# ESP32-POV.net
KiCad netlist of a schematic drawn in EAGLE
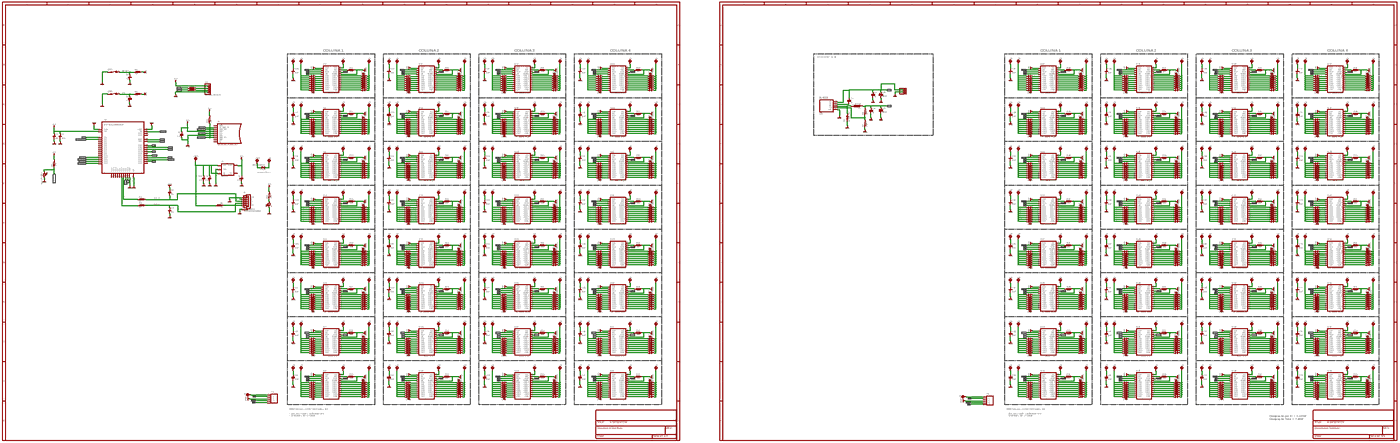
[diagram p0: schematic, sheet 1, overview]
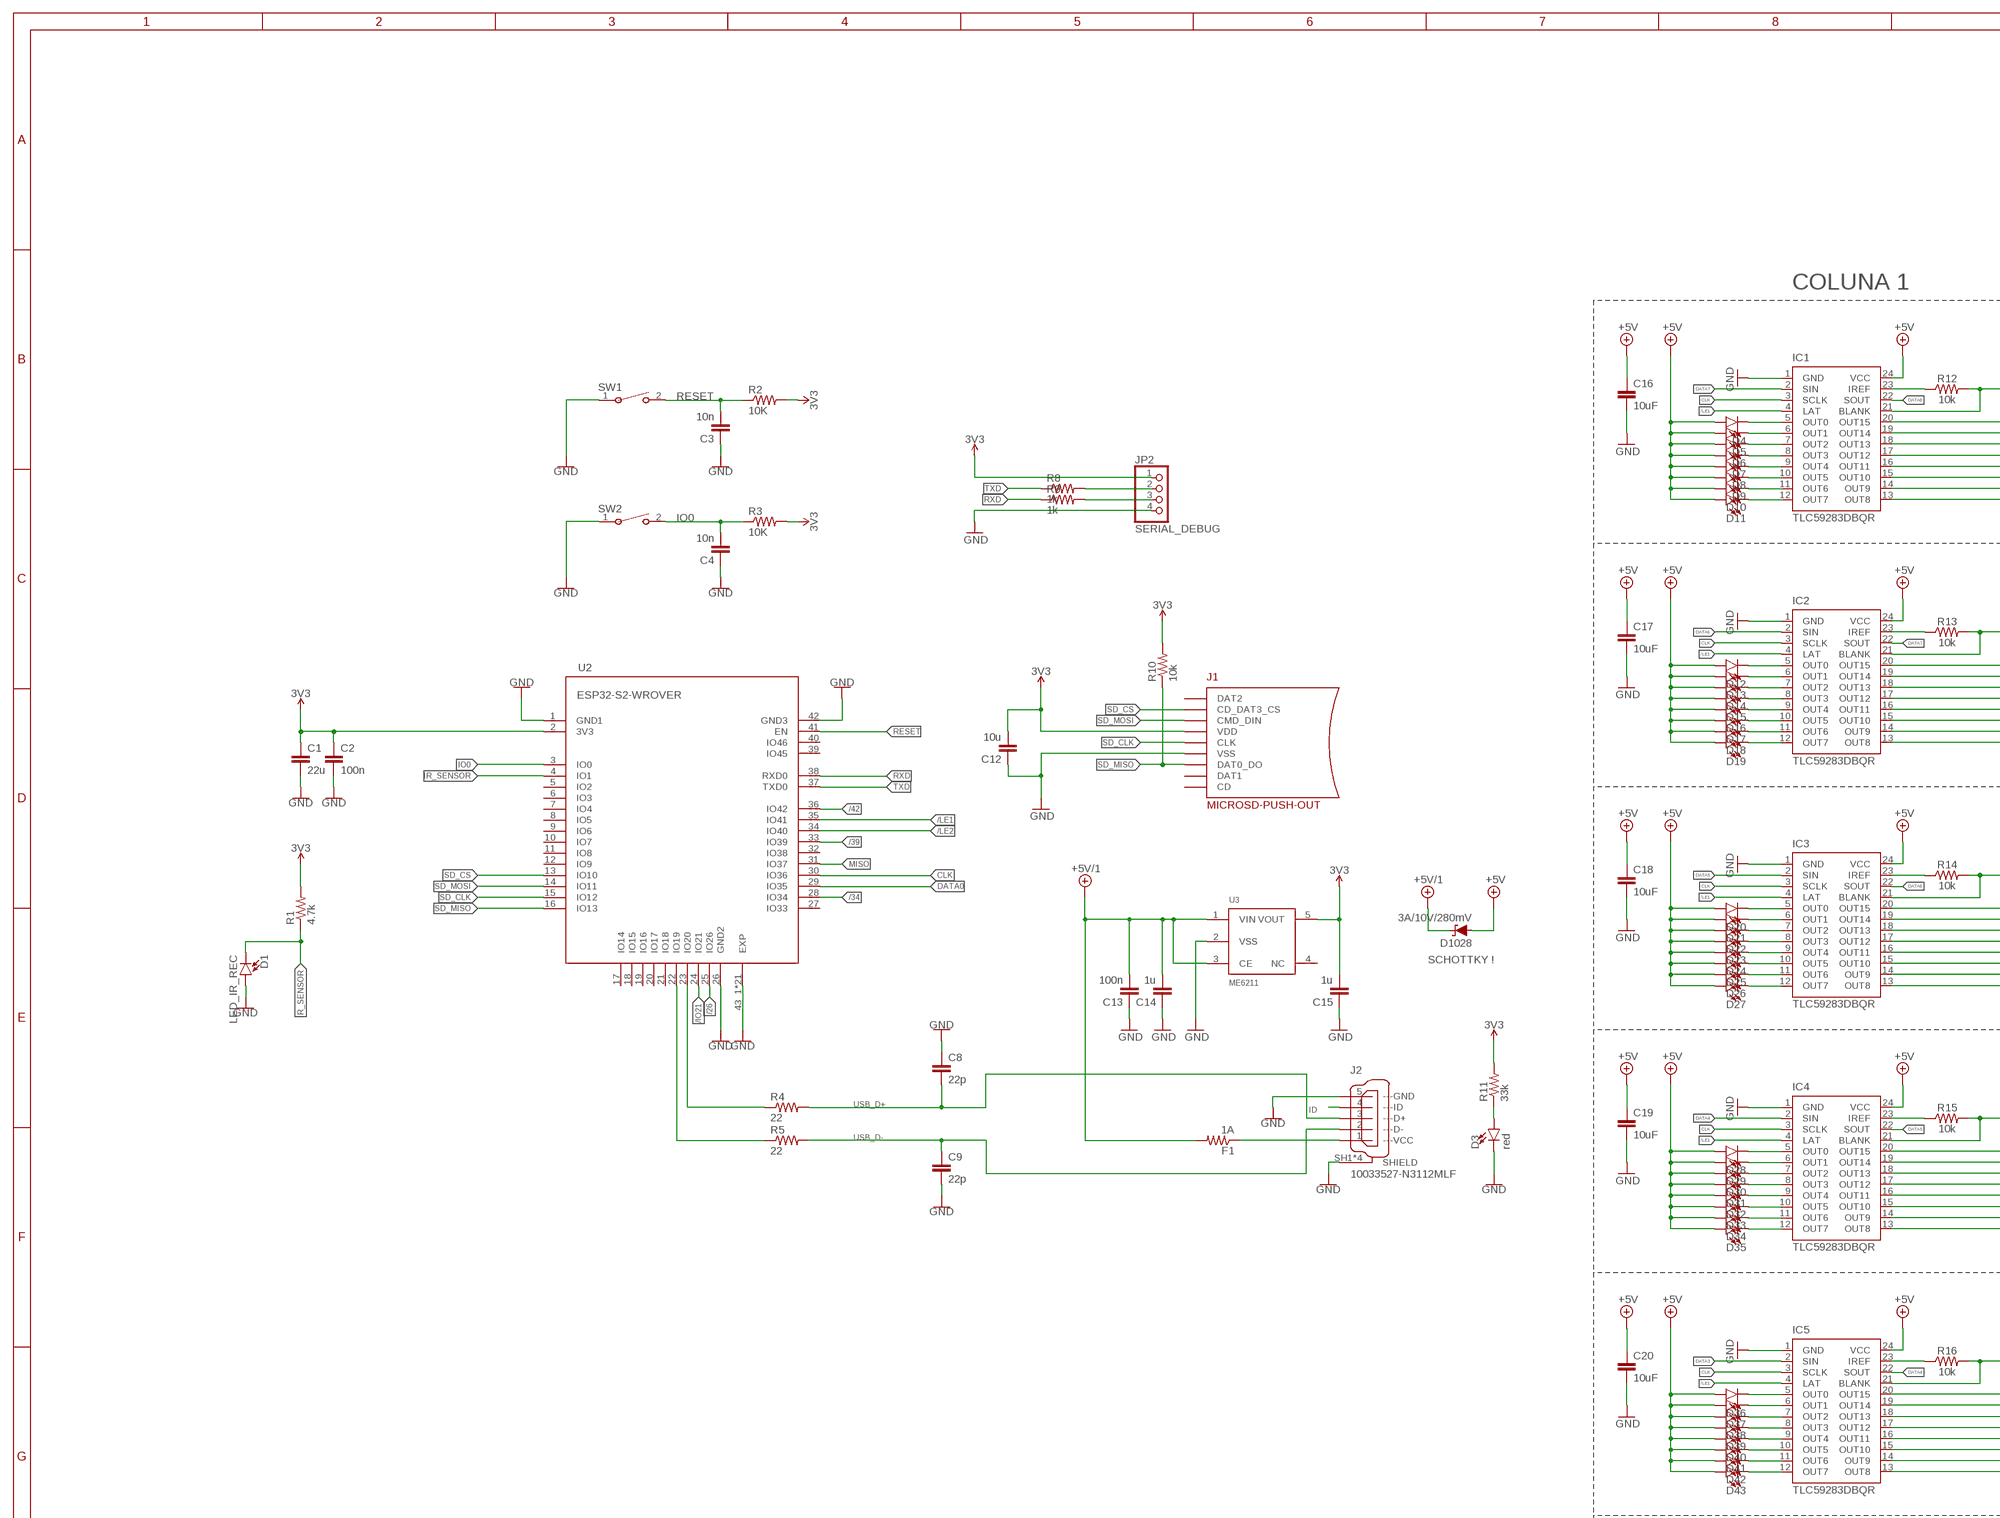
[diagram p1: schematic, sheet 1, part 1 of 8]
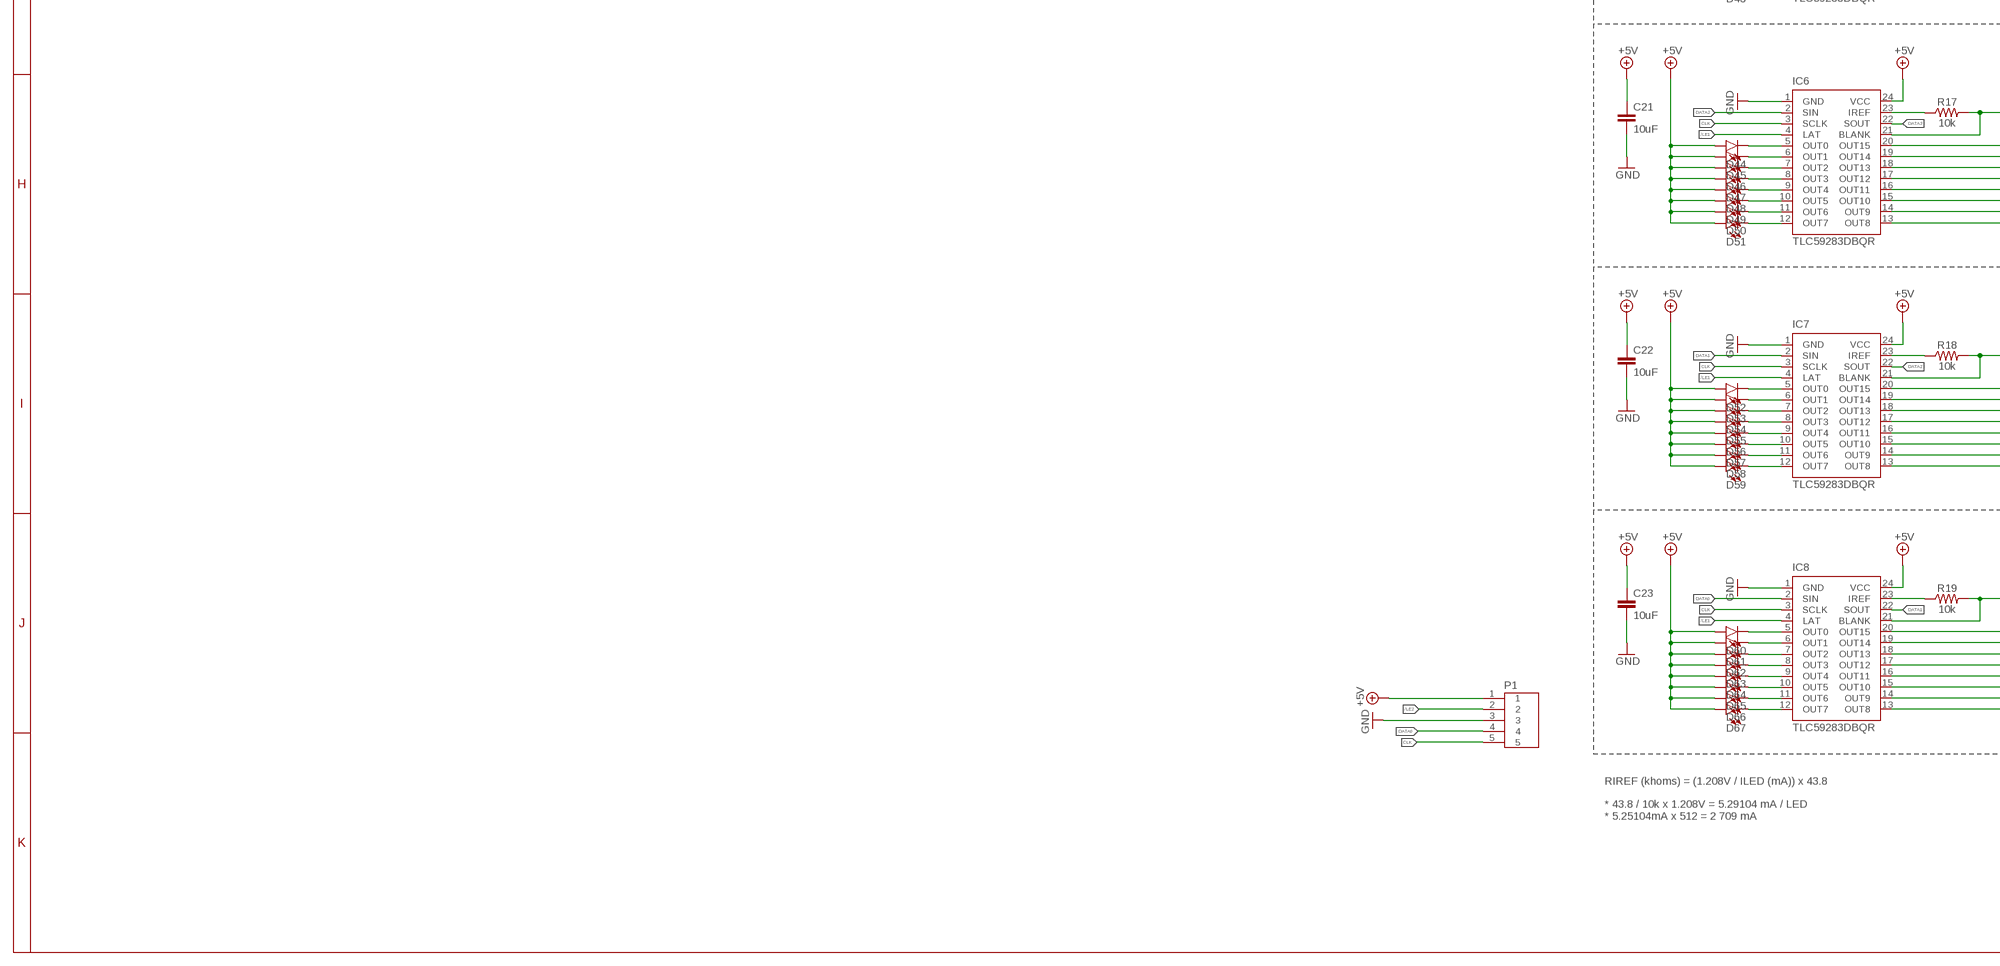
[diagram p2: schematic, sheet 1, part 2 of 8]
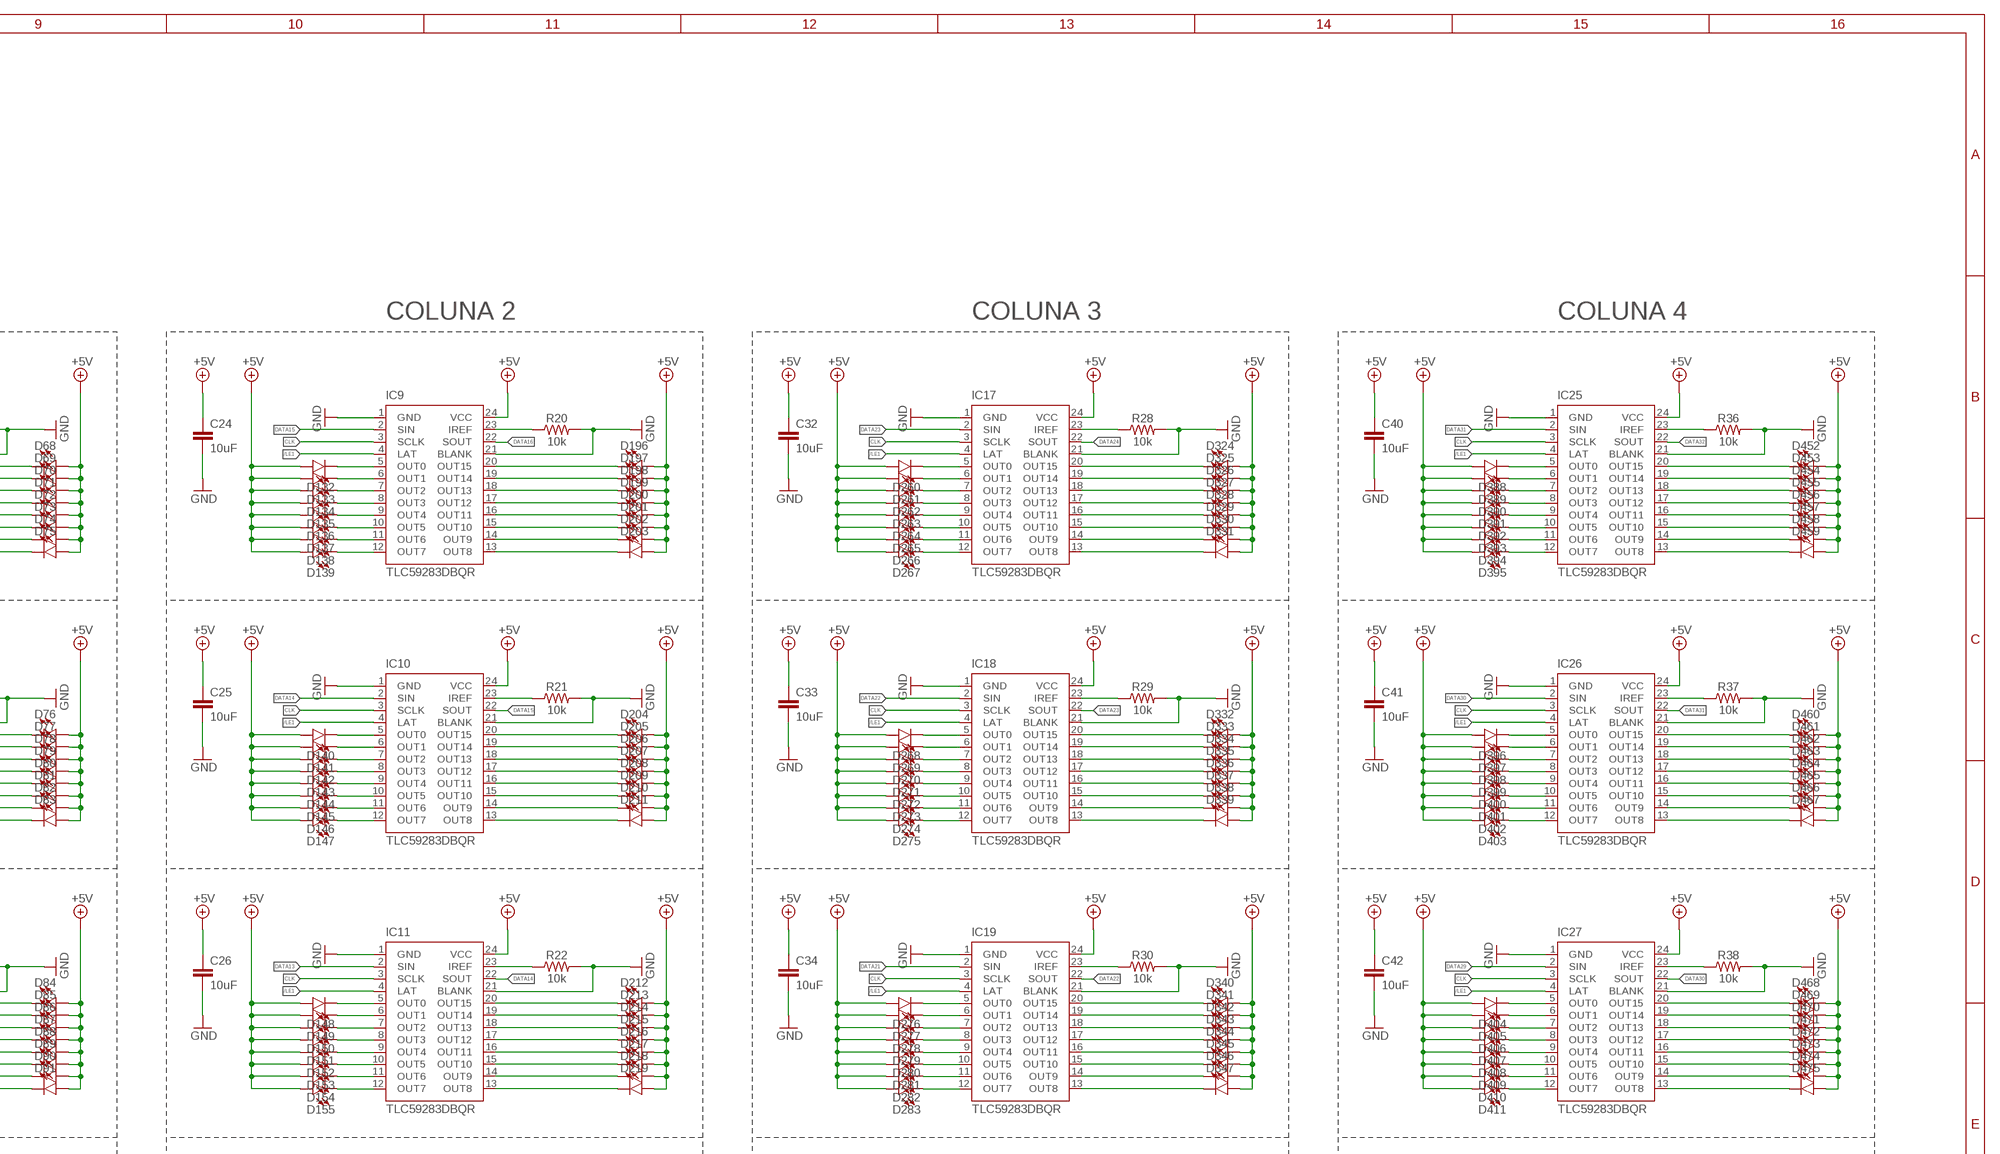
[diagram p3: schematic, sheet 1, part 3 of 8]
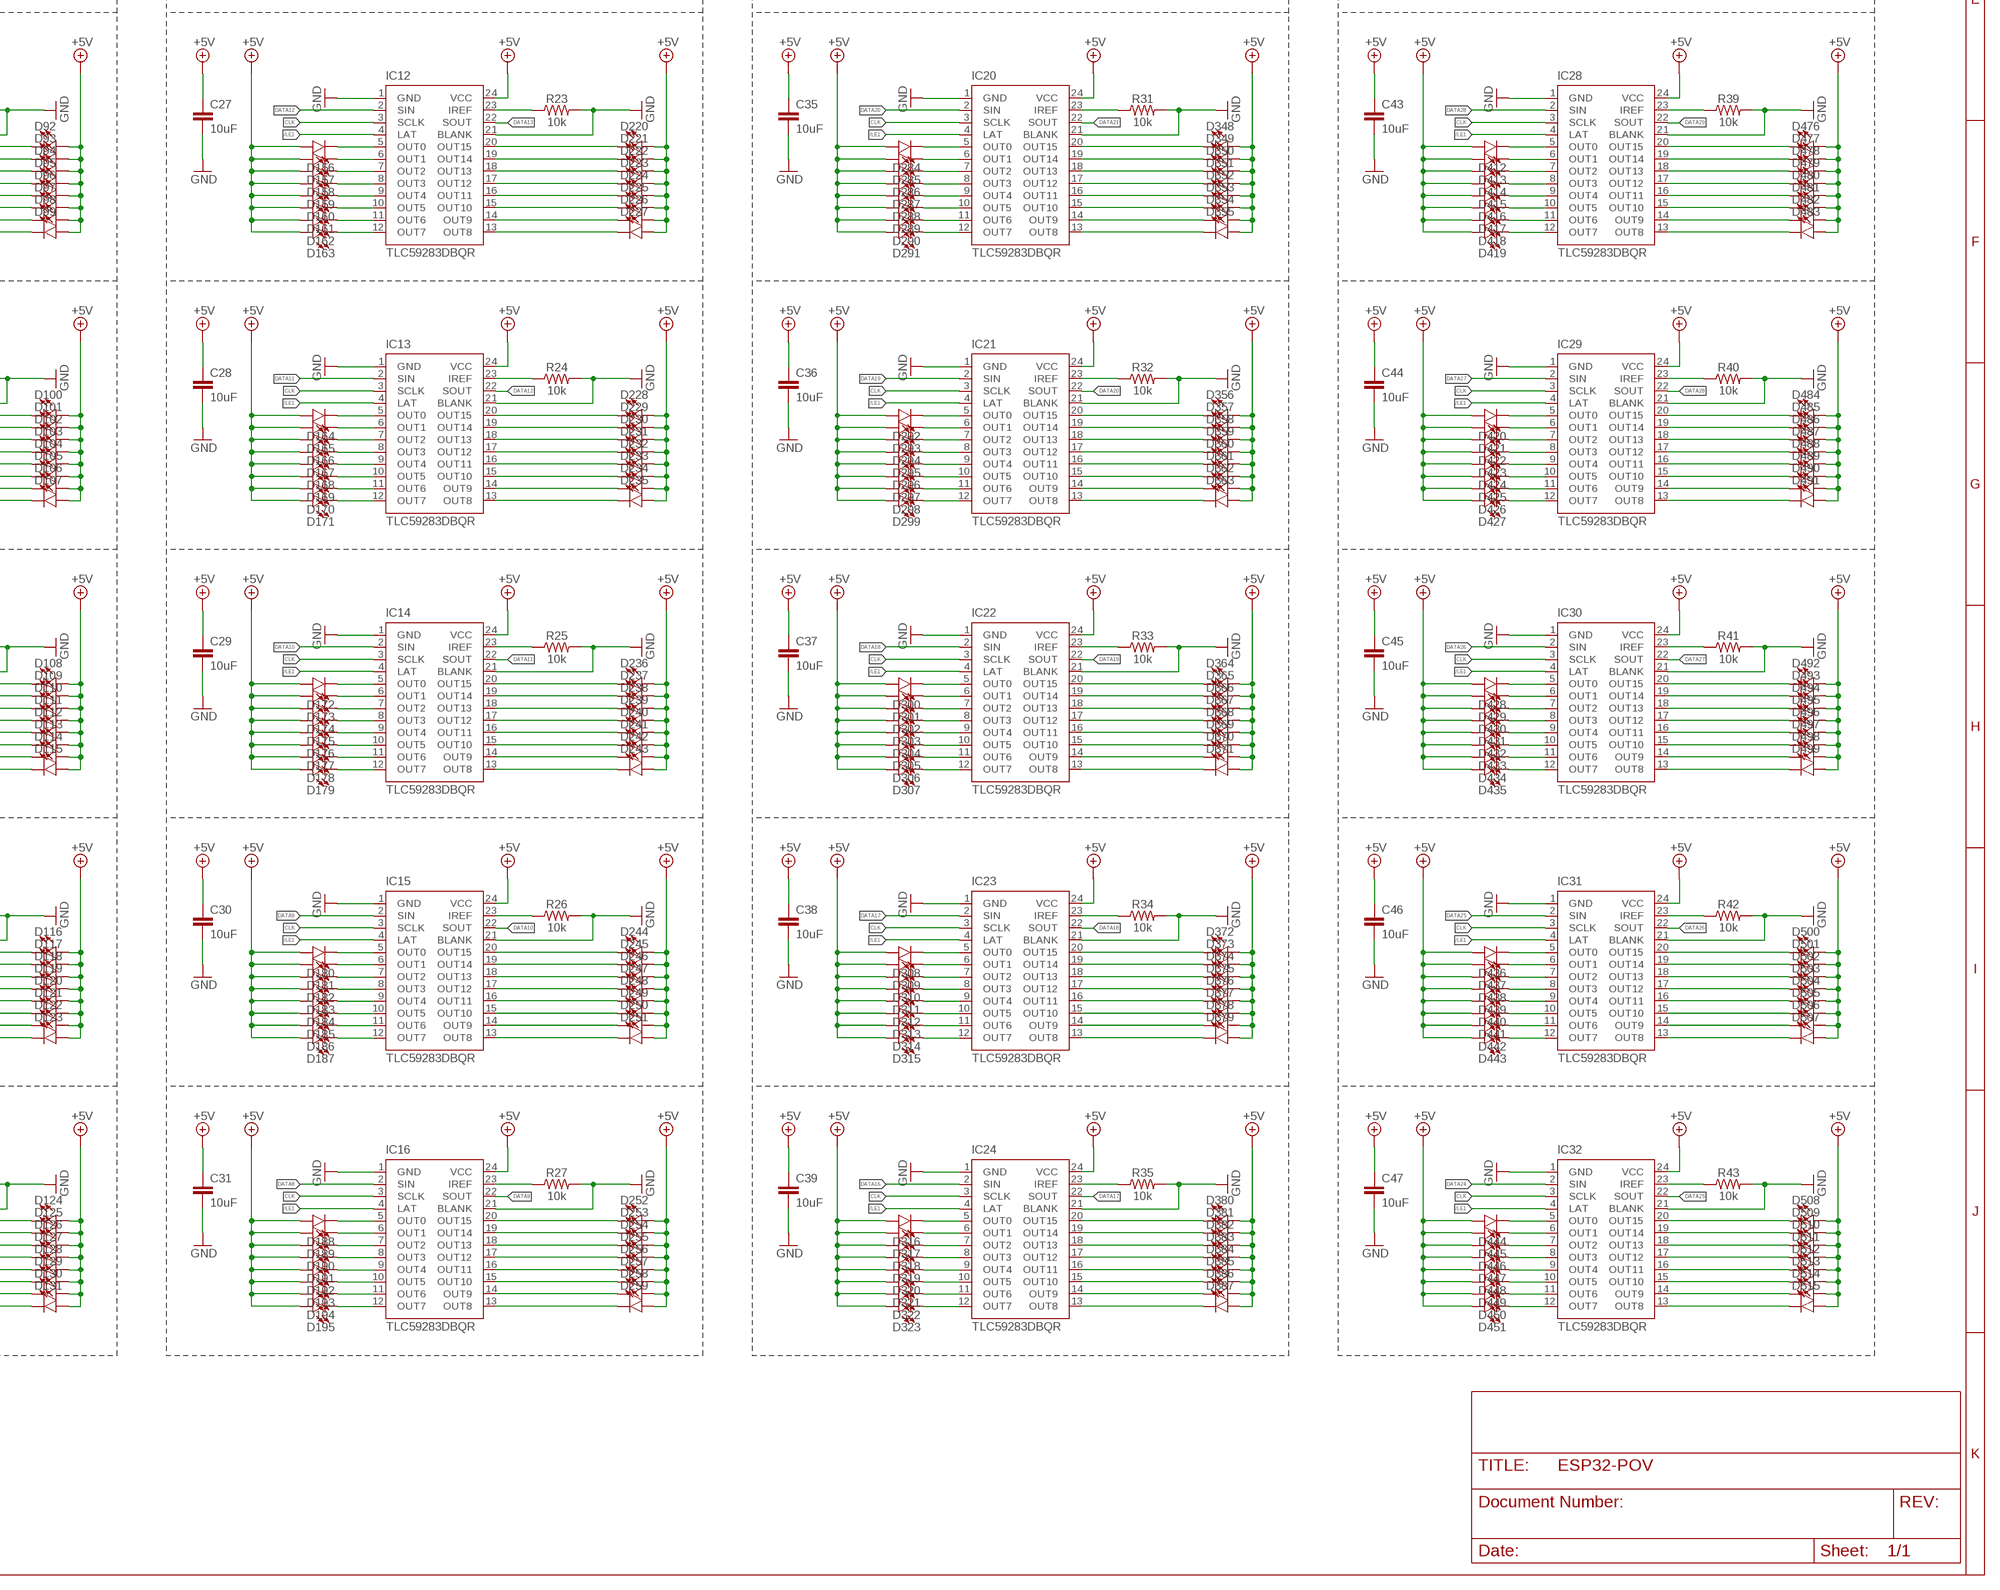
[diagram p4: schematic, sheet 1, part 4 of 8]
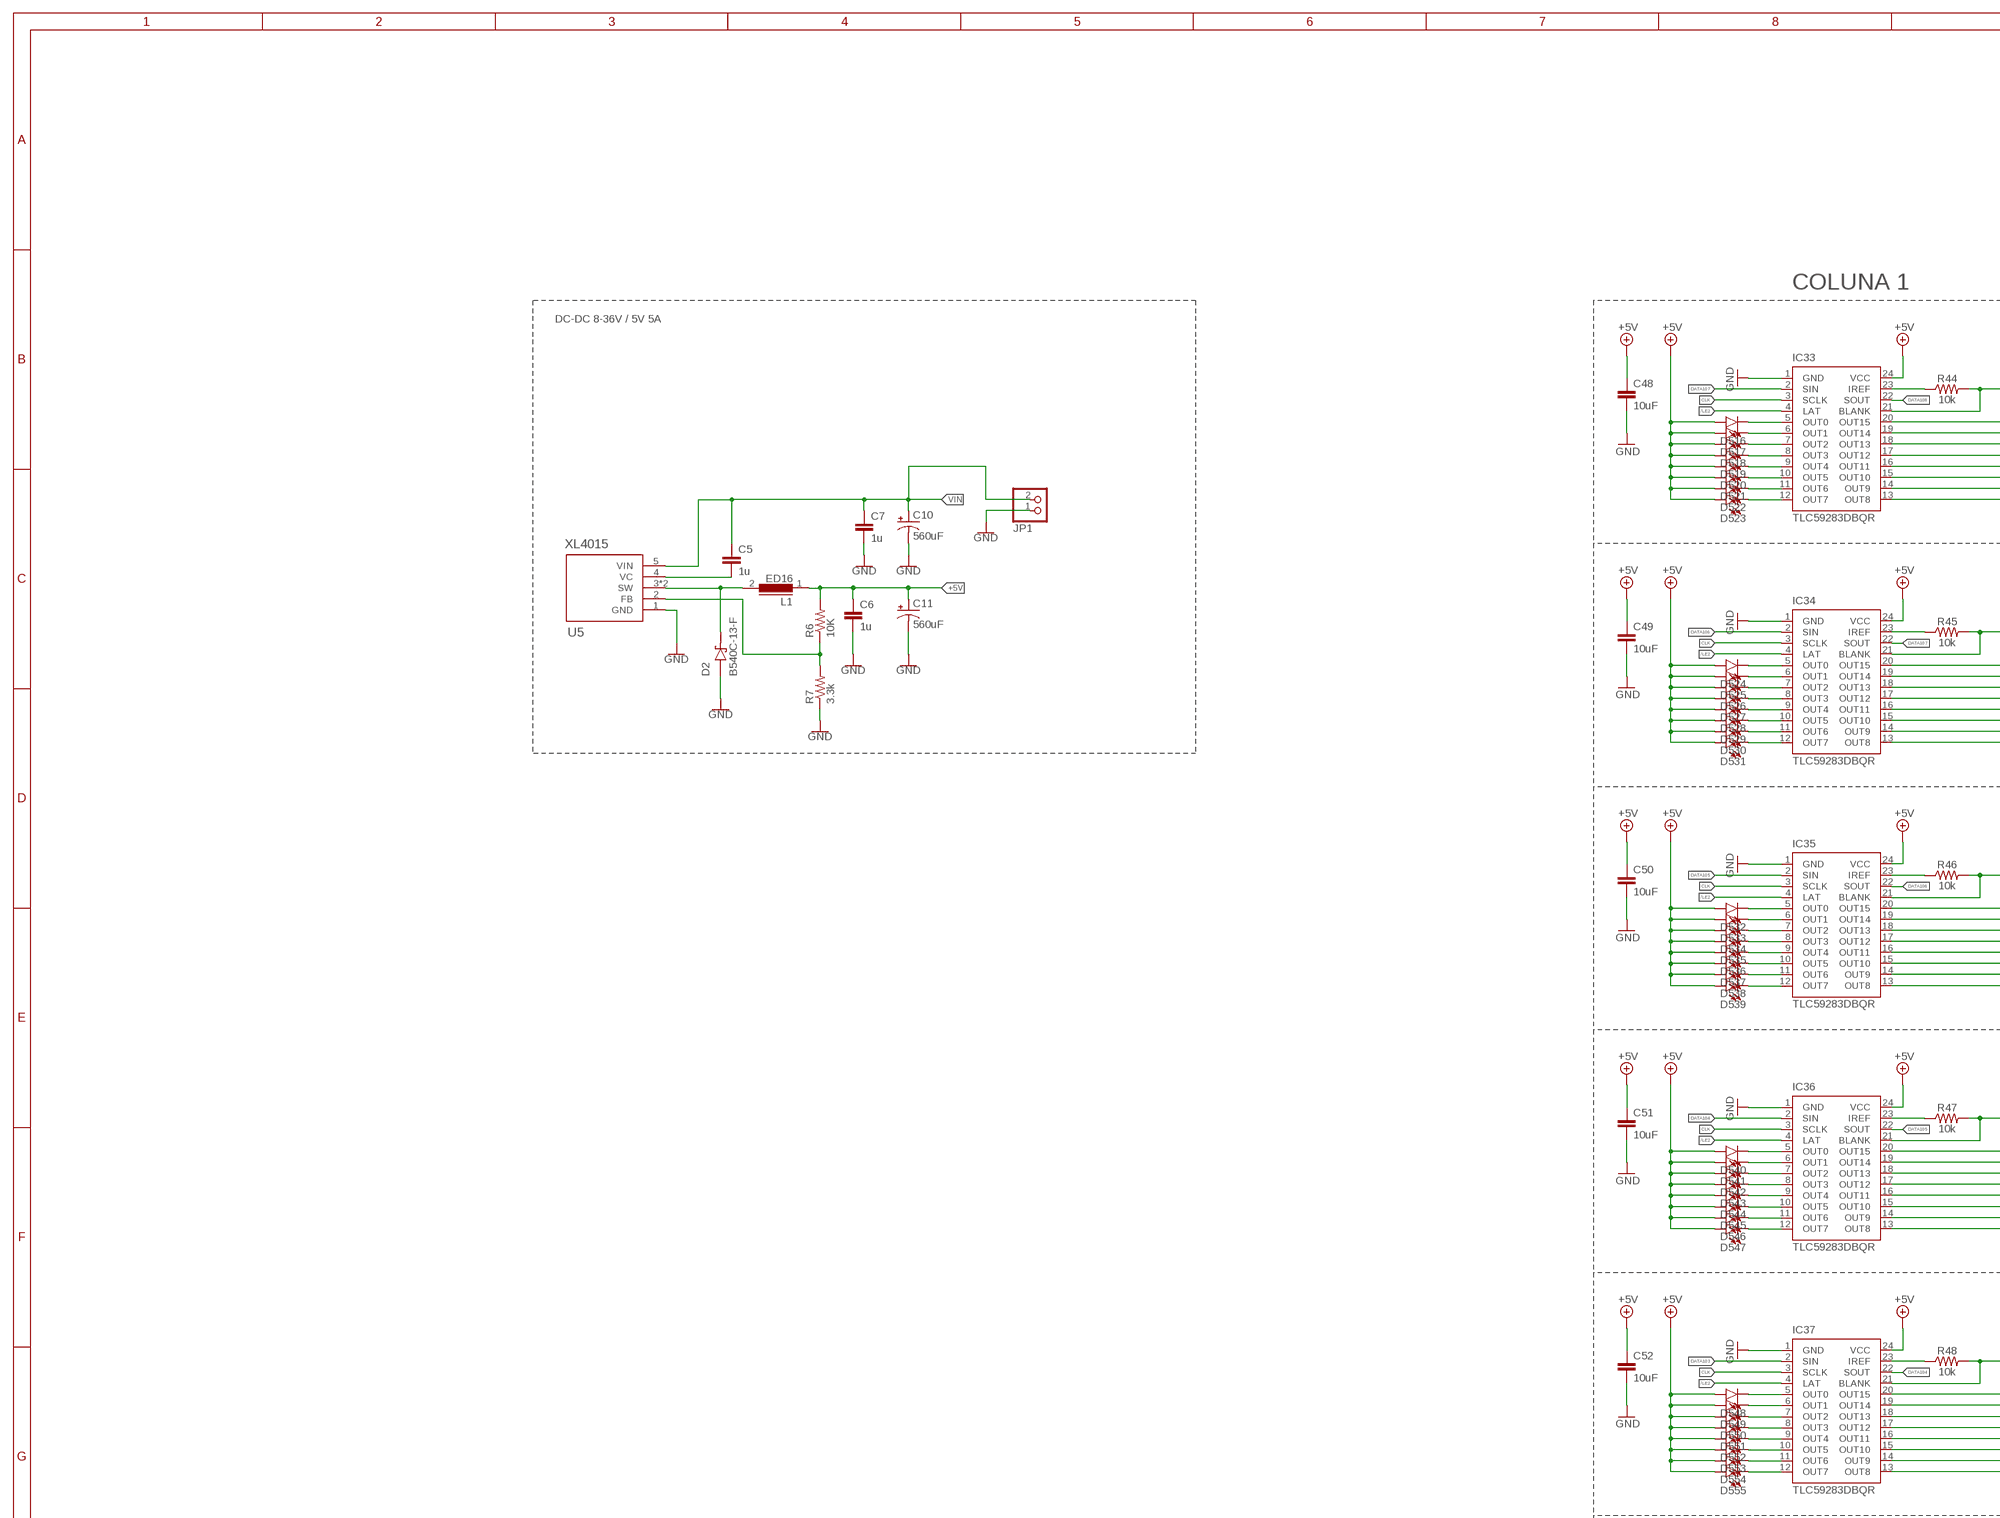
[diagram p5: schematic, sheet 1, part 5 of 8]
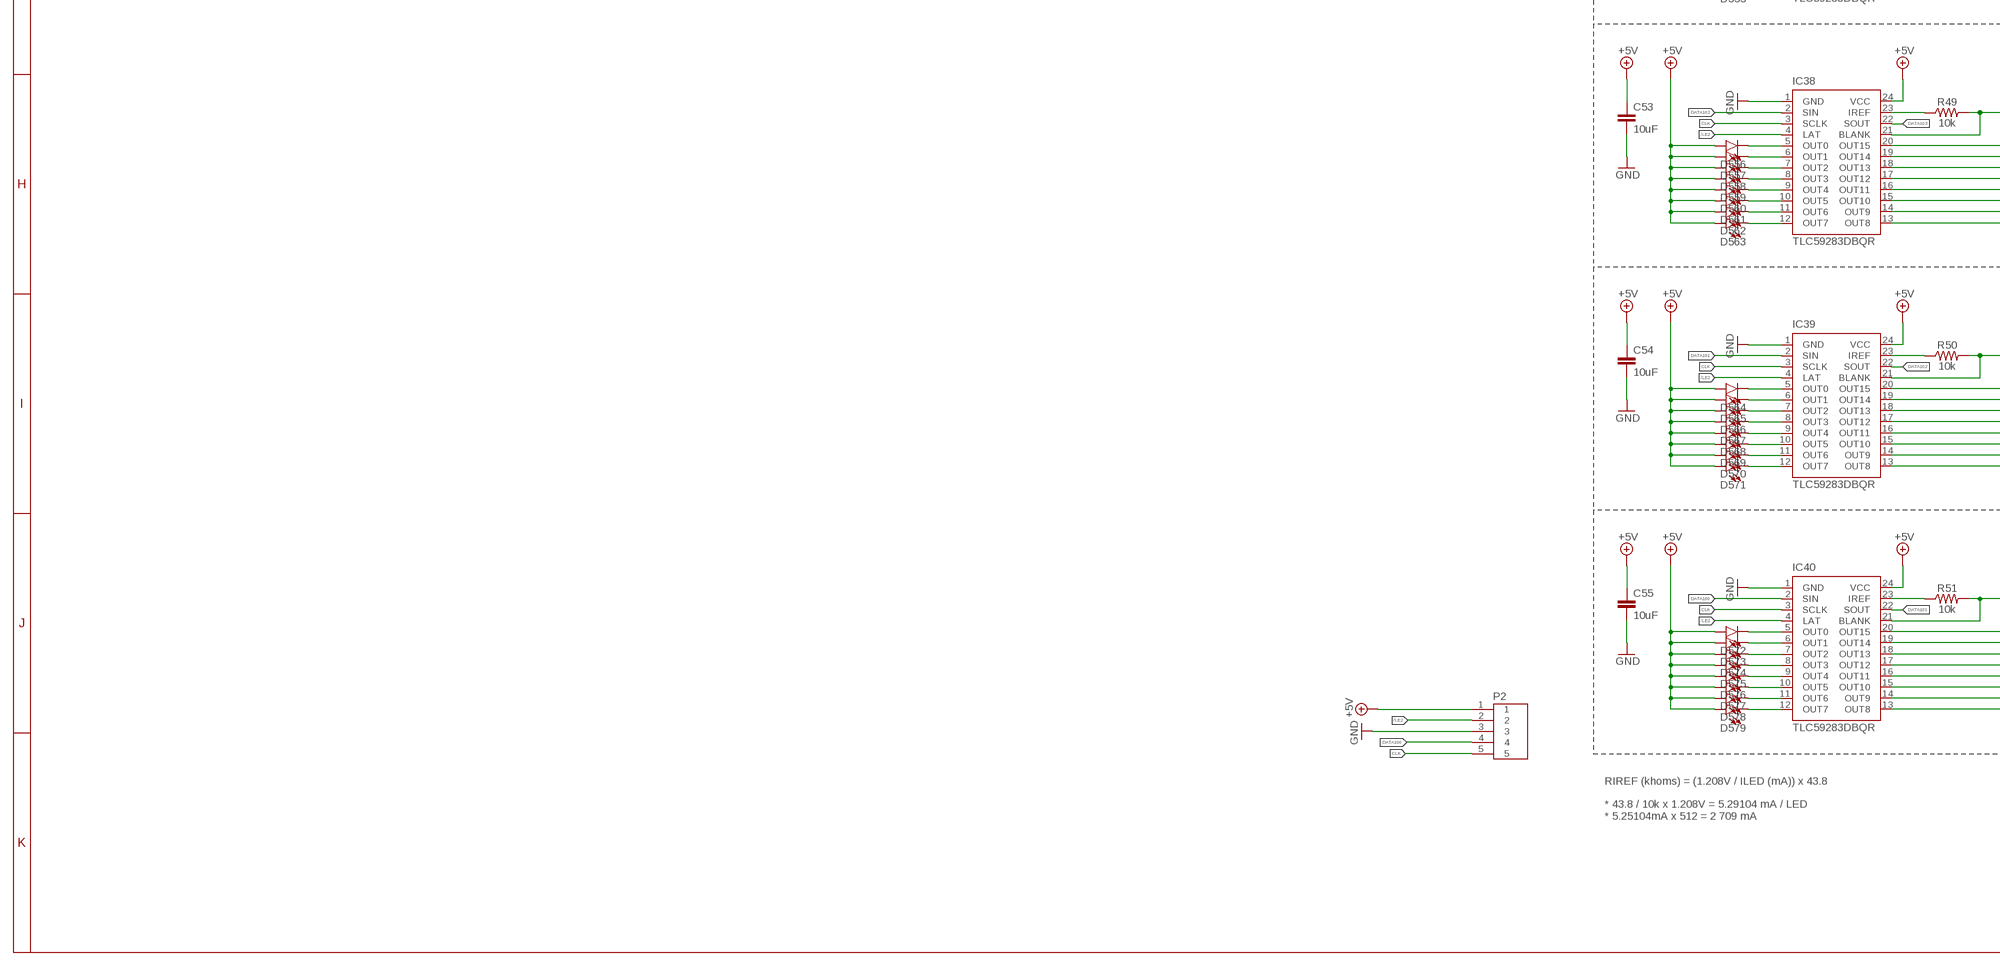
[diagram p6: schematic, sheet 1, part 6 of 8]
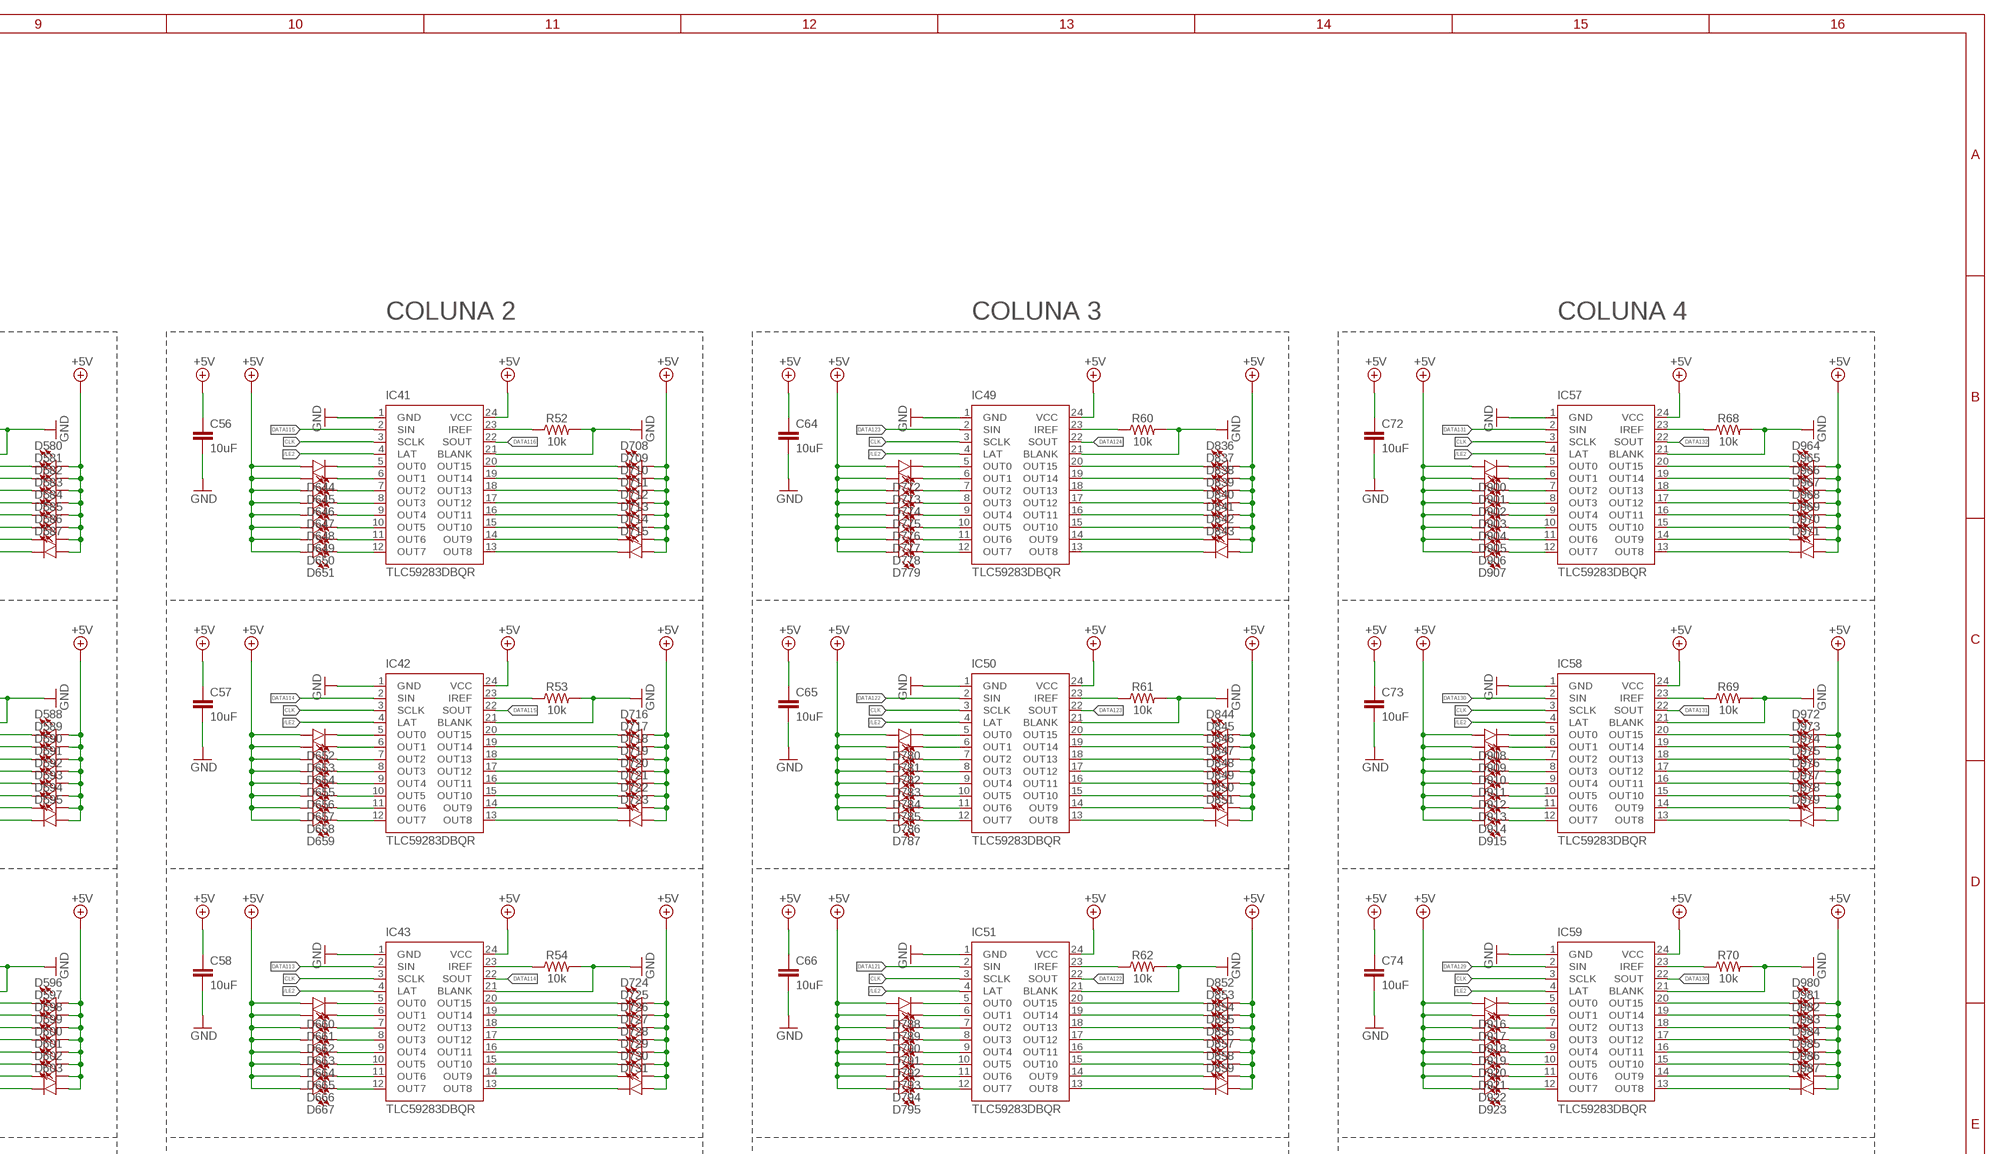
[diagram p7: schematic, sheet 1, part 7 of 8]
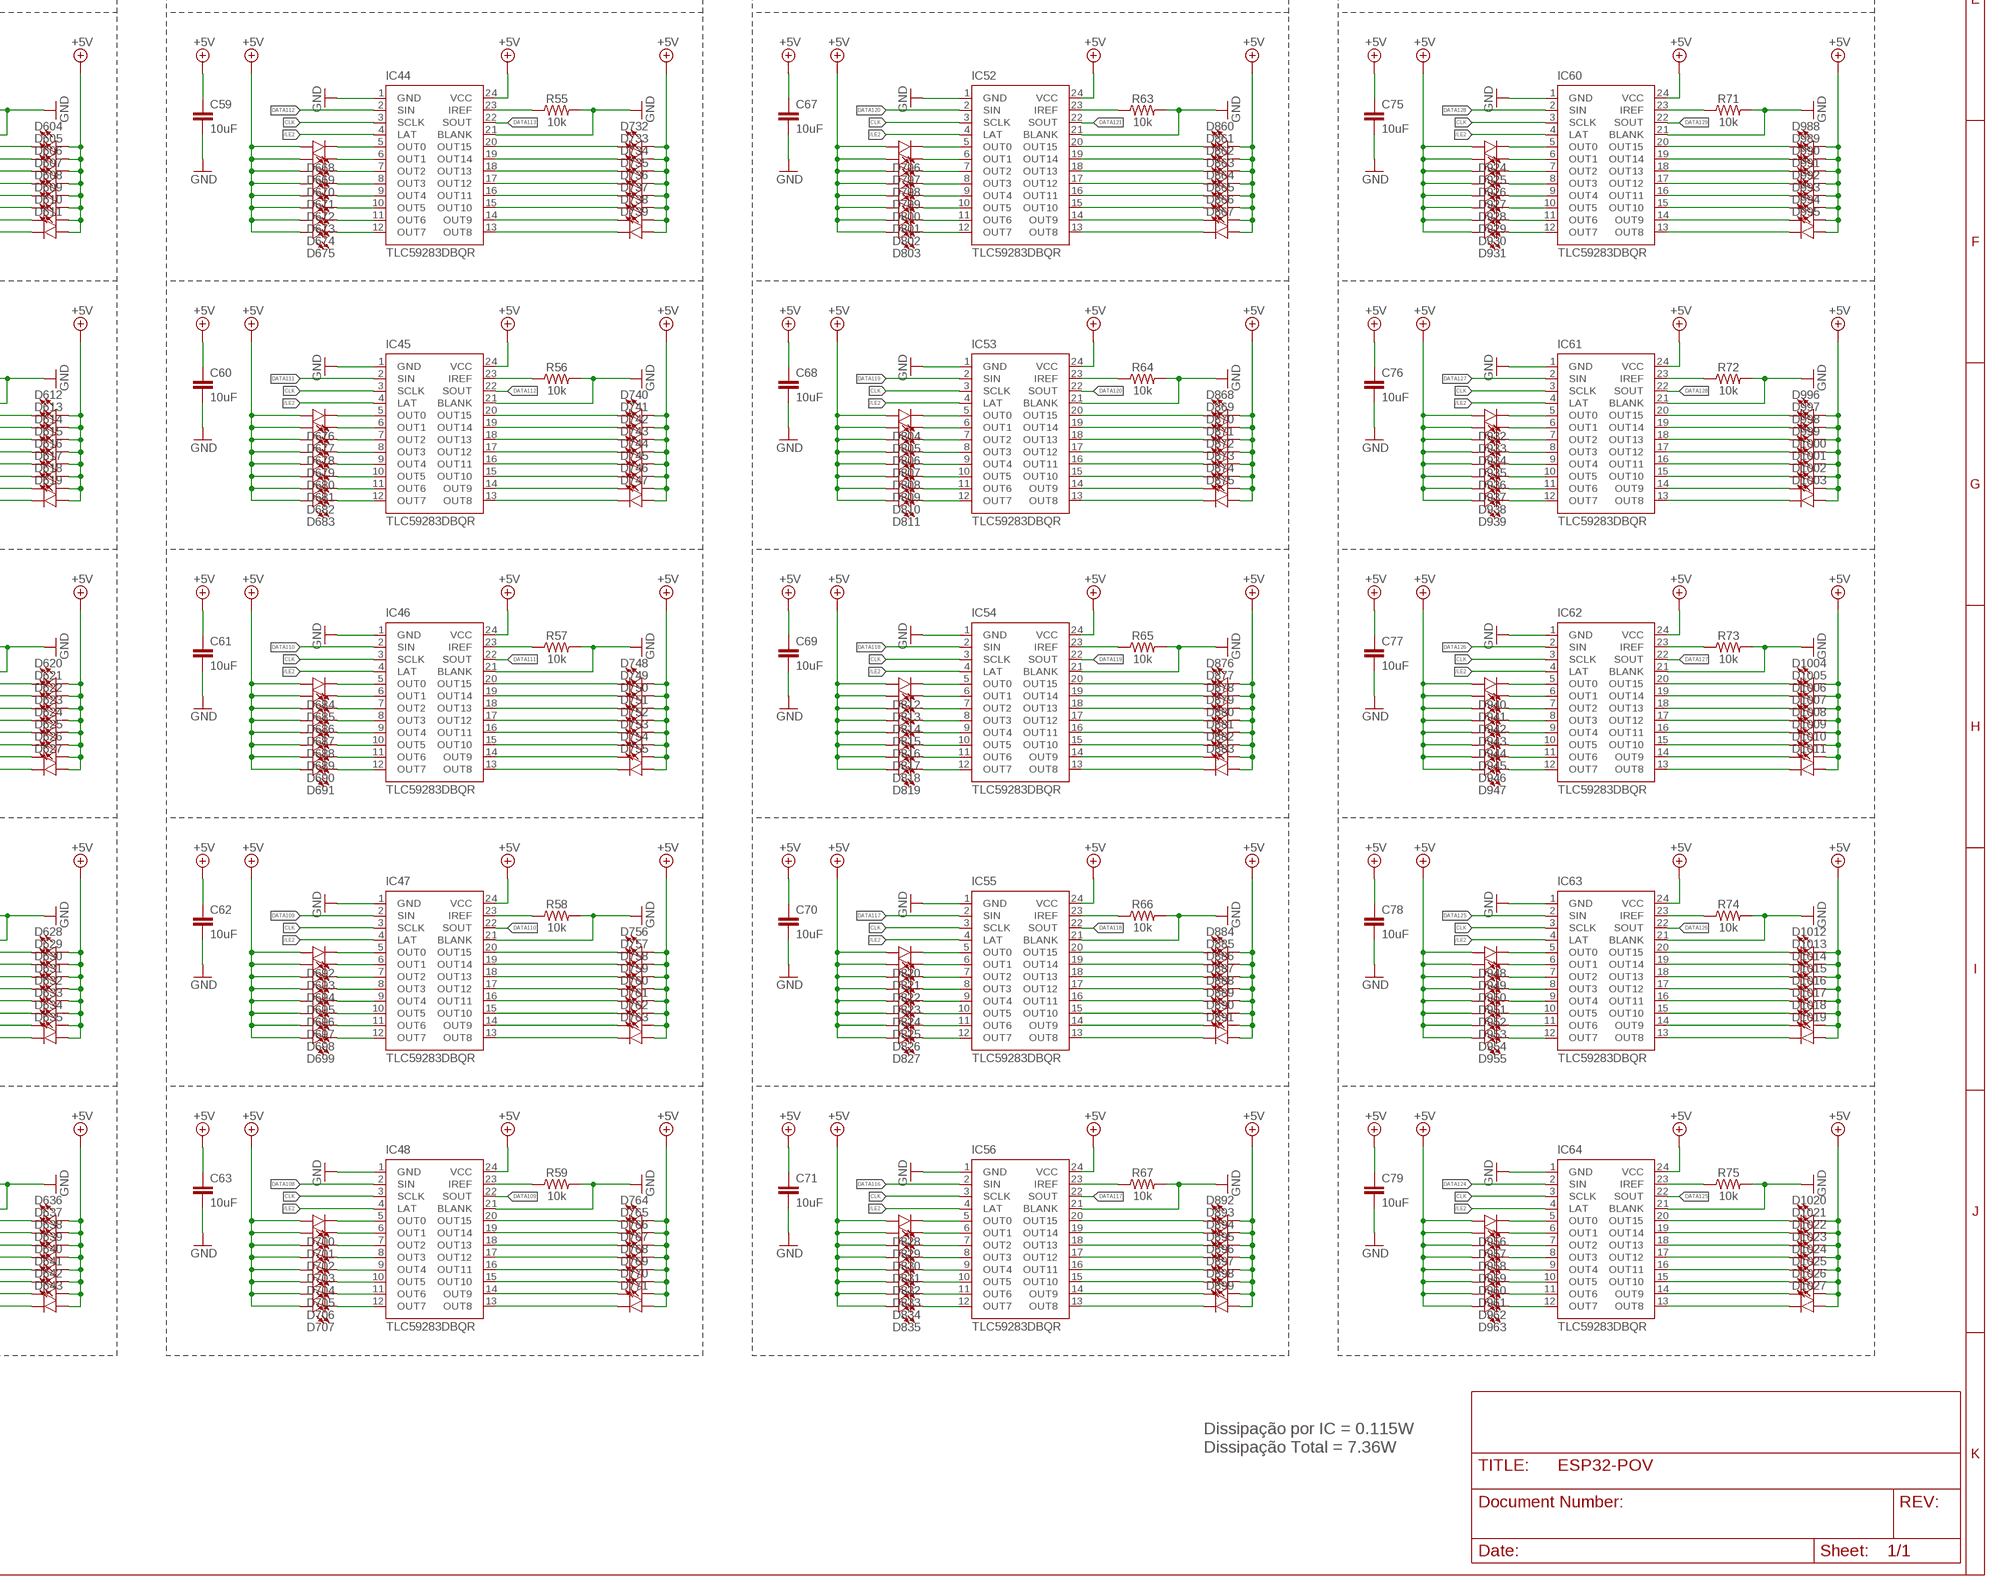
[diagram p8: schematic, sheet 1, part 8 of 8]

(export (version "E")
  (design (tool "Eeschema 10.0.6"))
  (components
    (comp (ref "C1")
      (value "22u")
      (footprint "eagle-import:1206")
      (libsource (lib "eagle-import") (part "CAP1206"))
    )
    (comp (ref "C2")
      (value "100n")
      (footprint "eagle-import:0805")
      (libsource (lib "eagle-import") (part "SparkFun-RC_CAP0805"))
    )
    (comp (ref "C3")
      (value "10n")
      (footprint "eagle-import:0805")
      (libsource (lib "eagle-import") (part "SparkFun-RC_CAP0805"))
    )
    (comp (ref "C4")
      (value "10n")
      (footprint "eagle-import:0805")
      (libsource (lib "eagle-import") (part "SparkFun-RC_CAP0805"))
    )
    (comp (ref "C5")
      (value "1u")
      (footprint "eagle-import:0805")
      (libsource (lib "eagle-import") (part "SparkFun-RC_CAP0805"))
    )
    (comp (ref "C6")
      (value "1u")
      (footprint "eagle-import:0805")
      (libsource (lib "eagle-import") (part "SparkFun-RC_CAP0805"))
    )
    (comp (ref "C7")
      (value "1u")
      (footprint "eagle-import:0805")
      (libsource (lib "eagle-import") (part "SparkFun-RC_CAP0805"))
    )
    (comp (ref "C8")
      (value "22p")
      (footprint "eagle-import:0805")
      (libsource (lib "eagle-import") (part "SparkFun-RC_CAP0805"))
    )
    (comp (ref "C9")
      (value "22p")
      (footprint "eagle-import:0805")
      (libsource (lib "eagle-import") (part "SparkFun-RC_CAP0805"))
    )
    (comp (ref "C10")
      (value "560uF")
      (footprint "eagle-import:PANASONIC_G")
      (libsource (lib "eagle-import") (part "560UF-PANASONIC_G-25V-20%"))
    )
    (comp (ref "C11")
      (value "560uF")
      (footprint "eagle-import:PANASONIC_G")
      (libsource (lib "eagle-import") (part "560UF-PANASONIC_G-25V-20%"))
    )
    (comp (ref "C12")
      (value "10u")
      (footprint "eagle-import:0805")
      (libsource (lib "eagle-import") (part "SparkFun-RC_CAP0805"))
    )
    (comp (ref "C13")
      (value "100n")
      (footprint "eagle-import:0805")
      (libsource (lib "eagle-import") (part "SparkFun-RC_CAP0805"))
    )
    (comp (ref "C14")
      (value "1u")
      (footprint "eagle-import:0805")
      (libsource (lib "eagle-import") (part "SparkFun-RC_CAP0805"))
    )
    (comp (ref "C15")
      (value "1u")
      (footprint "eagle-import:0805")
      (libsource (lib "eagle-import") (part "SparkFun-RC_CAP0805"))
    )
    (comp (ref "C16")
      (value "10uF")
      (footprint "eagle-import:0603")
      (libsource (lib "eagle-import") (part "10UF-0603-6.3V-20%"))
    )
    (comp (ref "C17")
      (value "10uF")
      (footprint "eagle-import:0603")
      (libsource (lib "eagle-import") (part "10UF-0603-6.3V-20%"))
    )
    (comp (ref "C18")
      (value "10uF")
      (footprint "eagle-import:0603")
      (libsource (lib "eagle-import") (part "10UF-0603-6.3V-20%"))
    )
    (comp (ref "C19")
      (value "10uF")
      (footprint "eagle-import:0603")
      (libsource (lib "eagle-import") (part "10UF-0603-6.3V-20%"))
    )
    (comp (ref "C20")
      (value "10uF")
      (footprint "eagle-import:0603")
      (libsource (lib "eagle-import") (part "10UF-0603-6.3V-20%"))
    )
    (comp (ref "C21")
      (value "10uF")
      (footprint "eagle-import:0603")
      (libsource (lib "eagle-import") (part "10UF-0603-6.3V-20%"))
    )
    (comp (ref "C22")
      (value "10uF")
      (footprint "eagle-import:0603")
      (libsource (lib "eagle-import") (part "10UF-0603-6.3V-20%"))
    )
    (comp (ref "C23")
      (value "10uF")
      (footprint "eagle-import:0603")
      (libsource (lib "eagle-import") (part "10UF-0603-6.3V-20%"))
    )
    (comp (ref "C24")
      (value "10uF")
      (footprint "eagle-import:0603")
      (libsource (lib "eagle-import") (part "10UF-0603-6.3V-20%"))
    )
    (comp (ref "C25")
      (value "10uF")
      (footprint "eagle-import:0603")
      (libsource (lib "eagle-import") (part "10UF-0603-6.3V-20%"))
    )
    (comp (ref "C26")
      (value "10uF")
      (footprint "eagle-import:0603")
      (libsource (lib "eagle-import") (part "10UF-0603-6.3V-20%"))
    )
    (comp (ref "C27")
      (value "10uF")
      (footprint "eagle-import:0603")
      (libsource (lib "eagle-import") (part "10UF-0603-6.3V-20%"))
    )
    (comp (ref "C28")
      (value "10uF")
      (footprint "eagle-import:0603")
      (libsource (lib "eagle-import") (part "10UF-0603-6.3V-20%"))
    )
    (comp (ref "C29")
      (value "10uF")
      (footprint "eagle-import:0603")
      (libsource (lib "eagle-import") (part "10UF-0603-6.3V-20%"))
    )
    (comp (ref "C30")
      (value "10uF")
      (footprint "eagle-import:0603")
      (libsource (lib "eagle-import") (part "10UF-0603-6.3V-20%"))
    )
    (comp (ref "C31")
      (value "10uF")
      (footprint "eagle-import:0603")
      (libsource (lib "eagle-import") (part "10UF-0603-6.3V-20%"))
    )
    (comp (ref "C32")
      (value "10uF")
      (footprint "eagle-import:0603")
      (libsource (lib "eagle-import") (part "10UF-0603-6.3V-20%"))
    )
    (comp (ref "C33")
      (value "10uF")
      (footprint "eagle-import:0603")
      (libsource (lib "eagle-import") (part "10UF-0603-6.3V-20%"))
    )
    (comp (ref "C34")
      (value "10uF")
      (footprint "eagle-import:0603")
      (libsource (lib "eagle-import") (part "10UF-0603-6.3V-20%"))
    )
    (comp (ref "C35")
      (value "10uF")
      (footprint "eagle-import:0603")
      (libsource (lib "eagle-import") (part "10UF-0603-6.3V-20%"))
    )
    (comp (ref "C36")
      (value "10uF")
      (footprint "eagle-import:0603")
      (libsource (lib "eagle-import") (part "10UF-0603-6.3V-20%"))
    )
    (comp (ref "C37")
      (value "10uF")
      (footprint "eagle-import:0603")
      (libsource (lib "eagle-import") (part "10UF-0603-6.3V-20%"))
    )
    (comp (ref "C38")
      (value "10uF")
      (footprint "eagle-import:0603")
      (libsource (lib "eagle-import") (part "10UF-0603-6.3V-20%"))
    )
    (comp (ref "C39")
      (value "10uF")
      (footprint "eagle-import:0603")
      (libsource (lib "eagle-import") (part "10UF-0603-6.3V-20%"))
    )
    (comp (ref "C40")
      (value "10uF")
      (footprint "eagle-import:0603")
      (libsource (lib "eagle-import") (part "10UF-0603-6.3V-20%"))
    )
    (comp (ref "C41")
      (value "10uF")
      (footprint "eagle-import:0603")
      (libsource (lib "eagle-import") (part "10UF-0603-6.3V-20%"))
    )
    (comp (ref "C42")
      (value "10uF")
      (footprint "eagle-import:0603")
      (libsource (lib "eagle-import") (part "10UF-0603-6.3V-20%"))
    )
    (comp (ref "C43")
      (value "10uF")
      (footprint "eagle-import:0603")
      (libsource (lib "eagle-import") (part "10UF-0603-6.3V-20%"))
    )
    (comp (ref "C44")
      (value "10uF")
      (footprint "eagle-import:0603")
      (libsource (lib "eagle-import") (part "10UF-0603-6.3V-20%"))
    )
    (comp (ref "C45")
      (value "10uF")
      (footprint "eagle-import:0603")
      (libsource (lib "eagle-import") (part "10UF-0603-6.3V-20%"))
    )
    (comp (ref "C46")
      (value "10uF")
      (footprint "eagle-import:0603")
      (libsource (lib "eagle-import") (part "10UF-0603-6.3V-20%"))
    )
    (comp (ref "C47")
      (value "10uF")
      (footprint "eagle-import:0603")
      (libsource (lib "eagle-import") (part "10UF-0603-6.3V-20%"))
    )
    (comp (ref "C48")
      (value "10uF")
      (footprint "eagle-import:0603")
      (libsource (lib "eagle-import") (part "10UF-0603-6.3V-20%"))
    )
    (comp (ref "C49")
      (value "10uF")
      (footprint "eagle-import:0603")
      (libsource (lib "eagle-import") (part "10UF-0603-6.3V-20%"))
    )
    (comp (ref "C50")
      (value "10uF")
      (footprint "eagle-import:0603")
      (libsource (lib "eagle-import") (part "10UF-0603-6.3V-20%"))
    )
    (comp (ref "C51")
      (value "10uF")
      (footprint "eagle-import:0603")
      (libsource (lib "eagle-import") (part "10UF-0603-6.3V-20%"))
    )
    (comp (ref "C52")
      (value "10uF")
      (footprint "eagle-import:0603")
      (libsource (lib "eagle-import") (part "10UF-0603-6.3V-20%"))
    )
    (comp (ref "C53")
      (value "10uF")
      (footprint "eagle-import:0603")
      (libsource (lib "eagle-import") (part "10UF-0603-6.3V-20%"))
    )
    (comp (ref "C54")
      (value "10uF")
      (footprint "eagle-import:0603")
      (libsource (lib "eagle-import") (part "10UF-0603-6.3V-20%"))
    )
    (comp (ref "C55")
      (value "10uF")
      (footprint "eagle-import:0603")
      (libsource (lib "eagle-import") (part "10UF-0603-6.3V-20%"))
    )
    (comp (ref "C56")
      (value "10uF")
      (footprint "eagle-import:0603")
      (libsource (lib "eagle-import") (part "10UF-0603-6.3V-20%"))
    )
    (comp (ref "C57")
      (value "10uF")
      (footprint "eagle-import:0603")
      (libsource (lib "eagle-import") (part "10UF-0603-6.3V-20%"))
    )
    (comp (ref "C58")
      (value "10uF")
      (footprint "eagle-import:0603")
      (libsource (lib "eagle-import") (part "10UF-0603-6.3V-20%"))
    )
    (comp (ref "C59")
      (value "10uF")
      (footprint "eagle-import:0603")
      (libsource (lib "eagle-import") (part "10UF-0603-6.3V-20%"))
    )
    (comp (ref "C60")
      (value "10uF")
      (footprint "eagle-import:0603")
      (libsource (lib "eagle-import") (part "10UF-0603-6.3V-20%"))
    )
    (comp (ref "C61")
      (value "10uF")
      (footprint "eagle-import:0603")
      (libsource (lib "eagle-import") (part "10UF-0603-6.3V-20%"))
    )
    (comp (ref "C62")
      (value "10uF")
      (footprint "eagle-import:0603")
      (libsource (lib "eagle-import") (part "10UF-0603-6.3V-20%"))
    )
    (comp (ref "C63")
      (value "10uF")
      (footprint "eagle-import:0603")
      (libsource (lib "eagle-import") (part "10UF-0603-6.3V-20%"))
    )
    (comp (ref "C64")
      (value "10uF")
      (footprint "eagle-import:0603")
      (libsource (lib "eagle-import") (part "10UF-0603-6.3V-20%"))
    )
    (comp (ref "C65")
      (value "10uF")
      (footprint "eagle-import:0603")
      (libsource (lib "eagle-import") (part "10UF-0603-6.3V-20%"))
    )
    (comp (ref "C66")
      (value "10uF")
      (footprint "eagle-import:0603")
      (libsource (lib "eagle-import") (part "10UF-0603-6.3V-20%"))
    )
    (comp (ref "C67")
      (value "10uF")
      (footprint "eagle-import:0603")
      (libsource (lib "eagle-import") (part "10UF-0603-6.3V-20%"))
    )
    (comp (ref "C68")
      (value "10uF")
      (footprint "eagle-import:0603")
      (libsource (lib "eagle-import") (part "10UF-0603-6.3V-20%"))
    )
    (comp (ref "C69")
      (value "10uF")
      (footprint "eagle-import:0603")
      (libsource (lib "eagle-import") (part "10UF-0603-6.3V-20%"))
    )
    (comp (ref "C70")
      (value "10uF")
      (footprint "eagle-import:0603")
      (libsource (lib "eagle-import") (part "10UF-0603-6.3V-20%"))
    )
    (comp (ref "C71")
      (value "10uF")
      (footprint "eagle-import:0603")
      (libsource (lib "eagle-import") (part "10UF-0603-6.3V-20%"))
    )
    (comp (ref "C72")
      (value "10uF")
      (footprint "eagle-import:0603")
      (libsource (lib "eagle-import") (part "10UF-0603-6.3V-20%"))
    )
    (comp (ref "C73")
      (value "10uF")
      (footprint "eagle-import:0603")
      (libsource (lib "eagle-import") (part "10UF-0603-6.3V-20%"))
    )
    (comp (ref "C74")
      (value "10uF")
      (footprint "eagle-import:0603")
      (libsource (lib "eagle-import") (part "10UF-0603-6.3V-20%"))
    )
    (comp (ref "C75")
      (value "10uF")
      (footprint "eagle-import:0603")
      (libsource (lib "eagle-import") (part "10UF-0603-6.3V-20%"))
    )
    (comp (ref "C76")
      (value "10uF")
      (footprint "eagle-import:0603")
      (libsource (lib "eagle-import") (part "10UF-0603-6.3V-20%"))
    )
    (comp (ref "C77")
      (value "10uF")
      (footprint "eagle-import:0603")
      (libsource (lib "eagle-import") (part "10UF-0603-6.3V-20%"))
    )
    (comp (ref "C78")
      (value "10uF")
      (footprint "eagle-import:0603")
      (libsource (lib "eagle-import") (part "10UF-0603-6.3V-20%"))
    )
    (comp (ref "C79")
      (value "10uF")
      (footprint "eagle-import:0603")
      (libsource (lib "eagle-import") (part "10UF-0603-6.3V-20%"))
    )
    (comp (ref "D1")
      (value "LED_IR_REC")
      (footprint "eagle-import:LED_IR_REC")
      (libsource (lib "eagle-import") (part "LED_IR_REC"))
    )
    (comp (ref "D2")
      (value "B540C-13-F")
      (footprint "eagle-import:DIOM6959X245N")
      (fields (field (name "MANUFACTURER") "multicomp"))
      (libsource (lib "eagle-import") (part "B540C-13-F"))
    )
    (comp (ref "D3")
      (value "red")
      (footprint "eagle-import:LED-0805")
      (libsource (lib "eagle-import") (part "LED-RED-0805"))
    )
    (comp (ref "D4")
      (value "LED-BLUE0603")
      (footprint "eagle-import:LED-0603")
      (libsource (lib "eagle-import") (part "LED-BLUE0603"))
    )
    (comp (ref "D5")
      (value "LED-BLUE0603")
      (footprint "eagle-import:LED-0603")
      (libsource (lib "eagle-import") (part "LED-BLUE0603"))
    )
    (comp (ref "D6")
      (value "LED-BLUE0603")
      (footprint "eagle-import:LED-0603")
      (libsource (lib "eagle-import") (part "LED-BLUE0603"))
    )
    (comp (ref "D7")
      (value "LED-BLUE0603")
      (footprint "eagle-import:LED-0603")
      (libsource (lib "eagle-import") (part "LED-BLUE0603"))
    )
    (comp (ref "D8")
      (value "LED-BLUE0603")
      (footprint "eagle-import:LED-0603")
      (libsource (lib "eagle-import") (part "LED-BLUE0603"))
    )
    (comp (ref "D9")
      (value "LED-BLUE0603")
      (footprint "eagle-import:LED-0603")
      (libsource (lib "eagle-import") (part "LED-BLUE0603"))
    )
    (comp (ref "D10")
      (value "LED-BLUE0603")
      (footprint "eagle-import:LED-0603")
      (libsource (lib "eagle-import") (part "LED-BLUE0603"))
    )
    (comp (ref "D11")
      (value "LED-BLUE0603")
      (footprint "eagle-import:LED-0603")
      (libsource (lib "eagle-import") (part "LED-BLUE0603"))
    )
    (comp (ref "D12")
      (value "LED-BLUE0603")
      (footprint "eagle-import:LED-0603")
      (libsource (lib "eagle-import") (part "LED-BLUE0603"))
    )
    (comp (ref "D13")
      (value "LED-BLUE0603")
      (footprint "eagle-import:LED-0603")
      (libsource (lib "eagle-import") (part "LED-BLUE0603"))
    )
    (comp (ref "D14")
      (value "LED-BLUE0603")
      (footprint "eagle-import:LED-0603")
      (libsource (lib "eagle-import") (part "LED-BLUE0603"))
    )
    (comp (ref "D15")
      (value "LED-BLUE0603")
      (footprint "eagle-import:LED-0603")
      (libsource (lib "eagle-import") (part "LED-BLUE0603"))
    )
    (comp (ref "D16")
      (value "LED-BLUE0603")
      (footprint "eagle-import:LED-0603")
      (libsource (lib "eagle-import") (part "LED-BLUE0603"))
    )
    (comp (ref "D17")
      (value "LED-BLUE0603")
      (footprint "eagle-import:LED-0603")
      (libsource (lib "eagle-import") (part "LED-BLUE0603"))
    )
    (comp (ref "D18")
      (value "LED-BLUE0603")
      (footprint "eagle-import:LED-0603")
      (libsource (lib "eagle-import") (part "LED-BLUE0603"))
    )
    (comp (ref "D19")
      (value "LED-BLUE0603")
      (footprint "eagle-import:LED-0603")
      (libsource (lib "eagle-import") (part "LED-BLUE0603"))
    )
    (comp (ref "D20")
      (value "LED-BLUE0603")
      (footprint "eagle-import:LED-0603")
      (libsource (lib "eagle-import") (part "LED-BLUE0603"))
    )
    (comp (ref "D21")
      (value "LED-BLUE0603")
      (footprint "eagle-import:LED-0603")
      (libsource (lib "eagle-import") (part "LED-BLUE0603"))
    )
    (comp (ref "D22")
      (value "LED-BLUE0603")
      (footprint "eagle-import:LED-0603")
      (libsource (lib "eagle-import") (part "LED-BLUE0603"))
    )
    (comp (ref "D23")
      (value "LED-BLUE0603")
      (footprint "eagle-import:LED-0603")
      (libsource (lib "eagle-import") (part "LED-BLUE0603"))
    )
    (comp (ref "D24")
      (value "LED-BLUE0603")
      (footprint "eagle-import:LED-0603")
      (libsource (lib "eagle-import") (part "LED-BLUE0603"))
    )
    (comp (ref "D25")
      (value "LED-BLUE0603")
      (footprint "eagle-import:LED-0603")
      (libsource (lib "eagle-import") (part "LED-BLUE0603"))
    )
    (comp (ref "D26")
      (value "LED-BLUE0603")
      (footprint "eagle-import:LED-0603")
      (libsource (lib "eagle-import") (part "LED-BLUE0603"))
    )
    (comp (ref "D27")
      (value "LED-BLUE0603")
      (footprint "eagle-import:LED-0603")
      (libsource (lib "eagle-import") (part "LED-BLUE0603"))
    )
    (comp (ref "D28")
      (value "LED-BLUE0603")
      (footprint "eagle-import:LED-0603")
      (libsource (lib "eagle-import") (part "LED-BLUE0603"))
    )
    (comp (ref "D29")
      (value "LED-BLUE0603")
      (footprint "eagle-import:LED-0603")
      (libsource (lib "eagle-import") (part "LED-BLUE0603"))
    )
    (comp (ref "D30")
      (value "LED-BLUE0603")
      (footprint "eagle-import:LED-0603")
      (libsource (lib "eagle-import") (part "LED-BLUE0603"))
    )
    (comp (ref "D31")
      (value "LED-BLUE0603")
      (footprint "eagle-import:LED-0603")
      (libsource (lib "eagle-import") (part "LED-BLUE0603"))
    )
    (comp (ref "D32")
      (value "LED-BLUE0603")
      (footprint "eagle-import:LED-0603")
      (libsource (lib "eagle-import") (part "LED-BLUE0603"))
    )
    (comp (ref "D33")
      (value "LED-BLUE0603")
      (footprint "eagle-import:LED-0603")
      (libsource (lib "eagle-import") (part "LED-BLUE0603"))
    )
    (comp (ref "D34")
      (value "LED-BLUE0603")
      (footprint "eagle-import:LED-0603")
      (libsource (lib "eagle-import") (part "LED-BLUE0603"))
    )
    (comp (ref "D35")
      (value "LED-BLUE0603")
      (footprint "eagle-import:LED-0603")
      (libsource (lib "eagle-import") (part "LED-BLUE0603"))
    )
    (comp (ref "D36")
      (value "LED-BLUE0603")
      (footprint "eagle-import:LED-0603")
      (libsource (lib "eagle-import") (part "LED-BLUE0603"))
    )
    (comp (ref "D37")
      (value "LED-BLUE0603")
      (footprint "eagle-import:LED-0603")
      (libsource (lib "eagle-import") (part "LED-BLUE0603"))
    )
    (comp (ref "D38")
      (value "LED-BLUE0603")
      (footprint "eagle-import:LED-0603")
      (libsource (lib "eagle-import") (part "LED-BLUE0603"))
    )
    (comp (ref "D39")
      (value "LED-BLUE0603")
      (footprint "eagle-import:LED-0603")
      (libsource (lib "eagle-import") (part "LED-BLUE0603"))
    )
    (comp (ref "D40")
      (value "LED-BLUE0603")
      (footprint "eagle-import:LED-0603")
      (libsource (lib "eagle-import") (part "LED-BLUE0603"))
    )
    (comp (ref "D41")
      (value "LED-BLUE0603")
      (footprint "eagle-import:LED-0603")
      (libsource (lib "eagle-import") (part "LED-BLUE0603"))
    )
    (comp (ref "D42")
      (value "LED-BLUE0603")
      (footprint "eagle-import:LED-0603")
      (libsource (lib "eagle-import") (part "LED-BLUE0603"))
    )
    (comp (ref "D43")
      (value "LED-BLUE0603")
      (footprint "eagle-import:LED-0603")
      (libsource (lib "eagle-import") (part "LED-BLUE0603"))
    )
    (comp (ref "D44")
      (value "LED-BLUE0603")
      (footprint "eagle-import:LED-0603")
      (libsource (lib "eagle-import") (part "LED-BLUE0603"))
    )
    (comp (ref "D45")
      (value "LED-BLUE0603")
      (footprint "eagle-import:LED-0603")
      (libsource (lib "eagle-import") (part "LED-BLUE0603"))
    )
    (comp (ref "D46")
      (value "LED-BLUE0603")
      (footprint "eagle-import:LED-0603")
      (libsource (lib "eagle-import") (part "LED-BLUE0603"))
    )
    (comp (ref "D47")
      (value "LED-BLUE0603")
      (footprint "eagle-import:LED-0603")
      (libsource (lib "eagle-import") (part "LED-BLUE0603"))
    )
    (comp (ref "D48")
      (value "LED-BLUE0603")
      (footprint "eagle-import:LED-0603")
      (libsource (lib "eagle-import") (part "LED-BLUE0603"))
    )
    (comp (ref "D49")
      (value "LED-BLUE0603")
      (footprint "eagle-import:LED-0603")
      (libsource (lib "eagle-import") (part "LED-BLUE0603"))
    )
    (comp (ref "D50")
      (value "LED-BLUE0603")
      (footprint "eagle-import:LED-0603")
      (libsource (lib "eagle-import") (part "LED-BLUE0603"))
    )
    (comp (ref "D51")
      (value "LED-BLUE0603")
      (footprint "eagle-import:LED-0603")
      (libsource (lib "eagle-import") (part "LED-BLUE0603"))
    )
    (comp (ref "D52")
      (value "LED-BLUE0603")
      (footprint "eagle-import:LED-0603")
      (libsource (lib "eagle-import") (part "LED-BLUE0603"))
    )
    (comp (ref "D53")
      (value "LED-BLUE0603")
      (footprint "eagle-import:LED-0603")
      (libsource (lib "eagle-import") (part "LED-BLUE0603"))
    )
    (comp (ref "D54")
      (value "LED-BLUE0603")
      (footprint "eagle-import:LED-0603")
      (libsource (lib "eagle-import") (part "LED-BLUE0603"))
    )
    (comp (ref "D55")
      (value "LED-BLUE0603")
      (footprint "eagle-import:LED-0603")
      (libsource (lib "eagle-import") (part "LED-BLUE0603"))
    )
    (comp (ref "D56")
      (value "LED-BLUE0603")
      (footprint "eagle-import:LED-0603")
      (libsource (lib "eagle-import") (part "LED-BLUE0603"))
    )
    (comp (ref "D57")
      (value "LED-BLUE0603")
      (footprint "eagle-import:LED-0603")
      (libsource (lib "eagle-import") (part "LED-BLUE0603"))
    )
    (comp (ref "D58")
      (value "LED-BLUE0603")
      (footprint "eagle-import:LED-0603")
      (libsource (lib "eagle-import") (part "LED-BLUE0603"))
    )
    (comp (ref "D59")
      (value "LED-BLUE0603")
      (footprint "eagle-import:LED-0603")
      (libsource (lib "eagle-import") (part "LED-BLUE0603"))
    )
    (comp (ref "D60")
      (value "LED-BLUE0603")
      (footprint "eagle-import:LED-0603")
      (libsource (lib "eagle-import") (part "LED-BLUE0603"))
    )
    (comp (ref "D61")
      (value "LED-BLUE0603")
      (footprint "eagle-import:LED-0603")
      (libsource (lib "eagle-import") (part "LED-BLUE0603"))
    )
    (comp (ref "D62")
      (value "LED-BLUE0603")
      (footprint "eagle-import:LED-0603")
      (libsource (lib "eagle-import") (part "LED-BLUE0603"))
    )
    (comp (ref "D63")
      (value "LED-BLUE0603")
      (footprint "eagle-import:LED-0603")
      (libsource (lib "eagle-import") (part "LED-BLUE0603"))
    )
    (comp (ref "D64")
      (value "LED-BLUE0603")
      (footprint "eagle-import:LED-0603")
      (libsource (lib "eagle-import") (part "LED-BLUE0603"))
    )
    (comp (ref "D65")
      (value "LED-BLUE0603")
      (footprint "eagle-import:LED-0603")
      (libsource (lib "eagle-import") (part "LED-BLUE0603"))
    )
    (comp (ref "D66")
      (value "LED-BLUE0603")
      (footprint "eagle-import:LED-0603")
      (libsource (lib "eagle-import") (part "LED-BLUE0603"))
    )
    (comp (ref "D67")
      (value "LED-BLUE0603")
      (footprint "eagle-import:LED-0603")
      (libsource (lib "eagle-import") (part "LED-BLUE0603"))
    )
    (comp (ref "D68")
      (value "LED-BLUE0603")
      (footprint "eagle-import:LED-0603")
      (libsource (lib "eagle-import") (part "LED-BLUE0603"))
    )
    (comp (ref "D69")
      (value "LED-BLUE0603")
      (footprint "eagle-import:LED-0603")
      (libsource (lib "eagle-import") (part "LED-BLUE0603"))
    )
    (comp (ref "D70")
      (value "LED-BLUE0603")
      (footprint "eagle-import:LED-0603")
      (libsource (lib "eagle-import") (part "LED-BLUE0603"))
    )
    (comp (ref "D71")
      (value "LED-BLUE0603")
      (footprint "eagle-import:LED-0603")
      (libsource (lib "eagle-import") (part "LED-BLUE0603"))
    )
    (comp (ref "D72")
      (value "LED-BLUE0603")
      (footprint "eagle-import:LED-0603")
      (libsource (lib "eagle-import") (part "LED-BLUE0603"))
    )
    (comp (ref "D73")
      (value "LED-BLUE0603")
      (footprint "eagle-import:LED-0603")
      (libsource (lib "eagle-import") (part "LED-BLUE0603"))
    )
    (comp (ref "D74")
      (value "LED-BLUE0603")
      (footprint "eagle-import:LED-0603")
      (libsource (lib "eagle-import") (part "LED-BLUE0603"))
    )
    (comp (ref "D75")
      (value "LED-BLUE0603")
      (footprint "eagle-import:LED-0603")
      (libsource (lib "eagle-import") (part "LED-BLUE0603"))
    )
    (comp (ref "D76")
      (value "LED-BLUE0603")
      (footprint "eagle-import:LED-0603")
      (libsource (lib "eagle-import") (part "LED-BLUE0603"))
    )
    (comp (ref "D77")
      (value "LED-BLUE0603")
      (footprint "eagle-import:LED-0603")
      (libsource (lib "eagle-import") (part "LED-BLUE0603"))
    )
    (comp (ref "D78")
      (value "LED-BLUE0603")
      (footprint "eagle-import:LED-0603")
      (libsource (lib "eagle-import") (part "LED-BLUE0603"))
    )
    (comp (ref "D79")
      (value "LED-BLUE0603")
      (footprint "eagle-import:LED-0603")
      (libsource (lib "eagle-import") (part "LED-BLUE0603"))
    )
    (comp (ref "D80")
      (value "LED-BLUE0603")
      (footprint "eagle-import:LED-0603")
      (libsource (lib "eagle-import") (part "LED-BLUE0603"))
    )
    (comp (ref "D81")
      (value "LED-BLUE0603")
      (footprint "eagle-import:LED-0603")
      (libsource (lib "eagle-import") (part "LED-BLUE0603"))
    )
    (comp (ref "D82")
      (value "LED-BLUE0603")
      (footprint "eagle-import:LED-0603")
      (libsource (lib "eagle-import") (part "LED-BLUE0603"))
    )
    (comp (ref "D83")
      (value "LED-BLUE0603")
      (footprint "eagle-import:LED-0603")
      (libsource (lib "eagle-import") (part "LED-BLUE0603"))
    )
    (comp (ref "D84")
      (value "LED-BLUE0603")
      (footprint "eagle-import:LED-0603")
      (libsource (lib "eagle-import") (part "LED-BLUE0603"))
    )
    (comp (ref "D85")
      (value "LED-BLUE0603")
      (footprint "eagle-import:LED-0603")
      (libsource (lib "eagle-import") (part "LED-BLUE0603"))
    )
    (comp (ref "D86")
      (value "LED-BLUE0603")
      (footprint "eagle-import:LED-0603")
      (libsource (lib "eagle-import") (part "LED-BLUE0603"))
    )
    (comp (ref "D87")
      (value "LED-BLUE0603")
      (footprint "eagle-import:LED-0603")
      (libsource (lib "eagle-import") (part "LED-BLUE0603"))
    )
    (comp (ref "D88")
      (value "LED-BLUE0603")
      (footprint "eagle-import:LED-0603")
      (libsource (lib "eagle-import") (part "LED-BLUE0603"))
    )
    (comp (ref "D89")
      (value "LED-BLUE0603")
      (footprint "eagle-import:LED-0603")
      (libsource (lib "eagle-import") (part "LED-BLUE0603"))
    )
    (comp (ref "D90")
      (value "LED-BLUE0603")
      (footprint "eagle-import:LED-0603")
      (libsource (lib "eagle-import") (part "LED-BLUE0603"))
    )
    (comp (ref "D91")
      (value "LED-BLUE0603")
      (footprint "eagle-import:LED-0603")
      (libsource (lib "eagle-import") (part "LED-BLUE0603"))
    )
    (comp (ref "D92")
      (value "LED-BLUE0603")
      (footprint "eagle-import:LED-0603")
      (libsource (lib "eagle-import") (part "LED-BLUE0603"))
    )
    (comp (ref "D93")
      (value "LED-BLUE0603")
      (footprint "eagle-import:LED-0603")
      (libsource (lib "eagle-import") (part "LED-BLUE0603"))
    )
    (comp (ref "D94")
      (value "LED-BLUE0603")
      (footprint "eagle-import:LED-0603")
      (libsource (lib "eagle-import") (part "LED-BLUE0603"))
    )
    (comp (ref "D95")
      (value "LED-BLUE0603")
      (footprint "eagle-import:LED-0603")
      (libsource (lib "eagle-import") (part "LED-BLUE0603"))
    )
    (comp (ref "D96")
      (value "LED-BLUE0603")
      (footprint "eagle-import:LED-0603")
      (libsource (lib "eagle-import") (part "LED-BLUE0603"))
    )
    (comp (ref "D97")
      (value "LED-BLUE0603")
      (footprint "eagle-import:LED-0603")
      (libsource (lib "eagle-import") (part "LED-BLUE0603"))
    )
    (comp (ref "D98")
      (value "LED-BLUE0603")
      (footprint "eagle-import:LED-0603")
      (libsource (lib "eagle-import") (part "LED-BLUE0603"))
    )
    (comp (ref "D99")
      (value "LED-BLUE0603")
      (footprint "eagle-import:LED-0603")
      (libsource (lib "eagle-import") (part "LED-BLUE0603"))
    )
    (comp (ref "D100")
      (value "LED-BLUE0603")
      (footprint "eagle-import:LED-0603")
      (libsource (lib "eagle-import") (part "LED-BLUE0603"))
    )
    (comp (ref "D101")
      (value "LED-BLUE0603")
      (footprint "eagle-import:LED-0603")
      (libsource (lib "eagle-import") (part "LED-BLUE0603"))
    )
    (comp (ref "D102")
      (value "LED-BLUE0603")
      (footprint "eagle-import:LED-0603")
      (libsource (lib "eagle-import") (part "LED-BLUE0603"))
    )
    (comp (ref "D103")
      (value "LED-BLUE0603")
      (footprint "eagle-import:LED-0603")
      (libsource (lib "eagle-import") (part "LED-BLUE0603"))
    )
    (comp (ref "D104")
      (value "LED-BLUE0603")
      (footprint "eagle-import:LED-0603")
      (libsource (lib "eagle-import") (part "LED-BLUE0603"))
    )
    (comp (ref "D105")
      (value "LED-BLUE0603")
      (footprint "eagle-import:LED-0603")
      (libsource (lib "eagle-import") (part "LED-BLUE0603"))
    )
    (comp (ref "D106")
      (value "LED-BLUE0603")
      (footprint "eagle-import:LED-0603")
      (libsource (lib "eagle-import") (part "LED-BLUE0603"))
    )
    (comp (ref "D107")
      (value "LED-BLUE0603")
      (footprint "eagle-import:LED-0603")
      (libsource (lib "eagle-import") (part "LED-BLUE0603"))
    )
    (comp (ref "D108")
      (value "LED-BLUE0603")
      (footprint "eagle-import:LED-0603")
      (libsource (lib "eagle-import") (part "LED-BLUE0603"))
    )
    (comp (ref "D109")
      (value "LED-BLUE0603")
      (footprint "eagle-import:LED-0603")
      (libsource (lib "eagle-import") (part "LED-BLUE0603"))
    )
    (comp (ref "D110")
      (value "LED-BLUE0603")
      (footprint "eagle-import:LED-0603")
      (libsource (lib "eagle-import") (part "LED-BLUE0603"))
    )
    (comp (ref "D111")
      (value "LED-BLUE0603")
      (footprint "eagle-import:LED-0603")
      (libsource (lib "eagle-import") (part "LED-BLUE0603"))
    )
    (comp (ref "D112")
      (value "LED-BLUE0603")
      (footprint "eagle-import:LED-0603")
      (libsource (lib "eagle-import") (part "LED-BLUE0603"))
    )
    (comp (ref "D113")
      (value "LED-BLUE0603")
      (footprint "eagle-import:LED-0603")
      (libsource (lib "eagle-import") (part "LED-BLUE0603"))
    )
    (comp (ref "D114")
      (value "LED-BLUE0603")
      (footprint "eagle-import:LED-0603")
      (libsource (lib "eagle-import") (part "LED-BLUE0603"))
    )
    (comp (ref "D115")
      (value "LED-BLUE0603")
      (footprint "eagle-import:LED-0603")
      (libsource (lib "eagle-import") (part "LED-BLUE0603"))
    )
    (comp (ref "D116")
      (value "LED-BLUE0603")
      (footprint "eagle-import:LED-0603")
      (libsource (lib "eagle-import") (part "LED-BLUE0603"))
    )
    (comp (ref "D117")
      (value "LED-BLUE0603")
      (footprint "eagle-import:LED-0603")
      (libsource (lib "eagle-import") (part "LED-BLUE0603"))
    )
    (comp (ref "D118")
      (value "LED-BLUE0603")
      (footprint "eagle-import:LED-0603")
      (libsource (lib "eagle-import") (part "LED-BLUE0603"))
    )
    (comp (ref "D119")
      (value "LED-BLUE0603")
      (footprint "eagle-import:LED-0603")
      (libsource (lib "eagle-import") (part "LED-BLUE0603"))
    )
    (comp (ref "D120")
      (value "LED-BLUE0603")
      (footprint "eagle-import:LED-0603")
      (libsource (lib "eagle-import") (part "LED-BLUE0603"))
    )
    (comp (ref "D121")
      (value "LED-BLUE0603")
      (footprint "eagle-import:LED-0603")
      (libsource (lib "eagle-import") (part "LED-BLUE0603"))
    )
    (comp (ref "D122")
      (value "LED-BLUE0603")
      (footprint "eagle-import:LED-0603")
      (libsource (lib "eagle-import") (part "LED-BLUE0603"))
    )
    (comp (ref "D123")
      (value "LED-BLUE0603")
      (footprint "eagle-import:LED-0603")
      (libsource (lib "eagle-import") (part "LED-BLUE0603"))
    )
    (comp (ref "D124")
      (value "LED-BLUE0603")
      (footprint "eagle-import:LED-0603")
      (libsource (lib "eagle-import") (part "LED-BLUE0603"))
    )
    (comp (ref "D125")
      (value "LED-BLUE0603")
      (footprint "eagle-import:LED-0603")
      (libsource (lib "eagle-import") (part "LED-BLUE0603"))
    )
    (comp (ref "D126")
      (value "LED-BLUE0603")
      (footprint "eagle-import:LED-0603")
      (libsource (lib "eagle-import") (part "LED-BLUE0603"))
    )
    (comp (ref "D127")
      (value "LED-BLUE0603")
      (footprint "eagle-import:LED-0603")
      (libsource (lib "eagle-import") (part "LED-BLUE0603"))
    )
    (comp (ref "D128")
      (value "LED-BLUE0603")
      (footprint "eagle-import:LED-0603")
      (libsource (lib "eagle-import") (part "LED-BLUE0603"))
    )
    (comp (ref "D129")
      (value "LED-BLUE0603")
      (footprint "eagle-import:LED-0603")
      (libsource (lib "eagle-import") (part "LED-BLUE0603"))
    )
    (comp (ref "D130")
      (value "LED-BLUE0603")
      (footprint "eagle-import:LED-0603")
      (libsource (lib "eagle-import") (part "LED-BLUE0603"))
    )
    (comp (ref "D131")
      (value "LED-BLUE0603")
      (footprint "eagle-import:LED-0603")
      (libsource (lib "eagle-import") (part "LED-BLUE0603"))
    )
    (comp (ref "D132")
      (value "LED-BLUE0603")
      (footprint "eagle-import:LED-0603")
      (libsource (lib "eagle-import") (part "LED-BLUE0603"))
    )
    (comp (ref "D133")
      (value "LED-BLUE0603")
      (footprint "eagle-import:LED-0603")
      (libsource (lib "eagle-import") (part "LED-BLUE0603"))
    )
    (comp (ref "D134")
      (value "LED-BLUE0603")
      (footprint "eagle-import:LED-0603")
      (libsource (lib "eagle-import") (part "LED-BLUE0603"))
    )
    (comp (ref "D135")
      (value "LED-BLUE0603")
      (footprint "eagle-import:LED-0603")
      (libsource (lib "eagle-import") (part "LED-BLUE0603"))
    )
    (comp (ref "D136")
      (value "LED-BLUE0603")
      (footprint "eagle-import:LED-0603")
      (libsource (lib "eagle-import") (part "LED-BLUE0603"))
    )
    (comp (ref "D137")
      (value "LED-BLUE0603")
      (footprint "eagle-import:LED-0603")
      (libsource (lib "eagle-import") (part "LED-BLUE0603"))
    )
    (comp (ref "D138")
      (value "LED-BLUE0603")
      (footprint "eagle-import:LED-0603")
      (libsource (lib "eagle-import") (part "LED-BLUE0603"))
    )
    (comp (ref "D139")
      (value "LED-BLUE0603")
      (footprint "eagle-import:LED-0603")
      (libsource (lib "eagle-import") (part "LED-BLUE0603"))
    )
    (comp (ref "D140")
      (value "LED-BLUE0603")
      (footprint "eagle-import:LED-0603")
      (libsource (lib "eagle-import") (part "LED-BLUE0603"))
    )
    (comp (ref "D141")
      (value "LED-BLUE0603")
      (footprint "eagle-import:LED-0603")
      (libsource (lib "eagle-import") (part "LED-BLUE0603"))
    )
    (comp (ref "D142")
      (value "LED-BLUE0603")
      (footprint "eagle-import:LED-0603")
      (libsource (lib "eagle-import") (part "LED-BLUE0603"))
    )
    (comp (ref "D143")
      (value "LED-BLUE0603")
      (footprint "eagle-import:LED-0603")
      (libsource (lib "eagle-import") (part "LED-BLUE0603"))
    )
    (comp (ref "D144")
      (value "LED-BLUE0603")
      (footprint "eagle-import:LED-0603")
      (libsource (lib "eagle-import") (part "LED-BLUE0603"))
    )
    (comp (ref "D145")
      (value "LED-BLUE0603")
      (footprint "eagle-import:LED-0603")
      (libsource (lib "eagle-import") (part "LED-BLUE0603"))
    )
    (comp (ref "D146")
      (value "LED-BLUE0603")
      (footprint "eagle-import:LED-0603")
      (libsource (lib "eagle-import") (part "LED-BLUE0603"))
    )
    (comp (ref "D147")
      (value "LED-BLUE0603")
      (footprint "eagle-import:LED-0603")
      (libsource (lib "eagle-import") (part "LED-BLUE0603"))
    )
    (comp (ref "D148")
      (value "LED-BLUE0603")
      (footprint "eagle-import:LED-0603")
      (libsource (lib "eagle-import") (part "LED-BLUE0603"))
    )
    (comp (ref "D149")
      (value "LED-BLUE0603")
      (footprint "eagle-import:LED-0603")
      (libsource (lib "eagle-import") (part "LED-BLUE0603"))
    )
    (comp (ref "D150")
      (value "LED-BLUE0603")
      (footprint "eagle-import:LED-0603")
      (libsource (lib "eagle-import") (part "LED-BLUE0603"))
    )
    (comp (ref "D151")
      (value "LED-BLUE0603")
      (footprint "eagle-import:LED-0603")
      (libsource (lib "eagle-import") (part "LED-BLUE0603"))
    )
    (comp (ref "D152")
      (value "LED-BLUE0603")
      (footprint "eagle-import:LED-0603")
      (libsource (lib "eagle-import") (part "LED-BLUE0603"))
    )
    (comp (ref "D153")
      (value "LED-BLUE0603")
      (footprint "eagle-import:LED-0603")
      (libsource (lib "eagle-import") (part "LED-BLUE0603"))
    )
    (comp (ref "D154")
      (value "LED-BLUE0603")
      (footprint "eagle-import:LED-0603")
      (libsource (lib "eagle-import") (part "LED-BLUE0603"))
    )
    (comp (ref "D155")
      (value "LED-BLUE0603")
      (footprint "eagle-import:LED-0603")
      (libsource (lib "eagle-import") (part "LED-BLUE0603"))
    )
    (comp (ref "D156")
      (value "LED-BLUE0603")
      (footprint "eagle-import:LED-0603")
      (libsource (lib "eagle-import") (part "LED-BLUE0603"))
    )
    (comp (ref "D157")
      (value "LED-BLUE0603")
      (footprint "eagle-import:LED-0603")
      (libsource (lib "eagle-import") (part "LED-BLUE0603"))
    )
    (comp (ref "D158")
      (value "LED-BLUE0603")
      (footprint "eagle-import:LED-0603")
      (libsource (lib "eagle-import") (part "LED-BLUE0603"))
    )
    (comp (ref "D159")
      (value "LED-BLUE0603")
      (footprint "eagle-import:LED-0603")
      (libsource (lib "eagle-import") (part "LED-BLUE0603"))
    )
    (comp (ref "D160")
      (value "LED-BLUE0603")
      (footprint "eagle-import:LED-0603")
      (libsource (lib "eagle-import") (part "LED-BLUE0603"))
    )
    (comp (ref "D161")
      (value "LED-BLUE0603")
      (footprint "eagle-import:LED-0603")
      (libsource (lib "eagle-import") (part "LED-BLUE0603"))
    )
    (comp (ref "D162")
      (value "LED-BLUE0603")
      (footprint "eagle-import:LED-0603")
      (libsource (lib "eagle-import") (part "LED-BLUE0603"))
    )
    (comp (ref "D163")
      (value "LED-BLUE0603")
      (footprint "eagle-import:LED-0603")
      (libsource (lib "eagle-import") (part "LED-BLUE0603"))
    )
    (comp (ref "D164")
      (value "LED-BLUE0603")
      (footprint "eagle-import:LED-0603")
      (libsource (lib "eagle-import") (part "LED-BLUE0603"))
    )
    (comp (ref "D165")
      (value "LED-BLUE0603")
      (footprint "eagle-import:LED-0603")
      (libsource (lib "eagle-import") (part "LED-BLUE0603"))
    )
    (comp (ref "D166")
      (value "LED-BLUE0603")
      (footprint "eagle-import:LED-0603")
      (libsource (lib "eagle-import") (part "LED-BLUE0603"))
    )
    (comp (ref "D167")
      (value "LED-BLUE0603")
      (footprint "eagle-import:LED-0603")
      (libsource (lib "eagle-import") (part "LED-BLUE0603"))
    )
    (comp (ref "D168")
      (value "LED-BLUE0603")
      (footprint "eagle-import:LED-0603")
      (libsource (lib "eagle-import") (part "LED-BLUE0603"))
    )
    (comp (ref "D169")
      (value "LED-BLUE0603")
      (footprint "eagle-import:LED-0603")
      (libsource (lib "eagle-import") (part "LED-BLUE0603"))
    )
    (comp (ref "D170")
      (value "LED-BLUE0603")
      (footprint "eagle-import:LED-0603")
      (libsource (lib "eagle-import") (part "LED-BLUE0603"))
    )
    (comp (ref "D171")
      (value "LED-BLUE0603")
      (footprint "eagle-import:LED-0603")
      (libsource (lib "eagle-import") (part "LED-BLUE0603"))
    )
    (comp (ref "D172")
      (value "LED-BLUE0603")
      (footprint "eagle-import:LED-0603")
      (libsource (lib "eagle-import") (part "LED-BLUE0603"))
    )
    (comp (ref "D173")
      (value "LED-BLUE0603")
      (footprint "eagle-import:LED-0603")
      (libsource (lib "eagle-import") (part "LED-BLUE0603"))
    )
    (comp (ref "D174")
      (value "LED-BLUE0603")
      (footprint "eagle-import:LED-0603")
      (libsource (lib "eagle-import") (part "LED-BLUE0603"))
    )
    (comp (ref "D175")
      (value "LED-BLUE0603")
      (footprint "eagle-import:LED-0603")
      (libsource (lib "eagle-import") (part "LED-BLUE0603"))
    )
    (comp (ref "D176")
      (value "LED-BLUE0603")
      (footprint "eagle-import:LED-0603")
      (libsource (lib "eagle-import") (part "LED-BLUE0603"))
    )
    (comp (ref "D177")
      (value "LED-BLUE0603")
      (footprint "eagle-import:LED-0603")
      (libsource (lib "eagle-import") (part "LED-BLUE0603"))
    )
    (comp (ref "D178")
      (value "LED-BLUE0603")
      (footprint "eagle-import:LED-0603")
      (libsource (lib "eagle-import") (part "LED-BLUE0603"))
    )
    (comp (ref "D179")
      (value "LED-BLUE0603")
      (footprint "eagle-import:LED-0603")
      (libsource (lib "eagle-import") (part "LED-BLUE0603"))
    )
    (comp (ref "D180")
      (value "LED-BLUE0603")
      (footprint "eagle-import:LED-0603")
      (libsource (lib "eagle-import") (part "LED-BLUE0603"))
    )
    (comp (ref "D181")
      (value "LED-BLUE0603")
      (footprint "eagle-import:LED-0603")
      (libsource (lib "eagle-import") (part "LED-BLUE0603"))
    )
    (comp (ref "D182")
      (value "LED-BLUE0603")
      (footprint "eagle-import:LED-0603")
      (libsource (lib "eagle-import") (part "LED-BLUE0603"))
    )
    (comp (ref "D183")
      (value "LED-BLUE0603")
      (footprint "eagle-import:LED-0603")
      (libsource (lib "eagle-import") (part "LED-BLUE0603"))
    )
    (comp (ref "D184")
      (value "LED-BLUE0603")
      (footprint "eagle-import:LED-0603")
      (libsource (lib "eagle-import") (part "LED-BLUE0603"))
    )
    (comp (ref "D185")
      (value "LED-BLUE0603")
      (footprint "eagle-import:LED-0603")
      (libsource (lib "eagle-import") (part "LED-BLUE0603"))
    )
    (comp (ref "D186")
      (value "LED-BLUE0603")
      (footprint "eagle-import:LED-0603")
      (libsource (lib "eagle-import") (part "LED-BLUE0603"))
    )
    (comp (ref "D187")
      (value "LED-BLUE0603")
      (footprint "eagle-import:LED-0603")
      (libsource (lib "eagle-import") (part "LED-BLUE0603"))
    )
    (comp (ref "D188")
      (value "LED-BLUE0603")
      (footprint "eagle-import:LED-0603")
      (libsource (lib "eagle-import") (part "LED-BLUE0603"))
    )
    (comp (ref "D189")
      (value "LED-BLUE0603")
      (footprint "eagle-import:LED-0603")
      (libsource (lib "eagle-import") (part "LED-BLUE0603"))
    )
    (comp (ref "D190")
      (value "LED-BLUE0603")
      (footprint "eagle-import:LED-0603")
      (libsource (lib "eagle-import") (part "LED-BLUE0603"))
    )
    (comp (ref "D191")
      (value "LED-BLUE0603")
      (footprint "eagle-import:LED-0603")
      (libsource (lib "eagle-import") (part "LED-BLUE0603"))
    )
    (comp (ref "D192")
      (value "LED-BLUE0603")
      (footprint "eagle-import:LED-0603")
      (libsource (lib "eagle-import") (part "LED-BLUE0603"))
    )
    (comp (ref "D193")
      (value "LED-BLUE0603")
      (footprint "eagle-import:LED-0603")
      (libsource (lib "eagle-import") (part "LED-BLUE0603"))
    )
    (comp (ref "D194")
      (value "LED-BLUE0603")
      (footprint "eagle-import:LED-0603")
      (libsource (lib "eagle-import") (part "LED-BLUE0603"))
    )
    (comp (ref "D195")
      (value "LED-BLUE0603")
      (footprint "eagle-import:LED-0603")
      (libsource (lib "eagle-import") (part "LED-BLUE0603"))
    )
    (comp (ref "D196")
      (value "LED-BLUE0603")
      (footprint "eagle-import:LED-0603")
      (libsource (lib "eagle-import") (part "LED-BLUE0603"))
    )
    (comp (ref "D197")
      (value "LED-BLUE0603")
      (footprint "eagle-import:LED-0603")
      (libsource (lib "eagle-import") (part "LED-BLUE0603"))
    )
    (comp (ref "D198")
      (value "LED-BLUE0603")
      (footprint "eagle-import:LED-0603")
      (libsource (lib "eagle-import") (part "LED-BLUE0603"))
    )
    (comp (ref "D199")
      (value "LED-BLUE0603")
      (footprint "eagle-import:LED-0603")
      (libsource (lib "eagle-import") (part "LED-BLUE0603"))
    )
    (comp (ref "D200")
      (value "LED-BLUE0603")
      (footprint "eagle-import:LED-0603")
      (libsource (lib "eagle-import") (part "LED-BLUE0603"))
    )
    (comp (ref "D201")
      (value "LED-BLUE0603")
      (footprint "eagle-import:LED-0603")
      (libsource (lib "eagle-import") (part "LED-BLUE0603"))
    )
    (comp (ref "D202")
      (value "LED-BLUE0603")
      (footprint "eagle-import:LED-0603")
      (libsource (lib "eagle-import") (part "LED-BLUE0603"))
    )
    (comp (ref "D203")
      (value "LED-BLUE0603")
      (footprint "eagle-import:LED-0603")
      (libsource (lib "eagle-import") (part "LED-BLUE0603"))
    )
    (comp (ref "D204")
      (value "LED-BLUE0603")
      (footprint "eagle-import:LED-0603")
      (libsource (lib "eagle-import") (part "LED-BLUE0603"))
    )
    (comp (ref "D205")
      (value "LED-BLUE0603")
      (footprint "eagle-import:LED-0603")
      (libsource (lib "eagle-import") (part "LED-BLUE0603"))
    )
    (comp (ref "D206")
      (value "LED-BLUE0603")
      (footprint "eagle-import:LED-0603")
      (libsource (lib "eagle-import") (part "LED-BLUE0603"))
    )
    (comp (ref "D207")
      (value "LED-BLUE0603")
      (footprint "eagle-import:LED-0603")
      (libsource (lib "eagle-import") (part "LED-BLUE0603"))
    )
    (comp (ref "D208")
      (value "LED-BLUE0603")
      (footprint "eagle-import:LED-0603")
      (libsource (lib "eagle-import") (part "LED-BLUE0603"))
    )
    (comp (ref "D209")
      (value "LED-BLUE0603")
      (footprint "eagle-import:LED-0603")
      (libsource (lib "eagle-import") (part "LED-BLUE0603"))
    )
    (comp (ref "D210")
      (value "LED-BLUE0603")
      (footprint "eagle-import:LED-0603")
      (libsource (lib "eagle-import") (part "LED-BLUE0603"))
    )
    (comp (ref "D211")
      (value "LED-BLUE0603")
      (footprint "eagle-import:LED-0603")
      (libsource (lib "eagle-import") (part "LED-BLUE0603"))
    )
    (comp (ref "D212")
      (value "LED-BLUE0603")
      (footprint "eagle-import:LED-0603")
      (libsource (lib "eagle-import") (part "LED-BLUE0603"))
    )
    (comp (ref "D213")
      (value "LED-BLUE0603")
      (footprint "eagle-import:LED-0603")
      (libsource (lib "eagle-import") (part "LED-BLUE0603"))
    )
    (comp (ref "D214")
      (value "LED-BLUE0603")
      (footprint "eagle-import:LED-0603")
      (libsource (lib "eagle-import") (part "LED-BLUE0603"))
    )
    (comp (ref "D215")
      (value "LED-BLUE0603")
      (footprint "eagle-import:LED-0603")
      (libsource (lib "eagle-import") (part "LED-BLUE0603"))
    )
    (comp (ref "D216")
      (value "LED-BLUE0603")
      (footprint "eagle-import:LED-0603")
      (libsource (lib "eagle-import") (part "LED-BLUE0603"))
    )
    (comp (ref "D217")
      (value "LED-BLUE0603")
      (footprint "eagle-import:LED-0603")
      (libsource (lib "eagle-import") (part "LED-BLUE0603"))
    )
    (comp (ref "D218")
      (value "LED-BLUE0603")
      (footprint "eagle-import:LED-0603")
      (libsource (lib "eagle-import") (part "LED-BLUE0603"))
    )
    (comp (ref "D219")
      (value "LED-BLUE0603")
      (footprint "eagle-import:LED-0603")
      (libsource (lib "eagle-import") (part "LED-BLUE0603"))
    )
    (comp (ref "D220")
      (value "LED-BLUE0603")
      (footprint "eagle-import:LED-0603")
      (libsource (lib "eagle-import") (part "LED-BLUE0603"))
    )
    (comp (ref "D221")
      (value "LED-BLUE0603")
      (footprint "eagle-import:LED-0603")
      (libsource (lib "eagle-import") (part "LED-BLUE0603"))
    )
    (comp (ref "D222")
      (value "LED-BLUE0603")
      (footprint "eagle-import:LED-0603")
      (libsource (lib "eagle-import") (part "LED-BLUE0603"))
    )
    (comp (ref "D223")
      (value "LED-BLUE0603")
      (footprint "eagle-import:LED-0603")
      (libsource (lib "eagle-import") (part "LED-BLUE0603"))
    )
    (comp (ref "D224")
      (value "LED-BLUE0603")
      (footprint "eagle-import:LED-0603")
      (libsource (lib "eagle-import") (part "LED-BLUE0603"))
    )
    (comp (ref "D225")
      (value "LED-BLUE0603")
      (footprint "eagle-import:LED-0603")
      (libsource (lib "eagle-import") (part "LED-BLUE0603"))
    )
    (comp (ref "D226")
      (value "LED-BLUE0603")
      (footprint "eagle-import:LED-0603")
      (libsource (lib "eagle-import") (part "LED-BLUE0603"))
    )
    (comp (ref "D227")
      (value "LED-BLUE0603")
      (footprint "eagle-import:LED-0603")
      (libsource (lib "eagle-import") (part "LED-BLUE0603"))
    )
    (comp (ref "D228")
      (value "LED-BLUE0603")
      (footprint "eagle-import:LED-0603")
      (libsource (lib "eagle-import") (part "LED-BLUE0603"))
    )
    (comp (ref "D229")
      (value "LED-BLUE0603")
      (footprint "eagle-import:LED-0603")
      (libsource (lib "eagle-import") (part "LED-BLUE0603"))
    )
    (comp (ref "D230")
      (value "LED-BLUE0603")
      (footprint "eagle-import:LED-0603")
      (libsource (lib "eagle-import") (part "LED-BLUE0603"))
    )
    (comp (ref "D231")
      (value "LED-BLUE0603")
      (footprint "eagle-import:LED-0603")
      (libsource (lib "eagle-import") (part "LED-BLUE0603"))
    )
    (comp (ref "D232")
      (value "LED-BLUE0603")
      (footprint "eagle-import:LED-0603")
      (libsource (lib "eagle-import") (part "LED-BLUE0603"))
    )
    (comp (ref "D233")
      (value "LED-BLUE0603")
      (footprint "eagle-import:LED-0603")
      (libsource (lib "eagle-import") (part "LED-BLUE0603"))
    )
    (comp (ref "D234")
      (value "LED-BLUE0603")
      (footprint "eagle-import:LED-0603")
      (libsource (lib "eagle-import") (part "LED-BLUE0603"))
    )
    (comp (ref "D235")
      (value "LED-BLUE0603")
      (footprint "eagle-import:LED-0603")
      (libsource (lib "eagle-import") (part "LED-BLUE0603"))
    )
    (comp (ref "D236")
      (value "LED-BLUE0603")
      (footprint "eagle-import:LED-0603")
      (libsource (lib "eagle-import") (part "LED-BLUE0603"))
    )
    (comp (ref "D237")
      (value "LED-BLUE0603")
      (footprint "eagle-import:LED-0603")
      (libsource (lib "eagle-import") (part "LED-BLUE0603"))
    )
    (comp (ref "D238")
      (value "LED-BLUE0603")
      (footprint "eagle-import:LED-0603")
      (libsource (lib "eagle-import") (part "LED-BLUE0603"))
    )
    (comp (ref "D239")
      (value "LED-BLUE0603")
      (footprint "eagle-import:LED-0603")
      (libsource (lib "eagle-import") (part "LED-BLUE0603"))
    )
    (comp (ref "D240")
      (value "LED-BLUE0603")
      (footprint "eagle-import:LED-0603")
      (libsource (lib "eagle-import") (part "LED-BLUE0603"))
    )
    (comp (ref "D241")
      (value "LED-BLUE0603")
      (footprint "eagle-import:LED-0603")
      (libsource (lib "eagle-import") (part "LED-BLUE0603"))
    )
    (comp (ref "D242")
      (value "LED-BLUE0603")
      (footprint "eagle-import:LED-0603")
      (libsource (lib "eagle-import") (part "LED-BLUE0603"))
    )
    (comp (ref "D243")
      (value "LED-BLUE0603")
      (footprint "eagle-import:LED-0603")
      (libsource (lib "eagle-import") (part "LED-BLUE0603"))
    )
    (comp (ref "D244")
      (value "LED-BLUE0603")
      (footprint "eagle-import:LED-0603")
      (libsource (lib "eagle-import") (part "LED-BLUE0603"))
    )
    (comp (ref "D245")
      (value "LED-BLUE0603")
      (footprint "eagle-import:LED-0603")
      (libsource (lib "eagle-import") (part "LED-BLUE0603"))
    )
    (comp (ref "D246")
      (value "LED-BLUE0603")
      (footprint "eagle-import:LED-0603")
      (libsource (lib "eagle-import") (part "LED-BLUE0603"))
    )
    (comp (ref "D247")
      (value "LED-BLUE0603")
      (footprint "eagle-import:LED-0603")
      (libsource (lib "eagle-import") (part "LED-BLUE0603"))
    )
    (comp (ref "D248")
      (value "LED-BLUE0603")
      (footprint "eagle-import:LED-0603")
      (libsource (lib "eagle-import") (part "LED-BLUE0603"))
    )
    (comp (ref "D249")
      (value "LED-BLUE0603")
      (footprint "eagle-import:LED-0603")
      (libsource (lib "eagle-import") (part "LED-BLUE0603"))
    )
    (comp (ref "D250")
      (value "LED-BLUE0603")
      (footprint "eagle-import:LED-0603")
      (libsource (lib "eagle-import") (part "LED-BLUE0603"))
    )
    (comp (ref "D251")
      (value "LED-BLUE0603")
      (footprint "eagle-import:LED-0603")
      (libsource (lib "eagle-import") (part "LED-BLUE0603"))
    )
    (comp (ref "D252")
      (value "LED-BLUE0603")
      (footprint "eagle-import:LED-0603")
      (libsource (lib "eagle-import") (part "LED-BLUE0603"))
    )
    (comp (ref "D253")
      (value "LED-BLUE0603")
      (footprint "eagle-import:LED-0603")
      (libsource (lib "eagle-import") (part "LED-BLUE0603"))
    )
    (comp (ref "D254")
      (value "LED-BLUE0603")
      (footprint "eagle-import:LED-0603")
      (libsource (lib "eagle-import") (part "LED-BLUE0603"))
    )
    (comp (ref "D255")
      (value "LED-BLUE0603")
      (footprint "eagle-import:LED-0603")
      (libsource (lib "eagle-import") (part "LED-BLUE0603"))
    )
    (comp (ref "D256")
      (value "LED-BLUE0603")
      (footprint "eagle-import:LED-0603")
      (libsource (lib "eagle-import") (part "LED-BLUE0603"))
    )
    (comp (ref "D257")
      (value "LED-BLUE0603")
      (footprint "eagle-import:LED-0603")
      (libsource (lib "eagle-import") (part "LED-BLUE0603"))
    )
    (comp (ref "D258")
      (value "LED-BLUE0603")
      (footprint "eagle-import:LED-0603")
      (libsource (lib "eagle-import") (part "LED-BLUE0603"))
    )
    (comp (ref "D259")
      (value "LED-BLUE0603")
      (footprint "eagle-import:LED-0603")
      (libsource (lib "eagle-import") (part "LED-BLUE0603"))
    )
    (comp (ref "D260")
      (value "LED-BLUE0603")
      (footprint "eagle-import:LED-0603")
      (libsource (lib "eagle-import") (part "LED-BLUE0603"))
    )
    (comp (ref "D261")
      (value "LED-BLUE0603")
      (footprint "eagle-import:LED-0603")
      (libsource (lib "eagle-import") (part "LED-BLUE0603"))
    )
    (comp (ref "D262")
      (value "LED-BLUE0603")
      (footprint "eagle-import:LED-0603")
      (libsource (lib "eagle-import") (part "LED-BLUE0603"))
    )
    (comp (ref "D263")
      (value "LED-BLUE0603")
      (footprint "eagle-import:LED-0603")
      (libsource (lib "eagle-import") (part "LED-BLUE0603"))
    )
    (comp (ref "D264")
      (value "LED-BLUE0603")
      (footprint "eagle-import:LED-0603")
      (libsource (lib "eagle-import") (part "LED-BLUE0603"))
    )
    (comp (ref "D265")
      (value "LED-BLUE0603")
      (footprint "eagle-import:LED-0603")
      (libsource (lib "eagle-import") (part "LED-BLUE0603"))
    )
    (comp (ref "D266")
      (value "LED-BLUE0603")
      (footprint "eagle-import:LED-0603")
      (libsource (lib "eagle-import") (part "LED-BLUE0603"))
    )
    (comp (ref "D267")
      (value "LED-BLUE0603")
      (footprint "eagle-import:LED-0603")
      (libsource (lib "eagle-import") (part "LED-BLUE0603"))
    )
    (comp (ref "D268")
      (value "LED-BLUE0603")
      (footprint "eagle-import:LED-0603")
      (libsource (lib "eagle-import") (part "LED-BLUE0603"))
    )
    (comp (ref "D269")
      (value "LED-BLUE0603")
      (footprint "eagle-import:LED-0603")
      (libsource (lib "eagle-import") (part "LED-BLUE0603"))
    )
    (comp (ref "D270")
      (value "LED-BLUE0603")
      (footprint "eagle-import:LED-0603")
      (libsource (lib "eagle-import") (part "LED-BLUE0603"))
    )
    (comp (ref "D271")
      (value "LED-BLUE0603")
      (footprint "eagle-import:LED-0603")
      (libsource (lib "eagle-import") (part "LED-BLUE0603"))
    )
    (comp (ref "D272")
      (value "LED-BLUE0603")
      (footprint "eagle-import:LED-0603")
      (libsource (lib "eagle-import") (part "LED-BLUE0603"))
    )
    (comp (ref "D273")
      (value "LED-BLUE0603")
      (footprint "eagle-import:LED-0603")
      (libsource (lib "eagle-import") (part "LED-BLUE0603"))
    )
    (comp (ref "D274")
      (value "LED-BLUE0603")
      (footprint "eagle-import:LED-0603")
      (libsource (lib "eagle-import") (part "LED-BLUE0603"))
    )
    (comp (ref "D275")
      (value "LED-BLUE0603")
      (footprint "eagle-import:LED-0603")
      (libsource (lib "eagle-import") (part "LED-BLUE0603"))
    )
    (comp (ref "D276")
      (value "LED-BLUE0603")
      (footprint "eagle-import:LED-0603")
      (libsource (lib "eagle-import") (part "LED-BLUE0603"))
    )
    (comp (ref "D277")
      (value "LED-BLUE0603")
      (footprint "eagle-import:LED-0603")
      (libsource (lib "eagle-import") (part "LED-BLUE0603"))
    )
    (comp (ref "D278")
      (value "LED-BLUE0603")
      (footprint "eagle-import:LED-0603")
      (libsource (lib "eagle-import") (part "LED-BLUE0603"))
    )
    (comp (ref "D279")
      (value "LED-BLUE0603")
      (footprint "eagle-import:LED-0603")
      (libsource (lib "eagle-import") (part "LED-BLUE0603"))
    )
    (comp (ref "D280")
      (value "LED-BLUE0603")
      (footprint "eagle-import:LED-0603")
      (libsource (lib "eagle-import") (part "LED-BLUE0603"))
    )
    (comp (ref "D281")
      (value "LED-BLUE0603")
      (footprint "eagle-import:LED-0603")
      (libsource (lib "eagle-import") (part "LED-BLUE0603"))
    )
    (comp (ref "D282")
      (value "LED-BLUE0603")
      (footprint "eagle-import:LED-0603")
      (libsource (lib "eagle-import") (part "LED-BLUE0603"))
    )
    (comp (ref "D283")
      (value "LED-BLUE0603")
      (footprint "eagle-import:LED-0603")
      (libsource (lib "eagle-import") (part "LED-BLUE0603"))
    )
    (comp (ref "D284")
      (value "LED-BLUE0603")
      (footprint "eagle-import:LED-0603")
      (libsource (lib "eagle-import") (part "LED-BLUE0603"))
    )
    (comp (ref "D285")
      (value "LED-BLUE0603")
      (footprint "eagle-import:LED-0603")
      (libsource (lib "eagle-import") (part "LED-BLUE0603"))
    )
    (comp (ref "D286")
      (value "LED-BLUE0603")
      (footprint "eagle-import:LED-0603")
      (libsource (lib "eagle-import") (part "LED-BLUE0603"))
    )
    (comp (ref "D287")
      (value "LED-BLUE0603")
      (footprint "eagle-import:LED-0603")
      (libsource (lib "eagle-import") (part "LED-BLUE0603"))
    )
    (comp (ref "D288")
      (value "LED-BLUE0603")
      (footprint "eagle-import:LED-0603")
      (libsource (lib "eagle-import") (part "LED-BLUE0603"))
    )
    (comp (ref "D289")
      (value "LED-BLUE0603")
      (footprint "eagle-import:LED-0603")
      (libsource (lib "eagle-import") (part "LED-BLUE0603"))
    )
    (comp (ref "D290")
      (value "LED-BLUE0603")
      (footprint "eagle-import:LED-0603")
      (libsource (lib "eagle-import") (part "LED-BLUE0603"))
    )
    (comp (ref "D291")
      (value "LED-BLUE0603")
      (footprint "eagle-import:LED-0603")
      (libsource (lib "eagle-import") (part "LED-BLUE0603"))
    )
    (comp (ref "D292")
      (value "LED-BLUE0603")
      (footprint "eagle-import:LED-0603")
      (libsource (lib "eagle-import") (part "LED-BLUE0603"))
    )
    (comp (ref "D293")
      (value "LED-BLUE0603")
      (footprint "eagle-import:LED-0603")
      (libsource (lib "eagle-import") (part "LED-BLUE0603"))
    )
    (comp (ref "D294")
      (value "LED-BLUE0603")
      (footprint "eagle-import:LED-0603")
      (libsource (lib "eagle-import") (part "LED-BLUE0603"))
    )
    (comp (ref "D295")
      (value "LED-BLUE0603")
      (footprint "eagle-import:LED-0603")
      (libsource (lib "eagle-import") (part "LED-BLUE0603"))
    )
    (comp (ref "D296")
      (value "LED-BLUE0603")
      (footprint "eagle-import:LED-0603")
      (libsource (lib "eagle-import") (part "LED-BLUE0603"))
    )
    (comp (ref "D297")
      (value "LED-BLUE0603")
      (footprint "eagle-import:LED-0603")
      (libsource (lib "eagle-import") (part "LED-BLUE0603"))
    )
    (comp (ref "D298")
      (value "LED-BLUE0603")
      (footprint "eagle-import:LED-0603")
      (libsource (lib "eagle-import") (part "LED-BLUE0603"))
    )
    (comp (ref "D299")
      (value "LED-BLUE0603")
      (footprint "eagle-import:LED-0603")
      (libsource (lib "eagle-import") (part "LED-BLUE0603"))
    )
    (comp (ref "D300")
      (value "LED-BLUE0603")
      (footprint "eagle-import:LED-0603")
      (libsource (lib "eagle-import") (part "LED-BLUE0603"))
    )
    (comp (ref "D301")
      (value "LED-BLUE0603")
      (footprint "eagle-import:LED-0603")
      (libsource (lib "eagle-import") (part "LED-BLUE0603"))
    )
    (comp (ref "D302")
      (value "LED-BLUE0603")
      (footprint "eagle-import:LED-0603")
      (libsource (lib "eagle-import") (part "LED-BLUE0603"))
    )
    (comp (ref "D303")
      (value "LED-BLUE0603")
      (footprint "eagle-import:LED-0603")
      (libsource (lib "eagle-import") (part "LED-BLUE0603"))
    )
    (comp (ref "D304")
      (value "LED-BLUE0603")
      (footprint "eagle-import:LED-0603")
      (libsource (lib "eagle-import") (part "LED-BLUE0603"))
    )
    (comp (ref "D305")
      (value "LED-BLUE0603")
      (footprint "eagle-import:LED-0603")
      (libsource (lib "eagle-import") (part "LED-BLUE0603"))
    )
    (comp (ref "D306")
      (value "LED-BLUE0603")
      (footprint "eagle-import:LED-0603")
      (libsource (lib "eagle-import") (part "LED-BLUE0603"))
    )
    (comp (ref "D307")
      (value "LED-BLUE0603")
      (footprint "eagle-import:LED-0603")
      (libsource (lib "eagle-import") (part "LED-BLUE0603"))
    )
    (comp (ref "D308")
      (value "LED-BLUE0603")
      (footprint "eagle-import:LED-0603")
      (libsource (lib "eagle-import") (part "LED-BLUE0603"))
    )
    (comp (ref "D309")
      (value "LED-BLUE0603")
      (footprint "eagle-import:LED-0603")
      (libsource (lib "eagle-import") (part "LED-BLUE0603"))
    )
    (comp (ref "D310")
      (value "LED-BLUE0603")
      (footprint "eagle-import:LED-0603")
      (libsource (lib "eagle-import") (part "LED-BLUE0603"))
    )
    (comp (ref "D311")
      (value "LED-BLUE0603")
      (footprint "eagle-import:LED-0603")
      (libsource (lib "eagle-import") (part "LED-BLUE0603"))
    )
    (comp (ref "D312")
      (value "LED-BLUE0603")
      (footprint "eagle-import:LED-0603")
      (libsource (lib "eagle-import") (part "LED-BLUE0603"))
    )
    (comp (ref "D313")
      (value "LED-BLUE0603")
      (footprint "eagle-import:LED-0603")
      (libsource (lib "eagle-import") (part "LED-BLUE0603"))
    )
    (comp (ref "D314")
      (value "LED-BLUE0603")
      (footprint "eagle-import:LED-0603")
      (libsource (lib "eagle-import") (part "LED-BLUE0603"))
    )
    (comp (ref "D315")
      (value "LED-BLUE0603")
      (footprint "eagle-import:LED-0603")
      (libsource (lib "eagle-import") (part "LED-BLUE0603"))
    )
    (comp (ref "D316")
      (value "LED-BLUE0603")
      (footprint "eagle-import:LED-0603")
      (libsource (lib "eagle-import") (part "LED-BLUE0603"))
    )
    (comp (ref "D317")
      (value "LED-BLUE0603")
      (footprint "eagle-import:LED-0603")
      (libsource (lib "eagle-import") (part "LED-BLUE0603"))
    )
    (comp (ref "D318")
      (value "LED-BLUE0603")
      (footprint "eagle-import:LED-0603")
      (libsource (lib "eagle-import") (part "LED-BLUE0603"))
    )
    (comp (ref "D319")
      (value "LED-BLUE0603")
      (footprint "eagle-import:LED-0603")
      (libsource (lib "eagle-import") (part "LED-BLUE0603"))
    )
    (comp (ref "D320")
      (value "LED-BLUE0603")
      (footprint "eagle-import:LED-0603")
      (libsource (lib "eagle-import") (part "LED-BLUE0603"))
    )
    (comp (ref "D321")
      (value "LED-BLUE0603")
      (footprint "eagle-import:LED-0603")
      (libsource (lib "eagle-import") (part "LED-BLUE0603"))
    )
    (comp (ref "D322")
      (value "LED-BLUE0603")
      (footprint "eagle-import:LED-0603")
      (libsource (lib "eagle-import") (part "LED-BLUE0603"))
    )
    (comp (ref "D323")
      (value "LED-BLUE0603")
      (footprint "eagle-import:LED-0603")
      (libsource (lib "eagle-import") (part "LED-BLUE0603"))
    )
    (comp (ref "D324")
      (value "LED-BLUE0603")
      (footprint "eagle-import:LED-0603")
      (libsource (lib "eagle-import") (part "LED-BLUE0603"))
    )
    (comp (ref "D325")
      (value "LED-BLUE0603")
      (footprint "eagle-import:LED-0603")
      (libsource (lib "eagle-import") (part "LED-BLUE0603"))
    )
    (comp (ref "D326")
      (value "LED-BLUE0603")
      (footprint "eagle-import:LED-0603")
      (libsource (lib "eagle-import") (part "LED-BLUE0603"))
    )
    (comp (ref "D327")
      (value "LED-BLUE0603")
      (footprint "eagle-import:LED-0603")
      (libsource (lib "eagle-import") (part "LED-BLUE0603"))
    )
    (comp (ref "D328")
      (value "LED-BLUE0603")
      (footprint "eagle-import:LED-0603")
      (libsource (lib "eagle-import") (part "LED-BLUE0603"))
    )
    (comp (ref "D329")
      (value "LED-BLUE0603")
      (footprint "eagle-import:LED-0603")
      (libsource (lib "eagle-import") (part "LED-BLUE0603"))
    )
    (comp (ref "D330")
      (value "LED-BLUE0603")
      (footprint "eagle-import:LED-0603")
      (libsource (lib "eagle-import") (part "LED-BLUE0603"))
    )
    (comp (ref "D331")
      (value "LED-BLUE0603")
      (footprint "eagle-import:LED-0603")
      (libsource (lib "eagle-import") (part "LED-BLUE0603"))
    )
    (comp (ref "D332")
      (value "LED-BLUE0603")
      (footprint "eagle-import:LED-0603")
      (libsource (lib "eagle-import") (part "LED-BLUE0603"))
    )
    (comp (ref "D333")
      (value "LED-BLUE0603")
      (footprint "eagle-import:LED-0603")
      (libsource (lib "eagle-import") (part "LED-BLUE0603"))
    )
    (comp (ref "D334")
      (value "LED-BLUE0603")
      (footprint "eagle-import:LED-0603")
      (libsource (lib "eagle-import") (part "LED-BLUE0603"))
    )
    (comp (ref "D335")
      (value "LED-BLUE0603")
      (footprint "eagle-import:LED-0603")
      (libsource (lib "eagle-import") (part "LED-BLUE0603"))
    )
    (comp (ref "D336")
      (value "LED-BLUE0603")
      (footprint "eagle-import:LED-0603")
      (libsource (lib "eagle-import") (part "LED-BLUE0603"))
    )
    (comp (ref "D337")
      (value "LED-BLUE0603")
      (footprint "eagle-import:LED-0603")
      (libsource (lib "eagle-import") (part "LED-BLUE0603"))
    )
    (comp (ref "D338")
      (value "LED-BLUE0603")
      (footprint "eagle-import:LED-0603")
      (libsource (lib "eagle-import") (part "LED-BLUE0603"))
    )
    (comp (ref "D339")
      (value "LED-BLUE0603")
      (footprint "eagle-import:LED-0603")
      (libsource (lib "eagle-import") (part "LED-BLUE0603"))
    )
    (comp (ref "D340")
      (value "LED-BLUE0603")
      (footprint "eagle-import:LED-0603")
      (libsource (lib "eagle-import") (part "LED-BLUE0603"))
    )
    (comp (ref "D341")
      (value "LED-BLUE0603")
      (footprint "eagle-import:LED-0603")
      (libsource (lib "eagle-import") (part "LED-BLUE0603"))
    )
    (comp (ref "D342")
      (value "LED-BLUE0603")
      (footprint "eagle-import:LED-0603")
      (libsource (lib "eagle-import") (part "LED-BLUE0603"))
    )
    (comp (ref "D343")
      (value "LED-BLUE0603")
      (footprint "eagle-import:LED-0603")
      (libsource (lib "eagle-import") (part "LED-BLUE0603"))
    )
    (comp (ref "D344")
      (value "LED-BLUE0603")
      (footprint "eagle-import:LED-0603")
      (libsource (lib "eagle-import") (part "LED-BLUE0603"))
    )
    (comp (ref "D345")
      (value "LED-BLUE0603")
      (footprint "eagle-import:LED-0603")
      (libsource (lib "eagle-import") (part "LED-BLUE0603"))
    )
    (comp (ref "D346")
      (value "LED-BLUE0603")
      (footprint "eagle-import:LED-0603")
      (libsource (lib "eagle-import") (part "LED-BLUE0603"))
    )
    (comp (ref "D347")
      (value "LED-BLUE0603")
      (footprint "eagle-import:LED-0603")
      (libsource (lib "eagle-import") (part "LED-BLUE0603"))
    )
    (comp (ref "D348")
      (value "LED-BLUE0603")
      (footprint "eagle-import:LED-0603")
      (libsource (lib "eagle-import") (part "LED-BLUE0603"))
    )
    (comp (ref "D349")
      (value "LED-BLUE0603")
      (footprint "eagle-import:LED-0603")
      (libsource (lib "eagle-import") (part "LED-BLUE0603"))
    )
    (comp (ref "D350")
      (value "LED-BLUE0603")
      (footprint "eagle-import:LED-0603")
      (libsource (lib "eagle-import") (part "LED-BLUE0603"))
    )
    (comp (ref "D351")
      (value "LED-BLUE0603")
      (footprint "eagle-import:LED-0603")
      (libsource (lib "eagle-import") (part "LED-BLUE0603"))
    )
    (comp (ref "D352")
      (value "LED-BLUE0603")
      (footprint "eagle-import:LED-0603")
      (libsource (lib "eagle-import") (part "LED-BLUE0603"))
    )
    (comp (ref "D353")
      (value "LED-BLUE0603")
      (footprint "eagle-import:LED-0603")
      (libsource (lib "eagle-import") (part "LED-BLUE0603"))
    )
    (comp (ref "D354")
      (value "LED-BLUE0603")
      (footprint "eagle-import:LED-0603")
      (libsource (lib "eagle-import") (part "LED-BLUE0603"))
    )
    (comp (ref "D355")
      (value "LED-BLUE0603")
      (footprint "eagle-import:LED-0603")
      (libsource (lib "eagle-import") (part "LED-BLUE0603"))
    )
    (comp (ref "D356")
      (value "LED-BLUE0603")
      (footprint "eagle-import:LED-0603")
      (libsource (lib "eagle-import") (part "LED-BLUE0603"))
    )
    (comp (ref "D357")
      (value "LED-BLUE0603")
      (footprint "eagle-import:LED-0603")
      (libsource (lib "eagle-import") (part "LED-BLUE0603"))
    )
    (comp (ref "D358")
      (value "LED-BLUE0603")
      (footprint "eagle-import:LED-0603")
      (libsource (lib "eagle-import") (part "LED-BLUE0603"))
    )
    (comp (ref "D359")
      (value "LED-BLUE0603")
      (footprint "eagle-import:LED-0603")
      (libsource (lib "eagle-import") (part "LED-BLUE0603"))
    )
    (comp (ref "D360")
      (value "LED-BLUE0603")
      (footprint "eagle-import:LED-0603")
      (libsource (lib "eagle-import") (part "LED-BLUE0603"))
    )
    (comp (ref "D361")
      (value "LED-BLUE0603")
      (footprint "eagle-import:LED-0603")
      (libsource (lib "eagle-import") (part "LED-BLUE0603"))
    )
    (comp (ref "D362")
      (value "LED-BLUE0603")
      (footprint "eagle-import:LED-0603")
      (libsource (lib "eagle-import") (part "LED-BLUE0603"))
    )
    (comp (ref "D363")
      (value "LED-BLUE0603")
      (footprint "eagle-import:LED-0603")
      (libsource (lib "eagle-import") (part "LED-BLUE0603"))
    )
    (comp (ref "D364")
      (value "LED-BLUE0603")
      (footprint "eagle-import:LED-0603")
      (libsource (lib "eagle-import") (part "LED-BLUE0603"))
    )
    (comp (ref "D365")
      (value "LED-BLUE0603")
      (footprint "eagle-import:LED-0603")
      (libsource (lib "eagle-import") (part "LED-BLUE0603"))
    )
    (comp (ref "D366")
      (value "LED-BLUE0603")
      (footprint "eagle-import:LED-0603")
      (libsource (lib "eagle-import") (part "LED-BLUE0603"))
    )
    (comp (ref "D367")
      (value "LED-BLUE0603")
      (footprint "eagle-import:LED-0603")
      (libsource (lib "eagle-import") (part "LED-BLUE0603"))
    )
    (comp (ref "D368")
      (value "LED-BLUE0603")
      (footprint "eagle-import:LED-0603")
      (libsource (lib "eagle-import") (part "LED-BLUE0603"))
    )
    (comp (ref "D369")
      (value "LED-BLUE0603")
      (footprint "eagle-import:LED-0603")
      (libsource (lib "eagle-import") (part "LED-BLUE0603"))
    )
    (comp (ref "D370")
      (value "LED-BLUE0603")
      (footprint "eagle-import:LED-0603")
      (libsource (lib "eagle-import") (part "LED-BLUE0603"))
    )
    (comp (ref "D371")
      (value "LED-BLUE0603")
      (footprint "eagle-import:LED-0603")
      (libsource (lib "eagle-import") (part "LED-BLUE0603"))
    )
    (comp (ref "D372")
      (value "LED-BLUE0603")
      (footprint "eagle-import:LED-0603")
      (libsource (lib "eagle-import") (part "LED-BLUE0603"))
    )
    (comp (ref "D373")
      (value "LED-BLUE0603")
      (footprint "eagle-import:LED-0603")
      (libsource (lib "eagle-import") (part "LED-BLUE0603"))
    )
    (comp (ref "D374")
      (value "LED-BLUE0603")
      (footprint "eagle-import:LED-0603")
      (libsource (lib "eagle-import") (part "LED-BLUE0603"))
    )
    (comp (ref "D375")
      (value "LED-BLUE0603")
      (footprint "eagle-import:LED-0603")
      (libsource (lib "eagle-import") (part "LED-BLUE0603"))
    )
    (comp (ref "D376")
      (value "LED-BLUE0603")
      (footprint "eagle-import:LED-0603")
      (libsource (lib "eagle-import") (part "LED-BLUE0603"))
    )
    (comp (ref "D377")
      (value "LED-BLUE0603")
      (footprint "eagle-import:LED-0603")
      (libsource (lib "eagle-import") (part "LED-BLUE0603"))
    )
    (comp (ref "D378")
      (value "LED-BLUE0603")
      (footprint "eagle-import:LED-0603")
      (libsource (lib "eagle-import") (part "LED-BLUE0603"))
    )
    (comp (ref "D379")
      (value "LED-BLUE0603")
      (footprint "eagle-import:LED-0603")
      (libsource (lib "eagle-import") (part "LED-BLUE0603"))
    )
    (comp (ref "D380")
      (value "LED-BLUE0603")
      (footprint "eagle-import:LED-0603")
      (libsource (lib "eagle-import") (part "LED-BLUE0603"))
    )
    (comp (ref "D381")
      (value "LED-BLUE0603")
      (footprint "eagle-import:LED-0603")
      (libsource (lib "eagle-import") (part "LED-BLUE0603"))
    )
    (comp (ref "D382")
      (value "LED-BLUE0603")
      (footprint "eagle-import:LED-0603")
      (libsource (lib "eagle-import") (part "LED-BLUE0603"))
    )
    (comp (ref "D383")
      (value "LED-BLUE0603")
      (footprint "eagle-import:LED-0603")
      (libsource (lib "eagle-import") (part "LED-BLUE0603"))
    )
    (comp (ref "D384")
      (value "LED-BLUE0603")
      (footprint "eagle-import:LED-0603")
      (libsource (lib "eagle-import") (part "LED-BLUE0603"))
    )
    (comp (ref "D385")
      (value "LED-BLUE0603")
      (footprint "eagle-import:LED-0603")
      (libsource (lib "eagle-import") (part "LED-BLUE0603"))
    )
    (comp (ref "D386")
      (value "LED-BLUE0603")
      (footprint "eagle-import:LED-0603")
      (libsource (lib "eagle-import") (part "LED-BLUE0603"))
    )
    (comp (ref "D387")
      (value "LED-BLUE0603")
      (footprint "eagle-import:LED-0603")
      (libsource (lib "eagle-import") (part "LED-BLUE0603"))
    )
    (comp (ref "D388")
      (value "LED-BLUE0603")
      (footprint "eagle-import:LED-0603")
      (libsource (lib "eagle-import") (part "LED-BLUE0603"))
    )
    (comp (ref "D389")
      (value "LED-BLUE0603")
      (footprint "eagle-import:LED-0603")
      (libsource (lib "eagle-import") (part "LED-BLUE0603"))
    )
    (comp (ref "D390")
      (value "LED-BLUE0603")
      (footprint "eagle-import:LED-0603")
      (libsource (lib "eagle-import") (part "LED-BLUE0603"))
    )
    (comp (ref "D391")
      (value "LED-BLUE0603")
      (footprint "eagle-import:LED-0603")
      (libsource (lib "eagle-import") (part "LED-BLUE0603"))
    )
    (comp (ref "D392")
      (value "LED-BLUE0603")
      (footprint "eagle-import:LED-0603")
      (libsource (lib "eagle-import") (part "LED-BLUE0603"))
    )
    (comp (ref "D393")
      (value "LED-BLUE0603")
      (footprint "eagle-import:LED-0603")
      (libsource (lib "eagle-import") (part "LED-BLUE0603"))
    )
    (comp (ref "D394")
      (value "LED-BLUE0603")
      (footprint "eagle-import:LED-0603")
      (libsource (lib "eagle-import") (part "LED-BLUE0603"))
    )
    (comp (ref "D395")
      (value "LED-BLUE0603")
      (footprint "eagle-import:LED-0603")
      (libsource (lib "eagle-import") (part "LED-BLUE0603"))
    )
    (comp (ref "D396")
      (value "LED-BLUE0603")
      (footprint "eagle-import:LED-0603")
      (libsource (lib "eagle-import") (part "LED-BLUE0603"))
    )
    (comp (ref "D397")
      (value "LED-BLUE0603")
      (footprint "eagle-import:LED-0603")
      (libsource (lib "eagle-import") (part "LED-BLUE0603"))
    )
    (comp (ref "D398")
      (value "LED-BLUE0603")
      (footprint "eagle-import:LED-0603")
      (libsource (lib "eagle-import") (part "LED-BLUE0603"))
    )
    (comp (ref "D399")
      (value "LED-BLUE0603")
      (footprint "eagle-import:LED-0603")
      (libsource (lib "eagle-import") (part "LED-BLUE0603"))
    )
    (comp (ref "D400")
      (value "LED-BLUE0603")
      (footprint "eagle-import:LED-0603")
      (libsource (lib "eagle-import") (part "LED-BLUE0603"))
    )
    (comp (ref "D401")
      (value "LED-BLUE0603")
      (footprint "eagle-import:LED-0603")
      (libsource (lib "eagle-import") (part "LED-BLUE0603"))
    )
    (comp (ref "D402")
      (value "LED-BLUE0603")
      (footprint "eagle-import:LED-0603")
      (libsource (lib "eagle-import") (part "LED-BLUE0603"))
    )
    (comp (ref "D403")
      (value "LED-BLUE0603")
      (footprint "eagle-import:LED-0603")
      (libsource (lib "eagle-import") (part "LED-BLUE0603"))
    )
    (comp (ref "D404")
      (value "LED-BLUE0603")
      (footprint "eagle-import:LED-0603")
      (libsource (lib "eagle-import") (part "LED-BLUE0603"))
    )
    (comp (ref "D405")
      (value "LED-BLUE0603")
      (footprint "eagle-import:LED-0603")
      (libsource (lib "eagle-import") (part "LED-BLUE0603"))
    )
    (comp (ref "D406")
      (value "LED-BLUE0603")
      (footprint "eagle-import:LED-0603")
      (libsource (lib "eagle-import") (part "LED-BLUE0603"))
    )
    (comp (ref "D407")
      (value "LED-BLUE0603")
      (footprint "eagle-import:LED-0603")
      (libsource (lib "eagle-import") (part "LED-BLUE0603"))
    )
    (comp (ref "D408")
      (value "LED-BLUE0603")
      (footprint "eagle-import:LED-0603")
      (libsource (lib "eagle-import") (part "LED-BLUE0603"))
    )
    (comp (ref "D409")
      (value "LED-BLUE0603")
      (footprint "eagle-import:LED-0603")
      (libsource (lib "eagle-import") (part "LED-BLUE0603"))
    )
    (comp (ref "D410")
      (value "LED-BLUE0603")
      (footprint "eagle-import:LED-0603")
      (libsource (lib "eagle-import") (part "LED-BLUE0603"))
    )
    (comp (ref "D411")
      (value "LED-BLUE0603")
      (footprint "eagle-import:LED-0603")
      (libsource (lib "eagle-import") (part "LED-BLUE0603"))
    )
    (comp (ref "D412")
      (value "LED-BLUE0603")
      (footprint "eagle-import:LED-0603")
      (libsource (lib "eagle-import") (part "LED-BLUE0603"))
    )
    (comp (ref "D413")
      (value "LED-BLUE0603")
      (footprint "eagle-import:LED-0603")
      (libsource (lib "eagle-import") (part "LED-BLUE0603"))
    )
    (comp (ref "D414")
      (value "LED-BLUE0603")
      (footprint "eagle-import:LED-0603")
      (libsource (lib "eagle-import") (part "LED-BLUE0603"))
    )
    (comp (ref "D415")
      (value "LED-BLUE0603")
      (footprint "eagle-import:LED-0603")
      (libsource (lib "eagle-import") (part "LED-BLUE0603"))
    )
    (comp (ref "D416")
      (value "LED-BLUE0603")
      (footprint "eagle-import:LED-0603")
      (libsource (lib "eagle-import") (part "LED-BLUE0603"))
    )
    (comp (ref "D417")
      (value "LED-BLUE0603")
      (footprint "eagle-import:LED-0603")
      (libsource (lib "eagle-import") (part "LED-BLUE0603"))
    )
    (comp (ref "D418")
      (value "LED-BLUE0603")
      (footprint "eagle-import:LED-0603")
      (libsource (lib "eagle-import") (part "LED-BLUE0603"))
    )
    (comp (ref "D419")
      (value "LED-BLUE0603")
      (footprint "eagle-import:LED-0603")
      (libsource (lib "eagle-import") (part "LED-BLUE0603"))
    )
    (comp (ref "D420")
      (value "LED-BLUE0603")
      (footprint "eagle-import:LED-0603")
      (libsource (lib "eagle-import") (part "LED-BLUE0603"))
    )
    (comp (ref "D421")
      (value "LED-BLUE0603")
      (footprint "eagle-import:LED-0603")
      (libsource (lib "eagle-import") (part "LED-BLUE0603"))
    )
    (comp (ref "D422")
      (value "LED-BLUE0603")
      (footprint "eagle-import:LED-0603")
      (libsource (lib "eagle-import") (part "LED-BLUE0603"))
    )
    (comp (ref "D423")
      (value "LED-BLUE0603")
      (footprint "eagle-import:LED-0603")
      (libsource (lib "eagle-import") (part "LED-BLUE0603"))
    )
    (comp (ref "D424")
      (value "LED-BLUE0603")
      (footprint "eagle-import:LED-0603")
      (libsource (lib "eagle-import") (part "LED-BLUE0603"))
    )
    (comp (ref "D425")
      (value "LED-BLUE0603")
      (footprint "eagle-import:LED-0603")
      (libsource (lib "eagle-import") (part "LED-BLUE0603"))
    )
    (comp (ref "D426")
      (value "LED-BLUE0603")
      (footprint "eagle-import:LED-0603")
      (libsource (lib "eagle-import") (part "LED-BLUE0603"))
    )
    (comp (ref "D427")
      (value "LED-BLUE0603")
      (footprint "eagle-import:LED-0603")
      (libsource (lib "eagle-import") (part "LED-BLUE0603"))
    )
    (comp (ref "D428")
      (value "LED-BLUE0603")
      (footprint "eagle-import:LED-0603")
      (libsource (lib "eagle-import") (part "LED-BLUE0603"))
    )
    (comp (ref "D429")
      (value "LED-BLUE0603")
      (footprint "eagle-import:LED-0603")
      (libsource (lib "eagle-import") (part "LED-BLUE0603"))
    )
    (comp (ref "D430")
      (value "LED-BLUE0603")
      (footprint "eagle-import:LED-0603")
      (libsource (lib "eagle-import") (part "LED-BLUE0603"))
    )
    (comp (ref "D431")
      (value "LED-BLUE0603")
      (footprint "eagle-import:LED-0603")
      (libsource (lib "eagle-import") (part "LED-BLUE0603"))
    )
    (comp (ref "D432")
      (value "LED-BLUE0603")
      (footprint "eagle-import:LED-0603")
      (libsource (lib "eagle-import") (part "LED-BLUE0603"))
    )
    (comp (ref "D433")
      (value "LED-BLUE0603")
      (footprint "eagle-import:LED-0603")
      (libsource (lib "eagle-import") (part "LED-BLUE0603"))
    )
    (comp (ref "D434")
      (value "LED-BLUE0603")
      (footprint "eagle-import:LED-0603")
      (libsource (lib "eagle-import") (part "LED-BLUE0603"))
    )
    (comp (ref "D435")
      (value "LED-BLUE0603")
      (footprint "eagle-import:LED-0603")
      (libsource (lib "eagle-import") (part "LED-BLUE0603"))
    )
    (comp (ref "D436")
      (value "LED-BLUE0603")
      (footprint "eagle-import:LED-0603")
      (libsource (lib "eagle-import") (part "LED-BLUE0603"))
    )
    (comp (ref "D437")
      (value "LED-BLUE0603")
      (footprint "eagle-import:LED-0603")
      (libsource (lib "eagle-import") (part "LED-BLUE0603"))
    )
    (comp (ref "D438")
      (value "LED-BLUE0603")
      (footprint "eagle-import:LED-0603")
      (libsource (lib "eagle-import") (part "LED-BLUE0603"))
    )
    (comp (ref "D439")
      (value "LED-BLUE0603")
      (footprint "eagle-import:LED-0603")
      (libsource (lib "eagle-import") (part "LED-BLUE0603"))
    )
    (comp (ref "D440")
      (value "LED-BLUE0603")
      (footprint "eagle-import:LED-0603")
      (libsource (lib "eagle-import") (part "LED-BLUE0603"))
    )
    (comp (ref "D441")
      (value "LED-BLUE0603")
      (footprint "eagle-import:LED-0603")
      (libsource (lib "eagle-import") (part "LED-BLUE0603"))
    )
    (comp (ref "D442")
      (value "LED-BLUE0603")
      (footprint "eagle-import:LED-0603")
      (libsource (lib "eagle-import") (part "LED-BLUE0603"))
    )
    (comp (ref "D443")
      (value "LED-BLUE0603")
      (footprint "eagle-import:LED-0603")
      (libsource (lib "eagle-import") (part "LED-BLUE0603"))
    )
    (comp (ref "D444")
      (value "LED-BLUE0603")
      (footprint "eagle-import:LED-0603")
      (libsource (lib "eagle-import") (part "LED-BLUE0603"))
    )
    (comp (ref "D445")
      (value "LED-BLUE0603")
      (footprint "eagle-import:LED-0603")
      (libsource (lib "eagle-import") (part "LED-BLUE0603"))
    )
    (comp (ref "D446")
      (value "LED-BLUE0603")
      (footprint "eagle-import:LED-0603")
      (libsource (lib "eagle-import") (part "LED-BLUE0603"))
    )
    (comp (ref "D447")
      (value "LED-BLUE0603")
      (footprint "eagle-import:LED-0603")
      (libsource (lib "eagle-import") (part "LED-BLUE0603"))
    )
    (comp (ref "D448")
      (value "LED-BLUE0603")
      (footprint "eagle-import:LED-0603")
      (libsource (lib "eagle-import") (part "LED-BLUE0603"))
    )
    (comp (ref "D449")
      (value "LED-BLUE0603")
      (footprint "eagle-import:LED-0603")
      (libsource (lib "eagle-import") (part "LED-BLUE0603"))
    )
    (comp (ref "D450")
      (value "LED-BLUE0603")
      (footprint "eagle-import:LED-0603")
      (libsource (lib "eagle-import") (part "LED-BLUE0603"))
    )
    (comp (ref "D451")
      (value "LED-BLUE0603")
      (footprint "eagle-import:LED-0603")
      (libsource (lib "eagle-import") (part "LED-BLUE0603"))
    )
    (comp (ref "D452")
      (value "LED-BLUE0603")
      (footprint "eagle-import:LED-0603")
      (libsource (lib "eagle-import") (part "LED-BLUE0603"))
    )
    (comp (ref "D453")
      (value "LED-BLUE0603")
      (footprint "eagle-import:LED-0603")
      (libsource (lib "eagle-import") (part "LED-BLUE0603"))
    )
    (comp (ref "D454")
      (value "LED-BLUE0603")
      (footprint "eagle-import:LED-0603")
      (libsource (lib "eagle-import") (part "LED-BLUE0603"))
    )
    (comp (ref "D455")
      (value "LED-BLUE0603")
      (footprint "eagle-import:LED-0603")
      (libsource (lib "eagle-import") (part "LED-BLUE0603"))
    )
    (comp (ref "D456")
      (value "LED-BLUE0603")
      (footprint "eagle-import:LED-0603")
      (libsource (lib "eagle-import") (part "LED-BLUE0603"))
    )
    (comp (ref "D457")
      (value "LED-BLUE0603")
      (footprint "eagle-import:LED-0603")
      (libsource (lib "eagle-import") (part "LED-BLUE0603"))
    )
    (comp (ref "D458")
      (value "LED-BLUE0603")
      (footprint "eagle-import:LED-0603")
      (libsource (lib "eagle-import") (part "LED-BLUE0603"))
    )
    (comp (ref "D459")
      (value "LED-BLUE0603")
      (footprint "eagle-import:LED-0603")
      (libsource (lib "eagle-import") (part "LED-BLUE0603"))
    )
    (comp (ref "D460")
      (value "LED-BLUE0603")
      (footprint "eagle-import:LED-0603")
      (libsource (lib "eagle-import") (part "LED-BLUE0603"))
    )
    (comp (ref "D461")
      (value "LED-BLUE0603")
      (footprint "eagle-import:LED-0603")
      (libsource (lib "eagle-import") (part "LED-BLUE0603"))
    )
    (comp (ref "D462")
      (value "LED-BLUE0603")
      (footprint "eagle-import:LED-0603")
      (libsource (lib "eagle-import") (part "LED-BLUE0603"))
    )
    (comp (ref "D463")
      (value "LED-BLUE0603")
      (footprint "eagle-import:LED-0603")
      (libsource (lib "eagle-import") (part "LED-BLUE0603"))
    )
    (comp (ref "D464")
      (value "LED-BLUE0603")
      (footprint "eagle-import:LED-0603")
      (libsource (lib "eagle-import") (part "LED-BLUE0603"))
    )
    (comp (ref "D465")
      (value "LED-BLUE0603")
      (footprint "eagle-import:LED-0603")
      (libsource (lib "eagle-import") (part "LED-BLUE0603"))
    )
    (comp (ref "D466")
      (value "LED-BLUE0603")
      (footprint "eagle-import:LED-0603")
      (libsource (lib "eagle-import") (part "LED-BLUE0603"))
    )
    (comp (ref "D467")
      (value "LED-BLUE0603")
      (footprint "eagle-import:LED-0603")
      (libsource (lib "eagle-import") (part "LED-BLUE0603"))
    )
    (comp (ref "D468")
      (value "LED-BLUE0603")
      (footprint "eagle-import:LED-0603")
      (libsource (lib "eagle-import") (part "LED-BLUE0603"))
    )
    (comp (ref "D469")
      (value "LED-BLUE0603")
      (footprint "eagle-import:LED-0603")
      (libsource (lib "eagle-import") (part "LED-BLUE0603"))
    )
    (comp (ref "D470")
      (value "LED-BLUE0603")
      (footprint "eagle-import:LED-0603")
      (libsource (lib "eagle-import") (part "LED-BLUE0603"))
    )
    (comp (ref "D471")
      (value "LED-BLUE0603")
      (footprint "eagle-import:LED-0603")
      (libsource (lib "eagle-import") (part "LED-BLUE0603"))
    )
    (comp (ref "D472")
      (value "LED-BLUE0603")
      (footprint "eagle-import:LED-0603")
      (libsource (lib "eagle-import") (part "LED-BLUE0603"))
    )
    (comp (ref "D473")
      (value "LED-BLUE0603")
      (footprint "eagle-import:LED-0603")
      (libsource (lib "eagle-import") (part "LED-BLUE0603"))
    )
    (comp (ref "D474")
      (value "LED-BLUE0603")
      (footprint "eagle-import:LED-0603")
      (libsource (lib "eagle-import") (part "LED-BLUE0603"))
    )
    (comp (ref "D475")
      (value "LED-BLUE0603")
      (footprint "eagle-import:LED-0603")
      (libsource (lib "eagle-import") (part "LED-BLUE0603"))
    )
    (comp (ref "D476")
      (value "LED-BLUE0603")
      (footprint "eagle-import:LED-0603")
      (libsource (lib "eagle-import") (part "LED-BLUE0603"))
    )
    (comp (ref "D477")
      (value "LED-BLUE0603")
      (footprint "eagle-import:LED-0603")
      (libsource (lib "eagle-import") (part "LED-BLUE0603"))
    )
    (comp (ref "D478")
      (value "LED-BLUE0603")
      (footprint "eagle-import:LED-0603")
      (libsource (lib "eagle-import") (part "LED-BLUE0603"))
    )
    (comp (ref "D479")
      (value "LED-BLUE0603")
      (footprint "eagle-import:LED-0603")
      (libsource (lib "eagle-import") (part "LED-BLUE0603"))
    )
    (comp (ref "D480")
      (value "LED-BLUE0603")
      (footprint "eagle-import:LED-0603")
      (libsource (lib "eagle-import") (part "LED-BLUE0603"))
    )
    (comp (ref "D481")
      (value "LED-BLUE0603")
      (footprint "eagle-import:LED-0603")
      (libsource (lib "eagle-import") (part "LED-BLUE0603"))
    )
    (comp (ref "D482")
      (value "LED-BLUE0603")
      (footprint "eagle-import:LED-0603")
      (libsource (lib "eagle-import") (part "LED-BLUE0603"))
    )
    (comp (ref "D483")
      (value "LED-BLUE0603")
      (footprint "eagle-import:LED-0603")
      (libsource (lib "eagle-import") (part "LED-BLUE0603"))
    )
    (comp (ref "D484")
      (value "LED-BLUE0603")
      (footprint "eagle-import:LED-0603")
      (libsource (lib "eagle-import") (part "LED-BLUE0603"))
    )
    (comp (ref "D485")
      (value "LED-BLUE0603")
      (footprint "eagle-import:LED-0603")
      (libsource (lib "eagle-import") (part "LED-BLUE0603"))
    )
    (comp (ref "D486")
      (value "LED-BLUE0603")
      (footprint "eagle-import:LED-0603")
      (libsource (lib "eagle-import") (part "LED-BLUE0603"))
    )
    (comp (ref "D487")
      (value "LED-BLUE0603")
      (footprint "eagle-import:LED-0603")
      (libsource (lib "eagle-import") (part "LED-BLUE0603"))
    )
    (comp (ref "D488")
      (value "LED-BLUE0603")
      (footprint "eagle-import:LED-0603")
      (libsource (lib "eagle-import") (part "LED-BLUE0603"))
    )
    (comp (ref "D489")
      (value "LED-BLUE0603")
      (footprint "eagle-import:LED-0603")
      (libsource (lib "eagle-import") (part "LED-BLUE0603"))
    )
    (comp (ref "D490")
      (value "LED-BLUE0603")
      (footprint "eagle-import:LED-0603")
      (libsource (lib "eagle-import") (part "LED-BLUE0603"))
    )
    (comp (ref "D491")
      (value "LED-BLUE0603")
      (footprint "eagle-import:LED-0603")
      (libsource (lib "eagle-import") (part "LED-BLUE0603"))
    )
    (comp (ref "D492")
      (value "LED-BLUE0603")
      (footprint "eagle-import:LED-0603")
      (libsource (lib "eagle-import") (part "LED-BLUE0603"))
    )
    (comp (ref "D493")
      (value "LED-BLUE0603")
      (footprint "eagle-import:LED-0603")
      (libsource (lib "eagle-import") (part "LED-BLUE0603"))
    )
    (comp (ref "D494")
      (value "LED-BLUE0603")
      (footprint "eagle-import:LED-0603")
      (libsource (lib "eagle-import") (part "LED-BLUE0603"))
    )
    (comp (ref "D495")
      (value "LED-BLUE0603")
      (footprint "eagle-import:LED-0603")
      (libsource (lib "eagle-import") (part "LED-BLUE0603"))
    )
    (comp (ref "D496")
      (value "LED-BLUE0603")
      (footprint "eagle-import:LED-0603")
      (libsource (lib "eagle-import") (part "LED-BLUE0603"))
    )
    (comp (ref "D497")
      (value "LED-BLUE0603")
      (footprint "eagle-import:LED-0603")
      (libsource (lib "eagle-import") (part "LED-BLUE0603"))
    )
    (comp (ref "D498")
      (value "LED-BLUE0603")
      (footprint "eagle-import:LED-0603")
      (libsource (lib "eagle-import") (part "LED-BLUE0603"))
    )
    (comp (ref "D499")
      (value "LED-BLUE0603")
      (footprint "eagle-import:LED-0603")
      (libsource (lib "eagle-import") (part "LED-BLUE0603"))
    )
    (comp (ref "D500")
      (value "LED-BLUE0603")
      (footprint "eagle-import:LED-0603")
      (libsource (lib "eagle-import") (part "LED-BLUE0603"))
    )
    (comp (ref "D501")
      (value "LED-BLUE0603")
      (footprint "eagle-import:LED-0603")
      (libsource (lib "eagle-import") (part "LED-BLUE0603"))
    )
    (comp (ref "D502")
      (value "LED-BLUE0603")
      (footprint "eagle-import:LED-0603")
      (libsource (lib "eagle-import") (part "LED-BLUE0603"))
    )
    (comp (ref "D503")
      (value "LED-BLUE0603")
      (footprint "eagle-import:LED-0603")
      (libsource (lib "eagle-import") (part "LED-BLUE0603"))
    )
    (comp (ref "D504")
      (value "LED-BLUE0603")
      (footprint "eagle-import:LED-0603")
      (libsource (lib "eagle-import") (part "LED-BLUE0603"))
    )
    (comp (ref "D505")
      (value "LED-BLUE0603")
      (footprint "eagle-import:LED-0603")
      (libsource (lib "eagle-import") (part "LED-BLUE0603"))
    )
    (comp (ref "D506")
      (value "LED-BLUE0603")
      (footprint "eagle-import:LED-0603")
      (libsource (lib "eagle-import") (part "LED-BLUE0603"))
    )
    (comp (ref "D507")
      (value "LED-BLUE0603")
      (footprint "eagle-import:LED-0603")
      (libsource (lib "eagle-import") (part "LED-BLUE0603"))
    )
    (comp (ref "D508")
      (value "LED-BLUE0603")
      (footprint "eagle-import:LED-0603")
      (libsource (lib "eagle-import") (part "LED-BLUE0603"))
    )
    (comp (ref "D509")
      (value "LED-BLUE0603")
      (footprint "eagle-import:LED-0603")
      (libsource (lib "eagle-import") (part "LED-BLUE0603"))
    )
    (comp (ref "D510")
      (value "LED-BLUE0603")
      (footprint "eagle-import:LED-0603")
      (libsource (lib "eagle-import") (part "LED-BLUE0603"))
    )
    (comp (ref "D511")
      (value "LED-BLUE0603")
      (footprint "eagle-import:LED-0603")
      (libsource (lib "eagle-import") (part "LED-BLUE0603"))
    )
    (comp (ref "D512")
      (value "LED-BLUE0603")
      (footprint "eagle-import:LED-0603")
      (libsource (lib "eagle-import") (part "LED-BLUE0603"))
    )
    (comp (ref "D513")
      (value "LED-BLUE0603")
      (footprint "eagle-import:LED-0603")
      (libsource (lib "eagle-import") (part "LED-BLUE0603"))
    )
    (comp (ref "D514")
      (value "LED-BLUE0603")
      (footprint "eagle-import:LED-0603")
      (libsource (lib "eagle-import") (part "LED-BLUE0603"))
    )
    (comp (ref "D515")
      (value "LED-BLUE0603")
      (footprint "eagle-import:LED-0603")
      (libsource (lib "eagle-import") (part "LED-BLUE0603"))
    )
    (comp (ref "D516")
      (value "LED-BLUE0603")
      (footprint "eagle-import:LED-0603")
      (libsource (lib "eagle-import") (part "LED-BLUE0603"))
    )
    (comp (ref "D517")
      (value "LED-BLUE0603")
      (footprint "eagle-import:LED-0603")
      (libsource (lib "eagle-import") (part "LED-BLUE0603"))
    )
    (comp (ref "D518")
      (value "LED-BLUE0603")
      (footprint "eagle-import:LED-0603")
      (libsource (lib "eagle-import") (part "LED-BLUE0603"))
    )
    (comp (ref "D519")
      (value "LED-BLUE0603")
      (footprint "eagle-import:LED-0603")
      (libsource (lib "eagle-import") (part "LED-BLUE0603"))
    )
    (comp (ref "D520")
      (value "LED-BLUE0603")
      (footprint "eagle-import:LED-0603")
      (libsource (lib "eagle-import") (part "LED-BLUE0603"))
    )
    (comp (ref "D521")
      (value "LED-BLUE0603")
      (footprint "eagle-import:LED-0603")
      (libsource (lib "eagle-import") (part "LED-BLUE0603"))
    )
    (comp (ref "D522")
      (value "LED-BLUE0603")
      (footprint "eagle-import:LED-0603")
      (libsource (lib "eagle-import") (part "LED-BLUE0603"))
    )
    (comp (ref "D523")
      (value "LED-BLUE0603")
      (footprint "eagle-import:LED-0603")
      (libsource (lib "eagle-import") (part "LED-BLUE0603"))
    )
    (comp (ref "D524")
      (value "LED-BLUE0603")
      (footprint "eagle-import:LED-0603")
      (libsource (lib "eagle-import") (part "LED-BLUE0603"))
    )
    (comp (ref "D525")
      (value "LED-BLUE0603")
      (footprint "eagle-import:LED-0603")
      (libsource (lib "eagle-import") (part "LED-BLUE0603"))
    )
    (comp (ref "D526")
      (value "LED-BLUE0603")
      (footprint "eagle-import:LED-0603")
      (libsource (lib "eagle-import") (part "LED-BLUE0603"))
    )
    (comp (ref "D527")
      (value "LED-BLUE0603")
      (footprint "eagle-import:LED-0603")
      (libsource (lib "eagle-import") (part "LED-BLUE0603"))
    )
    (comp (ref "D528")
      (value "LED-BLUE0603")
      (footprint "eagle-import:LED-0603")
      (libsource (lib "eagle-import") (part "LED-BLUE0603"))
    )
    (comp (ref "D529")
      (value "LED-BLUE0603")
      (footprint "eagle-import:LED-0603")
      (libsource (lib "eagle-import") (part "LED-BLUE0603"))
    )
    (comp (ref "D530")
      (value "LED-BLUE0603")
      (footprint "eagle-import:LED-0603")
      (libsource (lib "eagle-import") (part "LED-BLUE0603"))
    )
    (comp (ref "D531")
      (value "LED-BLUE0603")
      (footprint "eagle-import:LED-0603")
      (libsource (lib "eagle-import") (part "LED-BLUE0603"))
    )
    (comp (ref "D532")
      (value "LED-BLUE0603")
      (footprint "eagle-import:LED-0603")
      (libsource (lib "eagle-import") (part "LED-BLUE0603"))
    )
    (comp (ref "D533")
      (value "LED-BLUE0603")
      (footprint "eagle-import:LED-0603")
      (libsource (lib "eagle-import") (part "LED-BLUE0603"))
    )
    (comp (ref "D534")
      (value "LED-BLUE0603")
      (footprint "eagle-import:LED-0603")
      (libsource (lib "eagle-import") (part "LED-BLUE0603"))
    )
    (comp (ref "D535")
      (value "LED-BLUE0603")
      (footprint "eagle-import:LED-0603")
      (libsource (lib "eagle-import") (part "LED-BLUE0603"))
    )
    (comp (ref "D536")
      (value "LED-BLUE0603")
      (footprint "eagle-import:LED-0603")
      (libsource (lib "eagle-import") (part "LED-BLUE0603"))
    )
    (comp (ref "D537")
      (value "LED-BLUE0603")
      (footprint "eagle-import:LED-0603")
      (libsource (lib "eagle-import") (part "LED-BLUE0603"))
    )
    (comp (ref "D538")
      (value "LED-BLUE0603")
      (footprint "eagle-import:LED-0603")
      (libsource (lib "eagle-import") (part "LED-BLUE0603"))
    )
    (comp (ref "D539")
      (value "LED-BLUE0603")
      (footprint "eagle-import:LED-0603")
      (libsource (lib "eagle-import") (part "LED-BLUE0603"))
    )
    (comp (ref "D540")
      (value "LED-BLUE0603")
      (footprint "eagle-import:LED-0603")
      (libsource (lib "eagle-import") (part "LED-BLUE0603"))
    )
    (comp (ref "D541")
      (value "LED-BLUE0603")
      (footprint "eagle-import:LED-0603")
      (libsource (lib "eagle-import") (part "LED-BLUE0603"))
    )
    (comp (ref "D542")
      (value "LED-BLUE0603")
      (footprint "eagle-import:LED-0603")
      (libsource (lib "eagle-import") (part "LED-BLUE0603"))
    )
    (comp (ref "D543")
      (value "LED-BLUE0603")
      (footprint "eagle-import:LED-0603")
      (libsource (lib "eagle-import") (part "LED-BLUE0603"))
    )
    (comp (ref "D544")
      (value "LED-BLUE0603")
      (footprint "eagle-import:LED-0603")
      (libsource (lib "eagle-import") (part "LED-BLUE0603"))
    )
    (comp (ref "D545")
      (value "LED-BLUE0603")
      (footprint "eagle-import:LED-0603")
      (libsource (lib "eagle-import") (part "LED-BLUE0603"))
    )
    (comp (ref "D546")
      (value "LED-BLUE0603")
      (footprint "eagle-import:LED-0603")
      (libsource (lib "eagle-import") (part "LED-BLUE0603"))
    )
    (comp (ref "D547")
      (value "LED-BLUE0603")
      (footprint "eagle-import:LED-0603")
      (libsource (lib "eagle-import") (part "LED-BLUE0603"))
    )
    (comp (ref "D548")
      (value "LED-BLUE0603")
      (footprint "eagle-import:LED-0603")
      (libsource (lib "eagle-import") (part "LED-BLUE0603"))
    )
    (comp (ref "D549")
      (value "LED-BLUE0603")
      (footprint "eagle-import:LED-0603")
      (libsource (lib "eagle-import") (part "LED-BLUE0603"))
    )
    (comp (ref "D550")
      (value "LED-BLUE0603")
      (footprint "eagle-import:LED-0603")
      (libsource (lib "eagle-import") (part "LED-BLUE0603"))
    )
    (comp (ref "D551")
      (value "LED-BLUE0603")
      (footprint "eagle-import:LED-0603")
      (libsource (lib "eagle-import") (part "LED-BLUE0603"))
    )
    (comp (ref "D552")
      (value "LED-BLUE0603")
      (footprint "eagle-import:LED-0603")
      (libsource (lib "eagle-import") (part "LED-BLUE0603"))
    )
    (comp (ref "D553")
      (value "LED-BLUE0603")
      (footprint "eagle-import:LED-0603")
      (libsource (lib "eagle-import") (part "LED-BLUE0603"))
    )
    (comp (ref "D554")
      (value "LED-BLUE0603")
      (footprint "eagle-import:LED-0603")
      (libsource (lib "eagle-import") (part "LED-BLUE0603"))
    )
    (comp (ref "D555")
      (value "LED-BLUE0603")
      (footprint "eagle-import:LED-0603")
      (libsource (lib "eagle-import") (part "LED-BLUE0603"))
    )
    (comp (ref "D556")
      (value "LED-BLUE0603")
      (footprint "eagle-import:LED-0603")
      (libsource (lib "eagle-import") (part "LED-BLUE0603"))
    )
    (comp (ref "D557")
      (value "LED-BLUE0603")
      (footprint "eagle-import:LED-0603")
      (libsource (lib "eagle-import") (part "LED-BLUE0603"))
    )
    (comp (ref "D558")
      (value "LED-BLUE0603")
      (footprint "eagle-import:LED-0603")
      (libsource (lib "eagle-import") (part "LED-BLUE0603"))
    )
    (comp (ref "D559")
      (value "LED-BLUE0603")
      (footprint "eagle-import:LED-0603")
      (libsource (lib "eagle-import") (part "LED-BLUE0603"))
    )
    (comp (ref "D560")
      (value "LED-BLUE0603")
      (footprint "eagle-import:LED-0603")
      (libsource (lib "eagle-import") (part "LED-BLUE0603"))
    )
    (comp (ref "D561")
      (value "LED-BLUE0603")
      (footprint "eagle-import:LED-0603")
      (libsource (lib "eagle-import") (part "LED-BLUE0603"))
    )
    (comp (ref "D562")
      (value "LED-BLUE0603")
      (footprint "eagle-import:LED-0603")
      (libsource (lib "eagle-import") (part "LED-BLUE0603"))
    )
    (comp (ref "D563")
      (value "LED-BLUE0603")
      (footprint "eagle-import:LED-0603")
      (libsource (lib "eagle-import") (part "LED-BLUE0603"))
    )
    (comp (ref "D564")
      (value "LED-BLUE0603")
      (footprint "eagle-import:LED-0603")
      (libsource (lib "eagle-import") (part "LED-BLUE0603"))
    )
    (comp (ref "D565")
      (value "LED-BLUE0603")
      (footprint "eagle-import:LED-0603")
      (libsource (lib "eagle-import") (part "LED-BLUE0603"))
    )
    (comp (ref "D566")
      (value "LED-BLUE0603")
      (footprint "eagle-import:LED-0603")
      (libsource (lib "eagle-import") (part "LED-BLUE0603"))
    )
    (comp (ref "D567")
      (value "LED-BLUE0603")
      (footprint "eagle-import:LED-0603")
      (libsource (lib "eagle-import") (part "LED-BLUE0603"))
    )
    (comp (ref "D568")
      (value "LED-BLUE0603")
      (footprint "eagle-import:LED-0603")
      (libsource (lib "eagle-import") (part "LED-BLUE0603"))
    )
    (comp (ref "D569")
      (value "LED-BLUE0603")
      (footprint "eagle-import:LED-0603")
      (libsource (lib "eagle-import") (part "LED-BLUE0603"))
    )
    (comp (ref "D570")
      (value "LED-BLUE0603")
      (footprint "eagle-import:LED-0603")
      (libsource (lib "eagle-import") (part "LED-BLUE0603"))
    )
    (comp (ref "D571")
      (value "LED-BLUE0603")
      (footprint "eagle-import:LED-0603")
      (libsource (lib "eagle-import") (part "LED-BLUE0603"))
    )
    (comp (ref "D572")
      (value "LED-BLUE0603")
      (footprint "eagle-import:LED-0603")
      (libsource (lib "eagle-import") (part "LED-BLUE0603"))
    )
    (comp (ref "D573")
      (value "LED-BLUE0603")
      (footprint "eagle-import:LED-0603")
      (libsource (lib "eagle-import") (part "LED-BLUE0603"))
    )
    (comp (ref "D574")
      (value "LED-BLUE0603")
      (footprint "eagle-import:LED-0603")
      (libsource (lib "eagle-import") (part "LED-BLUE0603"))
    )
    (comp (ref "D575")
      (value "LED-BLUE0603")
      (footprint "eagle-import:LED-0603")
      (libsource (lib "eagle-import") (part "LED-BLUE0603"))
    )
    (comp (ref "D576")
      (value "LED-BLUE0603")
      (footprint "eagle-import:LED-0603")
      (libsource (lib "eagle-import") (part "LED-BLUE0603"))
    )
    (comp (ref "D577")
      (value "LED-BLUE0603")
      (footprint "eagle-import:LED-0603")
      (libsource (lib "eagle-import") (part "LED-BLUE0603"))
    )
    (comp (ref "D578")
      (value "LED-BLUE0603")
      (footprint "eagle-import:LED-0603")
      (libsource (lib "eagle-import") (part "LED-BLUE0603"))
    )
    (comp (ref "D579")
      (value "LED-BLUE0603")
      (footprint "eagle-import:LED-0603")
      (libsource (lib "eagle-import") (part "LED-BLUE0603"))
    )
    (comp (ref "D580")
      (value "LED-BLUE0603")
      (footprint "eagle-import:LED-0603")
      (libsource (lib "eagle-import") (part "LED-BLUE0603"))
    )
    (comp (ref "D581")
      (value "LED-BLUE0603")
      (footprint "eagle-import:LED-0603")
      (libsource (lib "eagle-import") (part "LED-BLUE0603"))
    )
    (comp (ref "D582")
      (value "LED-BLUE0603")
      (footprint "eagle-import:LED-0603")
      (libsource (lib "eagle-import") (part "LED-BLUE0603"))
    )
    (comp (ref "D583")
      (value "LED-BLUE0603")
      (footprint "eagle-import:LED-0603")
      (libsource (lib "eagle-import") (part "LED-BLUE0603"))
    )
    (comp (ref "D584")
      (value "LED-BLUE0603")
      (footprint "eagle-import:LED-0603")
      (libsource (lib "eagle-import") (part "LED-BLUE0603"))
    )
    (comp (ref "D585")
      (value "LED-BLUE0603")
      (footprint "eagle-import:LED-0603")
      (libsource (lib "eagle-import") (part "LED-BLUE0603"))
    )
    (comp (ref "D586")
      (value "LED-BLUE0603")
      (footprint "eagle-import:LED-0603")
      (libsource (lib "eagle-import") (part "LED-BLUE0603"))
    )
    (comp (ref "D587")
      (value "LED-BLUE0603")
      (footprint "eagle-import:LED-0603")
      (libsource (lib "eagle-import") (part "LED-BLUE0603"))
    )
    (comp (ref "D588")
      (value "LED-BLUE0603")
      (footprint "eagle-import:LED-0603")
      (libsource (lib "eagle-import") (part "LED-BLUE0603"))
    )
    (comp (ref "D589")
      (value "LED-BLUE0603")
      (footprint "eagle-import:LED-0603")
      (libsource (lib "eagle-import") (part "LED-BLUE0603"))
    )
    (comp (ref "D590")
      (value "LED-BLUE0603")
      (footprint "eagle-import:LED-0603")
      (libsource (lib "eagle-import") (part "LED-BLUE0603"))
    )
    (comp (ref "D591")
      (value "LED-BLUE0603")
      (footprint "eagle-import:LED-0603")
      (libsource (lib "eagle-import") (part "LED-BLUE0603"))
    )
    (comp (ref "D592")
      (value "LED-BLUE0603")
      (footprint "eagle-import:LED-0603")
      (libsource (lib "eagle-import") (part "LED-BLUE0603"))
    )
    (comp (ref "D593")
      (value "LED-BLUE0603")
      (footprint "eagle-import:LED-0603")
      (libsource (lib "eagle-import") (part "LED-BLUE0603"))
    )
    (comp (ref "D594")
      (value "LED-BLUE0603")
      (footprint "eagle-import:LED-0603")
      (libsource (lib "eagle-import") (part "LED-BLUE0603"))
    )
    (comp (ref "D595")
      (value "LED-BLUE0603")
      (footprint "eagle-import:LED-0603")
      (libsource (lib "eagle-import") (part "LED-BLUE0603"))
    )
    (comp (ref "D596")
      (value "LED-BLUE0603")
      (footprint "eagle-import:LED-0603")
      (libsource (lib "eagle-import") (part "LED-BLUE0603"))
    )
    (comp (ref "D597")
      (value "LED-BLUE0603")
      (footprint "eagle-import:LED-0603")
      (libsource (lib "eagle-import") (part "LED-BLUE0603"))
    )
    (comp (ref "D598")
      (value "LED-BLUE0603")
      (footprint "eagle-import:LED-0603")
      (libsource (lib "eagle-import") (part "LED-BLUE0603"))
    )
    (comp (ref "D599")
      (value "LED-BLUE0603")
      (footprint "eagle-import:LED-0603")
      (libsource (lib "eagle-import") (part "LED-BLUE0603"))
    )
    (comp (ref "D600")
      (value "LED-BLUE0603")
      (footprint "eagle-import:LED-0603")
      (libsource (lib "eagle-import") (part "LED-BLUE0603"))
    )
    (comp (ref "D601")
      (value "LED-BLUE0603")
      (footprint "eagle-import:LED-0603")
      (libsource (lib "eagle-import") (part "LED-BLUE0603"))
    )
    (comp (ref "D602")
      (value "LED-BLUE0603")
      (footprint "eagle-import:LED-0603")
      (libsource (lib "eagle-import") (part "LED-BLUE0603"))
    )
    (comp (ref "D603")
      (value "LED-BLUE0603")
      (footprint "eagle-import:LED-0603")
      (libsource (lib "eagle-import") (part "LED-BLUE0603"))
    )
    (comp (ref "D604")
      (value "LED-BLUE0603")
      (footprint "eagle-import:LED-0603")
      (libsource (lib "eagle-import") (part "LED-BLUE0603"))
    )
    (comp (ref "D605")
      (value "LED-BLUE0603")
      (footprint "eagle-import:LED-0603")
      (libsource (lib "eagle-import") (part "LED-BLUE0603"))
    )
    (comp (ref "D606")
      (value "LED-BLUE0603")
      (footprint "eagle-import:LED-0603")
      (libsource (lib "eagle-import") (part "LED-BLUE0603"))
    )
    (comp (ref "D607")
      (value "LED-BLUE0603")
      (footprint "eagle-import:LED-0603")
      (libsource (lib "eagle-import") (part "LED-BLUE0603"))
    )
    (comp (ref "D608")
      (value "LED-BLUE0603")
      (footprint "eagle-import:LED-0603")
      (libsource (lib "eagle-import") (part "LED-BLUE0603"))
    )
    (comp (ref "D609")
      (value "LED-BLUE0603")
      (footprint "eagle-import:LED-0603")
      (libsource (lib "eagle-import") (part "LED-BLUE0603"))
    )
    (comp (ref "D610")
      (value "LED-BLUE0603")
      (footprint "eagle-import:LED-0603")
      (libsource (lib "eagle-import") (part "LED-BLUE0603"))
    )
    (comp (ref "D611")
      (value "LED-BLUE0603")
      (footprint "eagle-import:LED-0603")
      (libsource (lib "eagle-import") (part "LED-BLUE0603"))
    )
    (comp (ref "D612")
      (value "LED-BLUE0603")
      (footprint "eagle-import:LED-0603")
      (libsource (lib "eagle-import") (part "LED-BLUE0603"))
    )
    (comp (ref "D613")
      (value "LED-BLUE0603")
      (footprint "eagle-import:LED-0603")
      (libsource (lib "eagle-import") (part "LED-BLUE0603"))
    )
    (comp (ref "D614")
      (value "LED-BLUE0603")
      (footprint "eagle-import:LED-0603")
      (libsource (lib "eagle-import") (part "LED-BLUE0603"))
    )
    (comp (ref "D615")
      (value "LED-BLUE0603")
      (footprint "eagle-import:LED-0603")
      (libsource (lib "eagle-import") (part "LED-BLUE0603"))
    )
    (comp (ref "D616")
      (value "LED-BLUE0603")
      (footprint "eagle-import:LED-0603")
      (libsource (lib "eagle-import") (part "LED-BLUE0603"))
    )
    (comp (ref "D617")
      (value "LED-BLUE0603")
      (footprint "eagle-import:LED-0603")
      (libsource (lib "eagle-import") (part "LED-BLUE0603"))
    )
    (comp (ref "D618")
      (value "LED-BLUE0603")
      (footprint "eagle-import:LED-0603")
      (libsource (lib "eagle-import") (part "LED-BLUE0603"))
    )
    (comp (ref "D619")
      (value "LED-BLUE0603")
      (footprint "eagle-import:LED-0603")
      (libsource (lib "eagle-import") (part "LED-BLUE0603"))
    )
    (comp (ref "D620")
      (value "LED-BLUE0603")
      (footprint "eagle-import:LED-0603")
      (libsource (lib "eagle-import") (part "LED-BLUE0603"))
    )
    (comp (ref "D621")
      (value "LED-BLUE0603")
      (footprint "eagle-import:LED-0603")
      (libsource (lib "eagle-import") (part "LED-BLUE0603"))
    )
    (comp (ref "D622")
      (value "LED-BLUE0603")
      (footprint "eagle-import:LED-0603")
      (libsource (lib "eagle-import") (part "LED-BLUE0603"))
    )
    (comp (ref "D623")
      (value "LED-BLUE0603")
      (footprint "eagle-import:LED-0603")
      (libsource (lib "eagle-import") (part "LED-BLUE0603"))
    )
    (comp (ref "D624")
      (value "LED-BLUE0603")
      (footprint "eagle-import:LED-0603")
      (libsource (lib "eagle-import") (part "LED-BLUE0603"))
    )
    (comp (ref "D625")
      (value "LED-BLUE0603")
      (footprint "eagle-import:LED-0603")
      (libsource (lib "eagle-import") (part "LED-BLUE0603"))
    )
    (comp (ref "D626")
      (value "LED-BLUE0603")
      (footprint "eagle-import:LED-0603")
      (libsource (lib "eagle-import") (part "LED-BLUE0603"))
    )
    (comp (ref "D627")
      (value "LED-BLUE0603")
      (footprint "eagle-import:LED-0603")
      (libsource (lib "eagle-import") (part "LED-BLUE0603"))
    )
    (comp (ref "D628")
      (value "LED-BLUE0603")
      (footprint "eagle-import:LED-0603")
      (libsource (lib "eagle-import") (part "LED-BLUE0603"))
    )
    (comp (ref "D629")
      (value "LED-BLUE0603")
      (footprint "eagle-import:LED-0603")
      (libsource (lib "eagle-import") (part "LED-BLUE0603"))
    )
    (comp (ref "D630")
      (value "LED-BLUE0603")
      (footprint "eagle-import:LED-0603")
      (libsource (lib "eagle-import") (part "LED-BLUE0603"))
    )
    (comp (ref "D631")
      (value "LED-BLUE0603")
      (footprint "eagle-import:LED-0603")
      (libsource (lib "eagle-import") (part "LED-BLUE0603"))
    )
    (comp (ref "D632")
      (value "LED-BLUE0603")
      (footprint "eagle-import:LED-0603")
      (libsource (lib "eagle-import") (part "LED-BLUE0603"))
    )
    (comp (ref "D633")
      (value "LED-BLUE0603")
      (footprint "eagle-import:LED-0603")
      (libsource (lib "eagle-import") (part "LED-BLUE0603"))
    )
    (comp (ref "D634")
      (value "LED-BLUE0603")
      (footprint "eagle-import:LED-0603")
      (libsource (lib "eagle-import") (part "LED-BLUE0603"))
    )
    (comp (ref "D635")
      (value "LED-BLUE0603")
      (footprint "eagle-import:LED-0603")
      (libsource (lib "eagle-import") (part "LED-BLUE0603"))
    )
    (comp (ref "D636")
      (value "LED-BLUE0603")
      (footprint "eagle-import:LED-0603")
      (libsource (lib "eagle-import") (part "LED-BLUE0603"))
    )
    (comp (ref "D637")
      (value "LED-BLUE0603")
      (footprint "eagle-import:LED-0603")
      (libsource (lib "eagle-import") (part "LED-BLUE0603"))
    )
    (comp (ref "D638")
      (value "LED-BLUE0603")
      (footprint "eagle-import:LED-0603")
      (libsource (lib "eagle-import") (part "LED-BLUE0603"))
    )
    (comp (ref "D639")
      (value "LED-BLUE0603")
      (footprint "eagle-import:LED-0603")
      (libsource (lib "eagle-import") (part "LED-BLUE0603"))
    )
    (comp (ref "D640")
      (value "LED-BLUE0603")
      (footprint "eagle-import:LED-0603")
      (libsource (lib "eagle-import") (part "LED-BLUE0603"))
    )
    (comp (ref "D641")
      (value "LED-BLUE0603")
      (footprint "eagle-import:LED-0603")
      (libsource (lib "eagle-import") (part "LED-BLUE0603"))
    )
    (comp (ref "D642")
      (value "LED-BLUE0603")
      (footprint "eagle-import:LED-0603")
      (libsource (lib "eagle-import") (part "LED-BLUE0603"))
    )
    (comp (ref "D643")
      (value "LED-BLUE0603")
      (footprint "eagle-import:LED-0603")
      (libsource (lib "eagle-import") (part "LED-BLUE0603"))
    )
    (comp (ref "D644")
      (value "LED-BLUE0603")
      (footprint "eagle-import:LED-0603")
      (libsource (lib "eagle-import") (part "LED-BLUE0603"))
    )
    (comp (ref "D645")
      (value "LED-BLUE0603")
      (footprint "eagle-import:LED-0603")
      (libsource (lib "eagle-import") (part "LED-BLUE0603"))
    )
    (comp (ref "D646")
      (value "LED-BLUE0603")
      (footprint "eagle-import:LED-0603")
      (libsource (lib "eagle-import") (part "LED-BLUE0603"))
    )
    (comp (ref "D647")
      (value "LED-BLUE0603")
      (footprint "eagle-import:LED-0603")
      (libsource (lib "eagle-import") (part "LED-BLUE0603"))
    )
    (comp (ref "D648")
      (value "LED-BLUE0603")
      (footprint "eagle-import:LED-0603")
      (libsource (lib "eagle-import") (part "LED-BLUE0603"))
    )
    (comp (ref "D649")
      (value "LED-BLUE0603")
      (footprint "eagle-import:LED-0603")
      (libsource (lib "eagle-import") (part "LED-BLUE0603"))
    )
    (comp (ref "D650")
      (value "LED-BLUE0603")
      (footprint "eagle-import:LED-0603")
      (libsource (lib "eagle-import") (part "LED-BLUE0603"))
    )
    (comp (ref "D651")
      (value "LED-BLUE0603")
      (footprint "eagle-import:LED-0603")
      (libsource (lib "eagle-import") (part "LED-BLUE0603"))
    )
    (comp (ref "D652")
      (value "LED-BLUE0603")
      (footprint "eagle-import:LED-0603")
      (libsource (lib "eagle-import") (part "LED-BLUE0603"))
    )
    (comp (ref "D653")
      (value "LED-BLUE0603")
      (footprint "eagle-import:LED-0603")
      (libsource (lib "eagle-import") (part "LED-BLUE0603"))
    )
    (comp (ref "D654")
      (value "LED-BLUE0603")
      (footprint "eagle-import:LED-0603")
      (libsource (lib "eagle-import") (part "LED-BLUE0603"))
    )
    (comp (ref "D655")
      (value "LED-BLUE0603")
      (footprint "eagle-import:LED-0603")
      (libsource (lib "eagle-import") (part "LED-BLUE0603"))
    )
    (comp (ref "D656")
      (value "LED-BLUE0603")
      (footprint "eagle-import:LED-0603")
      (libsource (lib "eagle-import") (part "LED-BLUE0603"))
    )
    (comp (ref "D657")
      (value "LED-BLUE0603")
      (footprint "eagle-import:LED-0603")
      (libsource (lib "eagle-import") (part "LED-BLUE0603"))
    )
    (comp (ref "D658")
      (value "LED-BLUE0603")
      (footprint "eagle-import:LED-0603")
      (libsource (lib "eagle-import") (part "LED-BLUE0603"))
    )
    (comp (ref "D659")
      (value "LED-BLUE0603")
      (footprint "eagle-import:LED-0603")
      (libsource (lib "eagle-import") (part "LED-BLUE0603"))
    )
    (comp (ref "D660")
      (value "LED-BLUE0603")
      (footprint "eagle-import:LED-0603")
      (libsource (lib "eagle-import") (part "LED-BLUE0603"))
    )
    (comp (ref "D661")
      (value "LED-BLUE0603")
      (footprint "eagle-import:LED-0603")
      (libsource (lib "eagle-import") (part "LED-BLUE0603"))
    )
    (comp (ref "D662")
      (value "LED-BLUE0603")
      (footprint "eagle-import:LED-0603")
      (libsource (lib "eagle-import") (part "LED-BLUE0603"))
    )
    (comp (ref "D663")
      (value "LED-BLUE0603")
      (footprint "eagle-import:LED-0603")
      (libsource (lib "eagle-import") (part "LED-BLUE0603"))
    )
    (comp (ref "D664")
      (value "LED-BLUE0603")
      (footprint "eagle-import:LED-0603")
      (libsource (lib "eagle-import") (part "LED-BLUE0603"))
    )
    (comp (ref "D665")
      (value "LED-BLUE0603")
      (footprint "eagle-import:LED-0603")
      (libsource (lib "eagle-import") (part "LED-BLUE0603"))
    )
    (comp (ref "D666")
      (value "LED-BLUE0603")
      (footprint "eagle-import:LED-0603")
      (libsource (lib "eagle-import") (part "LED-BLUE0603"))
    )
    (comp (ref "D667")
      (value "LED-BLUE0603")
      (footprint "eagle-import:LED-0603")
      (libsource (lib "eagle-import") (part "LED-BLUE0603"))
    )
    (comp (ref "D668")
      (value "LED-BLUE0603")
      (footprint "eagle-import:LED-0603")
      (libsource (lib "eagle-import") (part "LED-BLUE0603"))
    )
    (comp (ref "D669")
      (value "LED-BLUE0603")
      (footprint "eagle-import:LED-0603")
      (libsource (lib "eagle-import") (part "LED-BLUE0603"))
    )
    (comp (ref "D670")
      (value "LED-BLUE0603")
      (footprint "eagle-import:LED-0603")
      (libsource (lib "eagle-import") (part "LED-BLUE0603"))
    )
    (comp (ref "D671")
      (value "LED-BLUE0603")
      (footprint "eagle-import:LED-0603")
      (libsource (lib "eagle-import") (part "LED-BLUE0603"))
    )
    (comp (ref "D672")
      (value "LED-BLUE0603")
      (footprint "eagle-import:LED-0603")
      (libsource (lib "eagle-import") (part "LED-BLUE0603"))
    )
    (comp (ref "D673")
      (value "LED-BLUE0603")
      (footprint "eagle-import:LED-0603")
      (libsource (lib "eagle-import") (part "LED-BLUE0603"))
    )
    (comp (ref "D674")
      (value "LED-BLUE0603")
      (footprint "eagle-import:LED-0603")
      (libsource (lib "eagle-import") (part "LED-BLUE0603"))
    )
    (comp (ref "D675")
      (value "LED-BLUE0603")
      (footprint "eagle-import:LED-0603")
      (libsource (lib "eagle-import") (part "LED-BLUE0603"))
    )
    (comp (ref "D676")
      (value "LED-BLUE0603")
      (footprint "eagle-import:LED-0603")
      (libsource (lib "eagle-import") (part "LED-BLUE0603"))
    )
    (comp (ref "D677")
      (value "LED-BLUE0603")
      (footprint "eagle-import:LED-0603")
      (libsource (lib "eagle-import") (part "LED-BLUE0603"))
    )
    (comp (ref "D678")
      (value "LED-BLUE0603")
      (footprint "eagle-import:LED-0603")
      (libsource (lib "eagle-import") (part "LED-BLUE0603"))
    )
    (comp (ref "D679")
      (value "LED-BLUE0603")
      (footprint "eagle-import:LED-0603")
      (libsource (lib "eagle-import") (part "LED-BLUE0603"))
    )
    (comp (ref "D680")
      (value "LED-BLUE0603")
      (footprint "eagle-import:LED-0603")
      (libsource (lib "eagle-import") (part "LED-BLUE0603"))
    )
    (comp (ref "D681")
      (value "LED-BLUE0603")
      (footprint "eagle-import:LED-0603")
      (libsource (lib "eagle-import") (part "LED-BLUE0603"))
    )
    (comp (ref "D682")
      (value "LED-BLUE0603")
      (footprint "eagle-import:LED-0603")
      (libsource (lib "eagle-import") (part "LED-BLUE0603"))
    )
    (comp (ref "D683")
      (value "LED-BLUE0603")
      (footprint "eagle-import:LED-0603")
      (libsource (lib "eagle-import") (part "LED-BLUE0603"))
    )
    (comp (ref "D684")
      (value "LED-BLUE0603")
      (footprint "eagle-import:LED-0603")
      (libsource (lib "eagle-import") (part "LED-BLUE0603"))
    )
    (comp (ref "D685")
      (value "LED-BLUE0603")
      (footprint "eagle-import:LED-0603")
      (libsource (lib "eagle-import") (part "LED-BLUE0603"))
    )
    (comp (ref "D686")
      (value "LED-BLUE0603")
      (footprint "eagle-import:LED-0603")
      (libsource (lib "eagle-import") (part "LED-BLUE0603"))
    )
    (comp (ref "D687")
      (value "LED-BLUE0603")
      (footprint "eagle-import:LED-0603")
      (libsource (lib "eagle-import") (part "LED-BLUE0603"))
    )
    (comp (ref "D688")
      (value "LED-BLUE0603")
      (footprint "eagle-import:LED-0603")
      (libsource (lib "eagle-import") (part "LED-BLUE0603"))
    )
    (comp (ref "D689")
      (value "LED-BLUE0603")
      (footprint "eagle-import:LED-0603")
      (libsource (lib "eagle-import") (part "LED-BLUE0603"))
    )
    (comp (ref "D690")
      (value "LED-BLUE0603")
      (footprint "eagle-import:LED-0603")
      (libsource (lib "eagle-import") (part "LED-BLUE0603"))
    )
    (comp (ref "D691")
      (value "LED-BLUE0603")
      (footprint "eagle-import:LED-0603")
      (libsource (lib "eagle-import") (part "LED-BLUE0603"))
    )
    (comp (ref "D692")
      (value "LED-BLUE0603")
      (footprint "eagle-import:LED-0603")
      (libsource (lib "eagle-import") (part "LED-BLUE0603"))
    )
    (comp (ref "D693")
      (value "LED-BLUE0603")
      (footprint "eagle-import:LED-0603")
      (libsource (lib "eagle-import") (part "LED-BLUE0603"))
    )
    (comp (ref "D694")
      (value "LED-BLUE0603")
      (footprint "eagle-import:LED-0603")
      (libsource (lib "eagle-import") (part "LED-BLUE0603"))
    )
    (comp (ref "D695")
      (value "LED-BLUE0603")
      (footprint "eagle-import:LED-0603")
      (libsource (lib "eagle-import") (part "LED-BLUE0603"))
    )
    (comp (ref "D696")
      (value "LED-BLUE0603")
      (footprint "eagle-import:LED-0603")
      (libsource (lib "eagle-import") (part "LED-BLUE0603"))
    )
    (comp (ref "D697")
      (value "LED-BLUE0603")
      (footprint "eagle-import:LED-0603")
      (libsource (lib "eagle-import") (part "LED-BLUE0603"))
    )
    (comp (ref "D698")
      (value "LED-BLUE0603")
      (footprint "eagle-import:LED-0603")
      (libsource (lib "eagle-import") (part "LED-BLUE0603"))
    )
    (comp (ref "D699")
      (value "LED-BLUE0603")
      (footprint "eagle-import:LED-0603")
      (libsource (lib "eagle-import") (part "LED-BLUE0603"))
    )
    (comp (ref "D700")
      (value "LED-BLUE0603")
      (footprint "eagle-import:LED-0603")
      (libsource (lib "eagle-import") (part "LED-BLUE0603"))
    )
    (comp (ref "D701")
      (value "LED-BLUE0603")
      (footprint "eagle-import:LED-0603")
      (libsource (lib "eagle-import") (part "LED-BLUE0603"))
    )
    (comp (ref "D702")
      (value "LED-BLUE0603")
      (footprint "eagle-import:LED-0603")
      (libsource (lib "eagle-import") (part "LED-BLUE0603"))
    )
    (comp (ref "D703")
      (value "LED-BLUE0603")
      (footprint "eagle-import:LED-0603")
      (libsource (lib "eagle-import") (part "LED-BLUE0603"))
    )
    (comp (ref "D704")
      (value "LED-BLUE0603")
      (footprint "eagle-import:LED-0603")
      (libsource (lib "eagle-import") (part "LED-BLUE0603"))
    )
    (comp (ref "D705")
      (value "LED-BLUE0603")
      (footprint "eagle-import:LED-0603")
      (libsource (lib "eagle-import") (part "LED-BLUE0603"))
    )
    (comp (ref "D706")
      (value "LED-BLUE0603")
      (footprint "eagle-import:LED-0603")
      (libsource (lib "eagle-import") (part "LED-BLUE0603"))
    )
    (comp (ref "D707")
      (value "LED-BLUE0603")
      (footprint "eagle-import:LED-0603")
      (libsource (lib "eagle-import") (part "LED-BLUE0603"))
    )
    (comp (ref "D708")
      (value "LED-BLUE0603")
      (footprint "eagle-import:LED-0603")
      (libsource (lib "eagle-import") (part "LED-BLUE0603"))
    )
    (comp (ref "D709")
      (value "LED-BLUE0603")
      (footprint "eagle-import:LED-0603")
      (libsource (lib "eagle-import") (part "LED-BLUE0603"))
    )
    (comp (ref "D710")
      (value "LED-BLUE0603")
      (footprint "eagle-import:LED-0603")
      (libsource (lib "eagle-import") (part "LED-BLUE0603"))
    )
    (comp (ref "D711")
      (value "LED-BLUE0603")
      (footprint "eagle-import:LED-0603")
      (libsource (lib "eagle-import") (part "LED-BLUE0603"))
    )
    (comp (ref "D712")
      (value "LED-BLUE0603")
      (footprint "eagle-import:LED-0603")
      (libsource (lib "eagle-import") (part "LED-BLUE0603"))
    )
    (comp (ref "D713")
      (value "LED-BLUE0603")
      (footprint "eagle-import:LED-0603")
      (libsource (lib "eagle-import") (part "LED-BLUE0603"))
    )
    (comp (ref "D714")
      (value "LED-BLUE0603")
      (footprint "eagle-import:LED-0603")
      (libsource (lib "eagle-import") (part "LED-BLUE0603"))
    )
    (comp (ref "D715")
      (value "LED-BLUE0603")
      (footprint "eagle-import:LED-0603")
      (libsource (lib "eagle-import") (part "LED-BLUE0603"))
    )
    (comp (ref "D716")
      (value "LED-BLUE0603")
      (footprint "eagle-import:LED-0603")
      (libsource (lib "eagle-import") (part "LED-BLUE0603"))
    )
    (comp (ref "D717")
      (value "LED-BLUE0603")
      (footprint "eagle-import:LED-0603")
      (libsource (lib "eagle-import") (part "LED-BLUE0603"))
    )
    (comp (ref "D718")
      (value "LED-BLUE0603")
      (footprint "eagle-import:LED-0603")
      (libsource (lib "eagle-import") (part "LED-BLUE0603"))
    )
    (comp (ref "D719")
      (value "LED-BLUE0603")
      (footprint "eagle-import:LED-0603")
      (libsource (lib "eagle-import") (part "LED-BLUE0603"))
    )
    (comp (ref "D720")
      (value "LED-BLUE0603")
      (footprint "eagle-import:LED-0603")
      (libsource (lib "eagle-import") (part "LED-BLUE0603"))
    )
    (comp (ref "D721")
      (value "LED-BLUE0603")
      (footprint "eagle-import:LED-0603")
      (libsource (lib "eagle-import") (part "LED-BLUE0603"))
    )
    (comp (ref "D722")
      (value "LED-BLUE0603")
      (footprint "eagle-import:LED-0603")
      (libsource (lib "eagle-import") (part "LED-BLUE0603"))
    )
    (comp (ref "D723")
      (value "LED-BLUE0603")
      (footprint "eagle-import:LED-0603")
      (libsource (lib "eagle-import") (part "LED-BLUE0603"))
    )
    (comp (ref "D724")
      (value "LED-BLUE0603")
      (footprint "eagle-import:LED-0603")
      (libsource (lib "eagle-import") (part "LED-BLUE0603"))
    )
    (comp (ref "D725")
      (value "LED-BLUE0603")
      (footprint "eagle-import:LED-0603")
      (libsource (lib "eagle-import") (part "LED-BLUE0603"))
    )
    (comp (ref "D726")
      (value "LED-BLUE0603")
      (footprint "eagle-import:LED-0603")
      (libsource (lib "eagle-import") (part "LED-BLUE0603"))
    )
    (comp (ref "D727")
      (value "LED-BLUE0603")
      (footprint "eagle-import:LED-0603")
      (libsource (lib "eagle-import") (part "LED-BLUE0603"))
    )
    (comp (ref "D728")
      (value "LED-BLUE0603")
      (footprint "eagle-import:LED-0603")
      (libsource (lib "eagle-import") (part "LED-BLUE0603"))
    )
    (comp (ref "D729")
      (value "LED-BLUE0603")
      (footprint "eagle-import:LED-0603")
      (libsource (lib "eagle-import") (part "LED-BLUE0603"))
    )
    (comp (ref "D730")
      (value "LED-BLUE0603")
      (footprint "eagle-import:LED-0603")
      (libsource (lib "eagle-import") (part "LED-BLUE0603"))
    )
    (comp (ref "D731")
      (value "LED-BLUE0603")
      (footprint "eagle-import:LED-0603")
      (libsource (lib "eagle-import") (part "LED-BLUE0603"))
    )
    (comp (ref "D732")
      (value "LED-BLUE0603")
      (footprint "eagle-import:LED-0603")
      (libsource (lib "eagle-import") (part "LED-BLUE0603"))
    )
    (comp (ref "D733")
      (value "LED-BLUE0603")
      (footprint "eagle-import:LED-0603")
      (libsource (lib "eagle-import") (part "LED-BLUE0603"))
    )
    (comp (ref "D734")
      (value "LED-BLUE0603")
      (footprint "eagle-import:LED-0603")
      (libsource (lib "eagle-import") (part "LED-BLUE0603"))
    )
    (comp (ref "D735")
      (value "LED-BLUE0603")
      (footprint "eagle-import:LED-0603")
      (libsource (lib "eagle-import") (part "LED-BLUE0603"))
    )
    (comp (ref "D736")
      (value "LED-BLUE0603")
      (footprint "eagle-import:LED-0603")
      (libsource (lib "eagle-import") (part "LED-BLUE0603"))
    )
    (comp (ref "D737")
      (value "LED-BLUE0603")
      (footprint "eagle-import:LED-0603")
      (libsource (lib "eagle-import") (part "LED-BLUE0603"))
    )
    (comp (ref "D738")
      (value "LED-BLUE0603")
      (footprint "eagle-import:LED-0603")
      (libsource (lib "eagle-import") (part "LED-BLUE0603"))
    )
    (comp (ref "D739")
      (value "LED-BLUE0603")
      (footprint "eagle-import:LED-0603")
      (libsource (lib "eagle-import") (part "LED-BLUE0603"))
    )
    (comp (ref "D740")
      (value "LED-BLUE0603")
      (footprint "eagle-import:LED-0603")
      (libsource (lib "eagle-import") (part "LED-BLUE0603"))
    )
    (comp (ref "D741")
      (value "LED-BLUE0603")
      (footprint "eagle-import:LED-0603")
      (libsource (lib "eagle-import") (part "LED-BLUE0603"))
    )
    (comp (ref "D742")
      (value "LED-BLUE0603")
      (footprint "eagle-import:LED-0603")
      (libsource (lib "eagle-import") (part "LED-BLUE0603"))
    )
    (comp (ref "D743")
      (value "LED-BLUE0603")
      (footprint "eagle-import:LED-0603")
      (libsource (lib "eagle-import") (part "LED-BLUE0603"))
    )
    (comp (ref "D744")
      (value "LED-BLUE0603")
      (footprint "eagle-import:LED-0603")
      (libsource (lib "eagle-import") (part "LED-BLUE0603"))
    )
    (comp (ref "D745")
      (value "LED-BLUE0603")
      (footprint "eagle-import:LED-0603")
      (libsource (lib "eagle-import") (part "LED-BLUE0603"))
    )
    (comp (ref "D746")
      (value "LED-BLUE0603")
      (footprint "eagle-import:LED-0603")
      (libsource (lib "eagle-import") (part "LED-BLUE0603"))
    )
    (comp (ref "D747")
      (value "LED-BLUE0603")
      (footprint "eagle-import:LED-0603")
      (libsource (lib "eagle-import") (part "LED-BLUE0603"))
    )
    (comp (ref "D748")
      (value "LED-BLUE0603")
      (footprint "eagle-import:LED-0603")
      (libsource (lib "eagle-import") (part "LED-BLUE0603"))
    )
    (comp (ref "D749")
      (value "LED-BLUE0603")
      (footprint "eagle-import:LED-0603")
      (libsource (lib "eagle-import") (part "LED-BLUE0603"))
    )
    (comp (ref "D750")
      (value "LED-BLUE0603")
      (footprint "eagle-import:LED-0603")
      (libsource (lib "eagle-import") (part "LED-BLUE0603"))
    )
    (comp (ref "D751")
      (value "LED-BLUE0603")
      (footprint "eagle-import:LED-0603")
      (libsource (lib "eagle-import") (part "LED-BLUE0603"))
    )
    (comp (ref "D752")
      (value "LED-BLUE0603")
      (footprint "eagle-import:LED-0603")
      (libsource (lib "eagle-import") (part "LED-BLUE0603"))
    )
    (comp (ref "D753")
      (value "LED-BLUE0603")
      (footprint "eagle-import:LED-0603")
      (libsource (lib "eagle-import") (part "LED-BLUE0603"))
    )
    (comp (ref "D754")
      (value "LED-BLUE0603")
      (footprint "eagle-import:LED-0603")
      (libsource (lib "eagle-import") (part "LED-BLUE0603"))
    )
    (comp (ref "D755")
      (value "LED-BLUE0603")
      (footprint "eagle-import:LED-0603")
      (libsource (lib "eagle-import") (part "LED-BLUE0603"))
    )
    (comp (ref "D756")
      (value "LED-BLUE0603")
      (footprint "eagle-import:LED-0603")
      (libsource (lib "eagle-import") (part "LED-BLUE0603"))
    )
    (comp (ref "D757")
      (value "LED-BLUE0603")
      (footprint "eagle-import:LED-0603")
      (libsource (lib "eagle-import") (part "LED-BLUE0603"))
    )
    (comp (ref "D758")
      (value "LED-BLUE0603")
      (footprint "eagle-import:LED-0603")
      (libsource (lib "eagle-import") (part "LED-BLUE0603"))
    )
    (comp (ref "D759")
      (value "LED-BLUE0603")
      (footprint "eagle-import:LED-0603")
      (libsource (lib "eagle-import") (part "LED-BLUE0603"))
    )
    (comp (ref "D760")
      (value "LED-BLUE0603")
      (footprint "eagle-import:LED-0603")
      (libsource (lib "eagle-import") (part "LED-BLUE0603"))
    )
    (comp (ref "D761")
      (value "LED-BLUE0603")
      (footprint "eagle-import:LED-0603")
      (libsource (lib "eagle-import") (part "LED-BLUE0603"))
    )
    (comp (ref "D762")
      (value "LED-BLUE0603")
      (footprint "eagle-import:LED-0603")
      (libsource (lib "eagle-import") (part "LED-BLUE0603"))
    )
    (comp (ref "D763")
      (value "LED-BLUE0603")
      (footprint "eagle-import:LED-0603")
      (libsource (lib "eagle-import") (part "LED-BLUE0603"))
    )
    (comp (ref "D764")
      (value "LED-BLUE0603")
      (footprint "eagle-import:LED-0603")
      (libsource (lib "eagle-import") (part "LED-BLUE0603"))
    )
    (comp (ref "D765")
      (value "LED-BLUE0603")
      (footprint "eagle-import:LED-0603")
      (libsource (lib "eagle-import") (part "LED-BLUE0603"))
    )
    (comp (ref "D766")
      (value "LED-BLUE0603")
      (footprint "eagle-import:LED-0603")
      (libsource (lib "eagle-import") (part "LED-BLUE0603"))
    )
    (comp (ref "D767")
      (value "LED-BLUE0603")
      (footprint "eagle-import:LED-0603")
      (libsource (lib "eagle-import") (part "LED-BLUE0603"))
    )
    (comp (ref "D768")
      (value "LED-BLUE0603")
      (footprint "eagle-import:LED-0603")
      (libsource (lib "eagle-import") (part "LED-BLUE0603"))
    )
    (comp (ref "D769")
      (value "LED-BLUE0603")
      (footprint "eagle-import:LED-0603")
      (libsource (lib "eagle-import") (part "LED-BLUE0603"))
    )
    (comp (ref "D770")
      (value "LED-BLUE0603")
      (footprint "eagle-import:LED-0603")
      (libsource (lib "eagle-import") (part "LED-BLUE0603"))
    )
    (comp (ref "D771")
      (value "LED-BLUE0603")
      (footprint "eagle-import:LED-0603")
      (libsource (lib "eagle-import") (part "LED-BLUE0603"))
    )
    (comp (ref "D772")
      (value "LED-BLUE0603")
      (footprint "eagle-import:LED-0603")
      (libsource (lib "eagle-import") (part "LED-BLUE0603"))
    )
    (comp (ref "D773")
      (value "LED-BLUE0603")
      (footprint "eagle-import:LED-0603")
      (libsource (lib "eagle-import") (part "LED-BLUE0603"))
    )
    (comp (ref "D774")
      (value "LED-BLUE0603")
      (footprint "eagle-import:LED-0603")
      (libsource (lib "eagle-import") (part "LED-BLUE0603"))
    )
    (comp (ref "D775")
      (value "LED-BLUE0603")
      (footprint "eagle-import:LED-0603")
      (libsource (lib "eagle-import") (part "LED-BLUE0603"))
    )
    (comp (ref "D776")
      (value "LED-BLUE0603")
      (footprint "eagle-import:LED-0603")
      (libsource (lib "eagle-import") (part "LED-BLUE0603"))
    )
    (comp (ref "D777")
      (value "LED-BLUE0603")
      (footprint "eagle-import:LED-0603")
      (libsource (lib "eagle-import") (part "LED-BLUE0603"))
    )
    (comp (ref "D778")
      (value "LED-BLUE0603")
      (footprint "eagle-import:LED-0603")
      (libsource (lib "eagle-import") (part "LED-BLUE0603"))
    )
    (comp (ref "D779")
      (value "LED-BLUE0603")
      (footprint "eagle-import:LED-0603")
      (libsource (lib "eagle-import") (part "LED-BLUE0603"))
    )
    (comp (ref "D780")
      (value "LED-BLUE0603")
      (footprint "eagle-import:LED-0603")
      (libsource (lib "eagle-import") (part "LED-BLUE0603"))
    )
    (comp (ref "D781")
      (value "LED-BLUE0603")
      (footprint "eagle-import:LED-0603")
      (libsource (lib "eagle-import") (part "LED-BLUE0603"))
    )
    (comp (ref "D782")
      (value "LED-BLUE0603")
      (footprint "eagle-import:LED-0603")
      (libsource (lib "eagle-import") (part "LED-BLUE0603"))
    )
    (comp (ref "D783")
      (value "LED-BLUE0603")
      (footprint "eagle-import:LED-0603")
      (libsource (lib "eagle-import") (part "LED-BLUE0603"))
    )
    (comp (ref "D784")
      (value "LED-BLUE0603")
      (footprint "eagle-import:LED-0603")
      (libsource (lib "eagle-import") (part "LED-BLUE0603"))
    )
    (comp (ref "D785")
      (value "LED-BLUE0603")
      (footprint "eagle-import:LED-0603")
      (libsource (lib "eagle-import") (part "LED-BLUE0603"))
    )
    (comp (ref "D786")
      (value "LED-BLUE0603")
      (footprint "eagle-import:LED-0603")
      (libsource (lib "eagle-import") (part "LED-BLUE0603"))
    )
    (comp (ref "D787")
      (value "LED-BLUE0603")
      (footprint "eagle-import:LED-0603")
      (libsource (lib "eagle-import") (part "LED-BLUE0603"))
    )
    (comp (ref "D788")
      (value "LED-BLUE0603")
      (footprint "eagle-import:LED-0603")
      (libsource (lib "eagle-import") (part "LED-BLUE0603"))
    )
    (comp (ref "D789")
      (value "LED-BLUE0603")
      (footprint "eagle-import:LED-0603")
      (libsource (lib "eagle-import") (part "LED-BLUE0603"))
    )
    (comp (ref "D790")
      (value "LED-BLUE0603")
      (footprint "eagle-import:LED-0603")
      (libsource (lib "eagle-import") (part "LED-BLUE0603"))
    )
    (comp (ref "D791")
      (value "LED-BLUE0603")
      (footprint "eagle-import:LED-0603")
      (libsource (lib "eagle-import") (part "LED-BLUE0603"))
    )
    (comp (ref "D792")
      (value "LED-BLUE0603")
      (footprint "eagle-import:LED-0603")
      (libsource (lib "eagle-import") (part "LED-BLUE0603"))
    )
    (comp (ref "D793")
      (value "LED-BLUE0603")
      (footprint "eagle-import:LED-0603")
      (libsource (lib "eagle-import") (part "LED-BLUE0603"))
    )
    (comp (ref "D794")
      (value "LED-BLUE0603")
      (footprint "eagle-import:LED-0603")
      (libsource (lib "eagle-import") (part "LED-BLUE0603"))
    )
    (comp (ref "D795")
      (value "LED-BLUE0603")
      (footprint "eagle-import:LED-0603")
      (libsource (lib "eagle-import") (part "LED-BLUE0603"))
    )
    (comp (ref "D796")
      (value "LED-BLUE0603")
      (footprint "eagle-import:LED-0603")
      (libsource (lib "eagle-import") (part "LED-BLUE0603"))
    )
    (comp (ref "D797")
      (value "LED-BLUE0603")
      (footprint "eagle-import:LED-0603")
      (libsource (lib "eagle-import") (part "LED-BLUE0603"))
    )
    (comp (ref "D798")
      (value "LED-BLUE0603")
      (footprint "eagle-import:LED-0603")
      (libsource (lib "eagle-import") (part "LED-BLUE0603"))
    )
    (comp (ref "D799")
      (value "LED-BLUE0603")
      (footprint "eagle-import:LED-0603")
      (libsource (lib "eagle-import") (part "LED-BLUE0603"))
    )
    (comp (ref "D800")
      (value "LED-BLUE0603")
      (footprint "eagle-import:LED-0603")
      (libsource (lib "eagle-import") (part "LED-BLUE0603"))
    )
    (comp (ref "D801")
      (value "LED-BLUE0603")
      (footprint "eagle-import:LED-0603")
      (libsource (lib "eagle-import") (part "LED-BLUE0603"))
    )
    (comp (ref "D802")
      (value "LED-BLUE0603")
      (footprint "eagle-import:LED-0603")
      (libsource (lib "eagle-import") (part "LED-BLUE0603"))
    )
    (comp (ref "D803")
      (value "LED-BLUE0603")
      (footprint "eagle-import:LED-0603")
      (libsource (lib "eagle-import") (part "LED-BLUE0603"))
    )
    (comp (ref "D804")
      (value "LED-BLUE0603")
      (footprint "eagle-import:LED-0603")
      (libsource (lib "eagle-import") (part "LED-BLUE0603"))
    )
    (comp (ref "D805")
      (value "LED-BLUE0603")
      (footprint "eagle-import:LED-0603")
      (libsource (lib "eagle-import") (part "LED-BLUE0603"))
    )
    (comp (ref "D806")
      (value "LED-BLUE0603")
      (footprint "eagle-import:LED-0603")
      (libsource (lib "eagle-import") (part "LED-BLUE0603"))
    )
    (comp (ref "D807")
      (value "LED-BLUE0603")
      (footprint "eagle-import:LED-0603")
      (libsource (lib "eagle-import") (part "LED-BLUE0603"))
    )
    (comp (ref "D808")
      (value "LED-BLUE0603")
      (footprint "eagle-import:LED-0603")
      (libsource (lib "eagle-import") (part "LED-BLUE0603"))
    )
    (comp (ref "D809")
      (value "LED-BLUE0603")
      (footprint "eagle-import:LED-0603")
      (libsource (lib "eagle-import") (part "LED-BLUE0603"))
    )
    (comp (ref "D810")
      (value "LED-BLUE0603")
      (footprint "eagle-import:LED-0603")
      (libsource (lib "eagle-import") (part "LED-BLUE0603"))
    )
    (comp (ref "D811")
      (value "LED-BLUE0603")
      (footprint "eagle-import:LED-0603")
      (libsource (lib "eagle-import") (part "LED-BLUE0603"))
    )
    (comp (ref "D812")
      (value "LED-BLUE0603")
      (footprint "eagle-import:LED-0603")
      (libsource (lib "eagle-import") (part "LED-BLUE0603"))
    )
    (comp (ref "D813")
      (value "LED-BLUE0603")
      (footprint "eagle-import:LED-0603")
      (libsource (lib "eagle-import") (part "LED-BLUE0603"))
    )
    (comp (ref "D814")
      (value "LED-BLUE0603")
      (footprint "eagle-import:LED-0603")
      (libsource (lib "eagle-import") (part "LED-BLUE0603"))
    )
    (comp (ref "D815")
      (value "LED-BLUE0603")
      (footprint "eagle-import:LED-0603")
      (libsource (lib "eagle-import") (part "LED-BLUE0603"))
    )
    (comp (ref "D816")
      (value "LED-BLUE0603")
      (footprint "eagle-import:LED-0603")
      (libsource (lib "eagle-import") (part "LED-BLUE0603"))
    )
    (comp (ref "D817")
      (value "LED-BLUE0603")
      (footprint "eagle-import:LED-0603")
      (libsource (lib "eagle-import") (part "LED-BLUE0603"))
    )
    (comp (ref "D818")
      (value "LED-BLUE0603")
      (footprint "eagle-import:LED-0603")
      (libsource (lib "eagle-import") (part "LED-BLUE0603"))
    )
    (comp (ref "D819")
      (value "LED-BLUE0603")
      (footprint "eagle-import:LED-0603")
      (libsource (lib "eagle-import") (part "LED-BLUE0603"))
    )
    (comp (ref "D820")
      (value "LED-BLUE0603")
      (footprint "eagle-import:LED-0603")
      (libsource (lib "eagle-import") (part "LED-BLUE0603"))
    )
    (comp (ref "D821")
      (value "LED-BLUE0603")
      (footprint "eagle-import:LED-0603")
      (libsource (lib "eagle-import") (part "LED-BLUE0603"))
    )
    (comp (ref "D822")
      (value "LED-BLUE0603")
      (footprint "eagle-import:LED-0603")
      (libsource (lib "eagle-import") (part "LED-BLUE0603"))
    )
    (comp (ref "D823")
      (value "LED-BLUE0603")
      (footprint "eagle-import:LED-0603")
      (libsource (lib "eagle-import") (part "LED-BLUE0603"))
    )
    (comp (ref "D824")
      (value "LED-BLUE0603")
      (footprint "eagle-import:LED-0603")
      (libsource (lib "eagle-import") (part "LED-BLUE0603"))
    )
    (comp (ref "D825")
      (value "LED-BLUE0603")
      (footprint "eagle-import:LED-0603")
      (libsource (lib "eagle-import") (part "LED-BLUE0603"))
    )
    (comp (ref "D826")
      (value "LED-BLUE0603")
      (footprint "eagle-import:LED-0603")
      (libsource (lib "eagle-import") (part "LED-BLUE0603"))
    )
    (comp (ref "D827")
      (value "LED-BLUE0603")
      (footprint "eagle-import:LED-0603")
      (libsource (lib "eagle-import") (part "LED-BLUE0603"))
    )
    (comp (ref "D828")
      (value "LED-BLUE0603")
      (footprint "eagle-import:LED-0603")
      (libsource (lib "eagle-import") (part "LED-BLUE0603"))
    )
    (comp (ref "D829")
      (value "LED-BLUE0603")
      (footprint "eagle-import:LED-0603")
      (libsource (lib "eagle-import") (part "LED-BLUE0603"))
    )
    (comp (ref "D830")
      (value "LED-BLUE0603")
      (footprint "eagle-import:LED-0603")
      (libsource (lib "eagle-import") (part "LED-BLUE0603"))
    )
    (comp (ref "D831")
      (value "LED-BLUE0603")
      (footprint "eagle-import:LED-0603")
      (libsource (lib "eagle-import") (part "LED-BLUE0603"))
    )
    (comp (ref "D832")
      (value "LED-BLUE0603")
      (footprint "eagle-import:LED-0603")
      (libsource (lib "eagle-import") (part "LED-BLUE0603"))
    )
    (comp (ref "D833")
      (value "LED-BLUE0603")
      (footprint "eagle-import:LED-0603")
      (libsource (lib "eagle-import") (part "LED-BLUE0603"))
    )
    (comp (ref "D834")
      (value "LED-BLUE0603")
      (footprint "eagle-import:LED-0603")
      (libsource (lib "eagle-import") (part "LED-BLUE0603"))
    )
    (comp (ref "D835")
      (value "LED-BLUE0603")
      (footprint "eagle-import:LED-0603")
      (libsource (lib "eagle-import") (part "LED-BLUE0603"))
    )
    (comp (ref "D836")
      (value "LED-BLUE0603")
      (footprint "eagle-import:LED-0603")
      (libsource (lib "eagle-import") (part "LED-BLUE0603"))
    )
    (comp (ref "D837")
      (value "LED-BLUE0603")
      (footprint "eagle-import:LED-0603")
      (libsource (lib "eagle-import") (part "LED-BLUE0603"))
    )
    (comp (ref "D838")
      (value "LED-BLUE0603")
      (footprint "eagle-import:LED-0603")
      (libsource (lib "eagle-import") (part "LED-BLUE0603"))
    )
    (comp (ref "D839")
      (value "LED-BLUE0603")
      (footprint "eagle-import:LED-0603")
      (libsource (lib "eagle-import") (part "LED-BLUE0603"))
    )
    (comp (ref "D840")
      (value "LED-BLUE0603")
      (footprint "eagle-import:LED-0603")
      (libsource (lib "eagle-import") (part "LED-BLUE0603"))
    )
    (comp (ref "D841")
      (value "LED-BLUE0603")
      (footprint "eagle-import:LED-0603")
      (libsource (lib "eagle-import") (part "LED-BLUE0603"))
    )
    (comp (ref "D842")
      (value "LED-BLUE0603")
      (footprint "eagle-import:LED-0603")
      (libsource (lib "eagle-import") (part "LED-BLUE0603"))
    )
    (comp (ref "D843")
      (value "LED-BLUE0603")
      (footprint "eagle-import:LED-0603")
      (libsource (lib "eagle-import") (part "LED-BLUE0603"))
    )
    (comp (ref "D844")
      (value "LED-BLUE0603")
      (footprint "eagle-import:LED-0603")
      (libsource (lib "eagle-import") (part "LED-BLUE0603"))
    )
    (comp (ref "D845")
      (value "LED-BLUE0603")
      (footprint "eagle-import:LED-0603")
      (libsource (lib "eagle-import") (part "LED-BLUE0603"))
    )
    (comp (ref "D846")
      (value "LED-BLUE0603")
      (footprint "eagle-import:LED-0603")
      (libsource (lib "eagle-import") (part "LED-BLUE0603"))
    )
    (comp (ref "D847")
      (value "LED-BLUE0603")
      (footprint "eagle-import:LED-0603")
      (libsource (lib "eagle-import") (part "LED-BLUE0603"))
    )
    (comp (ref "D848")
      (value "LED-BLUE0603")
      (footprint "eagle-import:LED-0603")
      (libsource (lib "eagle-import") (part "LED-BLUE0603"))
    )
    (comp (ref "D849")
      (value "LED-BLUE0603")
      (footprint "eagle-import:LED-0603")
      (libsource (lib "eagle-import") (part "LED-BLUE0603"))
    )
    (comp (ref "D850")
      (value "LED-BLUE0603")
      (footprint "eagle-import:LED-0603")
      (libsource (lib "eagle-import") (part "LED-BLUE0603"))
    )
    (comp (ref "D851")
      (value "LED-BLUE0603")
      (footprint "eagle-import:LED-0603")
      (libsource (lib "eagle-import") (part "LED-BLUE0603"))
    )
    (comp (ref "D852")
      (value "LED-BLUE0603")
      (footprint "eagle-import:LED-0603")
      (libsource (lib "eagle-import") (part "LED-BLUE0603"))
    )
    (comp (ref "D853")
      (value "LED-BLUE0603")
      (footprint "eagle-import:LED-0603")
      (libsource (lib "eagle-import") (part "LED-BLUE0603"))
    )
    (comp (ref "D854")
      (value "LED-BLUE0603")
      (footprint "eagle-import:LED-0603")
      (libsource (lib "eagle-import") (part "LED-BLUE0603"))
    )
    (comp (ref "D855")
      (value "LED-BLUE0603")
      (footprint "eagle-import:LED-0603")
      (libsource (lib "eagle-import") (part "LED-BLUE0603"))
    )
    (comp (ref "D856")
      (value "LED-BLUE0603")
      (footprint "eagle-import:LED-0603")
      (libsource (lib "eagle-import") (part "LED-BLUE0603"))
    )
    (comp (ref "D857")
      (value "LED-BLUE0603")
      (footprint "eagle-import:LED-0603")
      (libsource (lib "eagle-import") (part "LED-BLUE0603"))
    )
    (comp (ref "D858")
      (value "LED-BLUE0603")
      (footprint "eagle-import:LED-0603")
      (libsource (lib "eagle-import") (part "LED-BLUE0603"))
    )
    (comp (ref "D859")
      (value "LED-BLUE0603")
      (footprint "eagle-import:LED-0603")
      (libsource (lib "eagle-import") (part "LED-BLUE0603"))
    )
    (comp (ref "D860")
      (value "LED-BLUE0603")
      (footprint "eagle-import:LED-0603")
      (libsource (lib "eagle-import") (part "LED-BLUE0603"))
    )
    (comp (ref "D861")
      (value "LED-BLUE0603")
      (footprint "eagle-import:LED-0603")
      (libsource (lib "eagle-import") (part "LED-BLUE0603"))
    )
    (comp (ref "D862")
      (value "LED-BLUE0603")
      (footprint "eagle-import:LED-0603")
      (libsource (lib "eagle-import") (part "LED-BLUE0603"))
    )
    (comp (ref "D863")
      (value "LED-BLUE0603")
      (footprint "eagle-import:LED-0603")
      (libsource (lib "eagle-import") (part "LED-BLUE0603"))
    )
    (comp (ref "D864")
      (value "LED-BLUE0603")
      (footprint "eagle-import:LED-0603")
      (libsource (lib "eagle-import") (part "LED-BLUE0603"))
    )
    (comp (ref "D865")
      (value "LED-BLUE0603")
      (footprint "eagle-import:LED-0603")
      (libsource (lib "eagle-import") (part "LED-BLUE0603"))
    )
    (comp (ref "D866")
      (value "LED-BLUE0603")
      (footprint "eagle-import:LED-0603")
      (libsource (lib "eagle-import") (part "LED-BLUE0603"))
    )
    (comp (ref "D867")
      (value "LED-BLUE0603")
      (footprint "eagle-import:LED-0603")
      (libsource (lib "eagle-import") (part "LED-BLUE0603"))
    )
    (comp (ref "D868")
      (value "LED-BLUE0603")
      (footprint "eagle-import:LED-0603")
      (libsource (lib "eagle-import") (part "LED-BLUE0603"))
    )
    (comp (ref "D869")
      (value "LED-BLUE0603")
      (footprint "eagle-import:LED-0603")
      (libsource (lib "eagle-import") (part "LED-BLUE0603"))
    )
    (comp (ref "D870")
      (value "LED-BLUE0603")
      (footprint "eagle-import:LED-0603")
      (libsource (lib "eagle-import") (part "LED-BLUE0603"))
    )
    (comp (ref "D871")
      (value "LED-BLUE0603")
      (footprint "eagle-import:LED-0603")
      (libsource (lib "eagle-import") (part "LED-BLUE0603"))
    )
    (comp (ref "D872")
      (value "LED-BLUE0603")
      (footprint "eagle-import:LED-0603")
      (libsource (lib "eagle-import") (part "LED-BLUE0603"))
    )
    (comp (ref "D873")
      (value "LED-BLUE0603")
      (footprint "eagle-import:LED-0603")
      (libsource (lib "eagle-import") (part "LED-BLUE0603"))
    )
    (comp (ref "D874")
      (value "LED-BLUE0603")
      (footprint "eagle-import:LED-0603")
      (libsource (lib "eagle-import") (part "LED-BLUE0603"))
    )
    (comp (ref "D875")
      (value "LED-BLUE0603")
      (footprint "eagle-import:LED-0603")
      (libsource (lib "eagle-import") (part "LED-BLUE0603"))
    )
    (comp (ref "D876")
      (value "LED-BLUE0603")
      (footprint "eagle-import:LED-0603")
      (libsource (lib "eagle-import") (part "LED-BLUE0603"))
    )
    (comp (ref "D877")
      (value "LED-BLUE0603")
      (footprint "eagle-import:LED-0603")
      (libsource (lib "eagle-import") (part "LED-BLUE0603"))
    )
    (comp (ref "D878")
      (value "LED-BLUE0603")
      (footprint "eagle-import:LED-0603")
      (libsource (lib "eagle-import") (part "LED-BLUE0603"))
    )
    (comp (ref "D879")
      (value "LED-BLUE0603")
      (footprint "eagle-import:LED-0603")
      (libsource (lib "eagle-import") (part "LED-BLUE0603"))
    )
    (comp (ref "D880")
      (value "LED-BLUE0603")
      (footprint "eagle-import:LED-0603")
      (libsource (lib "eagle-import") (part "LED-BLUE0603"))
    )
    (comp (ref "D881")
      (value "LED-BLUE0603")
      (footprint "eagle-import:LED-0603")
      (libsource (lib "eagle-import") (part "LED-BLUE0603"))
    )
    (comp (ref "D882")
      (value "LED-BLUE0603")
      (footprint "eagle-import:LED-0603")
      (libsource (lib "eagle-import") (part "LED-BLUE0603"))
    )
    (comp (ref "D883")
      (value "LED-BLUE0603")
      (footprint "eagle-import:LED-0603")
      (libsource (lib "eagle-import") (part "LED-BLUE0603"))
    )
    (comp (ref "D884")
      (value "LED-BLUE0603")
      (footprint "eagle-import:LED-0603")
      (libsource (lib "eagle-import") (part "LED-BLUE0603"))
    )
    (comp (ref "D885")
      (value "LED-BLUE0603")
      (footprint "eagle-import:LED-0603")
      (libsource (lib "eagle-import") (part "LED-BLUE0603"))
    )
    (comp (ref "D886")
      (value "LED-BLUE0603")
      (footprint "eagle-import:LED-0603")
      (libsource (lib "eagle-import") (part "LED-BLUE0603"))
    )
    (comp (ref "D887")
      (value "LED-BLUE0603")
      (footprint "eagle-import:LED-0603")
      (libsource (lib "eagle-import") (part "LED-BLUE0603"))
    )
    (comp (ref "D888")
      (value "LED-BLUE0603")
      (footprint "eagle-import:LED-0603")
      (libsource (lib "eagle-import") (part "LED-BLUE0603"))
    )
    (comp (ref "D889")
      (value "LED-BLUE0603")
      (footprint "eagle-import:LED-0603")
      (libsource (lib "eagle-import") (part "LED-BLUE0603"))
    )
    (comp (ref "D890")
      (value "LED-BLUE0603")
      (footprint "eagle-import:LED-0603")
      (libsource (lib "eagle-import") (part "LED-BLUE0603"))
    )
    (comp (ref "D891")
      (value "LED-BLUE0603")
      (footprint "eagle-import:LED-0603")
      (libsource (lib "eagle-import") (part "LED-BLUE0603"))
    )
    (comp (ref "D892")
      (value "LED-BLUE0603")
      (footprint "eagle-import:LED-0603")
      (libsource (lib "eagle-import") (part "LED-BLUE0603"))
    )
    (comp (ref "D893")
      (value "LED-BLUE0603")
      (footprint "eagle-import:LED-0603")
      (libsource (lib "eagle-import") (part "LED-BLUE0603"))
    )
    (comp (ref "D894")
      (value "LED-BLUE0603")
      (footprint "eagle-import:LED-0603")
      (libsource (lib "eagle-import") (part "LED-BLUE0603"))
    )
    (comp (ref "D895")
      (value "LED-BLUE0603")
      (footprint "eagle-import:LED-0603")
      (libsource (lib "eagle-import") (part "LED-BLUE0603"))
    )
    (comp (ref "D896")
      (value "LED-BLUE0603")
      (footprint "eagle-import:LED-0603")
      (libsource (lib "eagle-import") (part "LED-BLUE0603"))
    )
    (comp (ref "D897")
      (value "LED-BLUE0603")
      (footprint "eagle-import:LED-0603")
      (libsource (lib "eagle-import") (part "LED-BLUE0603"))
    )
    (comp (ref "D898")
      (value "LED-BLUE0603")
      (footprint "eagle-import:LED-0603")
      (libsource (lib "eagle-import") (part "LED-BLUE0603"))
    )
    (comp (ref "D899")
      (value "LED-BLUE0603")
      (footprint "eagle-import:LED-0603")
      (libsource (lib "eagle-import") (part "LED-BLUE0603"))
    )
    (comp (ref "D900")
      (value "LED-BLUE0603")
      (footprint "eagle-import:LED-0603")
      (libsource (lib "eagle-import") (part "LED-BLUE0603"))
    )
    (comp (ref "D901")
      (value "LED-BLUE0603")
      (footprint "eagle-import:LED-0603")
      (libsource (lib "eagle-import") (part "LED-BLUE0603"))
    )
    (comp (ref "D902")
      (value "LED-BLUE0603")
      (footprint "eagle-import:LED-0603")
      (libsource (lib "eagle-import") (part "LED-BLUE0603"))
    )
    (comp (ref "D903")
      (value "LED-BLUE0603")
      (footprint "eagle-import:LED-0603")
      (libsource (lib "eagle-import") (part "LED-BLUE0603"))
    )
    (comp (ref "D904")
      (value "LED-BLUE0603")
      (footprint "eagle-import:LED-0603")
      (libsource (lib "eagle-import") (part "LED-BLUE0603"))
    )
    (comp (ref "D905")
      (value "LED-BLUE0603")
      (footprint "eagle-import:LED-0603")
      (libsource (lib "eagle-import") (part "LED-BLUE0603"))
    )
    (comp (ref "D906")
      (value "LED-BLUE0603")
      (footprint "eagle-import:LED-0603")
      (libsource (lib "eagle-import") (part "LED-BLUE0603"))
    )
    (comp (ref "D907")
      (value "LED-BLUE0603")
      (footprint "eagle-import:LED-0603")
      (libsource (lib "eagle-import") (part "LED-BLUE0603"))
    )
    (comp (ref "D908")
      (value "LED-BLUE0603")
      (footprint "eagle-import:LED-0603")
      (libsource (lib "eagle-import") (part "LED-BLUE0603"))
    )
    (comp (ref "D909")
      (value "LED-BLUE0603")
      (footprint "eagle-import:LED-0603")
      (libsource (lib "eagle-import") (part "LED-BLUE0603"))
    )
    (comp (ref "D910")
      (value "LED-BLUE0603")
      (footprint "eagle-import:LED-0603")
      (libsource (lib "eagle-import") (part "LED-BLUE0603"))
    )
    (comp (ref "D911")
      (value "LED-BLUE0603")
      (footprint "eagle-import:LED-0603")
      (libsource (lib "eagle-import") (part "LED-BLUE0603"))
    )
    (comp (ref "D912")
      (value "LED-BLUE0603")
      (footprint "eagle-import:LED-0603")
      (libsource (lib "eagle-import") (part "LED-BLUE0603"))
    )
    (comp (ref "D913")
      (value "LED-BLUE0603")
      (footprint "eagle-import:LED-0603")
      (libsource (lib "eagle-import") (part "LED-BLUE0603"))
    )
    (comp (ref "D914")
      (value "LED-BLUE0603")
      (footprint "eagle-import:LED-0603")
      (libsource (lib "eagle-import") (part "LED-BLUE0603"))
    )
    (comp (ref "D915")
      (value "LED-BLUE0603")
      (footprint "eagle-import:LED-0603")
      (libsource (lib "eagle-import") (part "LED-BLUE0603"))
    )
    (comp (ref "D916")
      (value "LED-BLUE0603")
      (footprint "eagle-import:LED-0603")
      (libsource (lib "eagle-import") (part "LED-BLUE0603"))
    )
    (comp (ref "D917")
      (value "LED-BLUE0603")
      (footprint "eagle-import:LED-0603")
      (libsource (lib "eagle-import") (part "LED-BLUE0603"))
    )
    (comp (ref "D918")
      (value "LED-BLUE0603")
      (footprint "eagle-import:LED-0603")
      (libsource (lib "eagle-import") (part "LED-BLUE0603"))
    )
    (comp (ref "D919")
      (value "LED-BLUE0603")
      (footprint "eagle-import:LED-0603")
      (libsource (lib "eagle-import") (part "LED-BLUE0603"))
    )
    (comp (ref "D920")
      (value "LED-BLUE0603")
      (footprint "eagle-import:LED-0603")
      (libsource (lib "eagle-import") (part "LED-BLUE0603"))
    )
    (comp (ref "D921")
      (value "LED-BLUE0603")
      (footprint "eagle-import:LED-0603")
      (libsource (lib "eagle-import") (part "LED-BLUE0603"))
    )
    (comp (ref "D922")
      (value "LED-BLUE0603")
      (footprint "eagle-import:LED-0603")
      (libsource (lib "eagle-import") (part "LED-BLUE0603"))
    )
    (comp (ref "D923")
      (value "LED-BLUE0603")
      (footprint "eagle-import:LED-0603")
      (libsource (lib "eagle-import") (part "LED-BLUE0603"))
    )
    (comp (ref "D924")
      (value "LED-BLUE0603")
      (footprint "eagle-import:LED-0603")
      (libsource (lib "eagle-import") (part "LED-BLUE0603"))
    )
    (comp (ref "D925")
      (value "LED-BLUE0603")
      (footprint "eagle-import:LED-0603")
      (libsource (lib "eagle-import") (part "LED-BLUE0603"))
    )
    (comp (ref "D926")
      (value "LED-BLUE0603")
      (footprint "eagle-import:LED-0603")
      (libsource (lib "eagle-import") (part "LED-BLUE0603"))
    )
    (comp (ref "D927")
      (value "LED-BLUE0603")
      (footprint "eagle-import:LED-0603")
      (libsource (lib "eagle-import") (part "LED-BLUE0603"))
    )
    (comp (ref "D928")
      (value "LED-BLUE0603")
      (footprint "eagle-import:LED-0603")
      (libsource (lib "eagle-import") (part "LED-BLUE0603"))
    )
    (comp (ref "D929")
      (value "LED-BLUE0603")
      (footprint "eagle-import:LED-0603")
      (libsource (lib "eagle-import") (part "LED-BLUE0603"))
    )
    (comp (ref "D930")
      (value "LED-BLUE0603")
      (footprint "eagle-import:LED-0603")
      (libsource (lib "eagle-import") (part "LED-BLUE0603"))
    )
    (comp (ref "D931")
      (value "LED-BLUE0603")
      (footprint "eagle-import:LED-0603")
      (libsource (lib "eagle-import") (part "LED-BLUE0603"))
    )
    (comp (ref "D932")
      (value "LED-BLUE0603")
      (footprint "eagle-import:LED-0603")
      (libsource (lib "eagle-import") (part "LED-BLUE0603"))
    )
    (comp (ref "D933")
      (value "LED-BLUE0603")
      (footprint "eagle-import:LED-0603")
      (libsource (lib "eagle-import") (part "LED-BLUE0603"))
    )
    (comp (ref "D934")
      (value "LED-BLUE0603")
      (footprint "eagle-import:LED-0603")
      (libsource (lib "eagle-import") (part "LED-BLUE0603"))
    )
    (comp (ref "D935")
      (value "LED-BLUE0603")
      (footprint "eagle-import:LED-0603")
      (libsource (lib "eagle-import") (part "LED-BLUE0603"))
    )
    (comp (ref "D936")
      (value "LED-BLUE0603")
      (footprint "eagle-import:LED-0603")
      (libsource (lib "eagle-import") (part "LED-BLUE0603"))
    )
    (comp (ref "D937")
      (value "LED-BLUE0603")
      (footprint "eagle-import:LED-0603")
      (libsource (lib "eagle-import") (part "LED-BLUE0603"))
    )
    (comp (ref "D938")
      (value "LED-BLUE0603")
      (footprint "eagle-import:LED-0603")
      (libsource (lib "eagle-import") (part "LED-BLUE0603"))
    )
    (comp (ref "D939")
      (value "LED-BLUE0603")
      (footprint "eagle-import:LED-0603")
      (libsource (lib "eagle-import") (part "LED-BLUE0603"))
    )
    (comp (ref "D940")
      (value "LED-BLUE0603")
      (footprint "eagle-import:LED-0603")
      (libsource (lib "eagle-import") (part "LED-BLUE0603"))
    )
    (comp (ref "D941")
      (value "LED-BLUE0603")
      (footprint "eagle-import:LED-0603")
      (libsource (lib "eagle-import") (part "LED-BLUE0603"))
    )
    (comp (ref "D942")
      (value "LED-BLUE0603")
      (footprint "eagle-import:LED-0603")
      (libsource (lib "eagle-import") (part "LED-BLUE0603"))
    )
    (comp (ref "D943")
      (value "LED-BLUE0603")
      (footprint "eagle-import:LED-0603")
      (libsource (lib "eagle-import") (part "LED-BLUE0603"))
    )
    (comp (ref "D944")
      (value "LED-BLUE0603")
      (footprint "eagle-import:LED-0603")
      (libsource (lib "eagle-import") (part "LED-BLUE0603"))
    )
    (comp (ref "D945")
      (value "LED-BLUE0603")
      (footprint "eagle-import:LED-0603")
      (libsource (lib "eagle-import") (part "LED-BLUE0603"))
    )
    (comp (ref "D946")
      (value "LED-BLUE0603")
      (footprint "eagle-import:LED-0603")
      (libsource (lib "eagle-import") (part "LED-BLUE0603"))
    )
    (comp (ref "D947")
      (value "LED-BLUE0603")
      (footprint "eagle-import:LED-0603")
      (libsource (lib "eagle-import") (part "LED-BLUE0603"))
    )
    (comp (ref "D948")
      (value "LED-BLUE0603")
      (footprint "eagle-import:LED-0603")
      (libsource (lib "eagle-import") (part "LED-BLUE0603"))
    )
    (comp (ref "D949")
      (value "LED-BLUE0603")
      (footprint "eagle-import:LED-0603")
      (libsource (lib "eagle-import") (part "LED-BLUE0603"))
    )
    (comp (ref "D950")
      (value "LED-BLUE0603")
      (footprint "eagle-import:LED-0603")
      (libsource (lib "eagle-import") (part "LED-BLUE0603"))
    )
    (comp (ref "D951")
      (value "LED-BLUE0603")
      (footprint "eagle-import:LED-0603")
      (libsource (lib "eagle-import") (part "LED-BLUE0603"))
    )
    (comp (ref "D952")
      (value "LED-BLUE0603")
      (footprint "eagle-import:LED-0603")
      (libsource (lib "eagle-import") (part "LED-BLUE0603"))
    )
    (comp (ref "D953")
      (value "LED-BLUE0603")
      (footprint "eagle-import:LED-0603")
      (libsource (lib "eagle-import") (part "LED-BLUE0603"))
    )
    (comp (ref "D954")
      (value "LED-BLUE0603")
      (footprint "eagle-import:LED-0603")
      (libsource (lib "eagle-import") (part "LED-BLUE0603"))
    )
    (comp (ref "D955")
      (value "LED-BLUE0603")
      (footprint "eagle-import:LED-0603")
      (libsource (lib "eagle-import") (part "LED-BLUE0603"))
    )
    (comp (ref "D956")
      (value "LED-BLUE0603")
      (footprint "eagle-import:LED-0603")
      (libsource (lib "eagle-import") (part "LED-BLUE0603"))
    )
    (comp (ref "D957")
      (value "LED-BLUE0603")
      (footprint "eagle-import:LED-0603")
      (libsource (lib "eagle-import") (part "LED-BLUE0603"))
    )
    (comp (ref "D958")
      (value "LED-BLUE0603")
      (footprint "eagle-import:LED-0603")
      (libsource (lib "eagle-import") (part "LED-BLUE0603"))
    )
    (comp (ref "D959")
      (value "LED-BLUE0603")
      (footprint "eagle-import:LED-0603")
      (libsource (lib "eagle-import") (part "LED-BLUE0603"))
    )
    (comp (ref "D960")
      (value "LED-BLUE0603")
      (footprint "eagle-import:LED-0603")
      (libsource (lib "eagle-import") (part "LED-BLUE0603"))
    )
    (comp (ref "D961")
      (value "LED-BLUE0603")
      (footprint "eagle-import:LED-0603")
      (libsource (lib "eagle-import") (part "LED-BLUE0603"))
    )
    (comp (ref "D962")
      (value "LED-BLUE0603")
      (footprint "eagle-import:LED-0603")
      (libsource (lib "eagle-import") (part "LED-BLUE0603"))
    )
    (comp (ref "D963")
      (value "LED-BLUE0603")
      (footprint "eagle-import:LED-0603")
      (libsource (lib "eagle-import") (part "LED-BLUE0603"))
    )
    (comp (ref "D964")
      (value "LED-BLUE0603")
      (footprint "eagle-import:LED-0603")
      (libsource (lib "eagle-import") (part "LED-BLUE0603"))
    )
    (comp (ref "D965")
      (value "LED-BLUE0603")
      (footprint "eagle-import:LED-0603")
      (libsource (lib "eagle-import") (part "LED-BLUE0603"))
    )
    (comp (ref "D966")
      (value "LED-BLUE0603")
      (footprint "eagle-import:LED-0603")
      (libsource (lib "eagle-import") (part "LED-BLUE0603"))
    )
    (comp (ref "D967")
      (value "LED-BLUE0603")
      (footprint "eagle-import:LED-0603")
      (libsource (lib "eagle-import") (part "LED-BLUE0603"))
    )
    (comp (ref "D968")
      (value "LED-BLUE0603")
      (footprint "eagle-import:LED-0603")
      (libsource (lib "eagle-import") (part "LED-BLUE0603"))
    )
    (comp (ref "D969")
      (value "LED-BLUE0603")
      (footprint "eagle-import:LED-0603")
      (libsource (lib "eagle-import") (part "LED-BLUE0603"))
    )
    (comp (ref "D970")
      (value "LED-BLUE0603")
      (footprint "eagle-import:LED-0603")
      (libsource (lib "eagle-import") (part "LED-BLUE0603"))
    )
    (comp (ref "D971")
      (value "LED-BLUE0603")
      (footprint "eagle-import:LED-0603")
      (libsource (lib "eagle-import") (part "LED-BLUE0603"))
    )
    (comp (ref "D972")
      (value "LED-BLUE0603")
      (footprint "eagle-import:LED-0603")
      (libsource (lib "eagle-import") (part "LED-BLUE0603"))
    )
    (comp (ref "D973")
      (value "LED-BLUE0603")
      (footprint "eagle-import:LED-0603")
      (libsource (lib "eagle-import") (part "LED-BLUE0603"))
    )
    (comp (ref "D974")
      (value "LED-BLUE0603")
      (footprint "eagle-import:LED-0603")
      (libsource (lib "eagle-import") (part "LED-BLUE0603"))
    )
    (comp (ref "D975")
      (value "LED-BLUE0603")
      (footprint "eagle-import:LED-0603")
      (libsource (lib "eagle-import") (part "LED-BLUE0603"))
    )
    (comp (ref "D976")
      (value "LED-BLUE0603")
      (footprint "eagle-import:LED-0603")
      (libsource (lib "eagle-import") (part "LED-BLUE0603"))
    )
    (comp (ref "D977")
      (value "LED-BLUE0603")
      (footprint "eagle-import:LED-0603")
      (libsource (lib "eagle-import") (part "LED-BLUE0603"))
    )
    (comp (ref "D978")
      (value "LED-BLUE0603")
      (footprint "eagle-import:LED-0603")
      (libsource (lib "eagle-import") (part "LED-BLUE0603"))
    )
    (comp (ref "D979")
      (value "LED-BLUE0603")
      (footprint "eagle-import:LED-0603")
      (libsource (lib "eagle-import") (part "LED-BLUE0603"))
    )
    (comp (ref "D980")
      (value "LED-BLUE0603")
      (footprint "eagle-import:LED-0603")
      (libsource (lib "eagle-import") (part "LED-BLUE0603"))
    )
    (comp (ref "D981")
      (value "LED-BLUE0603")
      (footprint "eagle-import:LED-0603")
      (libsource (lib "eagle-import") (part "LED-BLUE0603"))
    )
    (comp (ref "D982")
      (value "LED-BLUE0603")
      (footprint "eagle-import:LED-0603")
      (libsource (lib "eagle-import") (part "LED-BLUE0603"))
    )
    (comp (ref "D983")
      (value "LED-BLUE0603")
      (footprint "eagle-import:LED-0603")
      (libsource (lib "eagle-import") (part "LED-BLUE0603"))
    )
    (comp (ref "D984")
      (value "LED-BLUE0603")
      (footprint "eagle-import:LED-0603")
      (libsource (lib "eagle-import") (part "LED-BLUE0603"))
    )
    (comp (ref "D985")
      (value "LED-BLUE0603")
      (footprint "eagle-import:LED-0603")
      (libsource (lib "eagle-import") (part "LED-BLUE0603"))
    )
    (comp (ref "D986")
      (value "LED-BLUE0603")
      (footprint "eagle-import:LED-0603")
      (libsource (lib "eagle-import") (part "LED-BLUE0603"))
    )
    (comp (ref "D987")
      (value "LED-BLUE0603")
      (footprint "eagle-import:LED-0603")
      (libsource (lib "eagle-import") (part "LED-BLUE0603"))
    )
    (comp (ref "D988")
      (value "LED-BLUE0603")
      (footprint "eagle-import:LED-0603")
      (libsource (lib "eagle-import") (part "LED-BLUE0603"))
    )
    (comp (ref "D989")
      (value "LED-BLUE0603")
      (footprint "eagle-import:LED-0603")
      (libsource (lib "eagle-import") (part "LED-BLUE0603"))
    )
    (comp (ref "D990")
      (value "LED-BLUE0603")
      (footprint "eagle-import:LED-0603")
      (libsource (lib "eagle-import") (part "LED-BLUE0603"))
    )
    (comp (ref "D991")
      (value "LED-BLUE0603")
      (footprint "eagle-import:LED-0603")
      (libsource (lib "eagle-import") (part "LED-BLUE0603"))
    )
    (comp (ref "D992")
      (value "LED-BLUE0603")
      (footprint "eagle-import:LED-0603")
      (libsource (lib "eagle-import") (part "LED-BLUE0603"))
    )
    (comp (ref "D993")
      (value "LED-BLUE0603")
      (footprint "eagle-import:LED-0603")
      (libsource (lib "eagle-import") (part "LED-BLUE0603"))
    )
    (comp (ref "D994")
      (value "LED-BLUE0603")
      (footprint "eagle-import:LED-0603")
      (libsource (lib "eagle-import") (part "LED-BLUE0603"))
    )
    (comp (ref "D995")
      (value "LED-BLUE0603")
      (footprint "eagle-import:LED-0603")
      (libsource (lib "eagle-import") (part "LED-BLUE0603"))
    )
    (comp (ref "D996")
      (value "LED-BLUE0603")
      (footprint "eagle-import:LED-0603")
      (libsource (lib "eagle-import") (part "LED-BLUE0603"))
    )
    (comp (ref "D997")
      (value "LED-BLUE0603")
      (footprint "eagle-import:LED-0603")
      (libsource (lib "eagle-import") (part "LED-BLUE0603"))
    )
    (comp (ref "D998")
      (value "LED-BLUE0603")
      (footprint "eagle-import:LED-0603")
      (libsource (lib "eagle-import") (part "LED-BLUE0603"))
    )
    (comp (ref "D999")
      (value "LED-BLUE0603")
      (footprint "eagle-import:LED-0603")
      (libsource (lib "eagle-import") (part "LED-BLUE0603"))
    )
    (comp (ref "D1000")
      (value "LED-BLUE0603")
      (footprint "eagle-import:LED-0603")
      (libsource (lib "eagle-import") (part "LED-BLUE0603"))
    )
    (comp (ref "D1001")
      (value "LED-BLUE0603")
      (footprint "eagle-import:LED-0603")
      (libsource (lib "eagle-import") (part "LED-BLUE0603"))
    )
    (comp (ref "D1002")
      (value "LED-BLUE0603")
      (footprint "eagle-import:LED-0603")
      (libsource (lib "eagle-import") (part "LED-BLUE0603"))
    )
    (comp (ref "D1003")
      (value "LED-BLUE0603")
      (footprint "eagle-import:LED-0603")
      (libsource (lib "eagle-import") (part "LED-BLUE0603"))
    )
    (comp (ref "D1004")
      (value "LED-BLUE0603")
      (footprint "eagle-import:LED-0603")
      (libsource (lib "eagle-import") (part "LED-BLUE0603"))
    )
    (comp (ref "D1005")
      (value "LED-BLUE0603")
      (footprint "eagle-import:LED-0603")
      (libsource (lib "eagle-import") (part "LED-BLUE0603"))
    )
    (comp (ref "D1006")
      (value "LED-BLUE0603")
      (footprint "eagle-import:LED-0603")
      (libsource (lib "eagle-import") (part "LED-BLUE0603"))
    )
    (comp (ref "D1007")
      (value "LED-BLUE0603")
      (footprint "eagle-import:LED-0603")
      (libsource (lib "eagle-import") (part "LED-BLUE0603"))
    )
    (comp (ref "D1008")
      (value "LED-BLUE0603")
      (footprint "eagle-import:LED-0603")
      (libsource (lib "eagle-import") (part "LED-BLUE0603"))
    )
    (comp (ref "D1009")
      (value "LED-BLUE0603")
      (footprint "eagle-import:LED-0603")
      (libsource (lib "eagle-import") (part "LED-BLUE0603"))
    )
    (comp (ref "D1010")
      (value "LED-BLUE0603")
      (footprint "eagle-import:LED-0603")
      (libsource (lib "eagle-import") (part "LED-BLUE0603"))
    )
    (comp (ref "D1011")
      (value "LED-BLUE0603")
      (footprint "eagle-import:LED-0603")
      (libsource (lib "eagle-import") (part "LED-BLUE0603"))
    )
    (comp (ref "D1012")
      (value "LED-BLUE0603")
      (footprint "eagle-import:LED-0603")
      (libsource (lib "eagle-import") (part "LED-BLUE0603"))
    )
    (comp (ref "D1013")
      (value "LED-BLUE0603")
      (footprint "eagle-import:LED-0603")
      (libsource (lib "eagle-import") (part "LED-BLUE0603"))
    )
    (comp (ref "D1014")
      (value "LED-BLUE0603")
      (footprint "eagle-import:LED-0603")
      (libsource (lib "eagle-import") (part "LED-BLUE0603"))
    )
    (comp (ref "D1015")
      (value "LED-BLUE0603")
      (footprint "eagle-import:LED-0603")
      (libsource (lib "eagle-import") (part "LED-BLUE0603"))
    )
    (comp (ref "D1016")
      (value "LED-BLUE0603")
      (footprint "eagle-import:LED-0603")
      (libsource (lib "eagle-import") (part "LED-BLUE0603"))
    )
    (comp (ref "D1017")
      (value "LED-BLUE0603")
      (footprint "eagle-import:LED-0603")
      (libsource (lib "eagle-import") (part "LED-BLUE0603"))
    )
    (comp (ref "D1018")
      (value "LED-BLUE0603")
      (footprint "eagle-import:LED-0603")
      (libsource (lib "eagle-import") (part "LED-BLUE0603"))
    )
    (comp (ref "D1019")
      (value "LED-BLUE0603")
      (footprint "eagle-import:LED-0603")
      (libsource (lib "eagle-import") (part "LED-BLUE0603"))
    )
    (comp (ref "D1020")
      (value "LED-BLUE0603")
      (footprint "eagle-import:LED-0603")
      (libsource (lib "eagle-import") (part "LED-BLUE0603"))
    )
    (comp (ref "D1021")
      (value "LED-BLUE0603")
      (footprint "eagle-import:LED-0603")
      (libsource (lib "eagle-import") (part "LED-BLUE0603"))
    )
    (comp (ref "D1022")
      (value "LED-BLUE0603")
      (footprint "eagle-import:LED-0603")
      (libsource (lib "eagle-import") (part "LED-BLUE0603"))
    )
    (comp (ref "D1023")
      (value "LED-BLUE0603")
      (footprint "eagle-import:LED-0603")
      (libsource (lib "eagle-import") (part "LED-BLUE0603"))
    )
    (comp (ref "D1024")
      (value "LED-BLUE0603")
      (footprint "eagle-import:LED-0603")
      (libsource (lib "eagle-import") (part "LED-BLUE0603"))
    )
    (comp (ref "D1025")
      (value "LED-BLUE0603")
      (footprint "eagle-import:LED-0603")
      (libsource (lib "eagle-import") (part "LED-BLUE0603"))
    )
    (comp (ref "D1026")
      (value "LED-BLUE0603")
      (footprint "eagle-import:LED-0603")
      (libsource (lib "eagle-import") (part "LED-BLUE0603"))
    )
    (comp (ref "D1027")
      (value "LED-BLUE0603")
      (footprint "eagle-import:LED-0603")
      (libsource (lib "eagle-import") (part "LED-BLUE0603"))
    )
    (comp (ref "D1028")
      (value "3A/10V/280mV")
      (footprint "eagle-import:SOD-323")
      (libsource (lib "eagle-import") (part "DIODE-SCHOTTKY-BAT60A"))
    )
    (comp (ref "F1")
      (value "1A")
      (footprint "eagle-import:0805")
      (libsource (lib "eagle-import") (part "RESISTOR0805-RES"))
    )
    (comp (ref "IC1")
      (value "TLC59283DBQR")
      (footprint "eagle-import:DBQ24_TEX")
      (fields (field (name "COPYRIGHT") "Copyright (C) 2024 Ultra Librarian. All rights reserved."))
      (libsource (lib "eagle-import") (part "TLC59283DBQR"))
    )
    (comp (ref "IC2")
      (value "TLC59283DBQR")
      (footprint "eagle-import:DBQ24_TEX")
      (fields (field (name "COPYRIGHT") "Copyright (C) 2024 Ultra Librarian. All rights reserved."))
      (libsource (lib "eagle-import") (part "TLC59283DBQR"))
    )
    (comp (ref "IC3")
      (value "TLC59283DBQR")
      (footprint "eagle-import:DBQ24_TEX")
      (fields (field (name "COPYRIGHT") "Copyright (C) 2024 Ultra Librarian. All rights reserved."))
      (libsource (lib "eagle-import") (part "TLC59283DBQR"))
    )
    (comp (ref "IC4")
      (value "TLC59283DBQR")
      (footprint "eagle-import:DBQ24_TEX")
      (fields (field (name "COPYRIGHT") "Copyright (C) 2024 Ultra Librarian. All rights reserved."))
      (libsource (lib "eagle-import") (part "TLC59283DBQR"))
    )
    (comp (ref "IC5")
      (value "TLC59283DBQR")
      (footprint "eagle-import:DBQ24_TEX")
      (fields (field (name "COPYRIGHT") "Copyright (C) 2024 Ultra Librarian. All rights reserved."))
      (libsource (lib "eagle-import") (part "TLC59283DBQR"))
    )
    (comp (ref "IC6")
      (value "TLC59283DBQR")
      (footprint "eagle-import:DBQ24_TEX")
      (fields (field (name "COPYRIGHT") "Copyright (C) 2024 Ultra Librarian. All rights reserved."))
      (libsource (lib "eagle-import") (part "TLC59283DBQR"))
    )
    (comp (ref "IC7")
      (value "TLC59283DBQR")
      (footprint "eagle-import:DBQ24_TEX")
      (fields (field (name "COPYRIGHT") "Copyright (C) 2024 Ultra Librarian. All rights reserved."))
      (libsource (lib "eagle-import") (part "TLC59283DBQR"))
    )
    (comp (ref "IC8")
      (value "TLC59283DBQR")
      (footprint "eagle-import:DBQ24_TEX")
      (fields (field (name "COPYRIGHT") "Copyright (C) 2024 Ultra Librarian. All rights reserved."))
      (libsource (lib "eagle-import") (part "TLC59283DBQR"))
    )
    (comp (ref "IC9")
      (value "TLC59283DBQR")
      (footprint "eagle-import:DBQ24_TEX")
      (fields (field (name "COPYRIGHT") "Copyright (C) 2024 Ultra Librarian. All rights reserved."))
      (libsource (lib "eagle-import") (part "TLC59283DBQR"))
    )
    (comp (ref "IC10")
      (value "TLC59283DBQR")
      (footprint "eagle-import:DBQ24_TEX")
      (fields (field (name "COPYRIGHT") "Copyright (C) 2024 Ultra Librarian. All rights reserved."))
      (libsource (lib "eagle-import") (part "TLC59283DBQR"))
    )
    (comp (ref "IC11")
      (value "TLC59283DBQR")
      (footprint "eagle-import:DBQ24_TEX")
      (fields (field (name "COPYRIGHT") "Copyright (C) 2024 Ultra Librarian. All rights reserved."))
      (libsource (lib "eagle-import") (part "TLC59283DBQR"))
    )
    (comp (ref "IC12")
      (value "TLC59283DBQR")
      (footprint "eagle-import:DBQ24_TEX")
      (fields (field (name "COPYRIGHT") "Copyright (C) 2024 Ultra Librarian. All rights reserved."))
      (libsource (lib "eagle-import") (part "TLC59283DBQR"))
    )
    (comp (ref "IC13")
      (value "TLC59283DBQR")
      (footprint "eagle-import:DBQ24_TEX")
      (fields (field (name "COPYRIGHT") "Copyright (C) 2024 Ultra Librarian. All rights reserved."))
      (libsource (lib "eagle-import") (part "TLC59283DBQR"))
    )
    (comp (ref "IC14")
      (value "TLC59283DBQR")
      (footprint "eagle-import:DBQ24_TEX")
      (fields (field (name "COPYRIGHT") "Copyright (C) 2024 Ultra Librarian. All rights reserved."))
      (libsource (lib "eagle-import") (part "TLC59283DBQR"))
    )
    (comp (ref "IC15")
      (value "TLC59283DBQR")
      (footprint "eagle-import:DBQ24_TEX")
      (fields (field (name "COPYRIGHT") "Copyright (C) 2024 Ultra Librarian. All rights reserved."))
      (libsource (lib "eagle-import") (part "TLC59283DBQR"))
    )
    (comp (ref "IC16")
      (value "TLC59283DBQR")
      (footprint "eagle-import:DBQ24_TEX")
      (fields (field (name "COPYRIGHT") "Copyright (C) 2024 Ultra Librarian. All rights reserved."))
      (libsource (lib "eagle-import") (part "TLC59283DBQR"))
    )
    (comp (ref "IC17")
      (value "TLC59283DBQR")
      (footprint "eagle-import:DBQ24_TEX")
      (fields (field (name "COPYRIGHT") "Copyright (C) 2024 Ultra Librarian. All rights reserved."))
      (libsource (lib "eagle-import") (part "TLC59283DBQR"))
    )
    (comp (ref "IC18")
      (value "TLC59283DBQR")
      (footprint "eagle-import:DBQ24_TEX")
      (fields (field (name "COPYRIGHT") "Copyright (C) 2024 Ultra Librarian. All rights reserved."))
      (libsource (lib "eagle-import") (part "TLC59283DBQR"))
    )
    (comp (ref "IC19")
      (value "TLC59283DBQR")
      (footprint "eagle-import:DBQ24_TEX")
      (fields (field (name "COPYRIGHT") "Copyright (C) 2024 Ultra Librarian. All rights reserved."))
      (libsource (lib "eagle-import") (part "TLC59283DBQR"))
    )
    (comp (ref "IC20")
      (value "TLC59283DBQR")
      (footprint "eagle-import:DBQ24_TEX")
      (fields (field (name "COPYRIGHT") "Copyright (C) 2024 Ultra Librarian. All rights reserved."))
      (libsource (lib "eagle-import") (part "TLC59283DBQR"))
    )
    (comp (ref "IC21")
      (value "TLC59283DBQR")
      (footprint "eagle-import:DBQ24_TEX")
      (fields (field (name "COPYRIGHT") "Copyright (C) 2024 Ultra Librarian. All rights reserved."))
      (libsource (lib "eagle-import") (part "TLC59283DBQR"))
    )
    (comp (ref "IC22")
      (value "TLC59283DBQR")
      (footprint "eagle-import:DBQ24_TEX")
      (fields (field (name "COPYRIGHT") "Copyright (C) 2024 Ultra Librarian. All rights reserved."))
      (libsource (lib "eagle-import") (part "TLC59283DBQR"))
    )
    (comp (ref "IC23")
      (value "TLC59283DBQR")
      (footprint "eagle-import:DBQ24_TEX")
      (fields (field (name "COPYRIGHT") "Copyright (C) 2024 Ultra Librarian. All rights reserved."))
      (libsource (lib "eagle-import") (part "TLC59283DBQR"))
    )
    (comp (ref "IC24")
      (value "TLC59283DBQR")
      (footprint "eagle-import:DBQ24_TEX")
      (fields (field (name "COPYRIGHT") "Copyright (C) 2024 Ultra Librarian. All rights reserved."))
      (libsource (lib "eagle-import") (part "TLC59283DBQR"))
    )
    (comp (ref "IC25")
      (value "TLC59283DBQR")
      (footprint "eagle-import:DBQ24_TEX")
      (fields (field (name "COPYRIGHT") "Copyright (C) 2024 Ultra Librarian. All rights reserved."))
      (libsource (lib "eagle-import") (part "TLC59283DBQR"))
    )
    (comp (ref "IC26")
      (value "TLC59283DBQR")
      (footprint "eagle-import:DBQ24_TEX")
      (fields (field (name "COPYRIGHT") "Copyright (C) 2024 Ultra Librarian. All rights reserved."))
      (libsource (lib "eagle-import") (part "TLC59283DBQR"))
    )
    (comp (ref "IC27")
      (value "TLC59283DBQR")
      (footprint "eagle-import:DBQ24_TEX")
      (fields (field (name "COPYRIGHT") "Copyright (C) 2024 Ultra Librarian. All rights reserved."))
      (libsource (lib "eagle-import") (part "TLC59283DBQR"))
    )
    (comp (ref "IC28")
      (value "TLC59283DBQR")
      (footprint "eagle-import:DBQ24_TEX")
      (fields (field (name "COPYRIGHT") "Copyright (C) 2024 Ultra Librarian. All rights reserved."))
      (libsource (lib "eagle-import") (part "TLC59283DBQR"))
    )
    (comp (ref "IC29")
      (value "TLC59283DBQR")
      (footprint "eagle-import:DBQ24_TEX")
      (fields (field (name "COPYRIGHT") "Copyright (C) 2024 Ultra Librarian. All rights reserved."))
      (libsource (lib "eagle-import") (part "TLC59283DBQR"))
    )
    (comp (ref "IC30")
      (value "TLC59283DBQR")
      (footprint "eagle-import:DBQ24_TEX")
      (fields (field (name "COPYRIGHT") "Copyright (C) 2024 Ultra Librarian. All rights reserved."))
      (libsource (lib "eagle-import") (part "TLC59283DBQR"))
    )
    (comp (ref "IC31")
      (value "TLC59283DBQR")
      (footprint "eagle-import:DBQ24_TEX")
      (fields (field (name "COPYRIGHT") "Copyright (C) 2024 Ultra Librarian. All rights reserved."))
      (libsource (lib "eagle-import") (part "TLC59283DBQR"))
    )
    (comp (ref "IC32")
      (value "TLC59283DBQR")
      (footprint "eagle-import:DBQ24_TEX")
      (fields (field (name "COPYRIGHT") "Copyright (C) 2024 Ultra Librarian. All rights reserved."))
      (libsource (lib "eagle-import") (part "TLC59283DBQR"))
    )
    (comp (ref "IC33")
      (value "TLC59283DBQR")
      (footprint "eagle-import:DBQ24_TEX")
      (fields (field (name "COPYRIGHT") "Copyright (C) 2024 Ultra Librarian. All rights reserved."))
      (libsource (lib "eagle-import") (part "TLC59283DBQR"))
    )
    (comp (ref "IC34")
      (value "TLC59283DBQR")
      (footprint "eagle-import:DBQ24_TEX")
      (fields (field (name "COPYRIGHT") "Copyright (C) 2024 Ultra Librarian. All rights reserved."))
      (libsource (lib "eagle-import") (part "TLC59283DBQR"))
    )
    (comp (ref "IC35")
      (value "TLC59283DBQR")
      (footprint "eagle-import:DBQ24_TEX")
      (fields (field (name "COPYRIGHT") "Copyright (C) 2024 Ultra Librarian. All rights reserved."))
      (libsource (lib "eagle-import") (part "TLC59283DBQR"))
    )
    (comp (ref "IC36")
      (value "TLC59283DBQR")
      (footprint "eagle-import:DBQ24_TEX")
      (fields (field (name "COPYRIGHT") "Copyright (C) 2024 Ultra Librarian. All rights reserved."))
      (libsource (lib "eagle-import") (part "TLC59283DBQR"))
    )
    (comp (ref "IC37")
      (value "TLC59283DBQR")
      (footprint "eagle-import:DBQ24_TEX")
      (fields (field (name "COPYRIGHT") "Copyright (C) 2024 Ultra Librarian. All rights reserved."))
      (libsource (lib "eagle-import") (part "TLC59283DBQR"))
    )
    (comp (ref "IC38")
      (value "TLC59283DBQR")
      (footprint "eagle-import:DBQ24_TEX")
      (fields (field (name "COPYRIGHT") "Copyright (C) 2024 Ultra Librarian. All rights reserved."))
      (libsource (lib "eagle-import") (part "TLC59283DBQR"))
    )
    (comp (ref "IC39")
      (value "TLC59283DBQR")
      (footprint "eagle-import:DBQ24_TEX")
      (fields (field (name "COPYRIGHT") "Copyright (C) 2024 Ultra Librarian. All rights reserved."))
      (libsource (lib "eagle-import") (part "TLC59283DBQR"))
    )
    (comp (ref "IC40")
      (value "TLC59283DBQR")
      (footprint "eagle-import:DBQ24_TEX")
      (fields (field (name "COPYRIGHT") "Copyright (C) 2024 Ultra Librarian. All rights reserved."))
      (libsource (lib "eagle-import") (part "TLC59283DBQR"))
    )
    (comp (ref "IC41")
      (value "TLC59283DBQR")
      (footprint "eagle-import:DBQ24_TEX")
      (fields (field (name "COPYRIGHT") "Copyright (C) 2024 Ultra Librarian. All rights reserved."))
      (libsource (lib "eagle-import") (part "TLC59283DBQR"))
    )
    (comp (ref "IC42")
      (value "TLC59283DBQR")
      (footprint "eagle-import:DBQ24_TEX")
      (fields (field (name "COPYRIGHT") "Copyright (C) 2024 Ultra Librarian. All rights reserved."))
      (libsource (lib "eagle-import") (part "TLC59283DBQR"))
    )
    (comp (ref "IC43")
      (value "TLC59283DBQR")
      (footprint "eagle-import:DBQ24_TEX")
      (fields (field (name "COPYRIGHT") "Copyright (C) 2024 Ultra Librarian. All rights reserved."))
      (libsource (lib "eagle-import") (part "TLC59283DBQR"))
    )
    (comp (ref "IC44")
      (value "TLC59283DBQR")
      (footprint "eagle-import:DBQ24_TEX")
      (fields (field (name "COPYRIGHT") "Copyright (C) 2024 Ultra Librarian. All rights reserved."))
      (libsource (lib "eagle-import") (part "TLC59283DBQR"))
    )
    (comp (ref "IC45")
      (value "TLC59283DBQR")
      (footprint "eagle-import:DBQ24_TEX")
      (fields (field (name "COPYRIGHT") "Copyright (C) 2024 Ultra Librarian. All rights reserved."))
      (libsource (lib "eagle-import") (part "TLC59283DBQR"))
    )
    (comp (ref "IC46")
      (value "TLC59283DBQR")
      (footprint "eagle-import:DBQ24_TEX")
      (fields (field (name "COPYRIGHT") "Copyright (C) 2024 Ultra Librarian. All rights reserved."))
      (libsource (lib "eagle-import") (part "TLC59283DBQR"))
    )
    (comp (ref "IC47")
      (value "TLC59283DBQR")
      (footprint "eagle-import:DBQ24_TEX")
      (fields (field (name "COPYRIGHT") "Copyright (C) 2024 Ultra Librarian. All rights reserved."))
      (libsource (lib "eagle-import") (part "TLC59283DBQR"))
    )
    (comp (ref "IC48")
      (value "TLC59283DBQR")
      (footprint "eagle-import:DBQ24_TEX")
      (fields (field (name "COPYRIGHT") "Copyright (C) 2024 Ultra Librarian. All rights reserved."))
      (libsource (lib "eagle-import") (part "TLC59283DBQR"))
    )
    (comp (ref "IC49")
      (value "TLC59283DBQR")
      (footprint "eagle-import:DBQ24_TEX")
      (fields (field (name "COPYRIGHT") "Copyright (C) 2024 Ultra Librarian. All rights reserved."))
      (libsource (lib "eagle-import") (part "TLC59283DBQR"))
    )
    (comp (ref "IC50")
      (value "TLC59283DBQR")
      (footprint "eagle-import:DBQ24_TEX")
      (fields (field (name "COPYRIGHT") "Copyright (C) 2024 Ultra Librarian. All rights reserved."))
      (libsource (lib "eagle-import") (part "TLC59283DBQR"))
    )
    (comp (ref "IC51")
      (value "TLC59283DBQR")
      (footprint "eagle-import:DBQ24_TEX")
      (fields (field (name "COPYRIGHT") "Copyright (C) 2024 Ultra Librarian. All rights reserved."))
      (libsource (lib "eagle-import") (part "TLC59283DBQR"))
    )
    (comp (ref "IC52")
      (value "TLC59283DBQR")
      (footprint "eagle-import:DBQ24_TEX")
      (fields (field (name "COPYRIGHT") "Copyright (C) 2024 Ultra Librarian. All rights reserved."))
      (libsource (lib "eagle-import") (part "TLC59283DBQR"))
    )
    (comp (ref "IC53")
      (value "TLC59283DBQR")
      (footprint "eagle-import:DBQ24_TEX")
      (fields (field (name "COPYRIGHT") "Copyright (C) 2024 Ultra Librarian. All rights reserved."))
      (libsource (lib "eagle-import") (part "TLC59283DBQR"))
    )
    (comp (ref "IC54")
      (value "TLC59283DBQR")
      (footprint "eagle-import:DBQ24_TEX")
      (fields (field (name "COPYRIGHT") "Copyright (C) 2024 Ultra Librarian. All rights reserved."))
      (libsource (lib "eagle-import") (part "TLC59283DBQR"))
    )
    (comp (ref "IC55")
      (value "TLC59283DBQR")
      (footprint "eagle-import:DBQ24_TEX")
      (fields (field (name "COPYRIGHT") "Copyright (C) 2024 Ultra Librarian. All rights reserved."))
      (libsource (lib "eagle-import") (part "TLC59283DBQR"))
    )
    (comp (ref "IC56")
      (value "TLC59283DBQR")
      (footprint "eagle-import:DBQ24_TEX")
      (fields (field (name "COPYRIGHT") "Copyright (C) 2024 Ultra Librarian. All rights reserved."))
      (libsource (lib "eagle-import") (part "TLC59283DBQR"))
    )
    (comp (ref "IC57")
      (value "TLC59283DBQR")
      (footprint "eagle-import:DBQ24_TEX")
      (fields (field (name "COPYRIGHT") "Copyright (C) 2024 Ultra Librarian. All rights reserved."))
      (libsource (lib "eagle-import") (part "TLC59283DBQR"))
    )
    (comp (ref "IC58")
      (value "TLC59283DBQR")
      (footprint "eagle-import:DBQ24_TEX")
      (fields (field (name "COPYRIGHT") "Copyright (C) 2024 Ultra Librarian. All rights reserved."))
      (libsource (lib "eagle-import") (part "TLC59283DBQR"))
    )
    (comp (ref "IC59")
      (value "TLC59283DBQR")
      (footprint "eagle-import:DBQ24_TEX")
      (fields (field (name "COPYRIGHT") "Copyright (C) 2024 Ultra Librarian. All rights reserved."))
      (libsource (lib "eagle-import") (part "TLC59283DBQR"))
    )
    (comp (ref "IC60")
      (value "TLC59283DBQR")
      (footprint "eagle-import:DBQ24_TEX")
      (fields (field (name "COPYRIGHT") "Copyright (C) 2024 Ultra Librarian. All rights reserved."))
      (libsource (lib "eagle-import") (part "TLC59283DBQR"))
    )
    (comp (ref "IC61")
      (value "TLC59283DBQR")
      (footprint "eagle-import:DBQ24_TEX")
      (fields (field (name "COPYRIGHT") "Copyright (C) 2024 Ultra Librarian. All rights reserved."))
      (libsource (lib "eagle-import") (part "TLC59283DBQR"))
    )
    (comp (ref "IC62")
      (value "TLC59283DBQR")
      (footprint "eagle-import:DBQ24_TEX")
      (fields (field (name "COPYRIGHT") "Copyright (C) 2024 Ultra Librarian. All rights reserved."))
      (libsource (lib "eagle-import") (part "TLC59283DBQR"))
    )
    (comp (ref "IC63")
      (value "TLC59283DBQR")
      (footprint "eagle-import:DBQ24_TEX")
      (fields (field (name "COPYRIGHT") "Copyright (C) 2024 Ultra Librarian. All rights reserved."))
      (libsource (lib "eagle-import") (part "TLC59283DBQR"))
    )
    (comp (ref "IC64")
      (value "TLC59283DBQR")
      (footprint "eagle-import:DBQ24_TEX")
      (fields (field (name "COPYRIGHT") "Copyright (C) 2024 Ultra Librarian. All rights reserved."))
      (libsource (lib "eagle-import") (part "TLC59283DBQR"))
    )
    (comp (ref "J1")
      (value "MICROSD-PUSH-OUT")
      (footprint "eagle-import:MICROSD-PUSH-OUT")
      (libsource (lib "eagle-import") (part "MICROSD-PUSH-OUT"))
    )
    (comp (ref "J2")
      (value "10033527-N3112MLF")
      (footprint "eagle-import:AMPHENOL_10033527-N3112MLF")
      (fields (field (name "MANUFACTURER") "Amphenol"))
      (libsource (lib "eagle-import") (part "10033527-N3112MLF"))
    )
    (comp (ref "JP1")
      (value "PINHD-1X2")
      (footprint "eagle-import:1X02")
      (libsource (lib "eagle-import") (part "PINHD-1X2"))
    )
    (comp (ref "JP2")
      (value "SERIAL_DEBUG")
      (footprint "eagle-import:PINHEAD_1X04")
      (libsource (lib "eagle-import") (part "PINHEAD_PINHD-1X4"))
    )
    (comp (ref "L1")
      (value "ED16")
      (footprint "eagle-import:ED16")
      (libsource (lib "eagle-import") (part "ED16"))
    )
    (comp (ref "P1")
      (value "HEADER5")
      (footprint "eagle-import:HEADER5")
      (libsource (lib "eagle-import") (part "HEADER5"))
    )
    (comp (ref "P2")
      (value "HEADER5")
      (footprint "eagle-import:HEADER5")
      (libsource (lib "eagle-import") (part "HEADER5"))
    )
    (comp (ref "R1")
      (value "4.7k")
      (footprint "eagle-import:0805")
      (libsource (lib "eagle-import") (part "RESISTOR0805-RES"))
    )
    (comp (ref "R2")
      (value "10K")
      (footprint "eagle-import:0805")
      (libsource (lib "eagle-import") (part "RESISTOR0805-RES"))
    )
    (comp (ref "R3")
      (value "10K")
      (footprint "eagle-import:0805")
      (libsource (lib "eagle-import") (part "RESISTOR0805-RES"))
    )
    (comp (ref "R4")
      (value "22")
      (footprint "eagle-import:0805")
      (libsource (lib "eagle-import") (part "RESISTOR0805-RES"))
    )
    (comp (ref "R5")
      (value "22")
      (footprint "eagle-import:0805")
      (libsource (lib "eagle-import") (part "RESISTOR0805-RES"))
    )
    (comp (ref "R6")
      (value "10K")
      (footprint "eagle-import:0805")
      (libsource (lib "eagle-import") (part "RESISTOR0805-RES"))
    )
    (comp (ref "R7")
      (value "3.3k")
      (footprint "eagle-import:0805")
      (libsource (lib "eagle-import") (part "RESISTOR0805-RES"))
    )
    (comp (ref "R8")
      (value "1k")
      (footprint "eagle-import:0805")
      (libsource (lib "eagle-import") (part "RESISTOR0805-RES"))
    )
    (comp (ref "R9")
      (value "1k")
      (footprint "eagle-import:0805")
      (libsource (lib "eagle-import") (part "RESISTOR0805-RES"))
    )
    (comp (ref "R10")
      (value "10k")
      (footprint "eagle-import:0805")
      (libsource (lib "eagle-import") (part "RESISTOR0805-RES"))
    )
    (comp (ref "R11")
      (value "33k")
      (footprint "eagle-import:0805")
      (libsource (lib "eagle-import") (part "RESISTOR0805-RES"))
    )
    (comp (ref "R12")
      (value "10k")
      (footprint "eagle-import:0603")
      (libsource (lib "eagle-import") (part "10KOHM-0603-1/10W-1%"))
    )
    (comp (ref "R13")
      (value "10k")
      (footprint "eagle-import:0603")
      (libsource (lib "eagle-import") (part "10KOHM-0603-1/10W-1%"))
    )
    (comp (ref "R14")
      (value "10k")
      (footprint "eagle-import:0603")
      (libsource (lib "eagle-import") (part "10KOHM-0603-1/10W-1%"))
    )
    (comp (ref "R15")
      (value "10k")
      (footprint "eagle-import:0603")
      (libsource (lib "eagle-import") (part "10KOHM-0603-1/10W-1%"))
    )
    (comp (ref "R16")
      (value "10k")
      (footprint "eagle-import:0603")
      (libsource (lib "eagle-import") (part "10KOHM-0603-1/10W-1%"))
    )
    (comp (ref "R17")
      (value "10k")
      (footprint "eagle-import:0603")
      (libsource (lib "eagle-import") (part "10KOHM-0603-1/10W-1%"))
    )
    (comp (ref "R18")
      (value "10k")
      (footprint "eagle-import:0603")
      (libsource (lib "eagle-import") (part "10KOHM-0603-1/10W-1%"))
    )
    (comp (ref "R19")
      (value "10k")
      (footprint "eagle-import:0603")
      (libsource (lib "eagle-import") (part "10KOHM-0603-1/10W-1%"))
    )
    (comp (ref "R20")
      (value "10k")
      (footprint "eagle-import:0603")
      (libsource (lib "eagle-import") (part "10KOHM-0603-1/10W-1%"))
    )
    (comp (ref "R21")
      (value "10k")
      (footprint "eagle-import:0603")
      (libsource (lib "eagle-import") (part "10KOHM-0603-1/10W-1%"))
    )
    (comp (ref "R22")
      (value "10k")
      (footprint "eagle-import:0603")
      (libsource (lib "eagle-import") (part "10KOHM-0603-1/10W-1%"))
    )
    (comp (ref "R23")
      (value "10k")
      (footprint "eagle-import:0603")
      (libsource (lib "eagle-import") (part "10KOHM-0603-1/10W-1%"))
    )
    (comp (ref "R24")
      (value "10k")
      (footprint "eagle-import:0603")
      (libsource (lib "eagle-import") (part "10KOHM-0603-1/10W-1%"))
    )
    (comp (ref "R25")
      (value "10k")
      (footprint "eagle-import:0603")
      (libsource (lib "eagle-import") (part "10KOHM-0603-1/10W-1%"))
    )
    (comp (ref "R26")
      (value "10k")
      (footprint "eagle-import:0603")
      (libsource (lib "eagle-import") (part "10KOHM-0603-1/10W-1%"))
    )
    (comp (ref "R27")
      (value "10k")
      (footprint "eagle-import:0603")
      (libsource (lib "eagle-import") (part "10KOHM-0603-1/10W-1%"))
    )
    (comp (ref "R28")
      (value "10k")
      (footprint "eagle-import:0603")
      (libsource (lib "eagle-import") (part "10KOHM-0603-1/10W-1%"))
    )
    (comp (ref "R29")
      (value "10k")
      (footprint "eagle-import:0603")
      (libsource (lib "eagle-import") (part "10KOHM-0603-1/10W-1%"))
    )
    (comp (ref "R30")
      (value "10k")
      (footprint "eagle-import:0603")
      (libsource (lib "eagle-import") (part "10KOHM-0603-1/10W-1%"))
    )
    (comp (ref "R31")
      (value "10k")
      (footprint "eagle-import:0603")
      (libsource (lib "eagle-import") (part "10KOHM-0603-1/10W-1%"))
    )
    (comp (ref "R32")
      (value "10k")
      (footprint "eagle-import:0603")
      (libsource (lib "eagle-import") (part "10KOHM-0603-1/10W-1%"))
    )
    (comp (ref "R33")
      (value "10k")
      (footprint "eagle-import:0603")
      (libsource (lib "eagle-import") (part "10KOHM-0603-1/10W-1%"))
    )
    (comp (ref "R34")
      (value "10k")
      (footprint "eagle-import:0603")
      (libsource (lib "eagle-import") (part "10KOHM-0603-1/10W-1%"))
    )
    (comp (ref "R35")
      (value "10k")
      (footprint "eagle-import:0603")
      (libsource (lib "eagle-import") (part "10KOHM-0603-1/10W-1%"))
    )
    (comp (ref "R36")
      (value "10k")
      (footprint "eagle-import:0603")
      (libsource (lib "eagle-import") (part "10KOHM-0603-1/10W-1%"))
    )
    (comp (ref "R37")
      (value "10k")
      (footprint "eagle-import:0603")
      (libsource (lib "eagle-import") (part "10KOHM-0603-1/10W-1%"))
    )
    (comp (ref "R38")
      (value "10k")
      (footprint "eagle-import:0603")
      (libsource (lib "eagle-import") (part "10KOHM-0603-1/10W-1%"))
    )
    (comp (ref "R39")
      (value "10k")
      (footprint "eagle-import:0603")
      (libsource (lib "eagle-import") (part "10KOHM-0603-1/10W-1%"))
    )
    (comp (ref "R40")
      (value "10k")
      (footprint "eagle-import:0603")
      (libsource (lib "eagle-import") (part "10KOHM-0603-1/10W-1%"))
    )
    (comp (ref "R41")
      (value "10k")
      (footprint "eagle-import:0603")
      (libsource (lib "eagle-import") (part "10KOHM-0603-1/10W-1%"))
    )
    (comp (ref "R42")
      (value "10k")
      (footprint "eagle-import:0603")
      (libsource (lib "eagle-import") (part "10KOHM-0603-1/10W-1%"))
    )
    (comp (ref "R43")
      (value "10k")
      (footprint "eagle-import:0603")
      (libsource (lib "eagle-import") (part "10KOHM-0603-1/10W-1%"))
    )
    (comp (ref "R44")
      (value "10k")
      (footprint "eagle-import:0603")
      (libsource (lib "eagle-import") (part "10KOHM-0603-1/10W-1%"))
    )
    (comp (ref "R45")
      (value "10k")
      (footprint "eagle-import:0603")
      (libsource (lib "eagle-import") (part "10KOHM-0603-1/10W-1%"))
    )
    (comp (ref "R46")
      (value "10k")
      (footprint "eagle-import:0603")
      (libsource (lib "eagle-import") (part "10KOHM-0603-1/10W-1%"))
    )
    (comp (ref "R47")
      (value "10k")
      (footprint "eagle-import:0603")
      (libsource (lib "eagle-import") (part "10KOHM-0603-1/10W-1%"))
    )
    (comp (ref "R48")
      (value "10k")
      (footprint "eagle-import:0603")
      (libsource (lib "eagle-import") (part "10KOHM-0603-1/10W-1%"))
    )
    (comp (ref "R49")
      (value "10k")
      (footprint "eagle-import:0603")
      (libsource (lib "eagle-import") (part "10KOHM-0603-1/10W-1%"))
    )
    (comp (ref "R50")
      (value "10k")
      (footprint "eagle-import:0603")
      (libsource (lib "eagle-import") (part "10KOHM-0603-1/10W-1%"))
    )
    (comp (ref "R51")
      (value "10k")
      (footprint "eagle-import:0603")
      (libsource (lib "eagle-import") (part "10KOHM-0603-1/10W-1%"))
    )
    (comp (ref "R52")
      (value "10k")
      (footprint "eagle-import:0603")
      (libsource (lib "eagle-import") (part "10KOHM-0603-1/10W-1%"))
    )
    (comp (ref "R53")
      (value "10k")
      (footprint "eagle-import:0603")
      (libsource (lib "eagle-import") (part "10KOHM-0603-1/10W-1%"))
    )
    (comp (ref "R54")
      (value "10k")
      (footprint "eagle-import:0603")
      (libsource (lib "eagle-import") (part "10KOHM-0603-1/10W-1%"))
    )
    (comp (ref "R55")
      (value "10k")
      (footprint "eagle-import:0603")
      (libsource (lib "eagle-import") (part "10KOHM-0603-1/10W-1%"))
    )
    (comp (ref "R56")
      (value "10k")
      (footprint "eagle-import:0603")
      (libsource (lib "eagle-import") (part "10KOHM-0603-1/10W-1%"))
    )
    (comp (ref "R57")
      (value "10k")
      (footprint "eagle-import:0603")
      (libsource (lib "eagle-import") (part "10KOHM-0603-1/10W-1%"))
    )
    (comp (ref "R58")
      (value "10k")
      (footprint "eagle-import:0603")
      (libsource (lib "eagle-import") (part "10KOHM-0603-1/10W-1%"))
    )
    (comp (ref "R59")
      (value "10k")
      (footprint "eagle-import:0603")
      (libsource (lib "eagle-import") (part "10KOHM-0603-1/10W-1%"))
    )
    (comp (ref "R60")
      (value "10k")
      (footprint "eagle-import:0603")
      (libsource (lib "eagle-import") (part "10KOHM-0603-1/10W-1%"))
    )
    (comp (ref "R61")
      (value "10k")
      (footprint "eagle-import:0603")
      (libsource (lib "eagle-import") (part "10KOHM-0603-1/10W-1%"))
    )
    (comp (ref "R62")
      (value "10k")
      (footprint "eagle-import:0603")
      (libsource (lib "eagle-import") (part "10KOHM-0603-1/10W-1%"))
    )
    (comp (ref "R63")
      (value "10k")
      (footprint "eagle-import:0603")
      (libsource (lib "eagle-import") (part "10KOHM-0603-1/10W-1%"))
    )
    (comp (ref "R64")
      (value "10k")
      (footprint "eagle-import:0603")
      (libsource (lib "eagle-import") (part "10KOHM-0603-1/10W-1%"))
    )
    (comp (ref "R65")
      (value "10k")
      (footprint "eagle-import:0603")
      (libsource (lib "eagle-import") (part "10KOHM-0603-1/10W-1%"))
    )
    (comp (ref "R66")
      (value "10k")
      (footprint "eagle-import:0603")
      (libsource (lib "eagle-import") (part "10KOHM-0603-1/10W-1%"))
    )
    (comp (ref "R67")
      (value "10k")
      (footprint "eagle-import:0603")
      (libsource (lib "eagle-import") (part "10KOHM-0603-1/10W-1%"))
    )
    (comp (ref "R68")
      (value "10k")
      (footprint "eagle-import:0603")
      (libsource (lib "eagle-import") (part "10KOHM-0603-1/10W-1%"))
    )
    (comp (ref "R69")
      (value "10k")
      (footprint "eagle-import:0603")
      (libsource (lib "eagle-import") (part "10KOHM-0603-1/10W-1%"))
    )
    (comp (ref "R70")
      (value "10k")
      (footprint "eagle-import:0603")
      (libsource (lib "eagle-import") (part "10KOHM-0603-1/10W-1%"))
    )
    (comp (ref "R71")
      (value "10k")
      (footprint "eagle-import:0603")
      (libsource (lib "eagle-import") (part "10KOHM-0603-1/10W-1%"))
    )
    (comp (ref "R72")
      (value "10k")
      (footprint "eagle-import:0603")
      (libsource (lib "eagle-import") (part "10KOHM-0603-1/10W-1%"))
    )
    (comp (ref "R73")
      (value "10k")
      (footprint "eagle-import:0603")
      (libsource (lib "eagle-import") (part "10KOHM-0603-1/10W-1%"))
    )
    (comp (ref "R74")
      (value "10k")
      (footprint "eagle-import:0603")
      (libsource (lib "eagle-import") (part "10KOHM-0603-1/10W-1%"))
    )
    (comp (ref "R75")
      (value "10k")
      (footprint "eagle-import:0603")
      (libsource (lib "eagle-import") (part "10KOHM-0603-1/10W-1%"))
    )
    (comp (ref "SW1")
      (value "PTS636_SM25F_SMTR_LFS")
      (footprint "eagle-import:SW2_PTS636_SM25F_SMTR_LFS_CNK")
      (fields
        (field (name "MANUFACTURER_PART_NUMBER") "PTS636 SM25F SMTR LFS")
        (field (name "COPYRIGHT") "Copyright (C) 2024 Ultra Librarian. All rights reserved.")
      )
      (libsource (lib "eagle-import") (part "PTS636_SM25F_SMTR_LFS"))
    )
    (comp (ref "SW2")
      (value "PTS636_SM25F_SMTR_LFS")
      (footprint "eagle-import:SW2_PTS636_SM25F_SMTR_LFS_CNK")
      (fields
        (field (name "MANUFACTURER_PART_NUMBER") "PTS636 SM25F SMTR LFS")
        (field (name "COPYRIGHT") "Copyright (C) 2024 Ultra Librarian. All rights reserved.")
      )
      (libsource (lib "eagle-import") (part "PTS636_SM25F_SMTR_LFS"))
    )
    (comp (ref "U2")
      (value "ESP32-S2-WROVER")
      (footprint "eagle-import:MODULE_ESP32-S2-WROVER")
      (fields (field (name "MF") "Espressif Systems"))
      (libsource (lib "eagle-import") (part "ESP32-S2-WROVER"))
    )
    (comp (ref "U3")
      (value "ME6211")
      (footprint "eagle-import:SOT23-5")
      (fields (field (name "MANUFACTURER") "MICRONE"))
      (libsource (lib "eagle-import") (part "ME6211"))
    )
    (comp (ref "U5")
      (value "XL4015")
      (footprint "eagle-import:TO263-5L_DIO")
      (fields (field (name "COPYRIGHT") "Copyright (C) 2024 Ultra Librarian. All rights reserved."))
      (libsource (lib "eagle-import") (part "XL4015"))
    )
  )
  (nets
    (net (code "1") (name "+5V") (class "Default")
      (node (ref "C11") (pin "+") (pinfunction "+_+") (pintype "passive"))
      (node (ref "C16") (pin "1") (pinfunction "1_1") (pintype "passive"))
      (node (ref "C17") (pin "1") (pinfunction "1_1") (pintype "passive"))
      (node (ref "C18") (pin "1") (pinfunction "1_1") (pintype "passive"))
      (node (ref "C19") (pin "1") (pinfunction "1_1") (pintype "passive"))
      (node (ref "C20") (pin "1") (pinfunction "1_1") (pintype "passive"))
      (node (ref "C21") (pin "1") (pinfunction "1_1") (pintype "passive"))
      (node (ref "C22") (pin "1") (pinfunction "1_1") (pintype "passive"))
      (node (ref "C23") (pin "1") (pinfunction "1_1") (pintype "passive"))
      (node (ref "C24") (pin "1") (pinfunction "1_1") (pintype "passive"))
      (node (ref "C25") (pin "1") (pinfunction "1_1") (pintype "passive"))
      (node (ref "C26") (pin "1") (pinfunction "1_1") (pintype "passive"))
      (node (ref "C27") (pin "1") (pinfunction "1_1") (pintype "passive"))
      (node (ref "C28") (pin "1") (pinfunction "1_1") (pintype "passive"))
      (node (ref "C29") (pin "1") (pinfunction "1_1") (pintype "passive"))
      (node (ref "C30") (pin "1") (pinfunction "1_1") (pintype "passive"))
      (node (ref "C31") (pin "1") (pinfunction "1_1") (pintype "passive"))
      (node (ref "C32") (pin "1") (pinfunction "1_1") (pintype "passive"))
      (node (ref "C33") (pin "1") (pinfunction "1_1") (pintype "passive"))
      (node (ref "C34") (pin "1") (pinfunction "1_1") (pintype "passive"))
      (node (ref "C35") (pin "1") (pinfunction "1_1") (pintype "passive"))
      (node (ref "C36") (pin "1") (pinfunction "1_1") (pintype "passive"))
      (node (ref "C37") (pin "1") (pinfunction "1_1") (pintype "passive"))
      (node (ref "C38") (pin "1") (pinfunction "1_1") (pintype "passive"))
      (node (ref "C39") (pin "1") (pinfunction "1_1") (pintype "passive"))
      (node (ref "C40") (pin "1") (pinfunction "1_1") (pintype "passive"))
      (node (ref "C41") (pin "1") (pinfunction "1_1") (pintype "passive"))
      (node (ref "C42") (pin "1") (pinfunction "1_1") (pintype "passive"))
      (node (ref "C43") (pin "1") (pinfunction "1_1") (pintype "passive"))
      (node (ref "C44") (pin "1") (pinfunction "1_1") (pintype "passive"))
      (node (ref "C45") (pin "1") (pinfunction "1_1") (pintype "passive"))
      (node (ref "C46") (pin "1") (pinfunction "1_1") (pintype "passive"))
      (node (ref "C47") (pin "1") (pinfunction "1_1") (pintype "passive"))
      (node (ref "C48") (pin "1") (pinfunction "1_1") (pintype "passive"))
      (node (ref "C49") (pin "1") (pinfunction "1_1") (pintype "passive"))
      (node (ref "C50") (pin "1") (pinfunction "1_1") (pintype "passive"))
      (node (ref "C51") (pin "1") (pinfunction "1_1") (pintype "passive"))
      (node (ref "C52") (pin "1") (pinfunction "1_1") (pintype "passive"))
      (node (ref "C53") (pin "1") (pinfunction "1_1") (pintype "passive"))
      (node (ref "C54") (pin "1") (pinfunction "1_1") (pintype "passive"))
      (node (ref "C55") (pin "1") (pinfunction "1_1") (pintype "passive"))
      (node (ref "C56") (pin "1") (pinfunction "1_1") (pintype "passive"))
      (node (ref "C57") (pin "1") (pinfunction "1_1") (pintype "passive"))
      (node (ref "C58") (pin "1") (pinfunction "1_1") (pintype "passive"))
      (node (ref "C59") (pin "1") (pinfunction "1_1") (pintype "passive"))
      (node (ref "C6") (pin "1") (pinfunction "1_1") (pintype "passive"))
      (node (ref "C60") (pin "1") (pinfunction "1_1") (pintype "passive"))
      (node (ref "C61") (pin "1") (pinfunction "1_1") (pintype "passive"))
      (node (ref "C62") (pin "1") (pinfunction "1_1") (pintype "passive"))
      (node (ref "C63") (pin "1") (pinfunction "1_1") (pintype "passive"))
      (node (ref "C64") (pin "1") (pinfunction "1_1") (pintype "passive"))
      (node (ref "C65") (pin "1") (pinfunction "1_1") (pintype "passive"))
      (node (ref "C66") (pin "1") (pinfunction "1_1") (pintype "passive"))
      (node (ref "C67") (pin "1") (pinfunction "1_1") (pintype "passive"))
      (node (ref "C68") (pin "1") (pinfunction "1_1") (pintype "passive"))
      (node (ref "C69") (pin "1") (pinfunction "1_1") (pintype "passive"))
      (node (ref "C70") (pin "1") (pinfunction "1_1") (pintype "passive"))
      (node (ref "C71") (pin "1") (pinfunction "1_1") (pintype "passive"))
      (node (ref "C72") (pin "1") (pinfunction "1_1") (pintype "passive"))
      (node (ref "C73") (pin "1") (pinfunction "1_1") (pintype "passive"))
      (node (ref "C74") (pin "1") (pinfunction "1_1") (pintype "passive"))
      (node (ref "C75") (pin "1") (pinfunction "1_1") (pintype "passive"))
      (node (ref "C76") (pin "1") (pinfunction "1_1") (pintype "passive"))
      (node (ref "C77") (pin "1") (pinfunction "1_1") (pintype "passive"))
      (node (ref "C78") (pin "1") (pinfunction "1_1") (pintype "passive"))
      (node (ref "C79") (pin "1") (pinfunction "1_1") (pintype "passive"))
      (node (ref "D10") (pin "A") (pinfunction "A_A") (pintype "passive"))
      (node (ref "D100") (pin "A") (pinfunction "A_A") (pintype "passive"))
      (node (ref "D1000") (pin "A") (pinfunction "A_A") (pintype "passive"))
      (node (ref "D1001") (pin "A") (pinfunction "A_A") (pintype "passive"))
      (node (ref "D1002") (pin "A") (pinfunction "A_A") (pintype "passive"))
      (node (ref "D1003") (pin "A") (pinfunction "A_A") (pintype "passive"))
      (node (ref "D1004") (pin "A") (pinfunction "A_A") (pintype "passive"))
      (node (ref "D1005") (pin "A") (pinfunction "A_A") (pintype "passive"))
      (node (ref "D1006") (pin "A") (pinfunction "A_A") (pintype "passive"))
      (node (ref "D1007") (pin "A") (pinfunction "A_A") (pintype "passive"))
      (node (ref "D1008") (pin "A") (pinfunction "A_A") (pintype "passive"))
      (node (ref "D1009") (pin "A") (pinfunction "A_A") (pintype "passive"))
      (node (ref "D101") (pin "A") (pinfunction "A_A") (pintype "passive"))
      (node (ref "D1010") (pin "A") (pinfunction "A_A") (pintype "passive"))
      (node (ref "D1011") (pin "A") (pinfunction "A_A") (pintype "passive"))
      (node (ref "D1012") (pin "A") (pinfunction "A_A") (pintype "passive"))
      (node (ref "D1013") (pin "A") (pinfunction "A_A") (pintype "passive"))
      (node (ref "D1014") (pin "A") (pinfunction "A_A") (pintype "passive"))
      (node (ref "D1015") (pin "A") (pinfunction "A_A") (pintype "passive"))
      (node (ref "D1016") (pin "A") (pinfunction "A_A") (pintype "passive"))
      (node (ref "D1017") (pin "A") (pinfunction "A_A") (pintype "passive"))
      (node (ref "D1018") (pin "A") (pinfunction "A_A") (pintype "passive"))
      (node (ref "D1019") (pin "A") (pinfunction "A_A") (pintype "passive"))
      (node (ref "D102") (pin "A") (pinfunction "A_A") (pintype "passive"))
      (node (ref "D1020") (pin "A") (pinfunction "A_A") (pintype "passive"))
      (node (ref "D1021") (pin "A") (pinfunction "A_A") (pintype "passive"))
      (node (ref "D1022") (pin "A") (pinfunction "A_A") (pintype "passive"))
      (node (ref "D1023") (pin "A") (pinfunction "A_A") (pintype "passive"))
      (node (ref "D1024") (pin "A") (pinfunction "A_A") (pintype "passive"))
      (node (ref "D1025") (pin "A") (pinfunction "A_A") (pintype "passive"))
      (node (ref "D1026") (pin "A") (pinfunction "A_A") (pintype "passive"))
      (node (ref "D1027") (pin "A") (pinfunction "A_A") (pintype "passive"))
      (node (ref "D1028") (pin "A") (pinfunction "A_A") (pintype "passive"))
      (node (ref "D103") (pin "A") (pinfunction "A_A") (pintype "passive"))
      (node (ref "D104") (pin "A") (pinfunction "A_A") (pintype "passive"))
      (node (ref "D105") (pin "A") (pinfunction "A_A") (pintype "passive"))
      (node (ref "D106") (pin "A") (pinfunction "A_A") (pintype "passive"))
      (node (ref "D107") (pin "A") (pinfunction "A_A") (pintype "passive"))
      (node (ref "D108") (pin "A") (pinfunction "A_A") (pintype "passive"))
      (node (ref "D109") (pin "A") (pinfunction "A_A") (pintype "passive"))
      (node (ref "D11") (pin "A") (pinfunction "A_A") (pintype "passive"))
      (node (ref "D110") (pin "A") (pinfunction "A_A") (pintype "passive"))
      (node (ref "D111") (pin "A") (pinfunction "A_A") (pintype "passive"))
      (node (ref "D112") (pin "A") (pinfunction "A_A") (pintype "passive"))
      (node (ref "D113") (pin "A") (pinfunction "A_A") (pintype "passive"))
      (node (ref "D114") (pin "A") (pinfunction "A_A") (pintype "passive"))
      (node (ref "D115") (pin "A") (pinfunction "A_A") (pintype "passive"))
      (node (ref "D116") (pin "A") (pinfunction "A_A") (pintype "passive"))
      (node (ref "D117") (pin "A") (pinfunction "A_A") (pintype "passive"))
      (node (ref "D118") (pin "A") (pinfunction "A_A") (pintype "passive"))
      (node (ref "D119") (pin "A") (pinfunction "A_A") (pintype "passive"))
      (node (ref "D12") (pin "A") (pinfunction "A_A") (pintype "passive"))
      (node (ref "D120") (pin "A") (pinfunction "A_A") (pintype "passive"))
      (node (ref "D121") (pin "A") (pinfunction "A_A") (pintype "passive"))
      (node (ref "D122") (pin "A") (pinfunction "A_A") (pintype "passive"))
      (node (ref "D123") (pin "A") (pinfunction "A_A") (pintype "passive"))
      (node (ref "D124") (pin "A") (pinfunction "A_A") (pintype "passive"))
      (node (ref "D125") (pin "A") (pinfunction "A_A") (pintype "passive"))
      (node (ref "D126") (pin "A") (pinfunction "A_A") (pintype "passive"))
      (node (ref "D127") (pin "A") (pinfunction "A_A") (pintype "passive"))
      (node (ref "D128") (pin "A") (pinfunction "A_A") (pintype "passive"))
      (node (ref "D129") (pin "A") (pinfunction "A_A") (pintype "passive"))
      (node (ref "D13") (pin "A") (pinfunction "A_A") (pintype "passive"))
      (node (ref "D130") (pin "A") (pinfunction "A_A") (pintype "passive"))
      (node (ref "D131") (pin "A") (pinfunction "A_A") (pintype "passive"))
      (node (ref "D132") (pin "A") (pinfunction "A_A") (pintype "passive"))
      (node (ref "D133") (pin "A") (pinfunction "A_A") (pintype "passive"))
      (node (ref "D134") (pin "A") (pinfunction "A_A") (pintype "passive"))
      (node (ref "D135") (pin "A") (pinfunction "A_A") (pintype "passive"))
      (node (ref "D136") (pin "A") (pinfunction "A_A") (pintype "passive"))
      (node (ref "D137") (pin "A") (pinfunction "A_A") (pintype "passive"))
      (node (ref "D138") (pin "A") (pinfunction "A_A") (pintype "passive"))
      (node (ref "D139") (pin "A") (pinfunction "A_A") (pintype "passive"))
      (node (ref "D14") (pin "A") (pinfunction "A_A") (pintype "passive"))
      (node (ref "D140") (pin "A") (pinfunction "A_A") (pintype "passive"))
      (node (ref "D141") (pin "A") (pinfunction "A_A") (pintype "passive"))
      (node (ref "D142") (pin "A") (pinfunction "A_A") (pintype "passive"))
      (node (ref "D143") (pin "A") (pinfunction "A_A") (pintype "passive"))
      (node (ref "D144") (pin "A") (pinfunction "A_A") (pintype "passive"))
      (node (ref "D145") (pin "A") (pinfunction "A_A") (pintype "passive"))
      (node (ref "D146") (pin "A") (pinfunction "A_A") (pintype "passive"))
      (node (ref "D147") (pin "A") (pinfunction "A_A") (pintype "passive"))
      (node (ref "D148") (pin "A") (pinfunction "A_A") (pintype "passive"))
      (node (ref "D149") (pin "A") (pinfunction "A_A") (pintype "passive"))
      (node (ref "D15") (pin "A") (pinfunction "A_A") (pintype "passive"))
      (node (ref "D150") (pin "A") (pinfunction "A_A") (pintype "passive"))
      (node (ref "D151") (pin "A") (pinfunction "A_A") (pintype "passive"))
      (node (ref "D152") (pin "A") (pinfunction "A_A") (pintype "passive"))
      (node (ref "D153") (pin "A") (pinfunction "A_A") (pintype "passive"))
      (node (ref "D154") (pin "A") (pinfunction "A_A") (pintype "passive"))
      (node (ref "D155") (pin "A") (pinfunction "A_A") (pintype "passive"))
      (node (ref "D156") (pin "A") (pinfunction "A_A") (pintype "passive"))
      (node (ref "D157") (pin "A") (pinfunction "A_A") (pintype "passive"))
      (node (ref "D158") (pin "A") (pinfunction "A_A") (pintype "passive"))
      (node (ref "D159") (pin "A") (pinfunction "A_A") (pintype "passive"))
      (node (ref "D16") (pin "A") (pinfunction "A_A") (pintype "passive"))
      (node (ref "D160") (pin "A") (pinfunction "A_A") (pintype "passive"))
      (node (ref "D161") (pin "A") (pinfunction "A_A") (pintype "passive"))
      (node (ref "D162") (pin "A") (pinfunction "A_A") (pintype "passive"))
      (node (ref "D163") (pin "A") (pinfunction "A_A") (pintype "passive"))
      (node (ref "D164") (pin "A") (pinfunction "A_A") (pintype "passive"))
      (node (ref "D165") (pin "A") (pinfunction "A_A") (pintype "passive"))
      (node (ref "D166") (pin "A") (pinfunction "A_A") (pintype "passive"))
      (node (ref "D167") (pin "A") (pinfunction "A_A") (pintype "passive"))
      (node (ref "D168") (pin "A") (pinfunction "A_A") (pintype "passive"))
      (node (ref "D169") (pin "A") (pinfunction "A_A") (pintype "passive"))
      (node (ref "D17") (pin "A") (pinfunction "A_A") (pintype "passive"))
      (node (ref "D170") (pin "A") (pinfunction "A_A") (pintype "passive"))
      (node (ref "D171") (pin "A") (pinfunction "A_A") (pintype "passive"))
      (node (ref "D172") (pin "A") (pinfunction "A_A") (pintype "passive"))
      (node (ref "D173") (pin "A") (pinfunction "A_A") (pintype "passive"))
      (node (ref "D174") (pin "A") (pinfunction "A_A") (pintype "passive"))
      (node (ref "D175") (pin "A") (pinfunction "A_A") (pintype "passive"))
      (node (ref "D176") (pin "A") (pinfunction "A_A") (pintype "passive"))
      (node (ref "D177") (pin "A") (pinfunction "A_A") (pintype "passive"))
      (node (ref "D178") (pin "A") (pinfunction "A_A") (pintype "passive"))
      (node (ref "D179") (pin "A") (pinfunction "A_A") (pintype "passive"))
      (node (ref "D18") (pin "A") (pinfunction "A_A") (pintype "passive"))
      (node (ref "D180") (pin "A") (pinfunction "A_A") (pintype "passive"))
      (node (ref "D181") (pin "A") (pinfunction "A_A") (pintype "passive"))
      (node (ref "D182") (pin "A") (pinfunction "A_A") (pintype "passive"))
      (node (ref "D183") (pin "A") (pinfunction "A_A") (pintype "passive"))
      (node (ref "D184") (pin "A") (pinfunction "A_A") (pintype "passive"))
      (node (ref "D185") (pin "A") (pinfunction "A_A") (pintype "passive"))
      (node (ref "D186") (pin "A") (pinfunction "A_A") (pintype "passive"))
      (node (ref "D187") (pin "A") (pinfunction "A_A") (pintype "passive"))
      (node (ref "D188") (pin "A") (pinfunction "A_A") (pintype "passive"))
      (node (ref "D189") (pin "A") (pinfunction "A_A") (pintype "passive"))
      (node (ref "D19") (pin "A") (pinfunction "A_A") (pintype "passive"))
      (node (ref "D190") (pin "A") (pinfunction "A_A") (pintype "passive"))
      (node (ref "D191") (pin "A") (pinfunction "A_A") (pintype "passive"))
      (node (ref "D192") (pin "A") (pinfunction "A_A") (pintype "passive"))
      (node (ref "D193") (pin "A") (pinfunction "A_A") (pintype "passive"))
      (node (ref "D194") (pin "A") (pinfunction "A_A") (pintype "passive"))
      (node (ref "D195") (pin "A") (pinfunction "A_A") (pintype "passive"))
      (node (ref "D196") (pin "A") (pinfunction "A_A") (pintype "passive"))
      (node (ref "D197") (pin "A") (pinfunction "A_A") (pintype "passive"))
      (node (ref "D198") (pin "A") (pinfunction "A_A") (pintype "passive"))
      (node (ref "D199") (pin "A") (pinfunction "A_A") (pintype "passive"))
      (node (ref "D20") (pin "A") (pinfunction "A_A") (pintype "passive"))
      (node (ref "D200") (pin "A") (pinfunction "A_A") (pintype "passive"))
      (node (ref "D201") (pin "A") (pinfunction "A_A") (pintype "passive"))
      (node (ref "D202") (pin "A") (pinfunction "A_A") (pintype "passive"))
      (node (ref "D203") (pin "A") (pinfunction "A_A") (pintype "passive"))
      (node (ref "D204") (pin "A") (pinfunction "A_A") (pintype "passive"))
      (node (ref "D205") (pin "A") (pinfunction "A_A") (pintype "passive"))
      (node (ref "D206") (pin "A") (pinfunction "A_A") (pintype "passive"))
      (node (ref "D207") (pin "A") (pinfunction "A_A") (pintype "passive"))
      (node (ref "D208") (pin "A") (pinfunction "A_A") (pintype "passive"))
      (node (ref "D209") (pin "A") (pinfunction "A_A") (pintype "passive"))
      (node (ref "D21") (pin "A") (pinfunction "A_A") (pintype "passive"))
      (node (ref "D210") (pin "A") (pinfunction "A_A") (pintype "passive"))
      (node (ref "D211") (pin "A") (pinfunction "A_A") (pintype "passive"))
      (node (ref "D212") (pin "A") (pinfunction "A_A") (pintype "passive"))
      (node (ref "D213") (pin "A") (pinfunction "A_A") (pintype "passive"))
      (node (ref "D214") (pin "A") (pinfunction "A_A") (pintype "passive"))
      (node (ref "D215") (pin "A") (pinfunction "A_A") (pintype "passive"))
      (node (ref "D216") (pin "A") (pinfunction "A_A") (pintype "passive"))
      (node (ref "D217") (pin "A") (pinfunction "A_A") (pintype "passive"))
      (node (ref "D218") (pin "A") (pinfunction "A_A") (pintype "passive"))
      (node (ref "D219") (pin "A") (pinfunction "A_A") (pintype "passive"))
      (node (ref "D22") (pin "A") (pinfunction "A_A") (pintype "passive"))
      (node (ref "D220") (pin "A") (pinfunction "A_A") (pintype "passive"))
      (node (ref "D221") (pin "A") (pinfunction "A_A") (pintype "passive"))
      (node (ref "D222") (pin "A") (pinfunction "A_A") (pintype "passive"))
      (node (ref "D223") (pin "A") (pinfunction "A_A") (pintype "passive"))
      (node (ref "D224") (pin "A") (pinfunction "A_A") (pintype "passive"))
      (node (ref "D225") (pin "A") (pinfunction "A_A") (pintype "passive"))
      (node (ref "D226") (pin "A") (pinfunction "A_A") (pintype "passive"))
      (node (ref "D227") (pin "A") (pinfunction "A_A") (pintype "passive"))
      (node (ref "D228") (pin "A") (pinfunction "A_A") (pintype "passive"))
      (node (ref "D229") (pin "A") (pinfunction "A_A") (pintype "passive"))
      (node (ref "D23") (pin "A") (pinfunction "A_A") (pintype "passive"))
      (node (ref "D230") (pin "A") (pinfunction "A_A") (pintype "passive"))
      (node (ref "D231") (pin "A") (pinfunction "A_A") (pintype "passive"))
      (node (ref "D232") (pin "A") (pinfunction "A_A") (pintype "passive"))
      (node (ref "D233") (pin "A") (pinfunction "A_A") (pintype "passive"))
      (node (ref "D234") (pin "A") (pinfunction "A_A") (pintype "passive"))
      (node (ref "D235") (pin "A") (pinfunction "A_A") (pintype "passive"))
      (node (ref "D236") (pin "A") (pinfunction "A_A") (pintype "passive"))
      (node (ref "D237") (pin "A") (pinfunction "A_A") (pintype "passive"))
      (node (ref "D238") (pin "A") (pinfunction "A_A") (pintype "passive"))
      (node (ref "D239") (pin "A") (pinfunction "A_A") (pintype "passive"))
      (node (ref "D24") (pin "A") (pinfunction "A_A") (pintype "passive"))
      (node (ref "D240") (pin "A") (pinfunction "A_A") (pintype "passive"))
      (node (ref "D241") (pin "A") (pinfunction "A_A") (pintype "passive"))
      (node (ref "D242") (pin "A") (pinfunction "A_A") (pintype "passive"))
      (node (ref "D243") (pin "A") (pinfunction "A_A") (pintype "passive"))
      (node (ref "D244") (pin "A") (pinfunction "A_A") (pintype "passive"))
      (node (ref "D245") (pin "A") (pinfunction "A_A") (pintype "passive"))
      (node (ref "D246") (pin "A") (pinfunction "A_A") (pintype "passive"))
      (node (ref "D247") (pin "A") (pinfunction "A_A") (pintype "passive"))
      (node (ref "D248") (pin "A") (pinfunction "A_A") (pintype "passive"))
      (node (ref "D249") (pin "A") (pinfunction "A_A") (pintype "passive"))
      (node (ref "D25") (pin "A") (pinfunction "A_A") (pintype "passive"))
      (node (ref "D250") (pin "A") (pinfunction "A_A") (pintype "passive"))
      (node (ref "D251") (pin "A") (pinfunction "A_A") (pintype "passive"))
      (node (ref "D252") (pin "A") (pinfunction "A_A") (pintype "passive"))
      (node (ref "D253") (pin "A") (pinfunction "A_A") (pintype "passive"))
      (node (ref "D254") (pin "A") (pinfunction "A_A") (pintype "passive"))
      (node (ref "D255") (pin "A") (pinfunction "A_A") (pintype "passive"))
      (node (ref "D256") (pin "A") (pinfunction "A_A") (pintype "passive"))
      (node (ref "D257") (pin "A") (pinfunction "A_A") (pintype "passive"))
      (node (ref "D258") (pin "A") (pinfunction "A_A") (pintype "passive"))
      (node (ref "D259") (pin "A") (pinfunction "A_A") (pintype "passive"))
      (node (ref "D26") (pin "A") (pinfunction "A_A") (pintype "passive"))
      (node (ref "D260") (pin "A") (pinfunction "A_A") (pintype "passive"))
      (node (ref "D261") (pin "A") (pinfunction "A_A") (pintype "passive"))
      (node (ref "D262") (pin "A") (pinfunction "A_A") (pintype "passive"))
      (node (ref "D263") (pin "A") (pinfunction "A_A") (pintype "passive"))
      (node (ref "D264") (pin "A") (pinfunction "A_A") (pintype "passive"))
      (node (ref "D265") (pin "A") (pinfunction "A_A") (pintype "passive"))
      (node (ref "D266") (pin "A") (pinfunction "A_A") (pintype "passive"))
      (node (ref "D267") (pin "A") (pinfunction "A_A") (pintype "passive"))
      (node (ref "D268") (pin "A") (pinfunction "A_A") (pintype "passive"))
      (node (ref "D269") (pin "A") (pinfunction "A_A") (pintype "passive"))
      (node (ref "D27") (pin "A") (pinfunction "A_A") (pintype "passive"))
      (node (ref "D270") (pin "A") (pinfunction "A_A") (pintype "passive"))
      (node (ref "D271") (pin "A") (pinfunction "A_A") (pintype "passive"))
      (node (ref "D272") (pin "A") (pinfunction "A_A") (pintype "passive"))
      (node (ref "D273") (pin "A") (pinfunction "A_A") (pintype "passive"))
      (node (ref "D274") (pin "A") (pinfunction "A_A") (pintype "passive"))
      (node (ref "D275") (pin "A") (pinfunction "A_A") (pintype "passive"))
      (node (ref "D276") (pin "A") (pinfunction "A_A") (pintype "passive"))
      (node (ref "D277") (pin "A") (pinfunction "A_A") (pintype "passive"))
      (node (ref "D278") (pin "A") (pinfunction "A_A") (pintype "passive"))
      (node (ref "D279") (pin "A") (pinfunction "A_A") (pintype "passive"))
      (node (ref "D28") (pin "A") (pinfunction "A_A") (pintype "passive"))
      (node (ref "D280") (pin "A") (pinfunction "A_A") (pintype "passive"))
      (node (ref "D281") (pin "A") (pinfunction "A_A") (pintype "passive"))
      (node (ref "D282") (pin "A") (pinfunction "A_A") (pintype "passive"))
      (node (ref "D283") (pin "A") (pinfunction "A_A") (pintype "passive"))
      (node (ref "D284") (pin "A") (pinfunction "A_A") (pintype "passive"))
      (node (ref "D285") (pin "A") (pinfunction "A_A") (pintype "passive"))
      (node (ref "D286") (pin "A") (pinfunction "A_A") (pintype "passive"))
      (node (ref "D287") (pin "A") (pinfunction "A_A") (pintype "passive"))
      (node (ref "D288") (pin "A") (pinfunction "A_A") (pintype "passive"))
      (node (ref "D289") (pin "A") (pinfunction "A_A") (pintype "passive"))
      (node (ref "D29") (pin "A") (pinfunction "A_A") (pintype "passive"))
      (node (ref "D290") (pin "A") (pinfunction "A_A") (pintype "passive"))
      (node (ref "D291") (pin "A") (pinfunction "A_A") (pintype "passive"))
      (node (ref "D292") (pin "A") (pinfunction "A_A") (pintype "passive"))
      (node (ref "D293") (pin "A") (pinfunction "A_A") (pintype "passive"))
      (node (ref "D294") (pin "A") (pinfunction "A_A") (pintype "passive"))
      (node (ref "D295") (pin "A") (pinfunction "A_A") (pintype "passive"))
      (node (ref "D296") (pin "A") (pinfunction "A_A") (pintype "passive"))
      (node (ref "D297") (pin "A") (pinfunction "A_A") (pintype "passive"))
      (node (ref "D298") (pin "A") (pinfunction "A_A") (pintype "passive"))
      (node (ref "D299") (pin "A") (pinfunction "A_A") (pintype "passive"))
      (node (ref "D30") (pin "A") (pinfunction "A_A") (pintype "passive"))
      (node (ref "D300") (pin "A") (pinfunction "A_A") (pintype "passive"))
      (node (ref "D301") (pin "A") (pinfunction "A_A") (pintype "passive"))
      (node (ref "D302") (pin "A") (pinfunction "A_A") (pintype "passive"))
      (node (ref "D303") (pin "A") (pinfunction "A_A") (pintype "passive"))
      (node (ref "D304") (pin "A") (pinfunction "A_A") (pintype "passive"))
      (node (ref "D305") (pin "A") (pinfunction "A_A") (pintype "passive"))
      (node (ref "D306") (pin "A") (pinfunction "A_A") (pintype "passive"))
      (node (ref "D307") (pin "A") (pinfunction "A_A") (pintype "passive"))
      (node (ref "D308") (pin "A") (pinfunction "A_A") (pintype "passive"))
      (node (ref "D309") (pin "A") (pinfunction "A_A") (pintype "passive"))
      (node (ref "D31") (pin "A") (pinfunction "A_A") (pintype "passive"))
      (node (ref "D310") (pin "A") (pinfunction "A_A") (pintype "passive"))
      (node (ref "D311") (pin "A") (pinfunction "A_A") (pintype "passive"))
      (node (ref "D312") (pin "A") (pinfunction "A_A") (pintype "passive"))
      (node (ref "D313") (pin "A") (pinfunction "A_A") (pintype "passive"))
      (node (ref "D314") (pin "A") (pinfunction "A_A") (pintype "passive"))
      (node (ref "D315") (pin "A") (pinfunction "A_A") (pintype "passive"))
      (node (ref "D316") (pin "A") (pinfunction "A_A") (pintype "passive"))
      (node (ref "D317") (pin "A") (pinfunction "A_A") (pintype "passive"))
      (node (ref "D318") (pin "A") (pinfunction "A_A") (pintype "passive"))
      (node (ref "D319") (pin "A") (pinfunction "A_A") (pintype "passive"))
      (node (ref "D32") (pin "A") (pinfunction "A_A") (pintype "passive"))
      (node (ref "D320") (pin "A") (pinfunction "A_A") (pintype "passive"))
      (node (ref "D321") (pin "A") (pinfunction "A_A") (pintype "passive"))
      (node (ref "D322") (pin "A") (pinfunction "A_A") (pintype "passive"))
      (node (ref "D323") (pin "A") (pinfunction "A_A") (pintype "passive"))
      (node (ref "D324") (pin "A") (pinfunction "A_A") (pintype "passive"))
      (node (ref "D325") (pin "A") (pinfunction "A_A") (pintype "passive"))
      (node (ref "D326") (pin "A") (pinfunction "A_A") (pintype "passive"))
      (node (ref "D327") (pin "A") (pinfunction "A_A") (pintype "passive"))
      (node (ref "D328") (pin "A") (pinfunction "A_A") (pintype "passive"))
      (node (ref "D329") (pin "A") (pinfunction "A_A") (pintype "passive"))
      (node (ref "D33") (pin "A") (pinfunction "A_A") (pintype "passive"))
      (node (ref "D330") (pin "A") (pinfunction "A_A") (pintype "passive"))
      (node (ref "D331") (pin "A") (pinfunction "A_A") (pintype "passive"))
      (node (ref "D332") (pin "A") (pinfunction "A_A") (pintype "passive"))
      (node (ref "D333") (pin "A") (pinfunction "A_A") (pintype "passive"))
      (node (ref "D334") (pin "A") (pinfunction "A_A") (pintype "passive"))
      (node (ref "D335") (pin "A") (pinfunction "A_A") (pintype "passive"))
      (node (ref "D336") (pin "A") (pinfunction "A_A") (pintype "passive"))
      (node (ref "D337") (pin "A") (pinfunction "A_A") (pintype "passive"))
      (node (ref "D338") (pin "A") (pinfunction "A_A") (pintype "passive"))
      (node (ref "D339") (pin "A") (pinfunction "A_A") (pintype "passive"))
      (node (ref "D34") (pin "A") (pinfunction "A_A") (pintype "passive"))
      (node (ref "D340") (pin "A") (pinfunction "A_A") (pintype "passive"))
      (node (ref "D341") (pin "A") (pinfunction "A_A") (pintype "passive"))
      (node (ref "D342") (pin "A") (pinfunction "A_A") (pintype "passive"))
      (node (ref "D343") (pin "A") (pinfunction "A_A") (pintype "passive"))
      (node (ref "D344") (pin "A") (pinfunction "A_A") (pintype "passive"))
      (node (ref "D345") (pin "A") (pinfunction "A_A") (pintype "passive"))
      (node (ref "D346") (pin "A") (pinfunction "A_A") (pintype "passive"))
      (node (ref "D347") (pin "A") (pinfunction "A_A") (pintype "passive"))
      (node (ref "D348") (pin "A") (pinfunction "A_A") (pintype "passive"))
      (node (ref "D349") (pin "A") (pinfunction "A_A") (pintype "passive"))
      (node (ref "D35") (pin "A") (pinfunction "A_A") (pintype "passive"))
      (node (ref "D350") (pin "A") (pinfunction "A_A") (pintype "passive"))
      (node (ref "D351") (pin "A") (pinfunction "A_A") (pintype "passive"))
      (node (ref "D352") (pin "A") (pinfunction "A_A") (pintype "passive"))
      (node (ref "D353") (pin "A") (pinfunction "A_A") (pintype "passive"))
      (node (ref "D354") (pin "A") (pinfunction "A_A") (pintype "passive"))
      (node (ref "D355") (pin "A") (pinfunction "A_A") (pintype "passive"))
      (node (ref "D356") (pin "A") (pinfunction "A_A") (pintype "passive"))
      (node (ref "D357") (pin "A") (pinfunction "A_A") (pintype "passive"))
      (node (ref "D358") (pin "A") (pinfunction "A_A") (pintype "passive"))
      (node (ref "D359") (pin "A") (pinfunction "A_A") (pintype "passive"))
      (node (ref "D36") (pin "A") (pinfunction "A_A") (pintype "passive"))
      (node (ref "D360") (pin "A") (pinfunction "A_A") (pintype "passive"))
      (node (ref "D361") (pin "A") (pinfunction "A_A") (pintype "passive"))
      (node (ref "D362") (pin "A") (pinfunction "A_A") (pintype "passive"))
      (node (ref "D363") (pin "A") (pinfunction "A_A") (pintype "passive"))
      (node (ref "D364") (pin "A") (pinfunction "A_A") (pintype "passive"))
      (node (ref "D365") (pin "A") (pinfunction "A_A") (pintype "passive"))
      (node (ref "D366") (pin "A") (pinfunction "A_A") (pintype "passive"))
      (node (ref "D367") (pin "A") (pinfunction "A_A") (pintype "passive"))
      (node (ref "D368") (pin "A") (pinfunction "A_A") (pintype "passive"))
      (node (ref "D369") (pin "A") (pinfunction "A_A") (pintype "passive"))
      (node (ref "D37") (pin "A") (pinfunction "A_A") (pintype "passive"))
      (node (ref "D370") (pin "A") (pinfunction "A_A") (pintype "passive"))
      (node (ref "D371") (pin "A") (pinfunction "A_A") (pintype "passive"))
      (node (ref "D372") (pin "A") (pinfunction "A_A") (pintype "passive"))
      (node (ref "D373") (pin "A") (pinfunction "A_A") (pintype "passive"))
      (node (ref "D374") (pin "A") (pinfunction "A_A") (pintype "passive"))
      (node (ref "D375") (pin "A") (pinfunction "A_A") (pintype "passive"))
      (node (ref "D376") (pin "A") (pinfunction "A_A") (pintype "passive"))
      (node (ref "D377") (pin "A") (pinfunction "A_A") (pintype "passive"))
      (node (ref "D378") (pin "A") (pinfunction "A_A") (pintype "passive"))
      (node (ref "D379") (pin "A") (pinfunction "A_A") (pintype "passive"))
      (node (ref "D38") (pin "A") (pinfunction "A_A") (pintype "passive"))
      (node (ref "D380") (pin "A") (pinfunction "A_A") (pintype "passive"))
      (node (ref "D381") (pin "A") (pinfunction "A_A") (pintype "passive"))
      (node (ref "D382") (pin "A") (pinfunction "A_A") (pintype "passive"))
      (node (ref "D383") (pin "A") (pinfunction "A_A") (pintype "passive"))
      (node (ref "D384") (pin "A") (pinfunction "A_A") (pintype "passive"))
      (node (ref "D385") (pin "A") (pinfunction "A_A") (pintype "passive"))
      (node (ref "D386") (pin "A") (pinfunction "A_A") (pintype "passive"))
      (node (ref "D387") (pin "A") (pinfunction "A_A") (pintype "passive"))
      (node (ref "D388") (pin "A") (pinfunction "A_A") (pintype "passive"))
      (node (ref "D389") (pin "A") (pinfunction "A_A") (pintype "passive"))
      (node (ref "D39") (pin "A") (pinfunction "A_A") (pintype "passive"))
      (node (ref "D390") (pin "A") (pinfunction "A_A") (pintype "passive"))
      (node (ref "D391") (pin "A") (pinfunction "A_A") (pintype "passive"))
      (node (ref "D392") (pin "A") (pinfunction "A_A") (pintype "passive"))
      (node (ref "D393") (pin "A") (pinfunction "A_A") (pintype "passive"))
      (node (ref "D394") (pin "A") (pinfunction "A_A") (pintype "passive"))
      (node (ref "D395") (pin "A") (pinfunction "A_A") (pintype "passive"))
      (node (ref "D396") (pin "A") (pinfunction "A_A") (pintype "passive"))
      (node (ref "D397") (pin "A") (pinfunction "A_A") (pintype "passive"))
      (node (ref "D398") (pin "A") (pinfunction "A_A") (pintype "passive"))
      (node (ref "D399") (pin "A") (pinfunction "A_A") (pintype "passive"))
      (node (ref "D4") (pin "A") (pinfunction "A_A") (pintype "passive"))
      (node (ref "D40") (pin "A") (pinfunction "A_A") (pintype "passive"))
      (node (ref "D400") (pin "A") (pinfunction "A_A") (pintype "passive"))
      (node (ref "D401") (pin "A") (pinfunction "A_A") (pintype "passive"))
      (node (ref "D402") (pin "A") (pinfunction "A_A") (pintype "passive"))
      (node (ref "D403") (pin "A") (pinfunction "A_A") (pintype "passive"))
      (node (ref "D404") (pin "A") (pinfunction "A_A") (pintype "passive"))
      (node (ref "D405") (pin "A") (pinfunction "A_A") (pintype "passive"))
      (node (ref "D406") (pin "A") (pinfunction "A_A") (pintype "passive"))
      (node (ref "D407") (pin "A") (pinfunction "A_A") (pintype "passive"))
      (node (ref "D408") (pin "A") (pinfunction "A_A") (pintype "passive"))
      (node (ref "D409") (pin "A") (pinfunction "A_A") (pintype "passive"))
      (node (ref "D41") (pin "A") (pinfunction "A_A") (pintype "passive"))
      (node (ref "D410") (pin "A") (pinfunction "A_A") (pintype "passive"))
      (node (ref "D411") (pin "A") (pinfunction "A_A") (pintype "passive"))
      (node (ref "D412") (pin "A") (pinfunction "A_A") (pintype "passive"))
      (node (ref "D413") (pin "A") (pinfunction "A_A") (pintype "passive"))
      (node (ref "D414") (pin "A") (pinfunction "A_A") (pintype "passive"))
      (node (ref "D415") (pin "A") (pinfunction "A_A") (pintype "passive"))
      (node (ref "D416") (pin "A") (pinfunction "A_A") (pintype "passive"))
      (node (ref "D417") (pin "A") (pinfunction "A_A") (pintype "passive"))
      (node (ref "D418") (pin "A") (pinfunction "A_A") (pintype "passive"))
      (node (ref "D419") (pin "A") (pinfunction "A_A") (pintype "passive"))
      (node (ref "D42") (pin "A") (pinfunction "A_A") (pintype "passive"))
      (node (ref "D420") (pin "A") (pinfunction "A_A") (pintype "passive"))
      (node (ref "D421") (pin "A") (pinfunction "A_A") (pintype "passive"))
      (node (ref "D422") (pin "A") (pinfunction "A_A") (pintype "passive"))
      (node (ref "D423") (pin "A") (pinfunction "A_A") (pintype "passive"))
      (node (ref "D424") (pin "A") (pinfunction "A_A") (pintype "passive"))
      (node (ref "D425") (pin "A") (pinfunction "A_A") (pintype "passive"))
      (node (ref "D426") (pin "A") (pinfunction "A_A") (pintype "passive"))
      (node (ref "D427") (pin "A") (pinfunction "A_A") (pintype "passive"))
      (node (ref "D428") (pin "A") (pinfunction "A_A") (pintype "passive"))
      (node (ref "D429") (pin "A") (pinfunction "A_A") (pintype "passive"))
      (node (ref "D43") (pin "A") (pinfunction "A_A") (pintype "passive"))
      (node (ref "D430") (pin "A") (pinfunction "A_A") (pintype "passive"))
      (node (ref "D431") (pin "A") (pinfunction "A_A") (pintype "passive"))
      (node (ref "D432") (pin "A") (pinfunction "A_A") (pintype "passive"))
      (node (ref "D433") (pin "A") (pinfunction "A_A") (pintype "passive"))
      (node (ref "D434") (pin "A") (pinfunction "A_A") (pintype "passive"))
      (node (ref "D435") (pin "A") (pinfunction "A_A") (pintype "passive"))
      (node (ref "D436") (pin "A") (pinfunction "A_A") (pintype "passive"))
      (node (ref "D437") (pin "A") (pinfunction "A_A") (pintype "passive"))
      (node (ref "D438") (pin "A") (pinfunction "A_A") (pintype "passive"))
      (node (ref "D439") (pin "A") (pinfunction "A_A") (pintype "passive"))
      (node (ref "D44") (pin "A") (pinfunction "A_A") (pintype "passive"))
      (node (ref "D440") (pin "A") (pinfunction "A_A") (pintype "passive"))
      (node (ref "D441") (pin "A") (pinfunction "A_A") (pintype "passive"))
      (node (ref "D442") (pin "A") (pinfunction "A_A") (pintype "passive"))
      (node (ref "D443") (pin "A") (pinfunction "A_A") (pintype "passive"))
      (node (ref "D444") (pin "A") (pinfunction "A_A") (pintype "passive"))
      (node (ref "D445") (pin "A") (pinfunction "A_A") (pintype "passive"))
      (node (ref "D446") (pin "A") (pinfunction "A_A") (pintype "passive"))
      (node (ref "D447") (pin "A") (pinfunction "A_A") (pintype "passive"))
      (node (ref "D448") (pin "A") (pinfunction "A_A") (pintype "passive"))
      (node (ref "D449") (pin "A") (pinfunction "A_A") (pintype "passive"))
      (node (ref "D45") (pin "A") (pinfunction "A_A") (pintype "passive"))
      (node (ref "D450") (pin "A") (pinfunction "A_A") (pintype "passive"))
      (node (ref "D451") (pin "A") (pinfunction "A_A") (pintype "passive"))
      (node (ref "D452") (pin "A") (pinfunction "A_A") (pintype "passive"))
      (node (ref "D453") (pin "A") (pinfunction "A_A") (pintype "passive"))
      (node (ref "D454") (pin "A") (pinfunction "A_A") (pintype "passive"))
      (node (ref "D455") (pin "A") (pinfunction "A_A") (pintype "passive"))
      (node (ref "D456") (pin "A") (pinfunction "A_A") (pintype "passive"))
      (node (ref "D457") (pin "A") (pinfunction "A_A") (pintype "passive"))
      (node (ref "D458") (pin "A") (pinfunction "A_A") (pintype "passive"))
      (node (ref "D459") (pin "A") (pinfunction "A_A") (pintype "passive"))
      (node (ref "D46") (pin "A") (pinfunction "A_A") (pintype "passive"))
      (node (ref "D460") (pin "A") (pinfunction "A_A") (pintype "passive"))
      (node (ref "D461") (pin "A") (pinfunction "A_A") (pintype "passive"))
      (node (ref "D462") (pin "A") (pinfunction "A_A") (pintype "passive"))
      (node (ref "D463") (pin "A") (pinfunction "A_A") (pintype "passive"))
      (node (ref "D464") (pin "A") (pinfunction "A_A") (pintype "passive"))
      (node (ref "D465") (pin "A") (pinfunction "A_A") (pintype "passive"))
      (node (ref "D466") (pin "A") (pinfunction "A_A") (pintype "passive"))
      (node (ref "D467") (pin "A") (pinfunction "A_A") (pintype "passive"))
      (node (ref "D468") (pin "A") (pinfunction "A_A") (pintype "passive"))
      (node (ref "D469") (pin "A") (pinfunction "A_A") (pintype "passive"))
      (node (ref "D47") (pin "A") (pinfunction "A_A") (pintype "passive"))
      (node (ref "D470") (pin "A") (pinfunction "A_A") (pintype "passive"))
      (node (ref "D471") (pin "A") (pinfunction "A_A") (pintype "passive"))
      (node (ref "D472") (pin "A") (pinfunction "A_A") (pintype "passive"))
      (node (ref "D473") (pin "A") (pinfunction "A_A") (pintype "passive"))
      (node (ref "D474") (pin "A") (pinfunction "A_A") (pintype "passive"))
      (node (ref "D475") (pin "A") (pinfunction "A_A") (pintype "passive"))
      (node (ref "D476") (pin "A") (pinfunction "A_A") (pintype "passive"))
      (node (ref "D477") (pin "A") (pinfunction "A_A") (pintype "passive"))
      (node (ref "D478") (pin "A") (pinfunction "A_A") (pintype "passive"))
      (node (ref "D479") (pin "A") (pinfunction "A_A") (pintype "passive"))
      (node (ref "D48") (pin "A") (pinfunction "A_A") (pintype "passive"))
      (node (ref "D480") (pin "A") (pinfunction "A_A") (pintype "passive"))
      (node (ref "D481") (pin "A") (pinfunction "A_A") (pintype "passive"))
      (node (ref "D482") (pin "A") (pinfunction "A_A") (pintype "passive"))
      (node (ref "D483") (pin "A") (pinfunction "A_A") (pintype "passive"))
      (node (ref "D484") (pin "A") (pinfunction "A_A") (pintype "passive"))
      (node (ref "D485") (pin "A") (pinfunction "A_A") (pintype "passive"))
      (node (ref "D486") (pin "A") (pinfunction "A_A") (pintype "passive"))
      (node (ref "D487") (pin "A") (pinfunction "A_A") (pintype "passive"))
      (node (ref "D488") (pin "A") (pinfunction "A_A") (pintype "passive"))
      (node (ref "D489") (pin "A") (pinfunction "A_A") (pintype "passive"))
      (node (ref "D49") (pin "A") (pinfunction "A_A") (pintype "passive"))
      (node (ref "D490") (pin "A") (pinfunction "A_A") (pintype "passive"))
      (node (ref "D491") (pin "A") (pinfunction "A_A") (pintype "passive"))
      (node (ref "D492") (pin "A") (pinfunction "A_A") (pintype "passive"))
      (node (ref "D493") (pin "A") (pinfunction "A_A") (pintype "passive"))
      (node (ref "D494") (pin "A") (pinfunction "A_A") (pintype "passive"))
      (node (ref "D495") (pin "A") (pinfunction "A_A") (pintype "passive"))
      (node (ref "D496") (pin "A") (pinfunction "A_A") (pintype "passive"))
      (node (ref "D497") (pin "A") (pinfunction "A_A") (pintype "passive"))
      (node (ref "D498") (pin "A") (pinfunction "A_A") (pintype "passive"))
      (node (ref "D499") (pin "A") (pinfunction "A_A") (pintype "passive"))
      (node (ref "D5") (pin "A") (pinfunction "A_A") (pintype "passive"))
      (node (ref "D50") (pin "A") (pinfunction "A_A") (pintype "passive"))
      (node (ref "D500") (pin "A") (pinfunction "A_A") (pintype "passive"))
      (node (ref "D501") (pin "A") (pinfunction "A_A") (pintype "passive"))
      (node (ref "D502") (pin "A") (pinfunction "A_A") (pintype "passive"))
      (node (ref "D503") (pin "A") (pinfunction "A_A") (pintype "passive"))
      (node (ref "D504") (pin "A") (pinfunction "A_A") (pintype "passive"))
      (node (ref "D505") (pin "A") (pinfunction "A_A") (pintype "passive"))
      (node (ref "D506") (pin "A") (pinfunction "A_A") (pintype "passive"))
      (node (ref "D507") (pin "A") (pinfunction "A_A") (pintype "passive"))
      (node (ref "D508") (pin "A") (pinfunction "A_A") (pintype "passive"))
      (node (ref "D509") (pin "A") (pinfunction "A_A") (pintype "passive"))
      (node (ref "D51") (pin "A") (pinfunction "A_A") (pintype "passive"))
      (node (ref "D510") (pin "A") (pinfunction "A_A") (pintype "passive"))
      (node (ref "D511") (pin "A") (pinfunction "A_A") (pintype "passive"))
      (node (ref "D512") (pin "A") (pinfunction "A_A") (pintype "passive"))
      (node (ref "D513") (pin "A") (pinfunction "A_A") (pintype "passive"))
      (node (ref "D514") (pin "A") (pinfunction "A_A") (pintype "passive"))
      (node (ref "D515") (pin "A") (pinfunction "A_A") (pintype "passive"))
      (node (ref "D516") (pin "A") (pinfunction "A_A") (pintype "passive"))
      (node (ref "D517") (pin "A") (pinfunction "A_A") (pintype "passive"))
      (node (ref "D518") (pin "A") (pinfunction "A_A") (pintype "passive"))
      (node (ref "D519") (pin "A") (pinfunction "A_A") (pintype "passive"))
      (node (ref "D52") (pin "A") (pinfunction "A_A") (pintype "passive"))
      (node (ref "D520") (pin "A") (pinfunction "A_A") (pintype "passive"))
      (node (ref "D521") (pin "A") (pinfunction "A_A") (pintype "passive"))
      (node (ref "D522") (pin "A") (pinfunction "A_A") (pintype "passive"))
      (node (ref "D523") (pin "A") (pinfunction "A_A") (pintype "passive"))
      (node (ref "D524") (pin "A") (pinfunction "A_A") (pintype "passive"))
      (node (ref "D525") (pin "A") (pinfunction "A_A") (pintype "passive"))
      (node (ref "D526") (pin "A") (pinfunction "A_A") (pintype "passive"))
      (node (ref "D527") (pin "A") (pinfunction "A_A") (pintype "passive"))
      (node (ref "D528") (pin "A") (pinfunction "A_A") (pintype "passive"))
      (node (ref "D529") (pin "A") (pinfunction "A_A") (pintype "passive"))
      (node (ref "D53") (pin "A") (pinfunction "A_A") (pintype "passive"))
      (node (ref "D530") (pin "A") (pinfunction "A_A") (pintype "passive"))
      (node (ref "D531") (pin "A") (pinfunction "A_A") (pintype "passive"))
      (node (ref "D532") (pin "A") (pinfunction "A_A") (pintype "passive"))
      (node (ref "D533") (pin "A") (pinfunction "A_A") (pintype "passive"))
      (node (ref "D534") (pin "A") (pinfunction "A_A") (pintype "passive"))
      (node (ref "D535") (pin "A") (pinfunction "A_A") (pintype "passive"))
      (node (ref "D536") (pin "A") (pinfunction "A_A") (pintype "passive"))
      (node (ref "D537") (pin "A") (pinfunction "A_A") (pintype "passive"))
      (node (ref "D538") (pin "A") (pinfunction "A_A") (pintype "passive"))
      (node (ref "D539") (pin "A") (pinfunction "A_A") (pintype "passive"))
      (node (ref "D54") (pin "A") (pinfunction "A_A") (pintype "passive"))
      (node (ref "D540") (pin "A") (pinfunction "A_A") (pintype "passive"))
      (node (ref "D541") (pin "A") (pinfunction "A_A") (pintype "passive"))
      (node (ref "D542") (pin "A") (pinfunction "A_A") (pintype "passive"))
      (node (ref "D543") (pin "A") (pinfunction "A_A") (pintype "passive"))
      (node (ref "D544") (pin "A") (pinfunction "A_A") (pintype "passive"))
      (node (ref "D545") (pin "A") (pinfunction "A_A") (pintype "passive"))
      (node (ref "D546") (pin "A") (pinfunction "A_A") (pintype "passive"))
      (node (ref "D547") (pin "A") (pinfunction "A_A") (pintype "passive"))
      (node (ref "D548") (pin "A") (pinfunction "A_A") (pintype "passive"))
      (node (ref "D549") (pin "A") (pinfunction "A_A") (pintype "passive"))
      (node (ref "D55") (pin "A") (pinfunction "A_A") (pintype "passive"))
      (node (ref "D550") (pin "A") (pinfunction "A_A") (pintype "passive"))
      (node (ref "D551") (pin "A") (pinfunction "A_A") (pintype "passive"))
      (node (ref "D552") (pin "A") (pinfunction "A_A") (pintype "passive"))
      (node (ref "D553") (pin "A") (pinfunction "A_A") (pintype "passive"))
      (node (ref "D554") (pin "A") (pinfunction "A_A") (pintype "passive"))
      (node (ref "D555") (pin "A") (pinfunction "A_A") (pintype "passive"))
      (node (ref "D556") (pin "A") (pinfunction "A_A") (pintype "passive"))
      (node (ref "D557") (pin "A") (pinfunction "A_A") (pintype "passive"))
      (node (ref "D558") (pin "A") (pinfunction "A_A") (pintype "passive"))
      (node (ref "D559") (pin "A") (pinfunction "A_A") (pintype "passive"))
      (node (ref "D56") (pin "A") (pinfunction "A_A") (pintype "passive"))
      (node (ref "D560") (pin "A") (pinfunction "A_A") (pintype "passive"))
      (node (ref "D561") (pin "A") (pinfunction "A_A") (pintype "passive"))
      (node (ref "D562") (pin "A") (pinfunction "A_A") (pintype "passive"))
      (node (ref "D563") (pin "A") (pinfunction "A_A") (pintype "passive"))
      (node (ref "D564") (pin "A") (pinfunction "A_A") (pintype "passive"))
      (node (ref "D565") (pin "A") (pinfunction "A_A") (pintype "passive"))
      (node (ref "D566") (pin "A") (pinfunction "A_A") (pintype "passive"))
      (node (ref "D567") (pin "A") (pinfunction "A_A") (pintype "passive"))
      (node (ref "D568") (pin "A") (pinfunction "A_A") (pintype "passive"))
      (node (ref "D569") (pin "A") (pinfunction "A_A") (pintype "passive"))
      (node (ref "D57") (pin "A") (pinfunction "A_A") (pintype "passive"))
      (node (ref "D570") (pin "A") (pinfunction "A_A") (pintype "passive"))
      (node (ref "D571") (pin "A") (pinfunction "A_A") (pintype "passive"))
      (node (ref "D572") (pin "A") (pinfunction "A_A") (pintype "passive"))
      (node (ref "D573") (pin "A") (pinfunction "A_A") (pintype "passive"))
      (node (ref "D574") (pin "A") (pinfunction "A_A") (pintype "passive"))
      (node (ref "D575") (pin "A") (pinfunction "A_A") (pintype "passive"))
      (node (ref "D576") (pin "A") (pinfunction "A_A") (pintype "passive"))
      (node (ref "D577") (pin "A") (pinfunction "A_A") (pintype "passive"))
      (node (ref "D578") (pin "A") (pinfunction "A_A") (pintype "passive"))
      (node (ref "D579") (pin "A") (pinfunction "A_A") (pintype "passive"))
      (node (ref "D58") (pin "A") (pinfunction "A_A") (pintype "passive"))
      (node (ref "D580") (pin "A") (pinfunction "A_A") (pintype "passive"))
      (node (ref "D581") (pin "A") (pinfunction "A_A") (pintype "passive"))
      (node (ref "D582") (pin "A") (pinfunction "A_A") (pintype "passive"))
      (node (ref "D583") (pin "A") (pinfunction "A_A") (pintype "passive"))
      (node (ref "D584") (pin "A") (pinfunction "A_A") (pintype "passive"))
      (node (ref "D585") (pin "A") (pinfunction "A_A") (pintype "passive"))
      (node (ref "D586") (pin "A") (pinfunction "A_A") (pintype "passive"))
      (node (ref "D587") (pin "A") (pinfunction "A_A") (pintype "passive"))
      (node (ref "D588") (pin "A") (pinfunction "A_A") (pintype "passive"))
      (node (ref "D589") (pin "A") (pinfunction "A_A") (pintype "passive"))
      (node (ref "D59") (pin "A") (pinfunction "A_A") (pintype "passive"))
      (node (ref "D590") (pin "A") (pinfunction "A_A") (pintype "passive"))
      (node (ref "D591") (pin "A") (pinfunction "A_A") (pintype "passive"))
      (node (ref "D592") (pin "A") (pinfunction "A_A") (pintype "passive"))
      (node (ref "D593") (pin "A") (pinfunction "A_A") (pintype "passive"))
      (node (ref "D594") (pin "A") (pinfunction "A_A") (pintype "passive"))
      (node (ref "D595") (pin "A") (pinfunction "A_A") (pintype "passive"))
      (node (ref "D596") (pin "A") (pinfunction "A_A") (pintype "passive"))
      (node (ref "D597") (pin "A") (pinfunction "A_A") (pintype "passive"))
      (node (ref "D598") (pin "A") (pinfunction "A_A") (pintype "passive"))
      (node (ref "D599") (pin "A") (pinfunction "A_A") (pintype "passive"))
      (node (ref "D6") (pin "A") (pinfunction "A_A") (pintype "passive"))
      (node (ref "D60") (pin "A") (pinfunction "A_A") (pintype "passive"))
      (node (ref "D600") (pin "A") (pinfunction "A_A") (pintype "passive"))
      (node (ref "D601") (pin "A") (pinfunction "A_A") (pintype "passive"))
      (node (ref "D602") (pin "A") (pinfunction "A_A") (pintype "passive"))
      (node (ref "D603") (pin "A") (pinfunction "A_A") (pintype "passive"))
      (node (ref "D604") (pin "A") (pinfunction "A_A") (pintype "passive"))
      (node (ref "D605") (pin "A") (pinfunction "A_A") (pintype "passive"))
      (node (ref "D606") (pin "A") (pinfunction "A_A") (pintype "passive"))
      (node (ref "D607") (pin "A") (pinfunction "A_A") (pintype "passive"))
      (node (ref "D608") (pin "A") (pinfunction "A_A") (pintype "passive"))
      (node (ref "D609") (pin "A") (pinfunction "A_A") (pintype "passive"))
      (node (ref "D61") (pin "A") (pinfunction "A_A") (pintype "passive"))
      (node (ref "D610") (pin "A") (pinfunction "A_A") (pintype "passive"))
      (node (ref "D611") (pin "A") (pinfunction "A_A") (pintype "passive"))
      (node (ref "D612") (pin "A") (pinfunction "A_A") (pintype "passive"))
      (node (ref "D613") (pin "A") (pinfunction "A_A") (pintype "passive"))
      (node (ref "D614") (pin "A") (pinfunction "A_A") (pintype "passive"))
      (node (ref "D615") (pin "A") (pinfunction "A_A") (pintype "passive"))
      (node (ref "D616") (pin "A") (pinfunction "A_A") (pintype "passive"))
      (node (ref "D617") (pin "A") (pinfunction "A_A") (pintype "passive"))
      (node (ref "D618") (pin "A") (pinfunction "A_A") (pintype "passive"))
      (node (ref "D619") (pin "A") (pinfunction "A_A") (pintype "passive"))
      (node (ref "D62") (pin "A") (pinfunction "A_A") (pintype "passive"))
      (node (ref "D620") (pin "A") (pinfunction "A_A") (pintype "passive"))
      (node (ref "D621") (pin "A") (pinfunction "A_A") (pintype "passive"))
      (node (ref "D622") (pin "A") (pinfunction "A_A") (pintype "passive"))
      (node (ref "D623") (pin "A") (pinfunction "A_A") (pintype "passive"))
      (node (ref "D624") (pin "A") (pinfunction "A_A") (pintype "passive"))
      (node (ref "D625") (pin "A") (pinfunction "A_A") (pintype "passive"))
      (node (ref "D626") (pin "A") (pinfunction "A_A") (pintype "passive"))
      (node (ref "D627") (pin "A") (pinfunction "A_A") (pintype "passive"))
      (node (ref "D628") (pin "A") (pinfunction "A_A") (pintype "passive"))
      (node (ref "D629") (pin "A") (pinfunction "A_A") (pintype "passive"))
      (node (ref "D63") (pin "A") (pinfunction "A_A") (pintype "passive"))
      (node (ref "D630") (pin "A") (pinfunction "A_A") (pintype "passive"))
      (node (ref "D631") (pin "A") (pinfunction "A_A") (pintype "passive"))
      (node (ref "D632") (pin "A") (pinfunction "A_A") (pintype "passive"))
      (node (ref "D633") (pin "A") (pinfunction "A_A") (pintype "passive"))
      (node (ref "D634") (pin "A") (pinfunction "A_A") (pintype "passive"))
      (node (ref "D635") (pin "A") (pinfunction "A_A") (pintype "passive"))
      (node (ref "D636") (pin "A") (pinfunction "A_A") (pintype "passive"))
      (node (ref "D637") (pin "A") (pinfunction "A_A") (pintype "passive"))
      (node (ref "D638") (pin "A") (pinfunction "A_A") (pintype "passive"))
      (node (ref "D639") (pin "A") (pinfunction "A_A") (pintype "passive"))
      (node (ref "D64") (pin "A") (pinfunction "A_A") (pintype "passive"))
      (node (ref "D640") (pin "A") (pinfunction "A_A") (pintype "passive"))
      (node (ref "D641") (pin "A") (pinfunction "A_A") (pintype "passive"))
      (node (ref "D642") (pin "A") (pinfunction "A_A") (pintype "passive"))
      (node (ref "D643") (pin "A") (pinfunction "A_A") (pintype "passive"))
      (node (ref "D644") (pin "A") (pinfunction "A_A") (pintype "passive"))
      (node (ref "D645") (pin "A") (pinfunction "A_A") (pintype "passive"))
      (node (ref "D646") (pin "A") (pinfunction "A_A") (pintype "passive"))
      (node (ref "D647") (pin "A") (pinfunction "A_A") (pintype "passive"))
      (node (ref "D648") (pin "A") (pinfunction "A_A") (pintype "passive"))
      (node (ref "D649") (pin "A") (pinfunction "A_A") (pintype "passive"))
      (node (ref "D65") (pin "A") (pinfunction "A_A") (pintype "passive"))
      (node (ref "D650") (pin "A") (pinfunction "A_A") (pintype "passive"))
      (node (ref "D651") (pin "A") (pinfunction "A_A") (pintype "passive"))
      (node (ref "D652") (pin "A") (pinfunction "A_A") (pintype "passive"))
      (node (ref "D653") (pin "A") (pinfunction "A_A") (pintype "passive"))
      (node (ref "D654") (pin "A") (pinfunction "A_A") (pintype "passive"))
      (node (ref "D655") (pin "A") (pinfunction "A_A") (pintype "passive"))
      (node (ref "D656") (pin "A") (pinfunction "A_A") (pintype "passive"))
      (node (ref "D657") (pin "A") (pinfunction "A_A") (pintype "passive"))
      (node (ref "D658") (pin "A") (pinfunction "A_A") (pintype "passive"))
      (node (ref "D659") (pin "A") (pinfunction "A_A") (pintype "passive"))
      (node (ref "D66") (pin "A") (pinfunction "A_A") (pintype "passive"))
      (node (ref "D660") (pin "A") (pinfunction "A_A") (pintype "passive"))
      (node (ref "D661") (pin "A") (pinfunction "A_A") (pintype "passive"))
      (node (ref "D662") (pin "A") (pinfunction "A_A") (pintype "passive"))
      (node (ref "D663") (pin "A") (pinfunction "A_A") (pintype "passive"))
      (node (ref "D664") (pin "A") (pinfunction "A_A") (pintype "passive"))
      (node (ref "D665") (pin "A") (pinfunction "A_A") (pintype "passive"))
      (node (ref "D666") (pin "A") (pinfunction "A_A") (pintype "passive"))
      (node (ref "D667") (pin "A") (pinfunction "A_A") (pintype "passive"))
      (node (ref "D668") (pin "A") (pinfunction "A_A") (pintype "passive"))
      (node (ref "D669") (pin "A") (pinfunction "A_A") (pintype "passive"))
      (node (ref "D67") (pin "A") (pinfunction "A_A") (pintype "passive"))
      (node (ref "D670") (pin "A") (pinfunction "A_A") (pintype "passive"))
      (node (ref "D671") (pin "A") (pinfunction "A_A") (pintype "passive"))
      (node (ref "D672") (pin "A") (pinfunction "A_A") (pintype "passive"))
      (node (ref "D673") (pin "A") (pinfunction "A_A") (pintype "passive"))
      (node (ref "D674") (pin "A") (pinfunction "A_A") (pintype "passive"))
      (node (ref "D675") (pin "A") (pinfunction "A_A") (pintype "passive"))
      (node (ref "D676") (pin "A") (pinfunction "A_A") (pintype "passive"))
      (node (ref "D677") (pin "A") (pinfunction "A_A") (pintype "passive"))
      (node (ref "D678") (pin "A") (pinfunction "A_A") (pintype "passive"))
      (node (ref "D679") (pin "A") (pinfunction "A_A") (pintype "passive"))
      (node (ref "D68") (pin "A") (pinfunction "A_A") (pintype "passive"))
      (node (ref "D680") (pin "A") (pinfunction "A_A") (pintype "passive"))
      (node (ref "D681") (pin "A") (pinfunction "A_A") (pintype "passive"))
      (node (ref "D682") (pin "A") (pinfunction "A_A") (pintype "passive"))
      (node (ref "D683") (pin "A") (pinfunction "A_A") (pintype "passive"))
      (node (ref "D684") (pin "A") (pinfunction "A_A") (pintype "passive"))
      (node (ref "D685") (pin "A") (pinfunction "A_A") (pintype "passive"))
      (node (ref "D686") (pin "A") (pinfunction "A_A") (pintype "passive"))
      (node (ref "D687") (pin "A") (pinfunction "A_A") (pintype "passive"))
      (node (ref "D688") (pin "A") (pinfunction "A_A") (pintype "passive"))
      (node (ref "D689") (pin "A") (pinfunction "A_A") (pintype "passive"))
      (node (ref "D69") (pin "A") (pinfunction "A_A") (pintype "passive"))
      (node (ref "D690") (pin "A") (pinfunction "A_A") (pintype "passive"))
      (node (ref "D691") (pin "A") (pinfunction "A_A") (pintype "passive"))
      (node (ref "D692") (pin "A") (pinfunction "A_A") (pintype "passive"))
      (node (ref "D693") (pin "A") (pinfunction "A_A") (pintype "passive"))
      (node (ref "D694") (pin "A") (pinfunction "A_A") (pintype "passive"))
      (node (ref "D695") (pin "A") (pinfunction "A_A") (pintype "passive"))
      (node (ref "D696") (pin "A") (pinfunction "A_A") (pintype "passive"))
      (node (ref "D697") (pin "A") (pinfunction "A_A") (pintype "passive"))
      (node (ref "D698") (pin "A") (pinfunction "A_A") (pintype "passive"))
      (node (ref "D699") (pin "A") (pinfunction "A_A") (pintype "passive"))
      (node (ref "D7") (pin "A") (pinfunction "A_A") (pintype "passive"))
      (node (ref "D70") (pin "A") (pinfunction "A_A") (pintype "passive"))
      (node (ref "D700") (pin "A") (pinfunction "A_A") (pintype "passive"))
      (node (ref "D701") (pin "A") (pinfunction "A_A") (pintype "passive"))
      (node (ref "D702") (pin "A") (pinfunction "A_A") (pintype "passive"))
      (node (ref "D703") (pin "A") (pinfunction "A_A") (pintype "passive"))
      (node (ref "D704") (pin "A") (pinfunction "A_A") (pintype "passive"))
      (node (ref "D705") (pin "A") (pinfunction "A_A") (pintype "passive"))
      (node (ref "D706") (pin "A") (pinfunction "A_A") (pintype "passive"))
      (node (ref "D707") (pin "A") (pinfunction "A_A") (pintype "passive"))
      (node (ref "D708") (pin "A") (pinfunction "A_A") (pintype "passive"))
      (node (ref "D709") (pin "A") (pinfunction "A_A") (pintype "passive"))
      (node (ref "D71") (pin "A") (pinfunction "A_A") (pintype "passive"))
      (node (ref "D710") (pin "A") (pinfunction "A_A") (pintype "passive"))
      (node (ref "D711") (pin "A") (pinfunction "A_A") (pintype "passive"))
      (node (ref "D712") (pin "A") (pinfunction "A_A") (pintype "passive"))
      (node (ref "D713") (pin "A") (pinfunction "A_A") (pintype "passive"))
      (node (ref "D714") (pin "A") (pinfunction "A_A") (pintype "passive"))
      (node (ref "D715") (pin "A") (pinfunction "A_A") (pintype "passive"))
      (node (ref "D716") (pin "A") (pinfunction "A_A") (pintype "passive"))
      (node (ref "D717") (pin "A") (pinfunction "A_A") (pintype "passive"))
      (node (ref "D718") (pin "A") (pinfunction "A_A") (pintype "passive"))
      (node (ref "D719") (pin "A") (pinfunction "A_A") (pintype "passive"))
      (node (ref "D72") (pin "A") (pinfunction "A_A") (pintype "passive"))
      (node (ref "D720") (pin "A") (pinfunction "A_A") (pintype "passive"))
      (node (ref "D721") (pin "A") (pinfunction "A_A") (pintype "passive"))
      (node (ref "D722") (pin "A") (pinfunction "A_A") (pintype "passive"))
      (node (ref "D723") (pin "A") (pinfunction "A_A") (pintype "passive"))
      (node (ref "D724") (pin "A") (pinfunction "A_A") (pintype "passive"))
      (node (ref "D725") (pin "A") (pinfunction "A_A") (pintype "passive"))
      (node (ref "D726") (pin "A") (pinfunction "A_A") (pintype "passive"))
      (node (ref "D727") (pin "A") (pinfunction "A_A") (pintype "passive"))
      (node (ref "D728") (pin "A") (pinfunction "A_A") (pintype "passive"))
      (node (ref "D729") (pin "A") (pinfunction "A_A") (pintype "passive"))
      (node (ref "D73") (pin "A") (pinfunction "A_A") (pintype "passive"))
      (node (ref "D730") (pin "A") (pinfunction "A_A") (pintype "passive"))
      (node (ref "D731") (pin "A") (pinfunction "A_A") (pintype "passive"))
      (node (ref "D732") (pin "A") (pinfunction "A_A") (pintype "passive"))
      (node (ref "D733") (pin "A") (pinfunction "A_A") (pintype "passive"))
      (node (ref "D734") (pin "A") (pinfunction "A_A") (pintype "passive"))
      (node (ref "D735") (pin "A") (pinfunction "A_A") (pintype "passive"))
      (node (ref "D736") (pin "A") (pinfunction "A_A") (pintype "passive"))
      (node (ref "D737") (pin "A") (pinfunction "A_A") (pintype "passive"))
      (node (ref "D738") (pin "A") (pinfunction "A_A") (pintype "passive"))
      (node (ref "D739") (pin "A") (pinfunction "A_A") (pintype "passive"))
      (node (ref "D74") (pin "A") (pinfunction "A_A") (pintype "passive"))
      (node (ref "D740") (pin "A") (pinfunction "A_A") (pintype "passive"))
      (node (ref "D741") (pin "A") (pinfunction "A_A") (pintype "passive"))
      (node (ref "D742") (pin "A") (pinfunction "A_A") (pintype "passive"))
      (node (ref "D743") (pin "A") (pinfunction "A_A") (pintype "passive"))
      (node (ref "D744") (pin "A") (pinfunction "A_A") (pintype "passive"))
      (node (ref "D745") (pin "A") (pinfunction "A_A") (pintype "passive"))
      (node (ref "D746") (pin "A") (pinfunction "A_A") (pintype "passive"))
      (node (ref "D747") (pin "A") (pinfunction "A_A") (pintype "passive"))
      (node (ref "D748") (pin "A") (pinfunction "A_A") (pintype "passive"))
      (node (ref "D749") (pin "A") (pinfunction "A_A") (pintype "passive"))
      (node (ref "D75") (pin "A") (pinfunction "A_A") (pintype "passive"))
      (node (ref "D750") (pin "A") (pinfunction "A_A") (pintype "passive"))
      (node (ref "D751") (pin "A") (pinfunction "A_A") (pintype "passive"))
      (node (ref "D752") (pin "A") (pinfunction "A_A") (pintype "passive"))
      (node (ref "D753") (pin "A") (pinfunction "A_A") (pintype "passive"))
      (node (ref "D754") (pin "A") (pinfunction "A_A") (pintype "passive"))
      (node (ref "D755") (pin "A") (pinfunction "A_A") (pintype "passive"))
      (node (ref "D756") (pin "A") (pinfunction "A_A") (pintype "passive"))
      (node (ref "D757") (pin "A") (pinfunction "A_A") (pintype "passive"))
      (node (ref "D758") (pin "A") (pinfunction "A_A") (pintype "passive"))
      (node (ref "D759") (pin "A") (pinfunction "A_A") (pintype "passive"))
      (node (ref "D76") (pin "A") (pinfunction "A_A") (pintype "passive"))
      (node (ref "D760") (pin "A") (pinfunction "A_A") (pintype "passive"))
      (node (ref "D761") (pin "A") (pinfunction "A_A") (pintype "passive"))
      (node (ref "D762") (pin "A") (pinfunction "A_A") (pintype "passive"))
      (node (ref "D763") (pin "A") (pinfunction "A_A") (pintype "passive"))
      (node (ref "D764") (pin "A") (pinfunction "A_A") (pintype "passive"))
      (node (ref "D765") (pin "A") (pinfunction "A_A") (pintype "passive"))
      (node (ref "D766") (pin "A") (pinfunction "A_A") (pintype "passive"))
      (node (ref "D767") (pin "A") (pinfunction "A_A") (pintype "passive"))
      (node (ref "D768") (pin "A") (pinfunction "A_A") (pintype "passive"))
      (node (ref "D769") (pin "A") (pinfunction "A_A") (pintype "passive"))
      (node (ref "D77") (pin "A") (pinfunction "A_A") (pintype "passive"))
      (node (ref "D770") (pin "A") (pinfunction "A_A") (pintype "passive"))
      (node (ref "D771") (pin "A") (pinfunction "A_A") (pintype "passive"))
      (node (ref "D772") (pin "A") (pinfunction "A_A") (pintype "passive"))
      (node (ref "D773") (pin "A") (pinfunction "A_A") (pintype "passive"))
      (node (ref "D774") (pin "A") (pinfunction "A_A") (pintype "passive"))
      (node (ref "D775") (pin "A") (pinfunction "A_A") (pintype "passive"))
      (node (ref "D776") (pin "A") (pinfunction "A_A") (pintype "passive"))
      (node (ref "D777") (pin "A") (pinfunction "A_A") (pintype "passive"))
      (node (ref "D778") (pin "A") (pinfunction "A_A") (pintype "passive"))
      (node (ref "D779") (pin "A") (pinfunction "A_A") (pintype "passive"))
      (node (ref "D78") (pin "A") (pinfunction "A_A") (pintype "passive"))
      (node (ref "D780") (pin "A") (pinfunction "A_A") (pintype "passive"))
      (node (ref "D781") (pin "A") (pinfunction "A_A") (pintype "passive"))
      (node (ref "D782") (pin "A") (pinfunction "A_A") (pintype "passive"))
      (node (ref "D783") (pin "A") (pinfunction "A_A") (pintype "passive"))
      (node (ref "D784") (pin "A") (pinfunction "A_A") (pintype "passive"))
      (node (ref "D785") (pin "A") (pinfunction "A_A") (pintype "passive"))
      (node (ref "D786") (pin "A") (pinfunction "A_A") (pintype "passive"))
      (node (ref "D787") (pin "A") (pinfunction "A_A") (pintype "passive"))
      (node (ref "D788") (pin "A") (pinfunction "A_A") (pintype "passive"))
      (node (ref "D789") (pin "A") (pinfunction "A_A") (pintype "passive"))
      (node (ref "D79") (pin "A") (pinfunction "A_A") (pintype "passive"))
      (node (ref "D790") (pin "A") (pinfunction "A_A") (pintype "passive"))
      (node (ref "D791") (pin "A") (pinfunction "A_A") (pintype "passive"))
      (node (ref "D792") (pin "A") (pinfunction "A_A") (pintype "passive"))
      (node (ref "D793") (pin "A") (pinfunction "A_A") (pintype "passive"))
      (node (ref "D794") (pin "A") (pinfunction "A_A") (pintype "passive"))
      (node (ref "D795") (pin "A") (pinfunction "A_A") (pintype "passive"))
      (node (ref "D796") (pin "A") (pinfunction "A_A") (pintype "passive"))
      (node (ref "D797") (pin "A") (pinfunction "A_A") (pintype "passive"))
      (node (ref "D798") (pin "A") (pinfunction "A_A") (pintype "passive"))
      (node (ref "D799") (pin "A") (pinfunction "A_A") (pintype "passive"))
      (node (ref "D8") (pin "A") (pinfunction "A_A") (pintype "passive"))
      (node (ref "D80") (pin "A") (pinfunction "A_A") (pintype "passive"))
      (node (ref "D800") (pin "A") (pinfunction "A_A") (pintype "passive"))
      (node (ref "D801") (pin "A") (pinfunction "A_A") (pintype "passive"))
      (node (ref "D802") (pin "A") (pinfunction "A_A") (pintype "passive"))
      (node (ref "D803") (pin "A") (pinfunction "A_A") (pintype "passive"))
      (node (ref "D804") (pin "A") (pinfunction "A_A") (pintype "passive"))
      (node (ref "D805") (pin "A") (pinfunction "A_A") (pintype "passive"))
      (node (ref "D806") (pin "A") (pinfunction "A_A") (pintype "passive"))
      (node (ref "D807") (pin "A") (pinfunction "A_A") (pintype "passive"))
      (node (ref "D808") (pin "A") (pinfunction "A_A") (pintype "passive"))
      (node (ref "D809") (pin "A") (pinfunction "A_A") (pintype "passive"))
      (node (ref "D81") (pin "A") (pinfunction "A_A") (pintype "passive"))
      (node (ref "D810") (pin "A") (pinfunction "A_A") (pintype "passive"))
      (node (ref "D811") (pin "A") (pinfunction "A_A") (pintype "passive"))
      (node (ref "D812") (pin "A") (pinfunction "A_A") (pintype "passive"))
      (node (ref "D813") (pin "A") (pinfunction "A_A") (pintype "passive"))
      (node (ref "D814") (pin "A") (pinfunction "A_A") (pintype "passive"))
      (node (ref "D815") (pin "A") (pinfunction "A_A") (pintype "passive"))
      (node (ref "D816") (pin "A") (pinfunction "A_A") (pintype "passive"))
      (node (ref "D817") (pin "A") (pinfunction "A_A") (pintype "passive"))
      (node (ref "D818") (pin "A") (pinfunction "A_A") (pintype "passive"))
      (node (ref "D819") (pin "A") (pinfunction "A_A") (pintype "passive"))
      (node (ref "D82") (pin "A") (pinfunction "A_A") (pintype "passive"))
      (node (ref "D820") (pin "A") (pinfunction "A_A") (pintype "passive"))
      (node (ref "D821") (pin "A") (pinfunction "A_A") (pintype "passive"))
      (node (ref "D822") (pin "A") (pinfunction "A_A") (pintype "passive"))
      (node (ref "D823") (pin "A") (pinfunction "A_A") (pintype "passive"))
      (node (ref "D824") (pin "A") (pinfunction "A_A") (pintype "passive"))
      (node (ref "D825") (pin "A") (pinfunction "A_A") (pintype "passive"))
      (node (ref "D826") (pin "A") (pinfunction "A_A") (pintype "passive"))
      (node (ref "D827") (pin "A") (pinfunction "A_A") (pintype "passive"))
      (node (ref "D828") (pin "A") (pinfunction "A_A") (pintype "passive"))
      (node (ref "D829") (pin "A") (pinfunction "A_A") (pintype "passive"))
      (node (ref "D83") (pin "A") (pinfunction "A_A") (pintype "passive"))
      (node (ref "D830") (pin "A") (pinfunction "A_A") (pintype "passive"))
      (node (ref "D831") (pin "A") (pinfunction "A_A") (pintype "passive"))
      (node (ref "D832") (pin "A") (pinfunction "A_A") (pintype "passive"))
      (node (ref "D833") (pin "A") (pinfunction "A_A") (pintype "passive"))
      (node (ref "D834") (pin "A") (pinfunction "A_A") (pintype "passive"))
      (node (ref "D835") (pin "A") (pinfunction "A_A") (pintype "passive"))
      (node (ref "D836") (pin "A") (pinfunction "A_A") (pintype "passive"))
      (node (ref "D837") (pin "A") (pinfunction "A_A") (pintype "passive"))
      (node (ref "D838") (pin "A") (pinfunction "A_A") (pintype "passive"))
      (node (ref "D839") (pin "A") (pinfunction "A_A") (pintype "passive"))
      (node (ref "D84") (pin "A") (pinfunction "A_A") (pintype "passive"))
      (node (ref "D840") (pin "A") (pinfunction "A_A") (pintype "passive"))
      (node (ref "D841") (pin "A") (pinfunction "A_A") (pintype "passive"))
      (node (ref "D842") (pin "A") (pinfunction "A_A") (pintype "passive"))
      (node (ref "D843") (pin "A") (pinfunction "A_A") (pintype "passive"))
      (node (ref "D844") (pin "A") (pinfunction "A_A") (pintype "passive"))
      (node (ref "D845") (pin "A") (pinfunction "A_A") (pintype "passive"))
      (node (ref "D846") (pin "A") (pinfunction "A_A") (pintype "passive"))
      (node (ref "D847") (pin "A") (pinfunction "A_A") (pintype "passive"))
      (node (ref "D848") (pin "A") (pinfunction "A_A") (pintype "passive"))
      (node (ref "D849") (pin "A") (pinfunction "A_A") (pintype "passive"))
      (node (ref "D85") (pin "A") (pinfunction "A_A") (pintype "passive"))
      (node (ref "D850") (pin "A") (pinfunction "A_A") (pintype "passive"))
      (node (ref "D851") (pin "A") (pinfunction "A_A") (pintype "passive"))
      (node (ref "D852") (pin "A") (pinfunction "A_A") (pintype "passive"))
      (node (ref "D853") (pin "A") (pinfunction "A_A") (pintype "passive"))
      (node (ref "D854") (pin "A") (pinfunction "A_A") (pintype "passive"))
      (node (ref "D855") (pin "A") (pinfunction "A_A") (pintype "passive"))
      (node (ref "D856") (pin "A") (pinfunction "A_A") (pintype "passive"))
      (node (ref "D857") (pin "A") (pinfunction "A_A") (pintype "passive"))
      (node (ref "D858") (pin "A") (pinfunction "A_A") (pintype "passive"))
      (node (ref "D859") (pin "A") (pinfunction "A_A") (pintype "passive"))
      (node (ref "D86") (pin "A") (pinfunction "A_A") (pintype "passive"))
      (node (ref "D860") (pin "A") (pinfunction "A_A") (pintype "passive"))
      (node (ref "D861") (pin "A") (pinfunction "A_A") (pintype "passive"))
      (node (ref "D862") (pin "A") (pinfunction "A_A") (pintype "passive"))
      (node (ref "D863") (pin "A") (pinfunction "A_A") (pintype "passive"))
      (node (ref "D864") (pin "A") (pinfunction "A_A") (pintype "passive"))
      (node (ref "D865") (pin "A") (pinfunction "A_A") (pintype "passive"))
      (node (ref "D866") (pin "A") (pinfunction "A_A") (pintype "passive"))
      (node (ref "D867") (pin "A") (pinfunction "A_A") (pintype "passive"))
      (node (ref "D868") (pin "A") (pinfunction "A_A") (pintype "passive"))
      (node (ref "D869") (pin "A") (pinfunction "A_A") (pintype "passive"))
      (node (ref "D87") (pin "A") (pinfunction "A_A") (pintype "passive"))
      (node (ref "D870") (pin "A") (pinfunction "A_A") (pintype "passive"))
      (node (ref "D871") (pin "A") (pinfunction "A_A") (pintype "passive"))
      (node (ref "D872") (pin "A") (pinfunction "A_A") (pintype "passive"))
      (node (ref "D873") (pin "A") (pinfunction "A_A") (pintype "passive"))
      (node (ref "D874") (pin "A") (pinfunction "A_A") (pintype "passive"))
      (node (ref "D875") (pin "A") (pinfunction "A_A") (pintype "passive"))
      (node (ref "D876") (pin "A") (pinfunction "A_A") (pintype "passive"))
      (node (ref "D877") (pin "A") (pinfunction "A_A") (pintype "passive"))
      (node (ref "D878") (pin "A") (pinfunction "A_A") (pintype "passive"))
      (node (ref "D879") (pin "A") (pinfunction "A_A") (pintype "passive"))
      (node (ref "D88") (pin "A") (pinfunction "A_A") (pintype "passive"))
      (node (ref "D880") (pin "A") (pinfunction "A_A") (pintype "passive"))
      (node (ref "D881") (pin "A") (pinfunction "A_A") (pintype "passive"))
      (node (ref "D882") (pin "A") (pinfunction "A_A") (pintype "passive"))
      (node (ref "D883") (pin "A") (pinfunction "A_A") (pintype "passive"))
      (node (ref "D884") (pin "A") (pinfunction "A_A") (pintype "passive"))
      (node (ref "D885") (pin "A") (pinfunction "A_A") (pintype "passive"))
      (node (ref "D886") (pin "A") (pinfunction "A_A") (pintype "passive"))
      (node (ref "D887") (pin "A") (pinfunction "A_A") (pintype "passive"))
      (node (ref "D888") (pin "A") (pinfunction "A_A") (pintype "passive"))
      (node (ref "D889") (pin "A") (pinfunction "A_A") (pintype "passive"))
      (node (ref "D89") (pin "A") (pinfunction "A_A") (pintype "passive"))
      (node (ref "D890") (pin "A") (pinfunction "A_A") (pintype "passive"))
      (node (ref "D891") (pin "A") (pinfunction "A_A") (pintype "passive"))
      (node (ref "D892") (pin "A") (pinfunction "A_A") (pintype "passive"))
      (node (ref "D893") (pin "A") (pinfunction "A_A") (pintype "passive"))
      (node (ref "D894") (pin "A") (pinfunction "A_A") (pintype "passive"))
      (node (ref "D895") (pin "A") (pinfunction "A_A") (pintype "passive"))
      (node (ref "D896") (pin "A") (pinfunction "A_A") (pintype "passive"))
      (node (ref "D897") (pin "A") (pinfunction "A_A") (pintype "passive"))
      (node (ref "D898") (pin "A") (pinfunction "A_A") (pintype "passive"))
      (node (ref "D899") (pin "A") (pinfunction "A_A") (pintype "passive"))
      (node (ref "D9") (pin "A") (pinfunction "A_A") (pintype "passive"))
      (node (ref "D90") (pin "A") (pinfunction "A_A") (pintype "passive"))
      (node (ref "D900") (pin "A") (pinfunction "A_A") (pintype "passive"))
      (node (ref "D901") (pin "A") (pinfunction "A_A") (pintype "passive"))
      (node (ref "D902") (pin "A") (pinfunction "A_A") (pintype "passive"))
      (node (ref "D903") (pin "A") (pinfunction "A_A") (pintype "passive"))
      (node (ref "D904") (pin "A") (pinfunction "A_A") (pintype "passive"))
      (node (ref "D905") (pin "A") (pinfunction "A_A") (pintype "passive"))
      (node (ref "D906") (pin "A") (pinfunction "A_A") (pintype "passive"))
      (node (ref "D907") (pin "A") (pinfunction "A_A") (pintype "passive"))
      (node (ref "D908") (pin "A") (pinfunction "A_A") (pintype "passive"))
      (node (ref "D909") (pin "A") (pinfunction "A_A") (pintype "passive"))
      (node (ref "D91") (pin "A") (pinfunction "A_A") (pintype "passive"))
      (node (ref "D910") (pin "A") (pinfunction "A_A") (pintype "passive"))
      (node (ref "D911") (pin "A") (pinfunction "A_A") (pintype "passive"))
      (node (ref "D912") (pin "A") (pinfunction "A_A") (pintype "passive"))
      (node (ref "D913") (pin "A") (pinfunction "A_A") (pintype "passive"))
      (node (ref "D914") (pin "A") (pinfunction "A_A") (pintype "passive"))
      (node (ref "D915") (pin "A") (pinfunction "A_A") (pintype "passive"))
      (node (ref "D916") (pin "A") (pinfunction "A_A") (pintype "passive"))
      (node (ref "D917") (pin "A") (pinfunction "A_A") (pintype "passive"))
      (node (ref "D918") (pin "A") (pinfunction "A_A") (pintype "passive"))
      (node (ref "D919") (pin "A") (pinfunction "A_A") (pintype "passive"))
      (node (ref "D92") (pin "A") (pinfunction "A_A") (pintype "passive"))
      (node (ref "D920") (pin "A") (pinfunction "A_A") (pintype "passive"))
      (node (ref "D921") (pin "A") (pinfunction "A_A") (pintype "passive"))
      (node (ref "D922") (pin "A") (pinfunction "A_A") (pintype "passive"))
      (node (ref "D923") (pin "A") (pinfunction "A_A") (pintype "passive"))
      (node (ref "D924") (pin "A") (pinfunction "A_A") (pintype "passive"))
      (node (ref "D925") (pin "A") (pinfunction "A_A") (pintype "passive"))
      (node (ref "D926") (pin "A") (pinfunction "A_A") (pintype "passive"))
      (node (ref "D927") (pin "A") (pinfunction "A_A") (pintype "passive"))
      (node (ref "D928") (pin "A") (pinfunction "A_A") (pintype "passive"))
      (node (ref "D929") (pin "A") (pinfunction "A_A") (pintype "passive"))
      (node (ref "D93") (pin "A") (pinfunction "A_A") (pintype "passive"))
      (node (ref "D930") (pin "A") (pinfunction "A_A") (pintype "passive"))
      (node (ref "D931") (pin "A") (pinfunction "A_A") (pintype "passive"))
      (node (ref "D932") (pin "A") (pinfunction "A_A") (pintype "passive"))
      (node (ref "D933") (pin "A") (pinfunction "A_A") (pintype "passive"))
      (node (ref "D934") (pin "A") (pinfunction "A_A") (pintype "passive"))
      (node (ref "D935") (pin "A") (pinfunction "A_A") (pintype "passive"))
      (node (ref "D936") (pin "A") (pinfunction "A_A") (pintype "passive"))
      (node (ref "D937") (pin "A") (pinfunction "A_A") (pintype "passive"))
      (node (ref "D938") (pin "A") (pinfunction "A_A") (pintype "passive"))
      (node (ref "D939") (pin "A") (pinfunction "A_A") (pintype "passive"))
      (node (ref "D94") (pin "A") (pinfunction "A_A") (pintype "passive"))
      (node (ref "D940") (pin "A") (pinfunction "A_A") (pintype "passive"))
      (node (ref "D941") (pin "A") (pinfunction "A_A") (pintype "passive"))
      (node (ref "D942") (pin "A") (pinfunction "A_A") (pintype "passive"))
      (node (ref "D943") (pin "A") (pinfunction "A_A") (pintype "passive"))
      (node (ref "D944") (pin "A") (pinfunction "A_A") (pintype "passive"))
      (node (ref "D945") (pin "A") (pinfunction "A_A") (pintype "passive"))
      (node (ref "D946") (pin "A") (pinfunction "A_A") (pintype "passive"))
      (node (ref "D947") (pin "A") (pinfunction "A_A") (pintype "passive"))
      (node (ref "D948") (pin "A") (pinfunction "A_A") (pintype "passive"))
      (node (ref "D949") (pin "A") (pinfunction "A_A") (pintype "passive"))
      (node (ref "D95") (pin "A") (pinfunction "A_A") (pintype "passive"))
      (node (ref "D950") (pin "A") (pinfunction "A_A") (pintype "passive"))
      (node (ref "D951") (pin "A") (pinfunction "A_A") (pintype "passive"))
      (node (ref "D952") (pin "A") (pinfunction "A_A") (pintype "passive"))
      (node (ref "D953") (pin "A") (pinfunction "A_A") (pintype "passive"))
      (node (ref "D954") (pin "A") (pinfunction "A_A") (pintype "passive"))
      (node (ref "D955") (pin "A") (pinfunction "A_A") (pintype "passive"))
      (node (ref "D956") (pin "A") (pinfunction "A_A") (pintype "passive"))
      (node (ref "D957") (pin "A") (pinfunction "A_A") (pintype "passive"))
      (node (ref "D958") (pin "A") (pinfunction "A_A") (pintype "passive"))
      (node (ref "D959") (pin "A") (pinfunction "A_A") (pintype "passive"))
      (node (ref "D96") (pin "A") (pinfunction "A_A") (pintype "passive"))
      (node (ref "D960") (pin "A") (pinfunction "A_A") (pintype "passive"))
      (node (ref "D961") (pin "A") (pinfunction "A_A") (pintype "passive"))
      (node (ref "D962") (pin "A") (pinfunction "A_A") (pintype "passive"))
      (node (ref "D963") (pin "A") (pinfunction "A_A") (pintype "passive"))
      (node (ref "D964") (pin "A") (pinfunction "A_A") (pintype "passive"))
      (node (ref "D965") (pin "A") (pinfunction "A_A") (pintype "passive"))
      (node (ref "D966") (pin "A") (pinfunction "A_A") (pintype "passive"))
      (node (ref "D967") (pin "A") (pinfunction "A_A") (pintype "passive"))
      (node (ref "D968") (pin "A") (pinfunction "A_A") (pintype "passive"))
      (node (ref "D969") (pin "A") (pinfunction "A_A") (pintype "passive"))
      (node (ref "D97") (pin "A") (pinfunction "A_A") (pintype "passive"))
      (node (ref "D970") (pin "A") (pinfunction "A_A") (pintype "passive"))
      (node (ref "D971") (pin "A") (pinfunction "A_A") (pintype "passive"))
      (node (ref "D972") (pin "A") (pinfunction "A_A") (pintype "passive"))
      (node (ref "D973") (pin "A") (pinfunction "A_A") (pintype "passive"))
      (node (ref "D974") (pin "A") (pinfunction "A_A") (pintype "passive"))
      (node (ref "D975") (pin "A") (pinfunction "A_A") (pintype "passive"))
      (node (ref "D976") (pin "A") (pinfunction "A_A") (pintype "passive"))
      (node (ref "D977") (pin "A") (pinfunction "A_A") (pintype "passive"))
      (node (ref "D978") (pin "A") (pinfunction "A_A") (pintype "passive"))
      (node (ref "D979") (pin "A") (pinfunction "A_A") (pintype "passive"))
      (node (ref "D98") (pin "A") (pinfunction "A_A") (pintype "passive"))
      (node (ref "D980") (pin "A") (pinfunction "A_A") (pintype "passive"))
      (node (ref "D981") (pin "A") (pinfunction "A_A") (pintype "passive"))
      (node (ref "D982") (pin "A") (pinfunction "A_A") (pintype "passive"))
      (node (ref "D983") (pin "A") (pinfunction "A_A") (pintype "passive"))
      (node (ref "D984") (pin "A") (pinfunction "A_A") (pintype "passive"))
      (node (ref "D985") (pin "A") (pinfunction "A_A") (pintype "passive"))
      (node (ref "D986") (pin "A") (pinfunction "A_A") (pintype "passive"))
      (node (ref "D987") (pin "A") (pinfunction "A_A") (pintype "passive"))
      (node (ref "D988") (pin "A") (pinfunction "A_A") (pintype "passive"))
      (node (ref "D989") (pin "A") (pinfunction "A_A") (pintype "passive"))
      (node (ref "D99") (pin "A") (pinfunction "A_A") (pintype "passive"))
      (node (ref "D990") (pin "A") (pinfunction "A_A") (pintype "passive"))
      (node (ref "D991") (pin "A") (pinfunction "A_A") (pintype "passive"))
      (node (ref "D992") (pin "A") (pinfunction "A_A") (pintype "passive"))
      (node (ref "D993") (pin "A") (pinfunction "A_A") (pintype "passive"))
      (node (ref "D994") (pin "A") (pinfunction "A_A") (pintype "passive"))
      (node (ref "D995") (pin "A") (pinfunction "A_A") (pintype "passive"))
      (node (ref "D996") (pin "A") (pinfunction "A_A") (pintype "passive"))
      (node (ref "D997") (pin "A") (pinfunction "A_A") (pintype "passive"))
      (node (ref "D998") (pin "A") (pinfunction "A_A") (pintype "passive"))
      (node (ref "D999") (pin "A") (pinfunction "A_A") (pintype "passive"))
      (node (ref "IC1") (pin "24") (pinfunction "VCC_24") (pintype "power_in"))
      (node (ref "IC10") (pin "24") (pinfunction "VCC_24") (pintype "power_in"))
      (node (ref "IC11") (pin "24") (pinfunction "VCC_24") (pintype "power_in"))
      (node (ref "IC12") (pin "24") (pinfunction "VCC_24") (pintype "power_in"))
      (node (ref "IC13") (pin "24") (pinfunction "VCC_24") (pintype "power_in"))
      (node (ref "IC14") (pin "24") (pinfunction "VCC_24") (pintype "power_in"))
      (node (ref "IC15") (pin "24") (pinfunction "VCC_24") (pintype "power_in"))
      (node (ref "IC16") (pin "24") (pinfunction "VCC_24") (pintype "power_in"))
      (node (ref "IC17") (pin "24") (pinfunction "VCC_24") (pintype "power_in"))
      (node (ref "IC18") (pin "24") (pinfunction "VCC_24") (pintype "power_in"))
      (node (ref "IC19") (pin "24") (pinfunction "VCC_24") (pintype "power_in"))
      (node (ref "IC2") (pin "24") (pinfunction "VCC_24") (pintype "power_in"))
      (node (ref "IC20") (pin "24") (pinfunction "VCC_24") (pintype "power_in"))
      (node (ref "IC21") (pin "24") (pinfunction "VCC_24") (pintype "power_in"))
      (node (ref "IC22") (pin "24") (pinfunction "VCC_24") (pintype "power_in"))
      (node (ref "IC23") (pin "24") (pinfunction "VCC_24") (pintype "power_in"))
      (node (ref "IC24") (pin "24") (pinfunction "VCC_24") (pintype "power_in"))
      (node (ref "IC25") (pin "24") (pinfunction "VCC_24") (pintype "power_in"))
      (node (ref "IC26") (pin "24") (pinfunction "VCC_24") (pintype "power_in"))
      (node (ref "IC27") (pin "24") (pinfunction "VCC_24") (pintype "power_in"))
      (node (ref "IC28") (pin "24") (pinfunction "VCC_24") (pintype "power_in"))
      (node (ref "IC29") (pin "24") (pinfunction "VCC_24") (pintype "power_in"))
      (node (ref "IC3") (pin "24") (pinfunction "VCC_24") (pintype "power_in"))
      (node (ref "IC30") (pin "24") (pinfunction "VCC_24") (pintype "power_in"))
      (node (ref "IC31") (pin "24") (pinfunction "VCC_24") (pintype "power_in"))
      (node (ref "IC32") (pin "24") (pinfunction "VCC_24") (pintype "power_in"))
      (node (ref "IC33") (pin "24") (pinfunction "VCC_24") (pintype "power_in"))
      (node (ref "IC34") (pin "24") (pinfunction "VCC_24") (pintype "power_in"))
      (node (ref "IC35") (pin "24") (pinfunction "VCC_24") (pintype "power_in"))
      (node (ref "IC36") (pin "24") (pinfunction "VCC_24") (pintype "power_in"))
      (node (ref "IC37") (pin "24") (pinfunction "VCC_24") (pintype "power_in"))
      (node (ref "IC38") (pin "24") (pinfunction "VCC_24") (pintype "power_in"))
      (node (ref "IC39") (pin "24") (pinfunction "VCC_24") (pintype "power_in"))
      (node (ref "IC4") (pin "24") (pinfunction "VCC_24") (pintype "power_in"))
      (node (ref "IC40") (pin "24") (pinfunction "VCC_24") (pintype "power_in"))
      (node (ref "IC41") (pin "24") (pinfunction "VCC_24") (pintype "power_in"))
      (node (ref "IC42") (pin "24") (pinfunction "VCC_24") (pintype "power_in"))
      (node (ref "IC43") (pin "24") (pinfunction "VCC_24") (pintype "power_in"))
      (node (ref "IC44") (pin "24") (pinfunction "VCC_24") (pintype "power_in"))
      (node (ref "IC45") (pin "24") (pinfunction "VCC_24") (pintype "power_in"))
      (node (ref "IC46") (pin "24") (pinfunction "VCC_24") (pintype "power_in"))
      (node (ref "IC47") (pin "24") (pinfunction "VCC_24") (pintype "power_in"))
      (node (ref "IC48") (pin "24") (pinfunction "VCC_24") (pintype "power_in"))
      (node (ref "IC49") (pin "24") (pinfunction "VCC_24") (pintype "power_in"))
      (node (ref "IC5") (pin "24") (pinfunction "VCC_24") (pintype "power_in"))
      (node (ref "IC50") (pin "24") (pinfunction "VCC_24") (pintype "power_in"))
      (node (ref "IC51") (pin "24") (pinfunction "VCC_24") (pintype "power_in"))
      (node (ref "IC52") (pin "24") (pinfunction "VCC_24") (pintype "power_in"))
      (node (ref "IC53") (pin "24") (pinfunction "VCC_24") (pintype "power_in"))
      (node (ref "IC54") (pin "24") (pinfunction "VCC_24") (pintype "power_in"))
      (node (ref "IC55") (pin "24") (pinfunction "VCC_24") (pintype "power_in"))
      (node (ref "IC56") (pin "24") (pinfunction "VCC_24") (pintype "power_in"))
      (node (ref "IC57") (pin "24") (pinfunction "VCC_24") (pintype "power_in"))
      (node (ref "IC58") (pin "24") (pinfunction "VCC_24") (pintype "power_in"))
      (node (ref "IC59") (pin "24") (pinfunction "VCC_24") (pintype "power_in"))
      (node (ref "IC6") (pin "24") (pinfunction "VCC_24") (pintype "power_in"))
      (node (ref "IC60") (pin "24") (pinfunction "VCC_24") (pintype "power_in"))
      (node (ref "IC61") (pin "24") (pinfunction "VCC_24") (pintype "power_in"))
      (node (ref "IC62") (pin "24") (pinfunction "VCC_24") (pintype "power_in"))
      (node (ref "IC63") (pin "24") (pinfunction "VCC_24") (pintype "power_in"))
      (node (ref "IC64") (pin "24") (pinfunction "VCC_24") (pintype "power_in"))
      (node (ref "IC7") (pin "24") (pinfunction "VCC_24") (pintype "power_in"))
      (node (ref "IC8") (pin "24") (pinfunction "VCC_24") (pintype "power_in"))
      (node (ref "IC9") (pin "24") (pinfunction "VCC_24") (pintype "power_in"))
      (node (ref "L1") (pin "1") (pinfunction "1_1") (pintype "passive"))
      (node (ref "P1") (pin "1") (pinfunction "1_1") (pintype "bidirectional"))
      (node (ref "P2") (pin "1") (pinfunction "1_1") (pintype "bidirectional"))
      (node (ref "R6") (pin "2") (pinfunction "2_2") (pintype "passive"))
    )
    (net (code "2") (name "+5V{slash}1") (class "Default")
      (node (ref "C13") (pin "2") (pinfunction "2_2") (pintype "passive"))
      (node (ref "C14") (pin "2") (pinfunction "2_2") (pintype "passive"))
      (node (ref "D1028") (pin "C") (pinfunction "C_C") (pintype "passive"))
      (node (ref "F1") (pin "2") (pinfunction "2_2") (pintype "passive"))
      (node (ref "U3") (pin "1") (pinfunction "VIN_1") (pintype "bidirectional"))
      (node (ref "U3") (pin "3") (pinfunction "CE_3") (pintype "bidirectional"))
    )
    (net (code "3") (name "/ID") (class "Default")
      (node (ref "J2") (pin "4") (pinfunction "---ID_4") (pintype "bidirectional"))
    )
    (net (code "4") (name "/USB_D+") (class "Default")
      (node (ref "C8") (pin "2") (pinfunction "2_2") (pintype "passive"))
      (node (ref "J2") (pin "3") (pinfunction "---D+_3") (pintype "bidirectional"))
      (node (ref "R4") (pin "2") (pinfunction "2_2") (pintype "passive"))
    )
    (net (code "5") (name "/USB_D-") (class "Default")
      (node (ref "C9") (pin "1") (pinfunction "1_1") (pintype "passive"))
      (node (ref "J2") (pin "2") (pinfunction "---D-_2") (pintype "bidirectional"))
      (node (ref "R5") (pin "2") (pinfunction "2_2") (pintype "passive"))
    )
    (net (code "6") (name "3V3") (class "Default")
      (node (ref "C1") (pin "1") (pinfunction "1_1") (pintype "passive"))
      (node (ref "C12") (pin "2") (pinfunction "2_2") (pintype "passive"))
      (node (ref "C15") (pin "2") (pinfunction "2_2") (pintype "passive"))
      (node (ref "C2") (pin "1") (pinfunction "1_1") (pintype "passive"))
      (node (ref "J1") (pin "4") (pinfunction "VDD_4") (pintype "bidirectional"))
      (node (ref "JP2") (pin "1") (pinfunction "1_1") (pintype "passive"))
      (node (ref "R1") (pin "2") (pinfunction "2_2") (pintype "passive"))
      (node (ref "R10") (pin "2") (pinfunction "2_2") (pintype "passive"))
      (node (ref "R11") (pin "2") (pinfunction "2_2") (pintype "passive"))
      (node (ref "R2") (pin "2") (pinfunction "2_2") (pintype "passive"))
      (node (ref "R3") (pin "2") (pinfunction "2_2") (pintype "passive"))
      (node (ref "U2") (pin "2") (pinfunction "3V3_2") (pintype "power_in"))
      (node (ref "U3") (pin "5") (pinfunction "VOUT_5") (pintype "bidirectional"))
    )
    (net (code "7") (name "CLK") (class "Default")
      (node (ref "IC1") (pin "3") (pinfunction "SCLK_3") (pintype "input"))
      (node (ref "IC10") (pin "3") (pinfunction "SCLK_3") (pintype "input"))
      (node (ref "IC11") (pin "3") (pinfunction "SCLK_3") (pintype "input"))
      (node (ref "IC12") (pin "3") (pinfunction "SCLK_3") (pintype "input"))
      (node (ref "IC13") (pin "3") (pinfunction "SCLK_3") (pintype "input"))
      (node (ref "IC14") (pin "3") (pinfunction "SCLK_3") (pintype "input"))
      (node (ref "IC15") (pin "3") (pinfunction "SCLK_3") (pintype "input"))
      (node (ref "IC16") (pin "3") (pinfunction "SCLK_3") (pintype "input"))
      (node (ref "IC17") (pin "3") (pinfunction "SCLK_3") (pintype "input"))
      (node (ref "IC18") (pin "3") (pinfunction "SCLK_3") (pintype "input"))
      (node (ref "IC19") (pin "3") (pinfunction "SCLK_3") (pintype "input"))
      (node (ref "IC2") (pin "3") (pinfunction "SCLK_3") (pintype "input"))
      (node (ref "IC20") (pin "3") (pinfunction "SCLK_3") (pintype "input"))
      (node (ref "IC21") (pin "3") (pinfunction "SCLK_3") (pintype "input"))
      (node (ref "IC22") (pin "3") (pinfunction "SCLK_3") (pintype "input"))
      (node (ref "IC23") (pin "3") (pinfunction "SCLK_3") (pintype "input"))
      (node (ref "IC24") (pin "3") (pinfunction "SCLK_3") (pintype "input"))
      (node (ref "IC25") (pin "3") (pinfunction "SCLK_3") (pintype "input"))
      (node (ref "IC26") (pin "3") (pinfunction "SCLK_3") (pintype "input"))
      (node (ref "IC27") (pin "3") (pinfunction "SCLK_3") (pintype "input"))
      (node (ref "IC28") (pin "3") (pinfunction "SCLK_3") (pintype "input"))
      (node (ref "IC29") (pin "3") (pinfunction "SCLK_3") (pintype "input"))
      (node (ref "IC3") (pin "3") (pinfunction "SCLK_3") (pintype "input"))
      (node (ref "IC30") (pin "3") (pinfunction "SCLK_3") (pintype "input"))
      (node (ref "IC31") (pin "3") (pinfunction "SCLK_3") (pintype "input"))
      (node (ref "IC32") (pin "3") (pinfunction "SCLK_3") (pintype "input"))
      (node (ref "IC33") (pin "3") (pinfunction "SCLK_3") (pintype "input"))
      (node (ref "IC34") (pin "3") (pinfunction "SCLK_3") (pintype "input"))
      (node (ref "IC35") (pin "3") (pinfunction "SCLK_3") (pintype "input"))
      (node (ref "IC36") (pin "3") (pinfunction "SCLK_3") (pintype "input"))
      (node (ref "IC37") (pin "3") (pinfunction "SCLK_3") (pintype "input"))
      (node (ref "IC38") (pin "3") (pinfunction "SCLK_3") (pintype "input"))
      (node (ref "IC39") (pin "3") (pinfunction "SCLK_3") (pintype "input"))
      (node (ref "IC4") (pin "3") (pinfunction "SCLK_3") (pintype "input"))
      (node (ref "IC40") (pin "3") (pinfunction "SCLK_3") (pintype "input"))
      (node (ref "IC41") (pin "3") (pinfunction "SCLK_3") (pintype "input"))
      (node (ref "IC42") (pin "3") (pinfunction "SCLK_3") (pintype "input"))
      (node (ref "IC43") (pin "3") (pinfunction "SCLK_3") (pintype "input"))
      (node (ref "IC44") (pin "3") (pinfunction "SCLK_3") (pintype "input"))
      (node (ref "IC45") (pin "3") (pinfunction "SCLK_3") (pintype "input"))
      (node (ref "IC46") (pin "3") (pinfunction "SCLK_3") (pintype "input"))
      (node (ref "IC47") (pin "3") (pinfunction "SCLK_3") (pintype "input"))
      (node (ref "IC48") (pin "3") (pinfunction "SCLK_3") (pintype "input"))
      (node (ref "IC49") (pin "3") (pinfunction "SCLK_3") (pintype "input"))
      (node (ref "IC5") (pin "3") (pinfunction "SCLK_3") (pintype "input"))
      (node (ref "IC50") (pin "3") (pinfunction "SCLK_3") (pintype "input"))
      (node (ref "IC51") (pin "3") (pinfunction "SCLK_3") (pintype "input"))
      (node (ref "IC52") (pin "3") (pinfunction "SCLK_3") (pintype "input"))
      (node (ref "IC53") (pin "3") (pinfunction "SCLK_3") (pintype "input"))
      (node (ref "IC54") (pin "3") (pinfunction "SCLK_3") (pintype "input"))
      (node (ref "IC55") (pin "3") (pinfunction "SCLK_3") (pintype "input"))
      (node (ref "IC56") (pin "3") (pinfunction "SCLK_3") (pintype "input"))
      (node (ref "IC57") (pin "3") (pinfunction "SCLK_3") (pintype "input"))
      (node (ref "IC58") (pin "3") (pinfunction "SCLK_3") (pintype "input"))
      (node (ref "IC59") (pin "3") (pinfunction "SCLK_3") (pintype "input"))
      (node (ref "IC6") (pin "3") (pinfunction "SCLK_3") (pintype "input"))
      (node (ref "IC60") (pin "3") (pinfunction "SCLK_3") (pintype "input"))
      (node (ref "IC61") (pin "3") (pinfunction "SCLK_3") (pintype "input"))
      (node (ref "IC62") (pin "3") (pinfunction "SCLK_3") (pintype "input"))
      (node (ref "IC63") (pin "3") (pinfunction "SCLK_3") (pintype "input"))
      (node (ref "IC64") (pin "3") (pinfunction "SCLK_3") (pintype "input"))
      (node (ref "IC7") (pin "3") (pinfunction "SCLK_3") (pintype "input"))
      (node (ref "IC8") (pin "3") (pinfunction "SCLK_3") (pintype "input"))
      (node (ref "IC9") (pin "3") (pinfunction "SCLK_3") (pintype "input"))
      (node (ref "P1") (pin "5") (pinfunction "5_5") (pintype "bidirectional"))
      (node (ref "P2") (pin "5") (pinfunction "5_5") (pintype "bidirectional"))
      (node (ref "U2") (pin "30") (pinfunction "IO36_30") (pintype "bidirectional"))
    )
    (net (code "8") (name "DATA0") (class "Default")
      (node (ref "IC8") (pin "2") (pinfunction "SIN_2") (pintype "input"))
      (node (ref "P1") (pin "4") (pinfunction "4_4") (pintype "bidirectional"))
      (node (ref "U2") (pin "29") (pinfunction "IO35_29") (pintype "input"))
    )
    (net (code "9") (name "DATA1") (class "Default")
      (node (ref "IC7") (pin "2") (pinfunction "SIN_2") (pintype "input"))
      (node (ref "IC8") (pin "22") (pinfunction "SOUT_22") (pintype "output"))
    )
    (net (code "10") (name "DATA2") (class "Default")
      (node (ref "IC6") (pin "2") (pinfunction "SIN_2") (pintype "input"))
      (node (ref "IC7") (pin "22") (pinfunction "SOUT_22") (pintype "output"))
    )
    (net (code "11") (name "DATA3") (class "Default")
      (node (ref "IC5") (pin "2") (pinfunction "SIN_2") (pintype "input"))
      (node (ref "IC6") (pin "22") (pinfunction "SOUT_22") (pintype "output"))
    )
    (net (code "12") (name "DATA4") (class "Default")
      (node (ref "IC4") (pin "2") (pinfunction "SIN_2") (pintype "input"))
      (node (ref "IC5") (pin "22") (pinfunction "SOUT_22") (pintype "output"))
    )
    (net (code "13") (name "DATA5") (class "Default")
      (node (ref "IC3") (pin "2") (pinfunction "SIN_2") (pintype "input"))
      (node (ref "IC4") (pin "22") (pinfunction "SOUT_22") (pintype "output"))
    )
    (net (code "14") (name "DATA6") (class "Default")
      (node (ref "IC2") (pin "2") (pinfunction "SIN_2") (pintype "input"))
      (node (ref "IC3") (pin "22") (pinfunction "SOUT_22") (pintype "output"))
    )
    (net (code "15") (name "DATA7") (class "Default")
      (node (ref "IC1") (pin "2") (pinfunction "SIN_2") (pintype "input"))
      (node (ref "IC2") (pin "22") (pinfunction "SOUT_22") (pintype "output"))
    )
    (net (code "16") (name "DATA8") (class "Default")
      (node (ref "IC1") (pin "22") (pinfunction "SOUT_22") (pintype "output"))
      (node (ref "IC16") (pin "2") (pinfunction "SIN_2") (pintype "input"))
    )
    (net (code "17") (name "DATA9") (class "Default")
      (node (ref "IC15") (pin "2") (pinfunction "SIN_2") (pintype "input"))
      (node (ref "IC16") (pin "22") (pinfunction "SOUT_22") (pintype "output"))
    )
    (net (code "18") (name "DATA10") (class "Default")
      (node (ref "IC14") (pin "2") (pinfunction "SIN_2") (pintype "input"))
      (node (ref "IC15") (pin "22") (pinfunction "SOUT_22") (pintype "output"))
    )
    (net (code "19") (name "DATA11") (class "Default")
      (node (ref "IC13") (pin "2") (pinfunction "SIN_2") (pintype "input"))
      (node (ref "IC14") (pin "22") (pinfunction "SOUT_22") (pintype "output"))
    )
    (net (code "20") (name "DATA12") (class "Default")
      (node (ref "IC12") (pin "2") (pinfunction "SIN_2") (pintype "input"))
      (node (ref "IC13") (pin "22") (pinfunction "SOUT_22") (pintype "output"))
    )
    (net (code "21") (name "DATA13") (class "Default")
      (node (ref "IC11") (pin "2") (pinfunction "SIN_2") (pintype "input"))
      (node (ref "IC12") (pin "22") (pinfunction "SOUT_22") (pintype "output"))
    )
    (net (code "22") (name "DATA14") (class "Default")
      (node (ref "IC10") (pin "2") (pinfunction "SIN_2") (pintype "input"))
      (node (ref "IC11") (pin "22") (pinfunction "SOUT_22") (pintype "output"))
    )
    (net (code "23") (name "DATA15") (class "Default")
      (node (ref "IC10") (pin "22") (pinfunction "SOUT_22") (pintype "output"))
      (node (ref "IC9") (pin "2") (pinfunction "SIN_2") (pintype "input"))
    )
    (net (code "24") (name "DATA16") (class "Default")
      (node (ref "IC24") (pin "2") (pinfunction "SIN_2") (pintype "input"))
      (node (ref "IC9") (pin "22") (pinfunction "SOUT_22") (pintype "output"))
    )
    (net (code "25") (name "DATA17") (class "Default")
      (node (ref "IC23") (pin "2") (pinfunction "SIN_2") (pintype "input"))
      (node (ref "IC24") (pin "22") (pinfunction "SOUT_22") (pintype "output"))
    )
    (net (code "26") (name "DATA18") (class "Default")
      (node (ref "IC22") (pin "2") (pinfunction "SIN_2") (pintype "input"))
      (node (ref "IC23") (pin "22") (pinfunction "SOUT_22") (pintype "output"))
    )
    (net (code "27") (name "DATA19") (class "Default")
      (node (ref "IC21") (pin "2") (pinfunction "SIN_2") (pintype "input"))
      (node (ref "IC22") (pin "22") (pinfunction "SOUT_22") (pintype "output"))
    )
    (net (code "28") (name "DATA20") (class "Default")
      (node (ref "IC20") (pin "2") (pinfunction "SIN_2") (pintype "input"))
      (node (ref "IC21") (pin "22") (pinfunction "SOUT_22") (pintype "output"))
    )
    (net (code "29") (name "DATA21") (class "Default")
      (node (ref "IC19") (pin "2") (pinfunction "SIN_2") (pintype "input"))
      (node (ref "IC20") (pin "22") (pinfunction "SOUT_22") (pintype "output"))
    )
    (net (code "30") (name "DATA22") (class "Default")
      (node (ref "IC18") (pin "2") (pinfunction "SIN_2") (pintype "input"))
      (node (ref "IC19") (pin "22") (pinfunction "SOUT_22") (pintype "output"))
    )
    (net (code "31") (name "DATA23") (class "Default")
      (node (ref "IC17") (pin "2") (pinfunction "SIN_2") (pintype "input"))
      (node (ref "IC18") (pin "22") (pinfunction "SOUT_22") (pintype "output"))
    )
    (net (code "32") (name "DATA24") (class "Default")
      (node (ref "IC17") (pin "22") (pinfunction "SOUT_22") (pintype "output"))
      (node (ref "IC32") (pin "2") (pinfunction "SIN_2") (pintype "input"))
    )
    (net (code "33") (name "DATA25") (class "Default")
      (node (ref "IC31") (pin "2") (pinfunction "SIN_2") (pintype "input"))
      (node (ref "IC32") (pin "22") (pinfunction "SOUT_22") (pintype "output"))
    )
    (net (code "34") (name "DATA26") (class "Default")
      (node (ref "IC30") (pin "2") (pinfunction "SIN_2") (pintype "input"))
      (node (ref "IC31") (pin "22") (pinfunction "SOUT_22") (pintype "output"))
    )
    (net (code "35") (name "DATA27") (class "Default")
      (node (ref "IC29") (pin "2") (pinfunction "SIN_2") (pintype "input"))
      (node (ref "IC30") (pin "22") (pinfunction "SOUT_22") (pintype "output"))
    )
    (net (code "36") (name "DATA28") (class "Default")
      (node (ref "IC28") (pin "2") (pinfunction "SIN_2") (pintype "input"))
      (node (ref "IC29") (pin "22") (pinfunction "SOUT_22") (pintype "output"))
    )
    (net (code "37") (name "DATA29") (class "Default")
      (node (ref "IC27") (pin "2") (pinfunction "SIN_2") (pintype "input"))
      (node (ref "IC28") (pin "22") (pinfunction "SOUT_22") (pintype "output"))
    )
    (net (code "38") (name "DATA30") (class "Default")
      (node (ref "IC26") (pin "2") (pinfunction "SIN_2") (pintype "input"))
      (node (ref "IC27") (pin "22") (pinfunction "SOUT_22") (pintype "output"))
    )
    (net (code "39") (name "DATA31") (class "Default")
      (node (ref "IC25") (pin "2") (pinfunction "SIN_2") (pintype "input"))
      (node (ref "IC26") (pin "22") (pinfunction "SOUT_22") (pintype "output"))
    )
    (net (code "40") (name "DATA32") (class "Default")
      (node (ref "IC25") (pin "22") (pinfunction "SOUT_22") (pintype "output"))
    )
    (net (code "41") (name "DATA100") (class "Default")
      (node (ref "IC40") (pin "2") (pinfunction "SIN_2") (pintype "input"))
      (node (ref "P2") (pin "4") (pinfunction "4_4") (pintype "bidirectional"))
    )
    (net (code "42") (name "DATA101") (class "Default")
      (node (ref "IC39") (pin "2") (pinfunction "SIN_2") (pintype "input"))
      (node (ref "IC40") (pin "22") (pinfunction "SOUT_22") (pintype "output"))
    )
    (net (code "43") (name "DATA102") (class "Default")
      (node (ref "IC38") (pin "2") (pinfunction "SIN_2") (pintype "input"))
      (node (ref "IC39") (pin "22") (pinfunction "SOUT_22") (pintype "output"))
    )
    (net (code "44") (name "DATA103") (class "Default")
      (node (ref "IC37") (pin "2") (pinfunction "SIN_2") (pintype "input"))
      (node (ref "IC38") (pin "22") (pinfunction "SOUT_22") (pintype "output"))
    )
    (net (code "45") (name "DATA104") (class "Default")
      (node (ref "IC36") (pin "2") (pinfunction "SIN_2") (pintype "input"))
      (node (ref "IC37") (pin "22") (pinfunction "SOUT_22") (pintype "output"))
    )
    (net (code "46") (name "DATA105") (class "Default")
      (node (ref "IC35") (pin "2") (pinfunction "SIN_2") (pintype "input"))
      (node (ref "IC36") (pin "22") (pinfunction "SOUT_22") (pintype "output"))
    )
    (net (code "47") (name "DATA106") (class "Default")
      (node (ref "IC34") (pin "2") (pinfunction "SIN_2") (pintype "input"))
      (node (ref "IC35") (pin "22") (pinfunction "SOUT_22") (pintype "output"))
    )
    (net (code "48") (name "DATA107") (class "Default")
      (node (ref "IC33") (pin "2") (pinfunction "SIN_2") (pintype "input"))
      (node (ref "IC34") (pin "22") (pinfunction "SOUT_22") (pintype "output"))
    )
    (net (code "49") (name "DATA108") (class "Default")
      (node (ref "IC33") (pin "22") (pinfunction "SOUT_22") (pintype "output"))
      (node (ref "IC48") (pin "2") (pinfunction "SIN_2") (pintype "input"))
    )
    (net (code "50") (name "DATA109") (class "Default")
      (node (ref "IC47") (pin "2") (pinfunction "SIN_2") (pintype "input"))
      (node (ref "IC48") (pin "22") (pinfunction "SOUT_22") (pintype "output"))
    )
    (net (code "51") (name "DATA110") (class "Default")
      (node (ref "IC46") (pin "2") (pinfunction "SIN_2") (pintype "input"))
      (node (ref "IC47") (pin "22") (pinfunction "SOUT_22") (pintype "output"))
    )
    (net (code "52") (name "DATA111") (class "Default")
      (node (ref "IC45") (pin "2") (pinfunction "SIN_2") (pintype "input"))
      (node (ref "IC46") (pin "22") (pinfunction "SOUT_22") (pintype "output"))
    )
    (net (code "53") (name "DATA112") (class "Default")
      (node (ref "IC44") (pin "2") (pinfunction "SIN_2") (pintype "input"))
      (node (ref "IC45") (pin "22") (pinfunction "SOUT_22") (pintype "output"))
    )
    (net (code "54") (name "DATA113") (class "Default")
      (node (ref "IC43") (pin "2") (pinfunction "SIN_2") (pintype "input"))
      (node (ref "IC44") (pin "22") (pinfunction "SOUT_22") (pintype "output"))
    )
    (net (code "55") (name "DATA114") (class "Default")
      (node (ref "IC42") (pin "2") (pinfunction "SIN_2") (pintype "input"))
      (node (ref "IC43") (pin "22") (pinfunction "SOUT_22") (pintype "output"))
    )
    (net (code "56") (name "DATA115") (class "Default")
      (node (ref "IC41") (pin "2") (pinfunction "SIN_2") (pintype "input"))
      (node (ref "IC42") (pin "22") (pinfunction "SOUT_22") (pintype "output"))
    )
    (net (code "57") (name "DATA116") (class "Default")
      (node (ref "IC41") (pin "22") (pinfunction "SOUT_22") (pintype "output"))
      (node (ref "IC56") (pin "2") (pinfunction "SIN_2") (pintype "input"))
    )
    (net (code "58") (name "DATA117") (class "Default")
      (node (ref "IC55") (pin "2") (pinfunction "SIN_2") (pintype "input"))
      (node (ref "IC56") (pin "22") (pinfunction "SOUT_22") (pintype "output"))
    )
    (net (code "59") (name "DATA118") (class "Default")
      (node (ref "IC54") (pin "2") (pinfunction "SIN_2") (pintype "input"))
      (node (ref "IC55") (pin "22") (pinfunction "SOUT_22") (pintype "output"))
    )
    (net (code "60") (name "DATA119") (class "Default")
      (node (ref "IC53") (pin "2") (pinfunction "SIN_2") (pintype "input"))
      (node (ref "IC54") (pin "22") (pinfunction "SOUT_22") (pintype "output"))
    )
    (net (code "61") (name "DATA120") (class "Default")
      (node (ref "IC52") (pin "2") (pinfunction "SIN_2") (pintype "input"))
      (node (ref "IC53") (pin "22") (pinfunction "SOUT_22") (pintype "output"))
    )
    (net (code "62") (name "DATA121") (class "Default")
      (node (ref "IC51") (pin "2") (pinfunction "SIN_2") (pintype "input"))
      (node (ref "IC52") (pin "22") (pinfunction "SOUT_22") (pintype "output"))
    )
    (net (code "63") (name "DATA122") (class "Default")
      (node (ref "IC50") (pin "2") (pinfunction "SIN_2") (pintype "input"))
      (node (ref "IC51") (pin "22") (pinfunction "SOUT_22") (pintype "output"))
    )
    (net (code "64") (name "DATA123") (class "Default")
      (node (ref "IC49") (pin "2") (pinfunction "SIN_2") (pintype "input"))
      (node (ref "IC50") (pin "22") (pinfunction "SOUT_22") (pintype "output"))
    )
    (net (code "65") (name "DATA124") (class "Default")
      (node (ref "IC49") (pin "22") (pinfunction "SOUT_22") (pintype "output"))
      (node (ref "IC64") (pin "2") (pinfunction "SIN_2") (pintype "input"))
    )
    (net (code "66") (name "DATA125") (class "Default")
      (node (ref "IC63") (pin "2") (pinfunction "SIN_2") (pintype "input"))
      (node (ref "IC64") (pin "22") (pinfunction "SOUT_22") (pintype "output"))
    )
    (net (code "67") (name "DATA126") (class "Default")
      (node (ref "IC62") (pin "2") (pinfunction "SIN_2") (pintype "input"))
      (node (ref "IC63") (pin "22") (pinfunction "SOUT_22") (pintype "output"))
    )
    (net (code "68") (name "DATA127") (class "Default")
      (node (ref "IC61") (pin "2") (pinfunction "SIN_2") (pintype "input"))
      (node (ref "IC62") (pin "22") (pinfunction "SOUT_22") (pintype "output"))
    )
    (net (code "69") (name "DATA128") (class "Default")
      (node (ref "IC60") (pin "2") (pinfunction "SIN_2") (pintype "input"))
      (node (ref "IC61") (pin "22") (pinfunction "SOUT_22") (pintype "output"))
    )
    (net (code "70") (name "DATA129") (class "Default")
      (node (ref "IC59") (pin "2") (pinfunction "SIN_2") (pintype "input"))
      (node (ref "IC60") (pin "22") (pinfunction "SOUT_22") (pintype "output"))
    )
    (net (code "71") (name "DATA130") (class "Default")
      (node (ref "IC58") (pin "2") (pinfunction "SIN_2") (pintype "input"))
      (node (ref "IC59") (pin "22") (pinfunction "SOUT_22") (pintype "output"))
    )
    (net (code "72") (name "DATA131") (class "Default")
      (node (ref "IC57") (pin "2") (pinfunction "SIN_2") (pintype "input"))
      (node (ref "IC58") (pin "22") (pinfunction "SOUT_22") (pintype "output"))
    )
    (net (code "73") (name "DATA132") (class "Default")
      (node (ref "IC57") (pin "22") (pinfunction "SOUT_22") (pintype "output"))
    )
    (net (code "74") (name "GND") (class "Default")
      (node (ref "C1") (pin "2") (pinfunction "2_2") (pintype "passive"))
      (node (ref "C10") (pin "-") (pinfunction "-_-") (pintype "passive"))
      (node (ref "C11") (pin "-") (pinfunction "-_-") (pintype "passive"))
      (node (ref "C12") (pin "1") (pinfunction "1_1") (pintype "passive"))
      (node (ref "C13") (pin "1") (pinfunction "1_1") (pintype "passive"))
      (node (ref "C14") (pin "1") (pinfunction "1_1") (pintype "passive"))
      (node (ref "C15") (pin "1") (pinfunction "1_1") (pintype "passive"))
      (node (ref "C16") (pin "2") (pinfunction "2_2") (pintype "passive"))
      (node (ref "C17") (pin "2") (pinfunction "2_2") (pintype "passive"))
      (node (ref "C18") (pin "2") (pinfunction "2_2") (pintype "passive"))
      (node (ref "C19") (pin "2") (pinfunction "2_2") (pintype "passive"))
      (node (ref "C2") (pin "2") (pinfunction "2_2") (pintype "passive"))
      (node (ref "C20") (pin "2") (pinfunction "2_2") (pintype "passive"))
      (node (ref "C21") (pin "2") (pinfunction "2_2") (pintype "passive"))
      (node (ref "C22") (pin "2") (pinfunction "2_2") (pintype "passive"))
      (node (ref "C23") (pin "2") (pinfunction "2_2") (pintype "passive"))
      (node (ref "C24") (pin "2") (pinfunction "2_2") (pintype "passive"))
      (node (ref "C25") (pin "2") (pinfunction "2_2") (pintype "passive"))
      (node (ref "C26") (pin "2") (pinfunction "2_2") (pintype "passive"))
      (node (ref "C27") (pin "2") (pinfunction "2_2") (pintype "passive"))
      (node (ref "C28") (pin "2") (pinfunction "2_2") (pintype "passive"))
      (node (ref "C29") (pin "2") (pinfunction "2_2") (pintype "passive"))
      (node (ref "C3") (pin "1") (pinfunction "1_1") (pintype "passive"))
      (node (ref "C30") (pin "2") (pinfunction "2_2") (pintype "passive"))
      (node (ref "C31") (pin "2") (pinfunction "2_2") (pintype "passive"))
      (node (ref "C32") (pin "2") (pinfunction "2_2") (pintype "passive"))
      (node (ref "C33") (pin "2") (pinfunction "2_2") (pintype "passive"))
      (node (ref "C34") (pin "2") (pinfunction "2_2") (pintype "passive"))
      (node (ref "C35") (pin "2") (pinfunction "2_2") (pintype "passive"))
      (node (ref "C36") (pin "2") (pinfunction "2_2") (pintype "passive"))
      (node (ref "C37") (pin "2") (pinfunction "2_2") (pintype "passive"))
      (node (ref "C38") (pin "2") (pinfunction "2_2") (pintype "passive"))
      (node (ref "C39") (pin "2") (pinfunction "2_2") (pintype "passive"))
      (node (ref "C4") (pin "1") (pinfunction "1_1") (pintype "passive"))
      (node (ref "C40") (pin "2") (pinfunction "2_2") (pintype "passive"))
      (node (ref "C41") (pin "2") (pinfunction "2_2") (pintype "passive"))
      (node (ref "C42") (pin "2") (pinfunction "2_2") (pintype "passive"))
      (node (ref "C43") (pin "2") (pinfunction "2_2") (pintype "passive"))
      (node (ref "C44") (pin "2") (pinfunction "2_2") (pintype "passive"))
      (node (ref "C45") (pin "2") (pinfunction "2_2") (pintype "passive"))
      (node (ref "C46") (pin "2") (pinfunction "2_2") (pintype "passive"))
      (node (ref "C47") (pin "2") (pinfunction "2_2") (pintype "passive"))
      (node (ref "C48") (pin "2") (pinfunction "2_2") (pintype "passive"))
      (node (ref "C49") (pin "2") (pinfunction "2_2") (pintype "passive"))
      (node (ref "C50") (pin "2") (pinfunction "2_2") (pintype "passive"))
      (node (ref "C51") (pin "2") (pinfunction "2_2") (pintype "passive"))
      (node (ref "C52") (pin "2") (pinfunction "2_2") (pintype "passive"))
      (node (ref "C53") (pin "2") (pinfunction "2_2") (pintype "passive"))
      (node (ref "C54") (pin "2") (pinfunction "2_2") (pintype "passive"))
      (node (ref "C55") (pin "2") (pinfunction "2_2") (pintype "passive"))
      (node (ref "C56") (pin "2") (pinfunction "2_2") (pintype "passive"))
      (node (ref "C57") (pin "2") (pinfunction "2_2") (pintype "passive"))
      (node (ref "C58") (pin "2") (pinfunction "2_2") (pintype "passive"))
      (node (ref "C59") (pin "2") (pinfunction "2_2") (pintype "passive"))
      (node (ref "C6") (pin "2") (pinfunction "2_2") (pintype "passive"))
      (node (ref "C60") (pin "2") (pinfunction "2_2") (pintype "passive"))
      (node (ref "C61") (pin "2") (pinfunction "2_2") (pintype "passive"))
      (node (ref "C62") (pin "2") (pinfunction "2_2") (pintype "passive"))
      (node (ref "C63") (pin "2") (pinfunction "2_2") (pintype "passive"))
      (node (ref "C64") (pin "2") (pinfunction "2_2") (pintype "passive"))
      (node (ref "C65") (pin "2") (pinfunction "2_2") (pintype "passive"))
      (node (ref "C66") (pin "2") (pinfunction "2_2") (pintype "passive"))
      (node (ref "C67") (pin "2") (pinfunction "2_2") (pintype "passive"))
      (node (ref "C68") (pin "2") (pinfunction "2_2") (pintype "passive"))
      (node (ref "C69") (pin "2") (pinfunction "2_2") (pintype "passive"))
      (node (ref "C7") (pin "2") (pinfunction "2_2") (pintype "passive"))
      (node (ref "C70") (pin "2") (pinfunction "2_2") (pintype "passive"))
      (node (ref "C71") (pin "2") (pinfunction "2_2") (pintype "passive"))
      (node (ref "C72") (pin "2") (pinfunction "2_2") (pintype "passive"))
      (node (ref "C73") (pin "2") (pinfunction "2_2") (pintype "passive"))
      (node (ref "C74") (pin "2") (pinfunction "2_2") (pintype "passive"))
      (node (ref "C75") (pin "2") (pinfunction "2_2") (pintype "passive"))
      (node (ref "C76") (pin "2") (pinfunction "2_2") (pintype "passive"))
      (node (ref "C77") (pin "2") (pinfunction "2_2") (pintype "passive"))
      (node (ref "C78") (pin "2") (pinfunction "2_2") (pintype "passive"))
      (node (ref "C79") (pin "2") (pinfunction "2_2") (pintype "passive"))
      (node (ref "C8") (pin "1") (pinfunction "1_1") (pintype "passive"))
      (node (ref "C9") (pin "2") (pinfunction "2_2") (pintype "passive"))
      (node (ref "D1") (pin "A") (pinfunction "A_A") (pintype "passive"))
      (node (ref "D2") (pin "A") (pinfunction "A_A") (pintype "passive"))
      (node (ref "D3") (pin "C") (pinfunction "C_C") (pintype "passive"))
      (node (ref "IC1") (pin "1") (pinfunction "GND_1") (pintype "power_in"))
      (node (ref "IC1") (pin "21") (pinfunction "BLANK_21") (pintype "input"))
      (node (ref "IC10") (pin "1") (pinfunction "GND_1") (pintype "power_in"))
      (node (ref "IC10") (pin "21") (pinfunction "BLANK_21") (pintype "input"))
      (node (ref "IC11") (pin "1") (pinfunction "GND_1") (pintype "power_in"))
      (node (ref "IC11") (pin "21") (pinfunction "BLANK_21") (pintype "input"))
      (node (ref "IC12") (pin "1") (pinfunction "GND_1") (pintype "power_in"))
      (node (ref "IC12") (pin "21") (pinfunction "BLANK_21") (pintype "input"))
      (node (ref "IC13") (pin "1") (pinfunction "GND_1") (pintype "power_in"))
      (node (ref "IC13") (pin "21") (pinfunction "BLANK_21") (pintype "input"))
      (node (ref "IC14") (pin "1") (pinfunction "GND_1") (pintype "power_in"))
      (node (ref "IC14") (pin "21") (pinfunction "BLANK_21") (pintype "input"))
      (node (ref "IC15") (pin "1") (pinfunction "GND_1") (pintype "power_in"))
      (node (ref "IC15") (pin "21") (pinfunction "BLANK_21") (pintype "input"))
      (node (ref "IC16") (pin "1") (pinfunction "GND_1") (pintype "power_in"))
      (node (ref "IC16") (pin "21") (pinfunction "BLANK_21") (pintype "input"))
      (node (ref "IC17") (pin "1") (pinfunction "GND_1") (pintype "power_in"))
      (node (ref "IC17") (pin "21") (pinfunction "BLANK_21") (pintype "input"))
      (node (ref "IC18") (pin "1") (pinfunction "GND_1") (pintype "power_in"))
      (node (ref "IC18") (pin "21") (pinfunction "BLANK_21") (pintype "input"))
      (node (ref "IC19") (pin "1") (pinfunction "GND_1") (pintype "power_in"))
      (node (ref "IC19") (pin "21") (pinfunction "BLANK_21") (pintype "input"))
      (node (ref "IC2") (pin "1") (pinfunction "GND_1") (pintype "power_in"))
      (node (ref "IC2") (pin "21") (pinfunction "BLANK_21") (pintype "input"))
      (node (ref "IC20") (pin "1") (pinfunction "GND_1") (pintype "power_in"))
      (node (ref "IC20") (pin "21") (pinfunction "BLANK_21") (pintype "input"))
      (node (ref "IC21") (pin "1") (pinfunction "GND_1") (pintype "power_in"))
      (node (ref "IC21") (pin "21") (pinfunction "BLANK_21") (pintype "input"))
      (node (ref "IC22") (pin "1") (pinfunction "GND_1") (pintype "power_in"))
      (node (ref "IC22") (pin "21") (pinfunction "BLANK_21") (pintype "input"))
      (node (ref "IC23") (pin "1") (pinfunction "GND_1") (pintype "power_in"))
      (node (ref "IC23") (pin "21") (pinfunction "BLANK_21") (pintype "input"))
      (node (ref "IC24") (pin "1") (pinfunction "GND_1") (pintype "power_in"))
      (node (ref "IC24") (pin "21") (pinfunction "BLANK_21") (pintype "input"))
      (node (ref "IC25") (pin "1") (pinfunction "GND_1") (pintype "power_in"))
      (node (ref "IC25") (pin "21") (pinfunction "BLANK_21") (pintype "input"))
      (node (ref "IC26") (pin "1") (pinfunction "GND_1") (pintype "power_in"))
      (node (ref "IC26") (pin "21") (pinfunction "BLANK_21") (pintype "input"))
      (node (ref "IC27") (pin "1") (pinfunction "GND_1") (pintype "power_in"))
      (node (ref "IC27") (pin "21") (pinfunction "BLANK_21") (pintype "input"))
      (node (ref "IC28") (pin "1") (pinfunction "GND_1") (pintype "power_in"))
      (node (ref "IC28") (pin "21") (pinfunction "BLANK_21") (pintype "input"))
      (node (ref "IC29") (pin "1") (pinfunction "GND_1") (pintype "power_in"))
      (node (ref "IC29") (pin "21") (pinfunction "BLANK_21") (pintype "input"))
      (node (ref "IC3") (pin "1") (pinfunction "GND_1") (pintype "power_in"))
      (node (ref "IC3") (pin "21") (pinfunction "BLANK_21") (pintype "input"))
      (node (ref "IC30") (pin "1") (pinfunction "GND_1") (pintype "power_in"))
      (node (ref "IC30") (pin "21") (pinfunction "BLANK_21") (pintype "input"))
      (node (ref "IC31") (pin "1") (pinfunction "GND_1") (pintype "power_in"))
      (node (ref "IC31") (pin "21") (pinfunction "BLANK_21") (pintype "input"))
      (node (ref "IC32") (pin "1") (pinfunction "GND_1") (pintype "power_in"))
      (node (ref "IC32") (pin "21") (pinfunction "BLANK_21") (pintype "input"))
      (node (ref "IC33") (pin "1") (pinfunction "GND_1") (pintype "power_in"))
      (node (ref "IC33") (pin "21") (pinfunction "BLANK_21") (pintype "input"))
      (node (ref "IC34") (pin "1") (pinfunction "GND_1") (pintype "power_in"))
      (node (ref "IC34") (pin "21") (pinfunction "BLANK_21") (pintype "input"))
      (node (ref "IC35") (pin "1") (pinfunction "GND_1") (pintype "power_in"))
      (node (ref "IC35") (pin "21") (pinfunction "BLANK_21") (pintype "input"))
      (node (ref "IC36") (pin "1") (pinfunction "GND_1") (pintype "power_in"))
      (node (ref "IC36") (pin "21") (pinfunction "BLANK_21") (pintype "input"))
      (node (ref "IC37") (pin "1") (pinfunction "GND_1") (pintype "power_in"))
      (node (ref "IC37") (pin "21") (pinfunction "BLANK_21") (pintype "input"))
      (node (ref "IC38") (pin "1") (pinfunction "GND_1") (pintype "power_in"))
      (node (ref "IC38") (pin "21") (pinfunction "BLANK_21") (pintype "input"))
      (node (ref "IC39") (pin "1") (pinfunction "GND_1") (pintype "power_in"))
      (node (ref "IC39") (pin "21") (pinfunction "BLANK_21") (pintype "input"))
      (node (ref "IC4") (pin "1") (pinfunction "GND_1") (pintype "power_in"))
      (node (ref "IC4") (pin "21") (pinfunction "BLANK_21") (pintype "input"))
      (node (ref "IC40") (pin "1") (pinfunction "GND_1") (pintype "power_in"))
      (node (ref "IC40") (pin "21") (pinfunction "BLANK_21") (pintype "input"))
      (node (ref "IC41") (pin "1") (pinfunction "GND_1") (pintype "power_in"))
      (node (ref "IC41") (pin "21") (pinfunction "BLANK_21") (pintype "input"))
      (node (ref "IC42") (pin "1") (pinfunction "GND_1") (pintype "power_in"))
      (node (ref "IC42") (pin "21") (pinfunction "BLANK_21") (pintype "input"))
      (node (ref "IC43") (pin "1") (pinfunction "GND_1") (pintype "power_in"))
      (node (ref "IC43") (pin "21") (pinfunction "BLANK_21") (pintype "input"))
      (node (ref "IC44") (pin "1") (pinfunction "GND_1") (pintype "power_in"))
      (node (ref "IC44") (pin "21") (pinfunction "BLANK_21") (pintype "input"))
      (node (ref "IC45") (pin "1") (pinfunction "GND_1") (pintype "power_in"))
      (node (ref "IC45") (pin "21") (pinfunction "BLANK_21") (pintype "input"))
      (node (ref "IC46") (pin "1") (pinfunction "GND_1") (pintype "power_in"))
      (node (ref "IC46") (pin "21") (pinfunction "BLANK_21") (pintype "input"))
      (node (ref "IC47") (pin "1") (pinfunction "GND_1") (pintype "power_in"))
      (node (ref "IC47") (pin "21") (pinfunction "BLANK_21") (pintype "input"))
      (node (ref "IC48") (pin "1") (pinfunction "GND_1") (pintype "power_in"))
      (node (ref "IC48") (pin "21") (pinfunction "BLANK_21") (pintype "input"))
      (node (ref "IC49") (pin "1") (pinfunction "GND_1") (pintype "power_in"))
      (node (ref "IC49") (pin "21") (pinfunction "BLANK_21") (pintype "input"))
      (node (ref "IC5") (pin "1") (pinfunction "GND_1") (pintype "power_in"))
      (node (ref "IC5") (pin "21") (pinfunction "BLANK_21") (pintype "input"))
      (node (ref "IC50") (pin "1") (pinfunction "GND_1") (pintype "power_in"))
      (node (ref "IC50") (pin "21") (pinfunction "BLANK_21") (pintype "input"))
      (node (ref "IC51") (pin "1") (pinfunction "GND_1") (pintype "power_in"))
      (node (ref "IC51") (pin "21") (pinfunction "BLANK_21") (pintype "input"))
      (node (ref "IC52") (pin "1") (pinfunction "GND_1") (pintype "power_in"))
      (node (ref "IC52") (pin "21") (pinfunction "BLANK_21") (pintype "input"))
      (node (ref "IC53") (pin "1") (pinfunction "GND_1") (pintype "power_in"))
      (node (ref "IC53") (pin "21") (pinfunction "BLANK_21") (pintype "input"))
      (node (ref "IC54") (pin "1") (pinfunction "GND_1") (pintype "power_in"))
      (node (ref "IC54") (pin "21") (pinfunction "BLANK_21") (pintype "input"))
      (node (ref "IC55") (pin "1") (pinfunction "GND_1") (pintype "power_in"))
      (node (ref "IC55") (pin "21") (pinfunction "BLANK_21") (pintype "input"))
      (node (ref "IC56") (pin "1") (pinfunction "GND_1") (pintype "power_in"))
      (node (ref "IC56") (pin "21") (pinfunction "BLANK_21") (pintype "input"))
      (node (ref "IC57") (pin "1") (pinfunction "GND_1") (pintype "power_in"))
      (node (ref "IC57") (pin "21") (pinfunction "BLANK_21") (pintype "input"))
      (node (ref "IC58") (pin "1") (pinfunction "GND_1") (pintype "power_in"))
      (node (ref "IC58") (pin "21") (pinfunction "BLANK_21") (pintype "input"))
      (node (ref "IC59") (pin "1") (pinfunction "GND_1") (pintype "power_in"))
      (node (ref "IC59") (pin "21") (pinfunction "BLANK_21") (pintype "input"))
      (node (ref "IC6") (pin "1") (pinfunction "GND_1") (pintype "power_in"))
      (node (ref "IC6") (pin "21") (pinfunction "BLANK_21") (pintype "input"))
      (node (ref "IC60") (pin "1") (pinfunction "GND_1") (pintype "power_in"))
      (node (ref "IC60") (pin "21") (pinfunction "BLANK_21") (pintype "input"))
      (node (ref "IC61") (pin "1") (pinfunction "GND_1") (pintype "power_in"))
      (node (ref "IC61") (pin "21") (pinfunction "BLANK_21") (pintype "input"))
      (node (ref "IC62") (pin "1") (pinfunction "GND_1") (pintype "power_in"))
      (node (ref "IC62") (pin "21") (pinfunction "BLANK_21") (pintype "input"))
      (node (ref "IC63") (pin "1") (pinfunction "GND_1") (pintype "power_in"))
      (node (ref "IC63") (pin "21") (pinfunction "BLANK_21") (pintype "input"))
      (node (ref "IC64") (pin "1") (pinfunction "GND_1") (pintype "power_in"))
      (node (ref "IC64") (pin "21") (pinfunction "BLANK_21") (pintype "input"))
      (node (ref "IC7") (pin "1") (pinfunction "GND_1") (pintype "power_in"))
      (node (ref "IC7") (pin "21") (pinfunction "BLANK_21") (pintype "input"))
      (node (ref "IC8") (pin "1") (pinfunction "GND_1") (pintype "power_in"))
      (node (ref "IC8") (pin "21") (pinfunction "BLANK_21") (pintype "input"))
      (node (ref "IC9") (pin "1") (pinfunction "GND_1") (pintype "power_in"))
      (node (ref "IC9") (pin "21") (pinfunction "BLANK_21") (pintype "input"))
      (node (ref "J1") (pin "6") (pinfunction "VSS_6") (pintype "bidirectional"))
      (node (ref "J1") (pin "G1") (pinfunction "VSS_G1") (pintype "bidirectional"))
      (node (ref "J1") (pin "G2") (pinfunction "VSS_G2") (pintype "bidirectional"))
      (node (ref "J1") (pin "G3") (pinfunction "VSS_G3") (pintype "bidirectional"))
      (node (ref "J1") (pin "G4") (pinfunction "VSS_G4") (pintype "bidirectional"))
      (node (ref "J2") (pin "5") (pinfunction "---GND_5") (pintype "power_in"))
      (node (ref "J2") (pin "SH1") (pinfunction "SHIELD_SH1") (pintype "passive"))
      (node (ref "J2") (pin "SH2") (pinfunction "SHIELD_SH2") (pintype "passive"))
      (node (ref "J2") (pin "SH3") (pinfunction "SHIELD_SH3") (pintype "passive"))
      (node (ref "J2") (pin "SH4") (pinfunction "SHIELD_SH4") (pintype "passive"))
      (node (ref "JP1") (pin "1") (pinfunction "1_1") (pintype "passive"))
      (node (ref "JP2") (pin "4") (pinfunction "4_4") (pintype "passive"))
      (node (ref "P1") (pin "3") (pinfunction "3_3") (pintype "bidirectional"))
      (node (ref "P2") (pin "3") (pinfunction "3_3") (pintype "bidirectional"))
      (node (ref "R12") (pin "2") (pinfunction "2_2") (pintype "passive"))
      (node (ref "R13") (pin "2") (pinfunction "2_2") (pintype "passive"))
      (node (ref "R14") (pin "2") (pinfunction "2_2") (pintype "passive"))
      (node (ref "R15") (pin "2") (pinfunction "2_2") (pintype "passive"))
      (node (ref "R16") (pin "2") (pinfunction "2_2") (pintype "passive"))
      (node (ref "R17") (pin "2") (pinfunction "2_2") (pintype "passive"))
      (node (ref "R18") (pin "2") (pinfunction "2_2") (pintype "passive"))
      (node (ref "R19") (pin "2") (pinfunction "2_2") (pintype "passive"))
      (node (ref "R20") (pin "2") (pinfunction "2_2") (pintype "passive"))
      (node (ref "R21") (pin "2") (pinfunction "2_2") (pintype "passive"))
      (node (ref "R22") (pin "2") (pinfunction "2_2") (pintype "passive"))
      (node (ref "R23") (pin "2") (pinfunction "2_2") (pintype "passive"))
      (node (ref "R24") (pin "2") (pinfunction "2_2") (pintype "passive"))
      (node (ref "R25") (pin "2") (pinfunction "2_2") (pintype "passive"))
      (node (ref "R26") (pin "2") (pinfunction "2_2") (pintype "passive"))
      (node (ref "R27") (pin "2") (pinfunction "2_2") (pintype "passive"))
      (node (ref "R28") (pin "2") (pinfunction "2_2") (pintype "passive"))
      (node (ref "R29") (pin "2") (pinfunction "2_2") (pintype "passive"))
      (node (ref "R30") (pin "2") (pinfunction "2_2") (pintype "passive"))
      (node (ref "R31") (pin "2") (pinfunction "2_2") (pintype "passive"))
      (node (ref "R32") (pin "2") (pinfunction "2_2") (pintype "passive"))
      (node (ref "R33") (pin "2") (pinfunction "2_2") (pintype "passive"))
      (node (ref "R34") (pin "2") (pinfunction "2_2") (pintype "passive"))
      (node (ref "R35") (pin "2") (pinfunction "2_2") (pintype "passive"))
      (node (ref "R36") (pin "2") (pinfunction "2_2") (pintype "passive"))
      (node (ref "R37") (pin "2") (pinfunction "2_2") (pintype "passive"))
      (node (ref "R38") (pin "2") (pinfunction "2_2") (pintype "passive"))
      (node (ref "R39") (pin "2") (pinfunction "2_2") (pintype "passive"))
      (node (ref "R40") (pin "2") (pinfunction "2_2") (pintype "passive"))
      (node (ref "R41") (pin "2") (pinfunction "2_2") (pintype "passive"))
      (node (ref "R42") (pin "2") (pinfunction "2_2") (pintype "passive"))
      (node (ref "R43") (pin "2") (pinfunction "2_2") (pintype "passive"))
      (node (ref "R44") (pin "2") (pinfunction "2_2") (pintype "passive"))
      (node (ref "R45") (pin "2") (pinfunction "2_2") (pintype "passive"))
      (node (ref "R46") (pin "2") (pinfunction "2_2") (pintype "passive"))
      (node (ref "R47") (pin "2") (pinfunction "2_2") (pintype "passive"))
      (node (ref "R48") (pin "2") (pinfunction "2_2") (pintype "passive"))
      (node (ref "R49") (pin "2") (pinfunction "2_2") (pintype "passive"))
      (node (ref "R50") (pin "2") (pinfunction "2_2") (pintype "passive"))
      (node (ref "R51") (pin "2") (pinfunction "2_2") (pintype "passive"))
      (node (ref "R52") (pin "2") (pinfunction "2_2") (pintype "passive"))
      (node (ref "R53") (pin "2") (pinfunction "2_2") (pintype "passive"))
      (node (ref "R54") (pin "2") (pinfunction "2_2") (pintype "passive"))
      (node (ref "R55") (pin "2") (pinfunction "2_2") (pintype "passive"))
      (node (ref "R56") (pin "2") (pinfunction "2_2") (pintype "passive"))
      (node (ref "R57") (pin "2") (pinfunction "2_2") (pintype "passive"))
      (node (ref "R58") (pin "2") (pinfunction "2_2") (pintype "passive"))
      (node (ref "R59") (pin "2") (pinfunction "2_2") (pintype "passive"))
      (node (ref "R60") (pin "2") (pinfunction "2_2") (pintype "passive"))
      (node (ref "R61") (pin "2") (pinfunction "2_2") (pintype "passive"))
      (node (ref "R62") (pin "2") (pinfunction "2_2") (pintype "passive"))
      (node (ref "R63") (pin "2") (pinfunction "2_2") (pintype "passive"))
      (node (ref "R64") (pin "2") (pinfunction "2_2") (pintype "passive"))
      (node (ref "R65") (pin "2") (pinfunction "2_2") (pintype "passive"))
      (node (ref "R66") (pin "2") (pinfunction "2_2") (pintype "passive"))
      (node (ref "R67") (pin "2") (pinfunction "2_2") (pintype "passive"))
      (node (ref "R68") (pin "2") (pinfunction "2_2") (pintype "passive"))
      (node (ref "R69") (pin "2") (pinfunction "2_2") (pintype "passive"))
      (node (ref "R7") (pin "1") (pinfunction "1_1") (pintype "passive"))
      (node (ref "R70") (pin "2") (pinfunction "2_2") (pintype "passive"))
      (node (ref "R71") (pin "2") (pinfunction "2_2") (pintype "passive"))
      (node (ref "R72") (pin "2") (pinfunction "2_2") (pintype "passive"))
      (node (ref "R73") (pin "2") (pinfunction "2_2") (pintype "passive"))
      (node (ref "R74") (pin "2") (pinfunction "2_2") (pintype "passive"))
      (node (ref "R75") (pin "2") (pinfunction "2_2") (pintype "passive"))
      (node (ref "SW1") (pin "1") (pinfunction "1_1") (pintype "passive"))
      (node (ref "SW2") (pin "1") (pinfunction "1_1") (pintype "passive"))
      (node (ref "U2") (pin "1") (pinfunction "GND1_1") (pintype "power_in"))
      (node (ref "U2") (pin "26") (pinfunction "GND2_26") (pintype "power_in"))
      (node (ref "U2") (pin "42") (pinfunction "GND3_42") (pintype "power_in"))
      (node (ref "U2") (pin "43_1") (pinfunction "EXP_43_1") (pintype "power_in"))
      (node (ref "U2") (pin "43_10") (pinfunction "EXP_43_10") (pintype "power_in"))
      (node (ref "U2") (pin "43_11") (pinfunction "EXP_43_11") (pintype "power_in"))
      (node (ref "U2") (pin "43_12") (pinfunction "EXP_43_12") (pintype "power_in"))
      (node (ref "U2") (pin "43_13") (pinfunction "EXP_43_13") (pintype "power_in"))
      (node (ref "U2") (pin "43_14") (pinfunction "EXP_43_14") (pintype "power_in"))
      (node (ref "U2") (pin "43_15") (pinfunction "EXP_43_15") (pintype "power_in"))
      (node (ref "U2") (pin "43_16") (pinfunction "EXP_43_16") (pintype "power_in"))
      (node (ref "U2") (pin "43_17") (pinfunction "EXP_43_17") (pintype "power_in"))
      (node (ref "U2") (pin "43_18") (pinfunction "EXP_43_18") (pintype "power_in"))
      (node (ref "U2") (pin "43_19") (pinfunction "EXP_43_19") (pintype "power_in"))
      (node (ref "U2") (pin "43_2") (pinfunction "EXP_43_2") (pintype "power_in"))
      (node (ref "U2") (pin "43_20") (pinfunction "EXP_43_20") (pintype "power_in"))
      (node (ref "U2") (pin "43_21") (pinfunction "EXP_43_21") (pintype "power_in"))
      (node (ref "U2") (pin "43_3") (pinfunction "EXP_43_3") (pintype "power_in"))
      (node (ref "U2") (pin "43_4") (pinfunction "EXP_43_4") (pintype "power_in"))
      (node (ref "U2") (pin "43_5") (pinfunction "EXP_43_5") (pintype "power_in"))
      (node (ref "U2") (pin "43_6") (pinfunction "EXP_43_6") (pintype "power_in"))
      (node (ref "U2") (pin "43_7") (pinfunction "EXP_43_7") (pintype "power_in"))
      (node (ref "U2") (pin "43_8") (pinfunction "EXP_43_8") (pintype "power_in"))
      (node (ref "U2") (pin "43_9") (pinfunction "EXP_43_9") (pintype "power_in"))
      (node (ref "U3") (pin "2") (pinfunction "VSS_2") (pintype "bidirectional"))
      (node (ref "U5") (pin "1") (pinfunction "GND_1") (pintype "power_in"))
    )
    (net (code "75") (name "IO0") (class "Default")
      (node (ref "C4") (pin "2") (pinfunction "2_2") (pintype "passive"))
      (node (ref "R3") (pin "1") (pinfunction "1_1") (pintype "passive"))
      (node (ref "SW2") (pin "2") (pinfunction "2_2") (pintype "passive"))
      (node (ref "U2") (pin "3") (pinfunction "IO0_3") (pintype "bidirectional"))
    )
    (net (code "76") (name "IR_SENSOR") (class "Default")
      (node (ref "D1") (pin "K") (pinfunction "C_K") (pintype "passive"))
      (node (ref "R1") (pin "1") (pinfunction "1_1") (pintype "passive"))
      (node (ref "U2") (pin "4") (pinfunction "IO1_4") (pintype "bidirectional"))
    )
    (net (code "77") (name "MISO") (class "Default")
      (node (ref "U2") (pin "31") (pinfunction "IO37_31") (pintype "bidirectional"))
    )
    (net (code "78") (name "Net-(D2-K)") (class "Default")
      (node (ref "D2") (pin "C") (pinfunction "K_C") (pintype "passive"))
      (node (ref "L1") (pin "2") (pinfunction "2_2") (pintype "passive"))
      (node (ref "U5") (pin "3") (pinfunction "SW_3") (pintype "output"))
      (node (ref "U5") (pin "6") (pinfunction "SW_6") (pintype "output"))
    )
    (net (code "79") (name "Net-(D3-PadA)") (class "Default")
      (node (ref "D3") (pin "A") (pinfunction "A_A") (pintype "passive"))
      (node (ref "R11") (pin "1") (pinfunction "1_1") (pintype "passive"))
    )
    (net (code "80") (name "Net-(IC1-IREF)") (class "Default")
      (node (ref "IC1") (pin "23") (pinfunction "IREF_23") (pintype "bidirectional"))
      (node (ref "R12") (pin "1") (pinfunction "1_1") (pintype "passive"))
    )
    (net (code "81") (name "Net-(IC1-OUT0)") (class "Default")
      (node (ref "D4") (pin "C") (pinfunction "C_C") (pintype "passive"))
      (node (ref "IC1") (pin "5") (pinfunction "OUT0_5") (pintype "output"))
    )
    (net (code "82") (name "Net-(IC1-OUT1)") (class "Default")
      (node (ref "D5") (pin "C") (pinfunction "C_C") (pintype "passive"))
      (node (ref "IC1") (pin "6") (pinfunction "OUT1_6") (pintype "output"))
    )
    (net (code "83") (name "Net-(IC1-OUT2)") (class "Default")
      (node (ref "D6") (pin "C") (pinfunction "C_C") (pintype "passive"))
      (node (ref "IC1") (pin "7") (pinfunction "OUT2_7") (pintype "output"))
    )
    (net (code "84") (name "Net-(IC1-OUT3)") (class "Default")
      (node (ref "D7") (pin "C") (pinfunction "C_C") (pintype "passive"))
      (node (ref "IC1") (pin "8") (pinfunction "OUT3_8") (pintype "output"))
    )
    (net (code "85") (name "Net-(IC1-OUT4)") (class "Default")
      (node (ref "D8") (pin "C") (pinfunction "C_C") (pintype "passive"))
      (node (ref "IC1") (pin "9") (pinfunction "OUT4_9") (pintype "output"))
    )
    (net (code "86") (name "Net-(IC1-OUT5)") (class "Default")
      (node (ref "D9") (pin "C") (pinfunction "C_C") (pintype "passive"))
      (node (ref "IC1") (pin "10") (pinfunction "OUT5_10") (pintype "output"))
    )
    (net (code "87") (name "Net-(IC1-OUT6)") (class "Default")
      (node (ref "D10") (pin "C") (pinfunction "C_C") (pintype "passive"))
      (node (ref "IC1") (pin "11") (pinfunction "OUT6_11") (pintype "output"))
    )
    (net (code "88") (name "Net-(IC1-OUT7)") (class "Default")
      (node (ref "D11") (pin "C") (pinfunction "C_C") (pintype "passive"))
      (node (ref "IC1") (pin "12") (pinfunction "OUT7_12") (pintype "output"))
    )
    (net (code "89") (name "Net-(IC1-OUT8)") (class "Default")
      (node (ref "D75") (pin "C") (pinfunction "C_C") (pintype "passive"))
      (node (ref "IC1") (pin "13") (pinfunction "OUT8_13") (pintype "output"))
    )
    (net (code "90") (name "Net-(IC1-OUT9)") (class "Default")
      (node (ref "D74") (pin "C") (pinfunction "C_C") (pintype "passive"))
      (node (ref "IC1") (pin "14") (pinfunction "OUT9_14") (pintype "output"))
    )
    (net (code "91") (name "Net-(IC1-OUT10)") (class "Default")
      (node (ref "D73") (pin "C") (pinfunction "C_C") (pintype "passive"))
      (node (ref "IC1") (pin "15") (pinfunction "OUT10_15") (pintype "output"))
    )
    (net (code "92") (name "Net-(IC1-OUT11)") (class "Default")
      (node (ref "D72") (pin "C") (pinfunction "C_C") (pintype "passive"))
      (node (ref "IC1") (pin "16") (pinfunction "OUT11_16") (pintype "output"))
    )
    (net (code "93") (name "Net-(IC1-OUT12)") (class "Default")
      (node (ref "D71") (pin "C") (pinfunction "C_C") (pintype "passive"))
      (node (ref "IC1") (pin "17") (pinfunction "OUT12_17") (pintype "output"))
    )
    (net (code "94") (name "Net-(IC1-OUT13)") (class "Default")
      (node (ref "D70") (pin "C") (pinfunction "C_C") (pintype "passive"))
      (node (ref "IC1") (pin "18") (pinfunction "OUT13_18") (pintype "output"))
    )
    (net (code "95") (name "Net-(IC1-OUT14)") (class "Default")
      (node (ref "D69") (pin "C") (pinfunction "C_C") (pintype "passive"))
      (node (ref "IC1") (pin "19") (pinfunction "OUT14_19") (pintype "output"))
    )
    (net (code "96") (name "Net-(IC1-OUT15)") (class "Default")
      (node (ref "D68") (pin "C") (pinfunction "C_C") (pintype "passive"))
      (node (ref "IC1") (pin "20") (pinfunction "OUT15_20") (pintype "output"))
    )
    (net (code "97") (name "Net-(IC2-IREF)") (class "Default")
      (node (ref "IC2") (pin "23") (pinfunction "IREF_23") (pintype "bidirectional"))
      (node (ref "R13") (pin "1") (pinfunction "1_1") (pintype "passive"))
    )
    (net (code "98") (name "Net-(IC2-OUT0)") (class "Default")
      (node (ref "D12") (pin "C") (pinfunction "C_C") (pintype "passive"))
      (node (ref "IC2") (pin "5") (pinfunction "OUT0_5") (pintype "output"))
    )
    (net (code "99") (name "Net-(IC2-OUT1)") (class "Default")
      (node (ref "D13") (pin "C") (pinfunction "C_C") (pintype "passive"))
      (node (ref "IC2") (pin "6") (pinfunction "OUT1_6") (pintype "output"))
    )
    (net (code "100") (name "Net-(IC2-OUT2)") (class "Default")
      (node (ref "D14") (pin "C") (pinfunction "C_C") (pintype "passive"))
      (node (ref "IC2") (pin "7") (pinfunction "OUT2_7") (pintype "output"))
    )
    (net (code "101") (name "Net-(IC2-OUT3)") (class "Default")
      (node (ref "D15") (pin "C") (pinfunction "C_C") (pintype "passive"))
      (node (ref "IC2") (pin "8") (pinfunction "OUT3_8") (pintype "output"))
    )
    (net (code "102") (name "Net-(IC2-OUT4)") (class "Default")
      (node (ref "D16") (pin "C") (pinfunction "C_C") (pintype "passive"))
      (node (ref "IC2") (pin "9") (pinfunction "OUT4_9") (pintype "output"))
    )
    (net (code "103") (name "Net-(IC2-OUT5)") (class "Default")
      (node (ref "D17") (pin "C") (pinfunction "C_C") (pintype "passive"))
      (node (ref "IC2") (pin "10") (pinfunction "OUT5_10") (pintype "output"))
    )
    (net (code "104") (name "Net-(IC2-OUT6)") (class "Default")
      (node (ref "D18") (pin "C") (pinfunction "C_C") (pintype "passive"))
      (node (ref "IC2") (pin "11") (pinfunction "OUT6_11") (pintype "output"))
    )
    (net (code "105") (name "Net-(IC2-OUT7)") (class "Default")
      (node (ref "D19") (pin "C") (pinfunction "C_C") (pintype "passive"))
      (node (ref "IC2") (pin "12") (pinfunction "OUT7_12") (pintype "output"))
    )
    (net (code "106") (name "Net-(IC2-OUT8)") (class "Default")
      (node (ref "D83") (pin "C") (pinfunction "C_C") (pintype "passive"))
      (node (ref "IC2") (pin "13") (pinfunction "OUT8_13") (pintype "output"))
    )
    (net (code "107") (name "Net-(IC2-OUT9)") (class "Default")
      (node (ref "D82") (pin "C") (pinfunction "C_C") (pintype "passive"))
      (node (ref "IC2") (pin "14") (pinfunction "OUT9_14") (pintype "output"))
    )
    (net (code "108") (name "Net-(IC2-OUT10)") (class "Default")
      (node (ref "D81") (pin "C") (pinfunction "C_C") (pintype "passive"))
      (node (ref "IC2") (pin "15") (pinfunction "OUT10_15") (pintype "output"))
    )
    (net (code "109") (name "Net-(IC2-OUT11)") (class "Default")
      (node (ref "D80") (pin "C") (pinfunction "C_C") (pintype "passive"))
      (node (ref "IC2") (pin "16") (pinfunction "OUT11_16") (pintype "output"))
    )
    (net (code "110") (name "Net-(IC2-OUT12)") (class "Default")
      (node (ref "D79") (pin "C") (pinfunction "C_C") (pintype "passive"))
      (node (ref "IC2") (pin "17") (pinfunction "OUT12_17") (pintype "output"))
    )
    (net (code "111") (name "Net-(IC2-OUT13)") (class "Default")
      (node (ref "D78") (pin "C") (pinfunction "C_C") (pintype "passive"))
      (node (ref "IC2") (pin "18") (pinfunction "OUT13_18") (pintype "output"))
    )
    (net (code "112") (name "Net-(IC2-OUT14)") (class "Default")
      (node (ref "D77") (pin "C") (pinfunction "C_C") (pintype "passive"))
      (node (ref "IC2") (pin "19") (pinfunction "OUT14_19") (pintype "output"))
    )
    (net (code "113") (name "Net-(IC2-OUT15)") (class "Default")
      (node (ref "D76") (pin "C") (pinfunction "C_C") (pintype "passive"))
      (node (ref "IC2") (pin "20") (pinfunction "OUT15_20") (pintype "output"))
    )
    (net (code "114") (name "Net-(IC3-IREF)") (class "Default")
      (node (ref "IC3") (pin "23") (pinfunction "IREF_23") (pintype "bidirectional"))
      (node (ref "R14") (pin "1") (pinfunction "1_1") (pintype "passive"))
    )
    (net (code "115") (name "Net-(IC3-OUT0)") (class "Default")
      (node (ref "D20") (pin "C") (pinfunction "C_C") (pintype "passive"))
      (node (ref "IC3") (pin "5") (pinfunction "OUT0_5") (pintype "output"))
    )
    (net (code "116") (name "Net-(IC3-OUT1)") (class "Default")
      (node (ref "D21") (pin "C") (pinfunction "C_C") (pintype "passive"))
      (node (ref "IC3") (pin "6") (pinfunction "OUT1_6") (pintype "output"))
    )
    (net (code "117") (name "Net-(IC3-OUT2)") (class "Default")
      (node (ref "D22") (pin "C") (pinfunction "C_C") (pintype "passive"))
      (node (ref "IC3") (pin "7") (pinfunction "OUT2_7") (pintype "output"))
    )
    (net (code "118") (name "Net-(IC3-OUT3)") (class "Default")
      (node (ref "D23") (pin "C") (pinfunction "C_C") (pintype "passive"))
      (node (ref "IC3") (pin "8") (pinfunction "OUT3_8") (pintype "output"))
    )
    (net (code "119") (name "Net-(IC3-OUT4)") (class "Default")
      (node (ref "D24") (pin "C") (pinfunction "C_C") (pintype "passive"))
      (node (ref "IC3") (pin "9") (pinfunction "OUT4_9") (pintype "output"))
    )
    (net (code "120") (name "Net-(IC3-OUT5)") (class "Default")
      (node (ref "D25") (pin "C") (pinfunction "C_C") (pintype "passive"))
      (node (ref "IC3") (pin "10") (pinfunction "OUT5_10") (pintype "output"))
    )
    (net (code "121") (name "Net-(IC3-OUT6)") (class "Default")
      (node (ref "D26") (pin "C") (pinfunction "C_C") (pintype "passive"))
      (node (ref "IC3") (pin "11") (pinfunction "OUT6_11") (pintype "output"))
    )
    (net (code "122") (name "Net-(IC3-OUT7)") (class "Default")
      (node (ref "D27") (pin "C") (pinfunction "C_C") (pintype "passive"))
      (node (ref "IC3") (pin "12") (pinfunction "OUT7_12") (pintype "output"))
    )
    (net (code "123") (name "Net-(IC3-OUT8)") (class "Default")
      (node (ref "D91") (pin "C") (pinfunction "C_C") (pintype "passive"))
      (node (ref "IC3") (pin "13") (pinfunction "OUT8_13") (pintype "output"))
    )
    (net (code "124") (name "Net-(IC3-OUT9)") (class "Default")
      (node (ref "D90") (pin "C") (pinfunction "C_C") (pintype "passive"))
      (node (ref "IC3") (pin "14") (pinfunction "OUT9_14") (pintype "output"))
    )
    (net (code "125") (name "Net-(IC3-OUT10)") (class "Default")
      (node (ref "D89") (pin "C") (pinfunction "C_C") (pintype "passive"))
      (node (ref "IC3") (pin "15") (pinfunction "OUT10_15") (pintype "output"))
    )
    (net (code "126") (name "Net-(IC3-OUT11)") (class "Default")
      (node (ref "D88") (pin "C") (pinfunction "C_C") (pintype "passive"))
      (node (ref "IC3") (pin "16") (pinfunction "OUT11_16") (pintype "output"))
    )
    (net (code "127") (name "Net-(IC3-OUT12)") (class "Default")
      (node (ref "D87") (pin "C") (pinfunction "C_C") (pintype "passive"))
      (node (ref "IC3") (pin "17") (pinfunction "OUT12_17") (pintype "output"))
    )
    (net (code "128") (name "Net-(IC3-OUT13)") (class "Default")
      (node (ref "D86") (pin "C") (pinfunction "C_C") (pintype "passive"))
      (node (ref "IC3") (pin "18") (pinfunction "OUT13_18") (pintype "output"))
    )
    (net (code "129") (name "Net-(IC3-OUT14)") (class "Default")
      (node (ref "D85") (pin "C") (pinfunction "C_C") (pintype "passive"))
      (node (ref "IC3") (pin "19") (pinfunction "OUT14_19") (pintype "output"))
    )
    (net (code "130") (name "Net-(IC3-OUT15)") (class "Default")
      (node (ref "D84") (pin "C") (pinfunction "C_C") (pintype "passive"))
      (node (ref "IC3") (pin "20") (pinfunction "OUT15_20") (pintype "output"))
    )
    (net (code "131") (name "Net-(IC4-IREF)") (class "Default")
      (node (ref "IC4") (pin "23") (pinfunction "IREF_23") (pintype "bidirectional"))
      (node (ref "R15") (pin "1") (pinfunction "1_1") (pintype "passive"))
    )
    (net (code "132") (name "Net-(IC4-OUT0)") (class "Default")
      (node (ref "D28") (pin "C") (pinfunction "C_C") (pintype "passive"))
      (node (ref "IC4") (pin "5") (pinfunction "OUT0_5") (pintype "output"))
    )
    (net (code "133") (name "Net-(IC4-OUT1)") (class "Default")
      (node (ref "D29") (pin "C") (pinfunction "C_C") (pintype "passive"))
      (node (ref "IC4") (pin "6") (pinfunction "OUT1_6") (pintype "output"))
    )
    (net (code "134") (name "Net-(IC4-OUT2)") (class "Default")
      (node (ref "D30") (pin "C") (pinfunction "C_C") (pintype "passive"))
      (node (ref "IC4") (pin "7") (pinfunction "OUT2_7") (pintype "output"))
    )
    (net (code "135") (name "Net-(IC4-OUT3)") (class "Default")
      (node (ref "D31") (pin "C") (pinfunction "C_C") (pintype "passive"))
      (node (ref "IC4") (pin "8") (pinfunction "OUT3_8") (pintype "output"))
    )
    (net (code "136") (name "Net-(IC4-OUT4)") (class "Default")
      (node (ref "D32") (pin "C") (pinfunction "C_C") (pintype "passive"))
      (node (ref "IC4") (pin "9") (pinfunction "OUT4_9") (pintype "output"))
    )
    (net (code "137") (name "Net-(IC4-OUT5)") (class "Default")
      (node (ref "D33") (pin "C") (pinfunction "C_C") (pintype "passive"))
      (node (ref "IC4") (pin "10") (pinfunction "OUT5_10") (pintype "output"))
    )
    (net (code "138") (name "Net-(IC4-OUT6)") (class "Default")
      (node (ref "D34") (pin "C") (pinfunction "C_C") (pintype "passive"))
      (node (ref "IC4") (pin "11") (pinfunction "OUT6_11") (pintype "output"))
    )
    (net (code "139") (name "Net-(IC4-OUT7)") (class "Default")
      (node (ref "D35") (pin "C") (pinfunction "C_C") (pintype "passive"))
      (node (ref "IC4") (pin "12") (pinfunction "OUT7_12") (pintype "output"))
    )
    (net (code "140") (name "Net-(IC4-OUT8)") (class "Default")
      (node (ref "D99") (pin "C") (pinfunction "C_C") (pintype "passive"))
      (node (ref "IC4") (pin "13") (pinfunction "OUT8_13") (pintype "output"))
    )
    (net (code "141") (name "Net-(IC4-OUT9)") (class "Default")
      (node (ref "D98") (pin "C") (pinfunction "C_C") (pintype "passive"))
      (node (ref "IC4") (pin "14") (pinfunction "OUT9_14") (pintype "output"))
    )
    (net (code "142") (name "Net-(IC4-OUT10)") (class "Default")
      (node (ref "D97") (pin "C") (pinfunction "C_C") (pintype "passive"))
      (node (ref "IC4") (pin "15") (pinfunction "OUT10_15") (pintype "output"))
    )
    (net (code "143") (name "Net-(IC4-OUT11)") (class "Default")
      (node (ref "D96") (pin "C") (pinfunction "C_C") (pintype "passive"))
      (node (ref "IC4") (pin "16") (pinfunction "OUT11_16") (pintype "output"))
    )
    (net (code "144") (name "Net-(IC4-OUT12)") (class "Default")
      (node (ref "D95") (pin "C") (pinfunction "C_C") (pintype "passive"))
      (node (ref "IC4") (pin "17") (pinfunction "OUT12_17") (pintype "output"))
    )
    (net (code "145") (name "Net-(IC4-OUT13)") (class "Default")
      (node (ref "D94") (pin "C") (pinfunction "C_C") (pintype "passive"))
      (node (ref "IC4") (pin "18") (pinfunction "OUT13_18") (pintype "output"))
    )
    (net (code "146") (name "Net-(IC4-OUT14)") (class "Default")
      (node (ref "D93") (pin "C") (pinfunction "C_C") (pintype "passive"))
      (node (ref "IC4") (pin "19") (pinfunction "OUT14_19") (pintype "output"))
    )
    (net (code "147") (name "Net-(IC4-OUT15)") (class "Default")
      (node (ref "D92") (pin "C") (pinfunction "C_C") (pintype "passive"))
      (node (ref "IC4") (pin "20") (pinfunction "OUT15_20") (pintype "output"))
    )
    (net (code "148") (name "Net-(IC5-IREF)") (class "Default")
      (node (ref "IC5") (pin "23") (pinfunction "IREF_23") (pintype "bidirectional"))
      (node (ref "R16") (pin "1") (pinfunction "1_1") (pintype "passive"))
    )
    (net (code "149") (name "Net-(IC5-OUT0)") (class "Default")
      (node (ref "D36") (pin "C") (pinfunction "C_C") (pintype "passive"))
      (node (ref "IC5") (pin "5") (pinfunction "OUT0_5") (pintype "output"))
    )
    (net (code "150") (name "Net-(IC5-OUT1)") (class "Default")
      (node (ref "D37") (pin "C") (pinfunction "C_C") (pintype "passive"))
      (node (ref "IC5") (pin "6") (pinfunction "OUT1_6") (pintype "output"))
    )
    (net (code "151") (name "Net-(IC5-OUT2)") (class "Default")
      (node (ref "D38") (pin "C") (pinfunction "C_C") (pintype "passive"))
      (node (ref "IC5") (pin "7") (pinfunction "OUT2_7") (pintype "output"))
    )
    (net (code "152") (name "Net-(IC5-OUT3)") (class "Default")
      (node (ref "D39") (pin "C") (pinfunction "C_C") (pintype "passive"))
      (node (ref "IC5") (pin "8") (pinfunction "OUT3_8") (pintype "output"))
    )
    (net (code "153") (name "Net-(IC5-OUT4)") (class "Default")
      (node (ref "D40") (pin "C") (pinfunction "C_C") (pintype "passive"))
      (node (ref "IC5") (pin "9") (pinfunction "OUT4_9") (pintype "output"))
    )
    (net (code "154") (name "Net-(IC5-OUT5)") (class "Default")
      (node (ref "D41") (pin "C") (pinfunction "C_C") (pintype "passive"))
      (node (ref "IC5") (pin "10") (pinfunction "OUT5_10") (pintype "output"))
    )
    (net (code "155") (name "Net-(IC5-OUT6)") (class "Default")
      (node (ref "D42") (pin "C") (pinfunction "C_C") (pintype "passive"))
      (node (ref "IC5") (pin "11") (pinfunction "OUT6_11") (pintype "output"))
    )
    (net (code "156") (name "Net-(IC5-OUT7)") (class "Default")
      (node (ref "D43") (pin "C") (pinfunction "C_C") (pintype "passive"))
      (node (ref "IC5") (pin "12") (pinfunction "OUT7_12") (pintype "output"))
    )
    (net (code "157") (name "Net-(IC5-OUT8)") (class "Default")
      (node (ref "D107") (pin "C") (pinfunction "C_C") (pintype "passive"))
      (node (ref "IC5") (pin "13") (pinfunction "OUT8_13") (pintype "output"))
    )
    (net (code "158") (name "Net-(IC5-OUT9)") (class "Default")
      (node (ref "D106") (pin "C") (pinfunction "C_C") (pintype "passive"))
      (node (ref "IC5") (pin "14") (pinfunction "OUT9_14") (pintype "output"))
    )
    (net (code "159") (name "Net-(IC5-OUT10)") (class "Default")
      (node (ref "D105") (pin "C") (pinfunction "C_C") (pintype "passive"))
      (node (ref "IC5") (pin "15") (pinfunction "OUT10_15") (pintype "output"))
    )
    (net (code "160") (name "Net-(IC5-OUT11)") (class "Default")
      (node (ref "D104") (pin "C") (pinfunction "C_C") (pintype "passive"))
      (node (ref "IC5") (pin "16") (pinfunction "OUT11_16") (pintype "output"))
    )
    (net (code "161") (name "Net-(IC5-OUT12)") (class "Default")
      (node (ref "D103") (pin "C") (pinfunction "C_C") (pintype "passive"))
      (node (ref "IC5") (pin "17") (pinfunction "OUT12_17") (pintype "output"))
    )
    (net (code "162") (name "Net-(IC5-OUT13)") (class "Default")
      (node (ref "D102") (pin "C") (pinfunction "C_C") (pintype "passive"))
      (node (ref "IC5") (pin "18") (pinfunction "OUT13_18") (pintype "output"))
    )
    (net (code "163") (name "Net-(IC5-OUT14)") (class "Default")
      (node (ref "D101") (pin "C") (pinfunction "C_C") (pintype "passive"))
      (node (ref "IC5") (pin "19") (pinfunction "OUT14_19") (pintype "output"))
    )
    (net (code "164") (name "Net-(IC5-OUT15)") (class "Default")
      (node (ref "D100") (pin "C") (pinfunction "C_C") (pintype "passive"))
      (node (ref "IC5") (pin "20") (pinfunction "OUT15_20") (pintype "output"))
    )
    (net (code "165") (name "Net-(IC6-IREF)") (class "Default")
      (node (ref "IC6") (pin "23") (pinfunction "IREF_23") (pintype "bidirectional"))
      (node (ref "R17") (pin "1") (pinfunction "1_1") (pintype "passive"))
    )
    (net (code "166") (name "Net-(IC6-OUT0)") (class "Default")
      (node (ref "D44") (pin "C") (pinfunction "C_C") (pintype "passive"))
      (node (ref "IC6") (pin "5") (pinfunction "OUT0_5") (pintype "output"))
    )
    (net (code "167") (name "Net-(IC6-OUT1)") (class "Default")
      (node (ref "D45") (pin "C") (pinfunction "C_C") (pintype "passive"))
      (node (ref "IC6") (pin "6") (pinfunction "OUT1_6") (pintype "output"))
    )
    (net (code "168") (name "Net-(IC6-OUT2)") (class "Default")
      (node (ref "D46") (pin "C") (pinfunction "C_C") (pintype "passive"))
      (node (ref "IC6") (pin "7") (pinfunction "OUT2_7") (pintype "output"))
    )
    (net (code "169") (name "Net-(IC6-OUT3)") (class "Default")
      (node (ref "D47") (pin "C") (pinfunction "C_C") (pintype "passive"))
      (node (ref "IC6") (pin "8") (pinfunction "OUT3_8") (pintype "output"))
    )
    (net (code "170") (name "Net-(IC6-OUT4)") (class "Default")
      (node (ref "D48") (pin "C") (pinfunction "C_C") (pintype "passive"))
      (node (ref "IC6") (pin "9") (pinfunction "OUT4_9") (pintype "output"))
    )
    (net (code "171") (name "Net-(IC6-OUT5)") (class "Default")
      (node (ref "D49") (pin "C") (pinfunction "C_C") (pintype "passive"))
      (node (ref "IC6") (pin "10") (pinfunction "OUT5_10") (pintype "output"))
    )
    (net (code "172") (name "Net-(IC6-OUT6)") (class "Default")
      (node (ref "D50") (pin "C") (pinfunction "C_C") (pintype "passive"))
      (node (ref "IC6") (pin "11") (pinfunction "OUT6_11") (pintype "output"))
    )
    (net (code "173") (name "Net-(IC6-OUT7)") (class "Default")
      (node (ref "D51") (pin "C") (pinfunction "C_C") (pintype "passive"))
      (node (ref "IC6") (pin "12") (pinfunction "OUT7_12") (pintype "output"))
    )
    (net (code "174") (name "Net-(IC6-OUT8)") (class "Default")
      (node (ref "D115") (pin "C") (pinfunction "C_C") (pintype "passive"))
      (node (ref "IC6") (pin "13") (pinfunction "OUT8_13") (pintype "output"))
    )
    (net (code "175") (name "Net-(IC6-OUT9)") (class "Default")
      (node (ref "D114") (pin "C") (pinfunction "C_C") (pintype "passive"))
      (node (ref "IC6") (pin "14") (pinfunction "OUT9_14") (pintype "output"))
    )
    (net (code "176") (name "Net-(IC6-OUT10)") (class "Default")
      (node (ref "D113") (pin "C") (pinfunction "C_C") (pintype "passive"))
      (node (ref "IC6") (pin "15") (pinfunction "OUT10_15") (pintype "output"))
    )
    (net (code "177") (name "Net-(IC6-OUT11)") (class "Default")
      (node (ref "D112") (pin "C") (pinfunction "C_C") (pintype "passive"))
      (node (ref "IC6") (pin "16") (pinfunction "OUT11_16") (pintype "output"))
    )
    (net (code "178") (name "Net-(IC6-OUT12)") (class "Default")
      (node (ref "D111") (pin "C") (pinfunction "C_C") (pintype "passive"))
      (node (ref "IC6") (pin "17") (pinfunction "OUT12_17") (pintype "output"))
    )
    (net (code "179") (name "Net-(IC6-OUT13)") (class "Default")
      (node (ref "D110") (pin "C") (pinfunction "C_C") (pintype "passive"))
      (node (ref "IC6") (pin "18") (pinfunction "OUT13_18") (pintype "output"))
    )
    (net (code "180") (name "Net-(IC6-OUT14)") (class "Default")
      (node (ref "D109") (pin "C") (pinfunction "C_C") (pintype "passive"))
      (node (ref "IC6") (pin "19") (pinfunction "OUT14_19") (pintype "output"))
    )
    (net (code "181") (name "Net-(IC6-OUT15)") (class "Default")
      (node (ref "D108") (pin "C") (pinfunction "C_C") (pintype "passive"))
      (node (ref "IC6") (pin "20") (pinfunction "OUT15_20") (pintype "output"))
    )
    (net (code "182") (name "Net-(IC7-IREF)") (class "Default")
      (node (ref "IC7") (pin "23") (pinfunction "IREF_23") (pintype "bidirectional"))
      (node (ref "R18") (pin "1") (pinfunction "1_1") (pintype "passive"))
    )
    (net (code "183") (name "Net-(IC7-OUT0)") (class "Default")
      (node (ref "D52") (pin "C") (pinfunction "C_C") (pintype "passive"))
      (node (ref "IC7") (pin "5") (pinfunction "OUT0_5") (pintype "output"))
    )
    (net (code "184") (name "Net-(IC7-OUT1)") (class "Default")
      (node (ref "D53") (pin "C") (pinfunction "C_C") (pintype "passive"))
      (node (ref "IC7") (pin "6") (pinfunction "OUT1_6") (pintype "output"))
    )
    (net (code "185") (name "Net-(IC7-OUT2)") (class "Default")
      (node (ref "D54") (pin "C") (pinfunction "C_C") (pintype "passive"))
      (node (ref "IC7") (pin "7") (pinfunction "OUT2_7") (pintype "output"))
    )
    (net (code "186") (name "Net-(IC7-OUT3)") (class "Default")
      (node (ref "D55") (pin "C") (pinfunction "C_C") (pintype "passive"))
      (node (ref "IC7") (pin "8") (pinfunction "OUT3_8") (pintype "output"))
    )
    (net (code "187") (name "Net-(IC7-OUT4)") (class "Default")
      (node (ref "D56") (pin "C") (pinfunction "C_C") (pintype "passive"))
      (node (ref "IC7") (pin "9") (pinfunction "OUT4_9") (pintype "output"))
    )
    (net (code "188") (name "Net-(IC7-OUT5)") (class "Default")
      (node (ref "D57") (pin "C") (pinfunction "C_C") (pintype "passive"))
      (node (ref "IC7") (pin "10") (pinfunction "OUT5_10") (pintype "output"))
    )
    (net (code "189") (name "Net-(IC7-OUT6)") (class "Default")
      (node (ref "D58") (pin "C") (pinfunction "C_C") (pintype "passive"))
      (node (ref "IC7") (pin "11") (pinfunction "OUT6_11") (pintype "output"))
    )
    (net (code "190") (name "Net-(IC7-OUT7)") (class "Default")
      (node (ref "D59") (pin "C") (pinfunction "C_C") (pintype "passive"))
      (node (ref "IC7") (pin "12") (pinfunction "OUT7_12") (pintype "output"))
    )
    (net (code "191") (name "Net-(IC7-OUT8)") (class "Default")
      (node (ref "D123") (pin "C") (pinfunction "C_C") (pintype "passive"))
      (node (ref "IC7") (pin "13") (pinfunction "OUT8_13") (pintype "output"))
    )
    (net (code "192") (name "Net-(IC7-OUT9)") (class "Default")
      (node (ref "D122") (pin "C") (pinfunction "C_C") (pintype "passive"))
      (node (ref "IC7") (pin "14") (pinfunction "OUT9_14") (pintype "output"))
    )
    (net (code "193") (name "Net-(IC7-OUT10)") (class "Default")
      (node (ref "D121") (pin "C") (pinfunction "C_C") (pintype "passive"))
      (node (ref "IC7") (pin "15") (pinfunction "OUT10_15") (pintype "output"))
    )
    (net (code "194") (name "Net-(IC7-OUT11)") (class "Default")
      (node (ref "D120") (pin "C") (pinfunction "C_C") (pintype "passive"))
      (node (ref "IC7") (pin "16") (pinfunction "OUT11_16") (pintype "output"))
    )
    (net (code "195") (name "Net-(IC7-OUT12)") (class "Default")
      (node (ref "D119") (pin "C") (pinfunction "C_C") (pintype "passive"))
      (node (ref "IC7") (pin "17") (pinfunction "OUT12_17") (pintype "output"))
    )
    (net (code "196") (name "Net-(IC7-OUT13)") (class "Default")
      (node (ref "D118") (pin "C") (pinfunction "C_C") (pintype "passive"))
      (node (ref "IC7") (pin "18") (pinfunction "OUT13_18") (pintype "output"))
    )
    (net (code "197") (name "Net-(IC7-OUT14)") (class "Default")
      (node (ref "D117") (pin "C") (pinfunction "C_C") (pintype "passive"))
      (node (ref "IC7") (pin "19") (pinfunction "OUT14_19") (pintype "output"))
    )
    (net (code "198") (name "Net-(IC7-OUT15)") (class "Default")
      (node (ref "D116") (pin "C") (pinfunction "C_C") (pintype "passive"))
      (node (ref "IC7") (pin "20") (pinfunction "OUT15_20") (pintype "output"))
    )
    (net (code "199") (name "Net-(IC8-IREF)") (class "Default")
      (node (ref "IC8") (pin "23") (pinfunction "IREF_23") (pintype "bidirectional"))
      (node (ref "R19") (pin "1") (pinfunction "1_1") (pintype "passive"))
    )
    (net (code "200") (name "Net-(IC8-OUT0)") (class "Default")
      (node (ref "D60") (pin "C") (pinfunction "C_C") (pintype "passive"))
      (node (ref "IC8") (pin "5") (pinfunction "OUT0_5") (pintype "output"))
    )
    (net (code "201") (name "Net-(IC8-OUT1)") (class "Default")
      (node (ref "D61") (pin "C") (pinfunction "C_C") (pintype "passive"))
      (node (ref "IC8") (pin "6") (pinfunction "OUT1_6") (pintype "output"))
    )
    (net (code "202") (name "Net-(IC8-OUT2)") (class "Default")
      (node (ref "D62") (pin "C") (pinfunction "C_C") (pintype "passive"))
      (node (ref "IC8") (pin "7") (pinfunction "OUT2_7") (pintype "output"))
    )
    (net (code "203") (name "Net-(IC8-OUT3)") (class "Default")
      (node (ref "D63") (pin "C") (pinfunction "C_C") (pintype "passive"))
      (node (ref "IC8") (pin "8") (pinfunction "OUT3_8") (pintype "output"))
    )
    (net (code "204") (name "Net-(IC8-OUT4)") (class "Default")
      (node (ref "D64") (pin "C") (pinfunction "C_C") (pintype "passive"))
      (node (ref "IC8") (pin "9") (pinfunction "OUT4_9") (pintype "output"))
    )
    (net (code "205") (name "Net-(IC8-OUT5)") (class "Default")
      (node (ref "D65") (pin "C") (pinfunction "C_C") (pintype "passive"))
      (node (ref "IC8") (pin "10") (pinfunction "OUT5_10") (pintype "output"))
    )
    (net (code "206") (name "Net-(IC8-OUT6)") (class "Default")
      (node (ref "D66") (pin "C") (pinfunction "C_C") (pintype "passive"))
      (node (ref "IC8") (pin "11") (pinfunction "OUT6_11") (pintype "output"))
    )
    (net (code "207") (name "Net-(IC8-OUT7)") (class "Default")
      (node (ref "D67") (pin "C") (pinfunction "C_C") (pintype "passive"))
      (node (ref "IC8") (pin "12") (pinfunction "OUT7_12") (pintype "output"))
    )
    (net (code "208") (name "Net-(IC8-OUT8)") (class "Default")
      (node (ref "D131") (pin "C") (pinfunction "C_C") (pintype "passive"))
      (node (ref "IC8") (pin "13") (pinfunction "OUT8_13") (pintype "output"))
    )
    (net (code "209") (name "Net-(IC8-OUT9)") (class "Default")
      (node (ref "D130") (pin "C") (pinfunction "C_C") (pintype "passive"))
      (node (ref "IC8") (pin "14") (pinfunction "OUT9_14") (pintype "output"))
    )
    (net (code "210") (name "Net-(IC8-OUT10)") (class "Default")
      (node (ref "D129") (pin "C") (pinfunction "C_C") (pintype "passive"))
      (node (ref "IC8") (pin "15") (pinfunction "OUT10_15") (pintype "output"))
    )
    (net (code "211") (name "Net-(IC8-OUT11)") (class "Default")
      (node (ref "D128") (pin "C") (pinfunction "C_C") (pintype "passive"))
      (node (ref "IC8") (pin "16") (pinfunction "OUT11_16") (pintype "output"))
    )
    (net (code "212") (name "Net-(IC8-OUT12)") (class "Default")
      (node (ref "D127") (pin "C") (pinfunction "C_C") (pintype "passive"))
      (node (ref "IC8") (pin "17") (pinfunction "OUT12_17") (pintype "output"))
    )
    (net (code "213") (name "Net-(IC8-OUT13)") (class "Default")
      (node (ref "D126") (pin "C") (pinfunction "C_C") (pintype "passive"))
      (node (ref "IC8") (pin "18") (pinfunction "OUT13_18") (pintype "output"))
    )
    (net (code "214") (name "Net-(IC8-OUT14)") (class "Default")
      (node (ref "D125") (pin "C") (pinfunction "C_C") (pintype "passive"))
      (node (ref "IC8") (pin "19") (pinfunction "OUT14_19") (pintype "output"))
    )
    (net (code "215") (name "Net-(IC8-OUT15)") (class "Default")
      (node (ref "D124") (pin "C") (pinfunction "C_C") (pintype "passive"))
      (node (ref "IC8") (pin "20") (pinfunction "OUT15_20") (pintype "output"))
    )
    (net (code "216") (name "Net-(IC9-IREF)") (class "Default")
      (node (ref "IC9") (pin "23") (pinfunction "IREF_23") (pintype "bidirectional"))
      (node (ref "R20") (pin "1") (pinfunction "1_1") (pintype "passive"))
    )
    (net (code "217") (name "Net-(IC9-OUT0)") (class "Default")
      (node (ref "D132") (pin "C") (pinfunction "C_C") (pintype "passive"))
      (node (ref "IC9") (pin "5") (pinfunction "OUT0_5") (pintype "output"))
    )
    (net (code "218") (name "Net-(IC9-OUT1)") (class "Default")
      (node (ref "D133") (pin "C") (pinfunction "C_C") (pintype "passive"))
      (node (ref "IC9") (pin "6") (pinfunction "OUT1_6") (pintype "output"))
    )
    (net (code "219") (name "Net-(IC9-OUT2)") (class "Default")
      (node (ref "D134") (pin "C") (pinfunction "C_C") (pintype "passive"))
      (node (ref "IC9") (pin "7") (pinfunction "OUT2_7") (pintype "output"))
    )
    (net (code "220") (name "Net-(IC9-OUT3)") (class "Default")
      (node (ref "D135") (pin "C") (pinfunction "C_C") (pintype "passive"))
      (node (ref "IC9") (pin "8") (pinfunction "OUT3_8") (pintype "output"))
    )
    (net (code "221") (name "Net-(IC9-OUT4)") (class "Default")
      (node (ref "D136") (pin "C") (pinfunction "C_C") (pintype "passive"))
      (node (ref "IC9") (pin "9") (pinfunction "OUT4_9") (pintype "output"))
    )
    (net (code "222") (name "Net-(IC9-OUT5)") (class "Default")
      (node (ref "D137") (pin "C") (pinfunction "C_C") (pintype "passive"))
      (node (ref "IC9") (pin "10") (pinfunction "OUT5_10") (pintype "output"))
    )
    (net (code "223") (name "Net-(IC9-OUT6)") (class "Default")
      (node (ref "D138") (pin "C") (pinfunction "C_C") (pintype "passive"))
      (node (ref "IC9") (pin "11") (pinfunction "OUT6_11") (pintype "output"))
    )
    (net (code "224") (name "Net-(IC9-OUT7)") (class "Default")
      (node (ref "D139") (pin "C") (pinfunction "C_C") (pintype "passive"))
      (node (ref "IC9") (pin "12") (pinfunction "OUT7_12") (pintype "output"))
    )
    (net (code "225") (name "Net-(IC9-OUT8)") (class "Default")
      (node (ref "D203") (pin "C") (pinfunction "C_C") (pintype "passive"))
      (node (ref "IC9") (pin "13") (pinfunction "OUT8_13") (pintype "output"))
    )
    (net (code "226") (name "Net-(IC9-OUT9)") (class "Default")
      (node (ref "D202") (pin "C") (pinfunction "C_C") (pintype "passive"))
      (node (ref "IC9") (pin "14") (pinfunction "OUT9_14") (pintype "output"))
    )
    (net (code "227") (name "Net-(IC9-OUT10)") (class "Default")
      (node (ref "D201") (pin "C") (pinfunction "C_C") (pintype "passive"))
      (node (ref "IC9") (pin "15") (pinfunction "OUT10_15") (pintype "output"))
    )
    (net (code "228") (name "Net-(IC9-OUT11)") (class "Default")
      (node (ref "D200") (pin "C") (pinfunction "C_C") (pintype "passive"))
      (node (ref "IC9") (pin "16") (pinfunction "OUT11_16") (pintype "output"))
    )
    (net (code "229") (name "Net-(IC9-OUT12)") (class "Default")
      (node (ref "D199") (pin "C") (pinfunction "C_C") (pintype "passive"))
      (node (ref "IC9") (pin "17") (pinfunction "OUT12_17") (pintype "output"))
    )
    (net (code "230") (name "Net-(IC9-OUT13)") (class "Default")
      (node (ref "D198") (pin "C") (pinfunction "C_C") (pintype "passive"))
      (node (ref "IC9") (pin "18") (pinfunction "OUT13_18") (pintype "output"))
    )
    (net (code "231") (name "Net-(IC9-OUT14)") (class "Default")
      (node (ref "D197") (pin "C") (pinfunction "C_C") (pintype "passive"))
      (node (ref "IC9") (pin "19") (pinfunction "OUT14_19") (pintype "output"))
    )
    (net (code "232") (name "Net-(IC9-OUT15)") (class "Default")
      (node (ref "D196") (pin "C") (pinfunction "C_C") (pintype "passive"))
      (node (ref "IC9") (pin "20") (pinfunction "OUT15_20") (pintype "output"))
    )
    (net (code "233") (name "Net-(IC10-IREF)") (class "Default")
      (node (ref "IC10") (pin "23") (pinfunction "IREF_23") (pintype "bidirectional"))
      (node (ref "R21") (pin "1") (pinfunction "1_1") (pintype "passive"))
    )
    (net (code "234") (name "Net-(IC10-OUT0)") (class "Default")
      (node (ref "D140") (pin "C") (pinfunction "C_C") (pintype "passive"))
      (node (ref "IC10") (pin "5") (pinfunction "OUT0_5") (pintype "output"))
    )
    (net (code "235") (name "Net-(IC10-OUT1)") (class "Default")
      (node (ref "D141") (pin "C") (pinfunction "C_C") (pintype "passive"))
      (node (ref "IC10") (pin "6") (pinfunction "OUT1_6") (pintype "output"))
    )
    (net (code "236") (name "Net-(IC10-OUT2)") (class "Default")
      (node (ref "D142") (pin "C") (pinfunction "C_C") (pintype "passive"))
      (node (ref "IC10") (pin "7") (pinfunction "OUT2_7") (pintype "output"))
    )
    (net (code "237") (name "Net-(IC10-OUT3)") (class "Default")
      (node (ref "D143") (pin "C") (pinfunction "C_C") (pintype "passive"))
      (node (ref "IC10") (pin "8") (pinfunction "OUT3_8") (pintype "output"))
    )
    (net (code "238") (name "Net-(IC10-OUT4)") (class "Default")
      (node (ref "D144") (pin "C") (pinfunction "C_C") (pintype "passive"))
      (node (ref "IC10") (pin "9") (pinfunction "OUT4_9") (pintype "output"))
    )
    (net (code "239") (name "Net-(IC10-OUT5)") (class "Default")
      (node (ref "D145") (pin "C") (pinfunction "C_C") (pintype "passive"))
      (node (ref "IC10") (pin "10") (pinfunction "OUT5_10") (pintype "output"))
    )
    (net (code "240") (name "Net-(IC10-OUT6)") (class "Default")
      (node (ref "D146") (pin "C") (pinfunction "C_C") (pintype "passive"))
      (node (ref "IC10") (pin "11") (pinfunction "OUT6_11") (pintype "output"))
    )
    (net (code "241") (name "Net-(IC10-OUT7)") (class "Default")
      (node (ref "D147") (pin "C") (pinfunction "C_C") (pintype "passive"))
      (node (ref "IC10") (pin "12") (pinfunction "OUT7_12") (pintype "output"))
    )
    (net (code "242") (name "Net-(IC10-OUT8)") (class "Default")
      (node (ref "D211") (pin "C") (pinfunction "C_C") (pintype "passive"))
      (node (ref "IC10") (pin "13") (pinfunction "OUT8_13") (pintype "output"))
    )
    (net (code "243") (name "Net-(IC10-OUT9)") (class "Default")
      (node (ref "D210") (pin "C") (pinfunction "C_C") (pintype "passive"))
      (node (ref "IC10") (pin "14") (pinfunction "OUT9_14") (pintype "output"))
    )
    (net (code "244") (name "Net-(IC10-OUT10)") (class "Default")
      (node (ref "D209") (pin "C") (pinfunction "C_C") (pintype "passive"))
      (node (ref "IC10") (pin "15") (pinfunction "OUT10_15") (pintype "output"))
    )
    (net (code "245") (name "Net-(IC10-OUT11)") (class "Default")
      (node (ref "D208") (pin "C") (pinfunction "C_C") (pintype "passive"))
      (node (ref "IC10") (pin "16") (pinfunction "OUT11_16") (pintype "output"))
    )
    (net (code "246") (name "Net-(IC10-OUT12)") (class "Default")
      (node (ref "D207") (pin "C") (pinfunction "C_C") (pintype "passive"))
      (node (ref "IC10") (pin "17") (pinfunction "OUT12_17") (pintype "output"))
    )
    (net (code "247") (name "Net-(IC10-OUT13)") (class "Default")
      (node (ref "D206") (pin "C") (pinfunction "C_C") (pintype "passive"))
      (node (ref "IC10") (pin "18") (pinfunction "OUT13_18") (pintype "output"))
    )
    (net (code "248") (name "Net-(IC10-OUT14)") (class "Default")
      (node (ref "D205") (pin "C") (pinfunction "C_C") (pintype "passive"))
      (node (ref "IC10") (pin "19") (pinfunction "OUT14_19") (pintype "output"))
    )
    (net (code "249") (name "Net-(IC10-OUT15)") (class "Default")
      (node (ref "D204") (pin "C") (pinfunction "C_C") (pintype "passive"))
      (node (ref "IC10") (pin "20") (pinfunction "OUT15_20") (pintype "output"))
    )
    (net (code "250") (name "Net-(IC11-IREF)") (class "Default")
      (node (ref "IC11") (pin "23") (pinfunction "IREF_23") (pintype "bidirectional"))
      (node (ref "R22") (pin "1") (pinfunction "1_1") (pintype "passive"))
    )
    (net (code "251") (name "Net-(IC11-OUT0)") (class "Default")
      (node (ref "D148") (pin "C") (pinfunction "C_C") (pintype "passive"))
      (node (ref "IC11") (pin "5") (pinfunction "OUT0_5") (pintype "output"))
    )
    (net (code "252") (name "Net-(IC11-OUT1)") (class "Default")
      (node (ref "D149") (pin "C") (pinfunction "C_C") (pintype "passive"))
      (node (ref "IC11") (pin "6") (pinfunction "OUT1_6") (pintype "output"))
    )
    (net (code "253") (name "Net-(IC11-OUT2)") (class "Default")
      (node (ref "D150") (pin "C") (pinfunction "C_C") (pintype "passive"))
      (node (ref "IC11") (pin "7") (pinfunction "OUT2_7") (pintype "output"))
    )
    (net (code "254") (name "Net-(IC11-OUT3)") (class "Default")
      (node (ref "D151") (pin "C") (pinfunction "C_C") (pintype "passive"))
      (node (ref "IC11") (pin "8") (pinfunction "OUT3_8") (pintype "output"))
    )
    (net (code "255") (name "Net-(IC11-OUT4)") (class "Default")
      (node (ref "D152") (pin "C") (pinfunction "C_C") (pintype "passive"))
      (node (ref "IC11") (pin "9") (pinfunction "OUT4_9") (pintype "output"))
    )
    (net (code "256") (name "Net-(IC11-OUT5)") (class "Default")
      (node (ref "D153") (pin "C") (pinfunction "C_C") (pintype "passive"))
      (node (ref "IC11") (pin "10") (pinfunction "OUT5_10") (pintype "output"))
    )
    (net (code "257") (name "Net-(IC11-OUT6)") (class "Default")
      (node (ref "D154") (pin "C") (pinfunction "C_C") (pintype "passive"))
      (node (ref "IC11") (pin "11") (pinfunction "OUT6_11") (pintype "output"))
    )
    (net (code "258") (name "Net-(IC11-OUT7)") (class "Default")
      (node (ref "D155") (pin "C") (pinfunction "C_C") (pintype "passive"))
      (node (ref "IC11") (pin "12") (pinfunction "OUT7_12") (pintype "output"))
    )
    (net (code "259") (name "Net-(IC11-OUT8)") (class "Default")
      (node (ref "D219") (pin "C") (pinfunction "C_C") (pintype "passive"))
      (node (ref "IC11") (pin "13") (pinfunction "OUT8_13") (pintype "output"))
    )
    (net (code "260") (name "Net-(IC11-OUT9)") (class "Default")
      (node (ref "D218") (pin "C") (pinfunction "C_C") (pintype "passive"))
      (node (ref "IC11") (pin "14") (pinfunction "OUT9_14") (pintype "output"))
    )
    (net (code "261") (name "Net-(IC11-OUT10)") (class "Default")
      (node (ref "D217") (pin "C") (pinfunction "C_C") (pintype "passive"))
      (node (ref "IC11") (pin "15") (pinfunction "OUT10_15") (pintype "output"))
    )
    (net (code "262") (name "Net-(IC11-OUT11)") (class "Default")
      (node (ref "D216") (pin "C") (pinfunction "C_C") (pintype "passive"))
      (node (ref "IC11") (pin "16") (pinfunction "OUT11_16") (pintype "output"))
    )
    (net (code "263") (name "Net-(IC11-OUT12)") (class "Default")
      (node (ref "D215") (pin "C") (pinfunction "C_C") (pintype "passive"))
      (node (ref "IC11") (pin "17") (pinfunction "OUT12_17") (pintype "output"))
    )
    (net (code "264") (name "Net-(IC11-OUT13)") (class "Default")
      (node (ref "D214") (pin "C") (pinfunction "C_C") (pintype "passive"))
      (node (ref "IC11") (pin "18") (pinfunction "OUT13_18") (pintype "output"))
    )
    (net (code "265") (name "Net-(IC11-OUT14)") (class "Default")
      (node (ref "D213") (pin "C") (pinfunction "C_C") (pintype "passive"))
      (node (ref "IC11") (pin "19") (pinfunction "OUT14_19") (pintype "output"))
    )
    (net (code "266") (name "Net-(IC11-OUT15)") (class "Default")
      (node (ref "D212") (pin "C") (pinfunction "C_C") (pintype "passive"))
      (node (ref "IC11") (pin "20") (pinfunction "OUT15_20") (pintype "output"))
    )
    (net (code "267") (name "Net-(IC12-IREF)") (class "Default")
      (node (ref "IC12") (pin "23") (pinfunction "IREF_23") (pintype "bidirectional"))
      (node (ref "R23") (pin "1") (pinfunction "1_1") (pintype "passive"))
    )
    (net (code "268") (name "Net-(IC12-OUT0)") (class "Default")
      (node (ref "D156") (pin "C") (pinfunction "C_C") (pintype "passive"))
      (node (ref "IC12") (pin "5") (pinfunction "OUT0_5") (pintype "output"))
    )
    (net (code "269") (name "Net-(IC12-OUT1)") (class "Default")
      (node (ref "D157") (pin "C") (pinfunction "C_C") (pintype "passive"))
      (node (ref "IC12") (pin "6") (pinfunction "OUT1_6") (pintype "output"))
    )
    (net (code "270") (name "Net-(IC12-OUT2)") (class "Default")
      (node (ref "D158") (pin "C") (pinfunction "C_C") (pintype "passive"))
      (node (ref "IC12") (pin "7") (pinfunction "OUT2_7") (pintype "output"))
    )
    (net (code "271") (name "Net-(IC12-OUT3)") (class "Default")
      (node (ref "D159") (pin "C") (pinfunction "C_C") (pintype "passive"))
      (node (ref "IC12") (pin "8") (pinfunction "OUT3_8") (pintype "output"))
    )
    (net (code "272") (name "Net-(IC12-OUT4)") (class "Default")
      (node (ref "D160") (pin "C") (pinfunction "C_C") (pintype "passive"))
      (node (ref "IC12") (pin "9") (pinfunction "OUT4_9") (pintype "output"))
    )
    (net (code "273") (name "Net-(IC12-OUT5)") (class "Default")
      (node (ref "D161") (pin "C") (pinfunction "C_C") (pintype "passive"))
      (node (ref "IC12") (pin "10") (pinfunction "OUT5_10") (pintype "output"))
    )
    (net (code "274") (name "Net-(IC12-OUT6)") (class "Default")
      (node (ref "D162") (pin "C") (pinfunction "C_C") (pintype "passive"))
      (node (ref "IC12") (pin "11") (pinfunction "OUT6_11") (pintype "output"))
    )
    (net (code "275") (name "Net-(IC12-OUT7)") (class "Default")
      (node (ref "D163") (pin "C") (pinfunction "C_C") (pintype "passive"))
      (node (ref "IC12") (pin "12") (pinfunction "OUT7_12") (pintype "output"))
    )
    (net (code "276") (name "Net-(IC12-OUT8)") (class "Default")
      (node (ref "D227") (pin "C") (pinfunction "C_C") (pintype "passive"))
      (node (ref "IC12") (pin "13") (pinfunction "OUT8_13") (pintype "output"))
    )
    (net (code "277") (name "Net-(IC12-OUT9)") (class "Default")
      (node (ref "D226") (pin "C") (pinfunction "C_C") (pintype "passive"))
      (node (ref "IC12") (pin "14") (pinfunction "OUT9_14") (pintype "output"))
    )
    (net (code "278") (name "Net-(IC12-OUT10)") (class "Default")
      (node (ref "D225") (pin "C") (pinfunction "C_C") (pintype "passive"))
      (node (ref "IC12") (pin "15") (pinfunction "OUT10_15") (pintype "output"))
    )
    (net (code "279") (name "Net-(IC12-OUT11)") (class "Default")
      (node (ref "D224") (pin "C") (pinfunction "C_C") (pintype "passive"))
      (node (ref "IC12") (pin "16") (pinfunction "OUT11_16") (pintype "output"))
    )
    (net (code "280") (name "Net-(IC12-OUT12)") (class "Default")
      (node (ref "D223") (pin "C") (pinfunction "C_C") (pintype "passive"))
      (node (ref "IC12") (pin "17") (pinfunction "OUT12_17") (pintype "output"))
    )
    (net (code "281") (name "Net-(IC12-OUT13)") (class "Default")
      (node (ref "D222") (pin "C") (pinfunction "C_C") (pintype "passive"))
      (node (ref "IC12") (pin "18") (pinfunction "OUT13_18") (pintype "output"))
    )
    (net (code "282") (name "Net-(IC12-OUT14)") (class "Default")
      (node (ref "D221") (pin "C") (pinfunction "C_C") (pintype "passive"))
      (node (ref "IC12") (pin "19") (pinfunction "OUT14_19") (pintype "output"))
    )
    (net (code "283") (name "Net-(IC12-OUT15)") (class "Default")
      (node (ref "D220") (pin "C") (pinfunction "C_C") (pintype "passive"))
      (node (ref "IC12") (pin "20") (pinfunction "OUT15_20") (pintype "output"))
    )
    (net (code "284") (name "Net-(IC13-IREF)") (class "Default")
      (node (ref "IC13") (pin "23") (pinfunction "IREF_23") (pintype "bidirectional"))
      (node (ref "R24") (pin "1") (pinfunction "1_1") (pintype "passive"))
    )
    (net (code "285") (name "Net-(IC13-OUT0)") (class "Default")
      (node (ref "D164") (pin "C") (pinfunction "C_C") (pintype "passive"))
      (node (ref "IC13") (pin "5") (pinfunction "OUT0_5") (pintype "output"))
    )
    (net (code "286") (name "Net-(IC13-OUT1)") (class "Default")
      (node (ref "D165") (pin "C") (pinfunction "C_C") (pintype "passive"))
      (node (ref "IC13") (pin "6") (pinfunction "OUT1_6") (pintype "output"))
    )
    (net (code "287") (name "Net-(IC13-OUT2)") (class "Default")
      (node (ref "D166") (pin "C") (pinfunction "C_C") (pintype "passive"))
      (node (ref "IC13") (pin "7") (pinfunction "OUT2_7") (pintype "output"))
    )
    (net (code "288") (name "Net-(IC13-OUT3)") (class "Default")
      (node (ref "D167") (pin "C") (pinfunction "C_C") (pintype "passive"))
      (node (ref "IC13") (pin "8") (pinfunction "OUT3_8") (pintype "output"))
    )
    (net (code "289") (name "Net-(IC13-OUT4)") (class "Default")
      (node (ref "D168") (pin "C") (pinfunction "C_C") (pintype "passive"))
      (node (ref "IC13") (pin "9") (pinfunction "OUT4_9") (pintype "output"))
    )
    (net (code "290") (name "Net-(IC13-OUT5)") (class "Default")
      (node (ref "D169") (pin "C") (pinfunction "C_C") (pintype "passive"))
      (node (ref "IC13") (pin "10") (pinfunction "OUT5_10") (pintype "output"))
    )
    (net (code "291") (name "Net-(IC13-OUT6)") (class "Default")
      (node (ref "D170") (pin "C") (pinfunction "C_C") (pintype "passive"))
      (node (ref "IC13") (pin "11") (pinfunction "OUT6_11") (pintype "output"))
    )
    (net (code "292") (name "Net-(IC13-OUT7)") (class "Default")
      (node (ref "D171") (pin "C") (pinfunction "C_C") (pintype "passive"))
      (node (ref "IC13") (pin "12") (pinfunction "OUT7_12") (pintype "output"))
    )
    (net (code "293") (name "Net-(IC13-OUT8)") (class "Default")
      (node (ref "D235") (pin "C") (pinfunction "C_C") (pintype "passive"))
      (node (ref "IC13") (pin "13") (pinfunction "OUT8_13") (pintype "output"))
    )
    (net (code "294") (name "Net-(IC13-OUT9)") (class "Default")
      (node (ref "D234") (pin "C") (pinfunction "C_C") (pintype "passive"))
      (node (ref "IC13") (pin "14") (pinfunction "OUT9_14") (pintype "output"))
    )
    (net (code "295") (name "Net-(IC13-OUT10)") (class "Default")
      (node (ref "D233") (pin "C") (pinfunction "C_C") (pintype "passive"))
      (node (ref "IC13") (pin "15") (pinfunction "OUT10_15") (pintype "output"))
    )
    (net (code "296") (name "Net-(IC13-OUT11)") (class "Default")
      (node (ref "D232") (pin "C") (pinfunction "C_C") (pintype "passive"))
      (node (ref "IC13") (pin "16") (pinfunction "OUT11_16") (pintype "output"))
    )
    (net (code "297") (name "Net-(IC13-OUT12)") (class "Default")
      (node (ref "D231") (pin "C") (pinfunction "C_C") (pintype "passive"))
      (node (ref "IC13") (pin "17") (pinfunction "OUT12_17") (pintype "output"))
    )
    (net (code "298") (name "Net-(IC13-OUT13)") (class "Default")
      (node (ref "D230") (pin "C") (pinfunction "C_C") (pintype "passive"))
      (node (ref "IC13") (pin "18") (pinfunction "OUT13_18") (pintype "output"))
    )
    (net (code "299") (name "Net-(IC13-OUT14)") (class "Default")
      (node (ref "D229") (pin "C") (pinfunction "C_C") (pintype "passive"))
      (node (ref "IC13") (pin "19") (pinfunction "OUT14_19") (pintype "output"))
    )
    (net (code "300") (name "Net-(IC13-OUT15)") (class "Default")
      (node (ref "D228") (pin "C") (pinfunction "C_C") (pintype "passive"))
      (node (ref "IC13") (pin "20") (pinfunction "OUT15_20") (pintype "output"))
    )
    (net (code "301") (name "Net-(IC14-IREF)") (class "Default")
      (node (ref "IC14") (pin "23") (pinfunction "IREF_23") (pintype "bidirectional"))
      (node (ref "R25") (pin "1") (pinfunction "1_1") (pintype "passive"))
    )
    (net (code "302") (name "Net-(IC14-OUT0)") (class "Default")
      (node (ref "D172") (pin "C") (pinfunction "C_C") (pintype "passive"))
      (node (ref "IC14") (pin "5") (pinfunction "OUT0_5") (pintype "output"))
    )
    (net (code "303") (name "Net-(IC14-OUT1)") (class "Default")
      (node (ref "D173") (pin "C") (pinfunction "C_C") (pintype "passive"))
      (node (ref "IC14") (pin "6") (pinfunction "OUT1_6") (pintype "output"))
    )
    (net (code "304") (name "Net-(IC14-OUT2)") (class "Default")
      (node (ref "D174") (pin "C") (pinfunction "C_C") (pintype "passive"))
      (node (ref "IC14") (pin "7") (pinfunction "OUT2_7") (pintype "output"))
    )
    (net (code "305") (name "Net-(IC14-OUT3)") (class "Default")
      (node (ref "D175") (pin "C") (pinfunction "C_C") (pintype "passive"))
      (node (ref "IC14") (pin "8") (pinfunction "OUT3_8") (pintype "output"))
    )
    (net (code "306") (name "Net-(IC14-OUT4)") (class "Default")
      (node (ref "D176") (pin "C") (pinfunction "C_C") (pintype "passive"))
      (node (ref "IC14") (pin "9") (pinfunction "OUT4_9") (pintype "output"))
    )
    (net (code "307") (name "Net-(IC14-OUT5)") (class "Default")
      (node (ref "D177") (pin "C") (pinfunction "C_C") (pintype "passive"))
      (node (ref "IC14") (pin "10") (pinfunction "OUT5_10") (pintype "output"))
    )
    (net (code "308") (name "Net-(IC14-OUT6)") (class "Default")
      (node (ref "D178") (pin "C") (pinfunction "C_C") (pintype "passive"))
      (node (ref "IC14") (pin "11") (pinfunction "OUT6_11") (pintype "output"))
    )
    (net (code "309") (name "Net-(IC14-OUT7)") (class "Default")
      (node (ref "D179") (pin "C") (pinfunction "C_C") (pintype "passive"))
      (node (ref "IC14") (pin "12") (pinfunction "OUT7_12") (pintype "output"))
    )
    (net (code "310") (name "Net-(IC14-OUT8)") (class "Default")
      (node (ref "D243") (pin "C") (pinfunction "C_C") (pintype "passive"))
      (node (ref "IC14") (pin "13") (pinfunction "OUT8_13") (pintype "output"))
    )
    (net (code "311") (name "Net-(IC14-OUT9)") (class "Default")
      (node (ref "D242") (pin "C") (pinfunction "C_C") (pintype "passive"))
      (node (ref "IC14") (pin "14") (pinfunction "OUT9_14") (pintype "output"))
    )
    (net (code "312") (name "Net-(IC14-OUT10)") (class "Default")
      (node (ref "D241") (pin "C") (pinfunction "C_C") (pintype "passive"))
      (node (ref "IC14") (pin "15") (pinfunction "OUT10_15") (pintype "output"))
    )
    (net (code "313") (name "Net-(IC14-OUT11)") (class "Default")
      (node (ref "D240") (pin "C") (pinfunction "C_C") (pintype "passive"))
      (node (ref "IC14") (pin "16") (pinfunction "OUT11_16") (pintype "output"))
    )
    (net (code "314") (name "Net-(IC14-OUT12)") (class "Default")
      (node (ref "D239") (pin "C") (pinfunction "C_C") (pintype "passive"))
      (node (ref "IC14") (pin "17") (pinfunction "OUT12_17") (pintype "output"))
    )
    (net (code "315") (name "Net-(IC14-OUT13)") (class "Default")
      (node (ref "D238") (pin "C") (pinfunction "C_C") (pintype "passive"))
      (node (ref "IC14") (pin "18") (pinfunction "OUT13_18") (pintype "output"))
    )
    (net (code "316") (name "Net-(IC14-OUT14)") (class "Default")
      (node (ref "D237") (pin "C") (pinfunction "C_C") (pintype "passive"))
      (node (ref "IC14") (pin "19") (pinfunction "OUT14_19") (pintype "output"))
    )
    (net (code "317") (name "Net-(IC14-OUT15)") (class "Default")
      (node (ref "D236") (pin "C") (pinfunction "C_C") (pintype "passive"))
      (node (ref "IC14") (pin "20") (pinfunction "OUT15_20") (pintype "output"))
    )
    (net (code "318") (name "Net-(IC15-IREF)") (class "Default")
      (node (ref "IC15") (pin "23") (pinfunction "IREF_23") (pintype "bidirectional"))
      (node (ref "R26") (pin "1") (pinfunction "1_1") (pintype "passive"))
    )
    (net (code "319") (name "Net-(IC15-OUT0)") (class "Default")
      (node (ref "D180") (pin "C") (pinfunction "C_C") (pintype "passive"))
      (node (ref "IC15") (pin "5") (pinfunction "OUT0_5") (pintype "output"))
    )
    (net (code "320") (name "Net-(IC15-OUT1)") (class "Default")
      (node (ref "D181") (pin "C") (pinfunction "C_C") (pintype "passive"))
      (node (ref "IC15") (pin "6") (pinfunction "OUT1_6") (pintype "output"))
    )
    (net (code "321") (name "Net-(IC15-OUT2)") (class "Default")
      (node (ref "D182") (pin "C") (pinfunction "C_C") (pintype "passive"))
      (node (ref "IC15") (pin "7") (pinfunction "OUT2_7") (pintype "output"))
    )
    (net (code "322") (name "Net-(IC15-OUT3)") (class "Default")
      (node (ref "D183") (pin "C") (pinfunction "C_C") (pintype "passive"))
      (node (ref "IC15") (pin "8") (pinfunction "OUT3_8") (pintype "output"))
    )
    (net (code "323") (name "Net-(IC15-OUT4)") (class "Default")
      (node (ref "D184") (pin "C") (pinfunction "C_C") (pintype "passive"))
      (node (ref "IC15") (pin "9") (pinfunction "OUT4_9") (pintype "output"))
    )
    (net (code "324") (name "Net-(IC15-OUT5)") (class "Default")
      (node (ref "D185") (pin "C") (pinfunction "C_C") (pintype "passive"))
      (node (ref "IC15") (pin "10") (pinfunction "OUT5_10") (pintype "output"))
    )
    (net (code "325") (name "Net-(IC15-OUT6)") (class "Default")
      (node (ref "D186") (pin "C") (pinfunction "C_C") (pintype "passive"))
      (node (ref "IC15") (pin "11") (pinfunction "OUT6_11") (pintype "output"))
    )
    (net (code "326") (name "Net-(IC15-OUT7)") (class "Default")
      (node (ref "D187") (pin "C") (pinfunction "C_C") (pintype "passive"))
      (node (ref "IC15") (pin "12") (pinfunction "OUT7_12") (pintype "output"))
    )
    (net (code "327") (name "Net-(IC15-OUT8)") (class "Default")
      (node (ref "D251") (pin "C") (pinfunction "C_C") (pintype "passive"))
      (node (ref "IC15") (pin "13") (pinfunction "OUT8_13") (pintype "output"))
    )
    (net (code "328") (name "Net-(IC15-OUT9)") (class "Default")
      (node (ref "D250") (pin "C") (pinfunction "C_C") (pintype "passive"))
      (node (ref "IC15") (pin "14") (pinfunction "OUT9_14") (pintype "output"))
    )
    (net (code "329") (name "Net-(IC15-OUT10)") (class "Default")
      (node (ref "D249") (pin "C") (pinfunction "C_C") (pintype "passive"))
      (node (ref "IC15") (pin "15") (pinfunction "OUT10_15") (pintype "output"))
    )
    (net (code "330") (name "Net-(IC15-OUT11)") (class "Default")
      (node (ref "D248") (pin "C") (pinfunction "C_C") (pintype "passive"))
      (node (ref "IC15") (pin "16") (pinfunction "OUT11_16") (pintype "output"))
    )
    (net (code "331") (name "Net-(IC15-OUT12)") (class "Default")
      (node (ref "D247") (pin "C") (pinfunction "C_C") (pintype "passive"))
      (node (ref "IC15") (pin "17") (pinfunction "OUT12_17") (pintype "output"))
    )
    (net (code "332") (name "Net-(IC15-OUT13)") (class "Default")
      (node (ref "D246") (pin "C") (pinfunction "C_C") (pintype "passive"))
      (node (ref "IC15") (pin "18") (pinfunction "OUT13_18") (pintype "output"))
    )
    (net (code "333") (name "Net-(IC15-OUT14)") (class "Default")
      (node (ref "D245") (pin "C") (pinfunction "C_C") (pintype "passive"))
      (node (ref "IC15") (pin "19") (pinfunction "OUT14_19") (pintype "output"))
    )
    (net (code "334") (name "Net-(IC15-OUT15)") (class "Default")
      (node (ref "D244") (pin "C") (pinfunction "C_C") (pintype "passive"))
      (node (ref "IC15") (pin "20") (pinfunction "OUT15_20") (pintype "output"))
    )
    (net (code "335") (name "Net-(IC16-IREF)") (class "Default")
      (node (ref "IC16") (pin "23") (pinfunction "IREF_23") (pintype "bidirectional"))
      (node (ref "R27") (pin "1") (pinfunction "1_1") (pintype "passive"))
    )
    (net (code "336") (name "Net-(IC16-OUT0)") (class "Default")
      (node (ref "D188") (pin "C") (pinfunction "C_C") (pintype "passive"))
      (node (ref "IC16") (pin "5") (pinfunction "OUT0_5") (pintype "output"))
    )
    (net (code "337") (name "Net-(IC16-OUT1)") (class "Default")
      (node (ref "D189") (pin "C") (pinfunction "C_C") (pintype "passive"))
      (node (ref "IC16") (pin "6") (pinfunction "OUT1_6") (pintype "output"))
    )
    (net (code "338") (name "Net-(IC16-OUT2)") (class "Default")
      (node (ref "D190") (pin "C") (pinfunction "C_C") (pintype "passive"))
      (node (ref "IC16") (pin "7") (pinfunction "OUT2_7") (pintype "output"))
    )
    (net (code "339") (name "Net-(IC16-OUT3)") (class "Default")
      (node (ref "D191") (pin "C") (pinfunction "C_C") (pintype "passive"))
      (node (ref "IC16") (pin "8") (pinfunction "OUT3_8") (pintype "output"))
    )
    (net (code "340") (name "Net-(IC16-OUT4)") (class "Default")
      (node (ref "D192") (pin "C") (pinfunction "C_C") (pintype "passive"))
      (node (ref "IC16") (pin "9") (pinfunction "OUT4_9") (pintype "output"))
    )
    (net (code "341") (name "Net-(IC16-OUT5)") (class "Default")
      (node (ref "D193") (pin "C") (pinfunction "C_C") (pintype "passive"))
      (node (ref "IC16") (pin "10") (pinfunction "OUT5_10") (pintype "output"))
    )
    (net (code "342") (name "Net-(IC16-OUT6)") (class "Default")
      (node (ref "D194") (pin "C") (pinfunction "C_C") (pintype "passive"))
      (node (ref "IC16") (pin "11") (pinfunction "OUT6_11") (pintype "output"))
    )
    (net (code "343") (name "Net-(IC16-OUT7)") (class "Default")
      (node (ref "D195") (pin "C") (pinfunction "C_C") (pintype "passive"))
      (node (ref "IC16") (pin "12") (pinfunction "OUT7_12") (pintype "output"))
    )
    (net (code "344") (name "Net-(IC16-OUT8)") (class "Default")
      (node (ref "D259") (pin "C") (pinfunction "C_C") (pintype "passive"))
      (node (ref "IC16") (pin "13") (pinfunction "OUT8_13") (pintype "output"))
    )
    (net (code "345") (name "Net-(IC16-OUT9)") (class "Default")
      (node (ref "D258") (pin "C") (pinfunction "C_C") (pintype "passive"))
      (node (ref "IC16") (pin "14") (pinfunction "OUT9_14") (pintype "output"))
    )
    (net (code "346") (name "Net-(IC16-OUT10)") (class "Default")
      (node (ref "D257") (pin "C") (pinfunction "C_C") (pintype "passive"))
      (node (ref "IC16") (pin "15") (pinfunction "OUT10_15") (pintype "output"))
    )
    (net (code "347") (name "Net-(IC16-OUT11)") (class "Default")
      (node (ref "D256") (pin "C") (pinfunction "C_C") (pintype "passive"))
      (node (ref "IC16") (pin "16") (pinfunction "OUT11_16") (pintype "output"))
    )
    (net (code "348") (name "Net-(IC16-OUT12)") (class "Default")
      (node (ref "D255") (pin "C") (pinfunction "C_C") (pintype "passive"))
      (node (ref "IC16") (pin "17") (pinfunction "OUT12_17") (pintype "output"))
    )
    (net (code "349") (name "Net-(IC16-OUT13)") (class "Default")
      (node (ref "D254") (pin "C") (pinfunction "C_C") (pintype "passive"))
      (node (ref "IC16") (pin "18") (pinfunction "OUT13_18") (pintype "output"))
    )
    (net (code "350") (name "Net-(IC16-OUT14)") (class "Default")
      (node (ref "D253") (pin "C") (pinfunction "C_C") (pintype "passive"))
      (node (ref "IC16") (pin "19") (pinfunction "OUT14_19") (pintype "output"))
    )
    (net (code "351") (name "Net-(IC16-OUT15)") (class "Default")
      (node (ref "D252") (pin "C") (pinfunction "C_C") (pintype "passive"))
      (node (ref "IC16") (pin "20") (pinfunction "OUT15_20") (pintype "output"))
    )
    (net (code "352") (name "Net-(IC17-IREF)") (class "Default")
      (node (ref "IC17") (pin "23") (pinfunction "IREF_23") (pintype "bidirectional"))
      (node (ref "R28") (pin "1") (pinfunction "1_1") (pintype "passive"))
    )
    (net (code "353") (name "Net-(IC17-OUT0)") (class "Default")
      (node (ref "D260") (pin "C") (pinfunction "C_C") (pintype "passive"))
      (node (ref "IC17") (pin "5") (pinfunction "OUT0_5") (pintype "output"))
    )
    (net (code "354") (name "Net-(IC17-OUT1)") (class "Default")
      (node (ref "D261") (pin "C") (pinfunction "C_C") (pintype "passive"))
      (node (ref "IC17") (pin "6") (pinfunction "OUT1_6") (pintype "output"))
    )
    (net (code "355") (name "Net-(IC17-OUT2)") (class "Default")
      (node (ref "D262") (pin "C") (pinfunction "C_C") (pintype "passive"))
      (node (ref "IC17") (pin "7") (pinfunction "OUT2_7") (pintype "output"))
    )
    (net (code "356") (name "Net-(IC17-OUT3)") (class "Default")
      (node (ref "D263") (pin "C") (pinfunction "C_C") (pintype "passive"))
      (node (ref "IC17") (pin "8") (pinfunction "OUT3_8") (pintype "output"))
    )
    (net (code "357") (name "Net-(IC17-OUT4)") (class "Default")
      (node (ref "D264") (pin "C") (pinfunction "C_C") (pintype "passive"))
      (node (ref "IC17") (pin "9") (pinfunction "OUT4_9") (pintype "output"))
    )
    (net (code "358") (name "Net-(IC17-OUT5)") (class "Default")
      (node (ref "D265") (pin "C") (pinfunction "C_C") (pintype "passive"))
      (node (ref "IC17") (pin "10") (pinfunction "OUT5_10") (pintype "output"))
    )
    (net (code "359") (name "Net-(IC17-OUT6)") (class "Default")
      (node (ref "D266") (pin "C") (pinfunction "C_C") (pintype "passive"))
      (node (ref "IC17") (pin "11") (pinfunction "OUT6_11") (pintype "output"))
    )
    (net (code "360") (name "Net-(IC17-OUT7)") (class "Default")
      (node (ref "D267") (pin "C") (pinfunction "C_C") (pintype "passive"))
      (node (ref "IC17") (pin "12") (pinfunction "OUT7_12") (pintype "output"))
    )
    (net (code "361") (name "Net-(IC17-OUT8)") (class "Default")
      (node (ref "D331") (pin "C") (pinfunction "C_C") (pintype "passive"))
      (node (ref "IC17") (pin "13") (pinfunction "OUT8_13") (pintype "output"))
    )
    (net (code "362") (name "Net-(IC17-OUT9)") (class "Default")
      (node (ref "D330") (pin "C") (pinfunction "C_C") (pintype "passive"))
      (node (ref "IC17") (pin "14") (pinfunction "OUT9_14") (pintype "output"))
    )
    (net (code "363") (name "Net-(IC17-OUT10)") (class "Default")
      (node (ref "D329") (pin "C") (pinfunction "C_C") (pintype "passive"))
      (node (ref "IC17") (pin "15") (pinfunction "OUT10_15") (pintype "output"))
    )
    (net (code "364") (name "Net-(IC17-OUT11)") (class "Default")
      (node (ref "D328") (pin "C") (pinfunction "C_C") (pintype "passive"))
      (node (ref "IC17") (pin "16") (pinfunction "OUT11_16") (pintype "output"))
    )
    (net (code "365") (name "Net-(IC17-OUT12)") (class "Default")
      (node (ref "D327") (pin "C") (pinfunction "C_C") (pintype "passive"))
      (node (ref "IC17") (pin "17") (pinfunction "OUT12_17") (pintype "output"))
    )
    (net (code "366") (name "Net-(IC17-OUT13)") (class "Default")
      (node (ref "D326") (pin "C") (pinfunction "C_C") (pintype "passive"))
      (node (ref "IC17") (pin "18") (pinfunction "OUT13_18") (pintype "output"))
    )
    (net (code "367") (name "Net-(IC17-OUT14)") (class "Default")
      (node (ref "D325") (pin "C") (pinfunction "C_C") (pintype "passive"))
      (node (ref "IC17") (pin "19") (pinfunction "OUT14_19") (pintype "output"))
    )
    (net (code "368") (name "Net-(IC17-OUT15)") (class "Default")
      (node (ref "D324") (pin "C") (pinfunction "C_C") (pintype "passive"))
      (node (ref "IC17") (pin "20") (pinfunction "OUT15_20") (pintype "output"))
    )
    (net (code "369") (name "Net-(IC18-IREF)") (class "Default")
      (node (ref "IC18") (pin "23") (pinfunction "IREF_23") (pintype "bidirectional"))
      (node (ref "R29") (pin "1") (pinfunction "1_1") (pintype "passive"))
    )
    (net (code "370") (name "Net-(IC18-OUT0)") (class "Default")
      (node (ref "D268") (pin "C") (pinfunction "C_C") (pintype "passive"))
      (node (ref "IC18") (pin "5") (pinfunction "OUT0_5") (pintype "output"))
    )
    (net (code "371") (name "Net-(IC18-OUT1)") (class "Default")
      (node (ref "D269") (pin "C") (pinfunction "C_C") (pintype "passive"))
      (node (ref "IC18") (pin "6") (pinfunction "OUT1_6") (pintype "output"))
    )
    (net (code "372") (name "Net-(IC18-OUT2)") (class "Default")
      (node (ref "D270") (pin "C") (pinfunction "C_C") (pintype "passive"))
      (node (ref "IC18") (pin "7") (pinfunction "OUT2_7") (pintype "output"))
    )
    (net (code "373") (name "Net-(IC18-OUT3)") (class "Default")
      (node (ref "D271") (pin "C") (pinfunction "C_C") (pintype "passive"))
      (node (ref "IC18") (pin "8") (pinfunction "OUT3_8") (pintype "output"))
    )
    (net (code "374") (name "Net-(IC18-OUT4)") (class "Default")
      (node (ref "D272") (pin "C") (pinfunction "C_C") (pintype "passive"))
      (node (ref "IC18") (pin "9") (pinfunction "OUT4_9") (pintype "output"))
    )
    (net (code "375") (name "Net-(IC18-OUT5)") (class "Default")
      (node (ref "D273") (pin "C") (pinfunction "C_C") (pintype "passive"))
      (node (ref "IC18") (pin "10") (pinfunction "OUT5_10") (pintype "output"))
    )
    (net (code "376") (name "Net-(IC18-OUT6)") (class "Default")
      (node (ref "D274") (pin "C") (pinfunction "C_C") (pintype "passive"))
      (node (ref "IC18") (pin "11") (pinfunction "OUT6_11") (pintype "output"))
    )
    (net (code "377") (name "Net-(IC18-OUT7)") (class "Default")
      (node (ref "D275") (pin "C") (pinfunction "C_C") (pintype "passive"))
      (node (ref "IC18") (pin "12") (pinfunction "OUT7_12") (pintype "output"))
    )
    (net (code "378") (name "Net-(IC18-OUT8)") (class "Default")
      (node (ref "D339") (pin "C") (pinfunction "C_C") (pintype "passive"))
      (node (ref "IC18") (pin "13") (pinfunction "OUT8_13") (pintype "output"))
    )
    (net (code "379") (name "Net-(IC18-OUT9)") (class "Default")
      (node (ref "D338") (pin "C") (pinfunction "C_C") (pintype "passive"))
      (node (ref "IC18") (pin "14") (pinfunction "OUT9_14") (pintype "output"))
    )
    (net (code "380") (name "Net-(IC18-OUT10)") (class "Default")
      (node (ref "D337") (pin "C") (pinfunction "C_C") (pintype "passive"))
      (node (ref "IC18") (pin "15") (pinfunction "OUT10_15") (pintype "output"))
    )
    (net (code "381") (name "Net-(IC18-OUT11)") (class "Default")
      (node (ref "D336") (pin "C") (pinfunction "C_C") (pintype "passive"))
      (node (ref "IC18") (pin "16") (pinfunction "OUT11_16") (pintype "output"))
    )
    (net (code "382") (name "Net-(IC18-OUT12)") (class "Default")
      (node (ref "D335") (pin "C") (pinfunction "C_C") (pintype "passive"))
      (node (ref "IC18") (pin "17") (pinfunction "OUT12_17") (pintype "output"))
    )
    (net (code "383") (name "Net-(IC18-OUT13)") (class "Default")
      (node (ref "D334") (pin "C") (pinfunction "C_C") (pintype "passive"))
      (node (ref "IC18") (pin "18") (pinfunction "OUT13_18") (pintype "output"))
    )
    (net (code "384") (name "Net-(IC18-OUT14)") (class "Default")
      (node (ref "D333") (pin "C") (pinfunction "C_C") (pintype "passive"))
      (node (ref "IC18") (pin "19") (pinfunction "OUT14_19") (pintype "output"))
    )
    (net (code "385") (name "Net-(IC18-OUT15)") (class "Default")
      (node (ref "D332") (pin "C") (pinfunction "C_C") (pintype "passive"))
      (node (ref "IC18") (pin "20") (pinfunction "OUT15_20") (pintype "output"))
    )
    (net (code "386") (name "Net-(IC19-IREF)") (class "Default")
      (node (ref "IC19") (pin "23") (pinfunction "IREF_23") (pintype "bidirectional"))
      (node (ref "R30") (pin "1") (pinfunction "1_1") (pintype "passive"))
    )
    (net (code "387") (name "Net-(IC19-OUT0)") (class "Default")
      (node (ref "D276") (pin "C") (pinfunction "C_C") (pintype "passive"))
      (node (ref "IC19") (pin "5") (pinfunction "OUT0_5") (pintype "output"))
    )
    (net (code "388") (name "Net-(IC19-OUT1)") (class "Default")
      (node (ref "D277") (pin "C") (pinfunction "C_C") (pintype "passive"))
      (node (ref "IC19") (pin "6") (pinfunction "OUT1_6") (pintype "output"))
    )
    (net (code "389") (name "Net-(IC19-OUT2)") (class "Default")
      (node (ref "D278") (pin "C") (pinfunction "C_C") (pintype "passive"))
      (node (ref "IC19") (pin "7") (pinfunction "OUT2_7") (pintype "output"))
    )
    (net (code "390") (name "Net-(IC19-OUT3)") (class "Default")
      (node (ref "D279") (pin "C") (pinfunction "C_C") (pintype "passive"))
      (node (ref "IC19") (pin "8") (pinfunction "OUT3_8") (pintype "output"))
    )
    (net (code "391") (name "Net-(IC19-OUT4)") (class "Default")
      (node (ref "D280") (pin "C") (pinfunction "C_C") (pintype "passive"))
      (node (ref "IC19") (pin "9") (pinfunction "OUT4_9") (pintype "output"))
    )
    (net (code "392") (name "Net-(IC19-OUT5)") (class "Default")
      (node (ref "D281") (pin "C") (pinfunction "C_C") (pintype "passive"))
      (node (ref "IC19") (pin "10") (pinfunction "OUT5_10") (pintype "output"))
    )
    (net (code "393") (name "Net-(IC19-OUT6)") (class "Default")
      (node (ref "D282") (pin "C") (pinfunction "C_C") (pintype "passive"))
      (node (ref "IC19") (pin "11") (pinfunction "OUT6_11") (pintype "output"))
    )
    (net (code "394") (name "Net-(IC19-OUT7)") (class "Default")
      (node (ref "D283") (pin "C") (pinfunction "C_C") (pintype "passive"))
      (node (ref "IC19") (pin "12") (pinfunction "OUT7_12") (pintype "output"))
    )
    (net (code "395") (name "Net-(IC19-OUT8)") (class "Default")
      (node (ref "D347") (pin "C") (pinfunction "C_C") (pintype "passive"))
      (node (ref "IC19") (pin "13") (pinfunction "OUT8_13") (pintype "output"))
    )
    (net (code "396") (name "Net-(IC19-OUT9)") (class "Default")
      (node (ref "D346") (pin "C") (pinfunction "C_C") (pintype "passive"))
      (node (ref "IC19") (pin "14") (pinfunction "OUT9_14") (pintype "output"))
    )
    (net (code "397") (name "Net-(IC19-OUT10)") (class "Default")
      (node (ref "D345") (pin "C") (pinfunction "C_C") (pintype "passive"))
      (node (ref "IC19") (pin "15") (pinfunction "OUT10_15") (pintype "output"))
    )
    (net (code "398") (name "Net-(IC19-OUT11)") (class "Default")
      (node (ref "D344") (pin "C") (pinfunction "C_C") (pintype "passive"))
      (node (ref "IC19") (pin "16") (pinfunction "OUT11_16") (pintype "output"))
    )
    (net (code "399") (name "Net-(IC19-OUT12)") (class "Default")
      (node (ref "D343") (pin "C") (pinfunction "C_C") (pintype "passive"))
      (node (ref "IC19") (pin "17") (pinfunction "OUT12_17") (pintype "output"))
    )
    (net (code "400") (name "Net-(IC19-OUT13)") (class "Default")
      (node (ref "D342") (pin "C") (pinfunction "C_C") (pintype "passive"))
      (node (ref "IC19") (pin "18") (pinfunction "OUT13_18") (pintype "output"))
    )
    (net (code "401") (name "Net-(IC19-OUT14)") (class "Default")
      (node (ref "D341") (pin "C") (pinfunction "C_C") (pintype "passive"))
      (node (ref "IC19") (pin "19") (pinfunction "OUT14_19") (pintype "output"))
    )
    (net (code "402") (name "Net-(IC19-OUT15)") (class "Default")
      (node (ref "D340") (pin "C") (pinfunction "C_C") (pintype "passive"))
      (node (ref "IC19") (pin "20") (pinfunction "OUT15_20") (pintype "output"))
    )
    (net (code "403") (name "Net-(IC20-IREF)") (class "Default")
      (node (ref "IC20") (pin "23") (pinfunction "IREF_23") (pintype "bidirectional"))
      (node (ref "R31") (pin "1") (pinfunction "1_1") (pintype "passive"))
    )
    (net (code "404") (name "Net-(IC20-OUT0)") (class "Default")
      (node (ref "D284") (pin "C") (pinfunction "C_C") (pintype "passive"))
      (node (ref "IC20") (pin "5") (pinfunction "OUT0_5") (pintype "output"))
    )
    (net (code "405") (name "Net-(IC20-OUT1)") (class "Default")
      (node (ref "D285") (pin "C") (pinfunction "C_C") (pintype "passive"))
      (node (ref "IC20") (pin "6") (pinfunction "OUT1_6") (pintype "output"))
    )
    (net (code "406") (name "Net-(IC20-OUT2)") (class "Default")
      (node (ref "D286") (pin "C") (pinfunction "C_C") (pintype "passive"))
      (node (ref "IC20") (pin "7") (pinfunction "OUT2_7") (pintype "output"))
    )
    (net (code "407") (name "Net-(IC20-OUT3)") (class "Default")
      (node (ref "D287") (pin "C") (pinfunction "C_C") (pintype "passive"))
      (node (ref "IC20") (pin "8") (pinfunction "OUT3_8") (pintype "output"))
    )
    (net (code "408") (name "Net-(IC20-OUT4)") (class "Default")
      (node (ref "D288") (pin "C") (pinfunction "C_C") (pintype "passive"))
      (node (ref "IC20") (pin "9") (pinfunction "OUT4_9") (pintype "output"))
    )
    (net (code "409") (name "Net-(IC20-OUT5)") (class "Default")
      (node (ref "D289") (pin "C") (pinfunction "C_C") (pintype "passive"))
      (node (ref "IC20") (pin "10") (pinfunction "OUT5_10") (pintype "output"))
    )
    (net (code "410") (name "Net-(IC20-OUT6)") (class "Default")
      (node (ref "D290") (pin "C") (pinfunction "C_C") (pintype "passive"))
      (node (ref "IC20") (pin "11") (pinfunction "OUT6_11") (pintype "output"))
    )
    (net (code "411") (name "Net-(IC20-OUT7)") (class "Default")
      (node (ref "D291") (pin "C") (pinfunction "C_C") (pintype "passive"))
      (node (ref "IC20") (pin "12") (pinfunction "OUT7_12") (pintype "output"))
    )
    (net (code "412") (name "Net-(IC20-OUT8)") (class "Default")
      (node (ref "D355") (pin "C") (pinfunction "C_C") (pintype "passive"))
      (node (ref "IC20") (pin "13") (pinfunction "OUT8_13") (pintype "output"))
    )
    (net (code "413") (name "Net-(IC20-OUT9)") (class "Default")
      (node (ref "D354") (pin "C") (pinfunction "C_C") (pintype "passive"))
      (node (ref "IC20") (pin "14") (pinfunction "OUT9_14") (pintype "output"))
    )
    (net (code "414") (name "Net-(IC20-OUT10)") (class "Default")
      (node (ref "D353") (pin "C") (pinfunction "C_C") (pintype "passive"))
      (node (ref "IC20") (pin "15") (pinfunction "OUT10_15") (pintype "output"))
    )
    (net (code "415") (name "Net-(IC20-OUT11)") (class "Default")
      (node (ref "D352") (pin "C") (pinfunction "C_C") (pintype "passive"))
      (node (ref "IC20") (pin "16") (pinfunction "OUT11_16") (pintype "output"))
    )
    (net (code "416") (name "Net-(IC20-OUT12)") (class "Default")
      (node (ref "D351") (pin "C") (pinfunction "C_C") (pintype "passive"))
      (node (ref "IC20") (pin "17") (pinfunction "OUT12_17") (pintype "output"))
    )
    (net (code "417") (name "Net-(IC20-OUT13)") (class "Default")
      (node (ref "D350") (pin "C") (pinfunction "C_C") (pintype "passive"))
      (node (ref "IC20") (pin "18") (pinfunction "OUT13_18") (pintype "output"))
    )
    (net (code "418") (name "Net-(IC20-OUT14)") (class "Default")
      (node (ref "D349") (pin "C") (pinfunction "C_C") (pintype "passive"))
      (node (ref "IC20") (pin "19") (pinfunction "OUT14_19") (pintype "output"))
    )
    (net (code "419") (name "Net-(IC20-OUT15)") (class "Default")
      (node (ref "D348") (pin "C") (pinfunction "C_C") (pintype "passive"))
      (node (ref "IC20") (pin "20") (pinfunction "OUT15_20") (pintype "output"))
    )
    (net (code "420") (name "Net-(IC21-IREF)") (class "Default")
      (node (ref "IC21") (pin "23") (pinfunction "IREF_23") (pintype "bidirectional"))
      (node (ref "R32") (pin "1") (pinfunction "1_1") (pintype "passive"))
    )
    (net (code "421") (name "Net-(IC21-OUT0)") (class "Default")
      (node (ref "D292") (pin "C") (pinfunction "C_C") (pintype "passive"))
      (node (ref "IC21") (pin "5") (pinfunction "OUT0_5") (pintype "output"))
    )
    (net (code "422") (name "Net-(IC21-OUT1)") (class "Default")
      (node (ref "D293") (pin "C") (pinfunction "C_C") (pintype "passive"))
      (node (ref "IC21") (pin "6") (pinfunction "OUT1_6") (pintype "output"))
    )
    (net (code "423") (name "Net-(IC21-OUT2)") (class "Default")
      (node (ref "D294") (pin "C") (pinfunction "C_C") (pintype "passive"))
      (node (ref "IC21") (pin "7") (pinfunction "OUT2_7") (pintype "output"))
    )
    (net (code "424") (name "Net-(IC21-OUT3)") (class "Default")
      (node (ref "D295") (pin "C") (pinfunction "C_C") (pintype "passive"))
      (node (ref "IC21") (pin "8") (pinfunction "OUT3_8") (pintype "output"))
    )
    (net (code "425") (name "Net-(IC21-OUT4)") (class "Default")
      (node (ref "D296") (pin "C") (pinfunction "C_C") (pintype "passive"))
      (node (ref "IC21") (pin "9") (pinfunction "OUT4_9") (pintype "output"))
    )
    (net (code "426") (name "Net-(IC21-OUT5)") (class "Default")
      (node (ref "D297") (pin "C") (pinfunction "C_C") (pintype "passive"))
      (node (ref "IC21") (pin "10") (pinfunction "OUT5_10") (pintype "output"))
    )
    (net (code "427") (name "Net-(IC21-OUT6)") (class "Default")
      (node (ref "D298") (pin "C") (pinfunction "C_C") (pintype "passive"))
      (node (ref "IC21") (pin "11") (pinfunction "OUT6_11") (pintype "output"))
    )
    (net (code "428") (name "Net-(IC21-OUT7)") (class "Default")
      (node (ref "D299") (pin "C") (pinfunction "C_C") (pintype "passive"))
      (node (ref "IC21") (pin "12") (pinfunction "OUT7_12") (pintype "output"))
    )
    (net (code "429") (name "Net-(IC21-OUT8)") (class "Default")
      (node (ref "D363") (pin "C") (pinfunction "C_C") (pintype "passive"))
      (node (ref "IC21") (pin "13") (pinfunction "OUT8_13") (pintype "output"))
    )
    (net (code "430") (name "Net-(IC21-OUT9)") (class "Default")
      (node (ref "D362") (pin "C") (pinfunction "C_C") (pintype "passive"))
      (node (ref "IC21") (pin "14") (pinfunction "OUT9_14") (pintype "output"))
    )
    (net (code "431") (name "Net-(IC21-OUT10)") (class "Default")
      (node (ref "D361") (pin "C") (pinfunction "C_C") (pintype "passive"))
      (node (ref "IC21") (pin "15") (pinfunction "OUT10_15") (pintype "output"))
    )
    (net (code "432") (name "Net-(IC21-OUT11)") (class "Default")
      (node (ref "D360") (pin "C") (pinfunction "C_C") (pintype "passive"))
      (node (ref "IC21") (pin "16") (pinfunction "OUT11_16") (pintype "output"))
    )
    (net (code "433") (name "Net-(IC21-OUT12)") (class "Default")
      (node (ref "D359") (pin "C") (pinfunction "C_C") (pintype "passive"))
      (node (ref "IC21") (pin "17") (pinfunction "OUT12_17") (pintype "output"))
    )
    (net (code "434") (name "Net-(IC21-OUT13)") (class "Default")
      (node (ref "D358") (pin "C") (pinfunction "C_C") (pintype "passive"))
      (node (ref "IC21") (pin "18") (pinfunction "OUT13_18") (pintype "output"))
    )
    (net (code "435") (name "Net-(IC21-OUT14)") (class "Default")
      (node (ref "D357") (pin "C") (pinfunction "C_C") (pintype "passive"))
      (node (ref "IC21") (pin "19") (pinfunction "OUT14_19") (pintype "output"))
    )
    (net (code "436") (name "Net-(IC21-OUT15)") (class "Default")
      (node (ref "D356") (pin "C") (pinfunction "C_C") (pintype "passive"))
      (node (ref "IC21") (pin "20") (pinfunction "OUT15_20") (pintype "output"))
    )
    (net (code "437") (name "Net-(IC22-IREF)") (class "Default")
      (node (ref "IC22") (pin "23") (pinfunction "IREF_23") (pintype "bidirectional"))
      (node (ref "R33") (pin "1") (pinfunction "1_1") (pintype "passive"))
    )
    (net (code "438") (name "Net-(IC22-OUT0)") (class "Default")
      (node (ref "D300") (pin "C") (pinfunction "C_C") (pintype "passive"))
      (node (ref "IC22") (pin "5") (pinfunction "OUT0_5") (pintype "output"))
    )
    (net (code "439") (name "Net-(IC22-OUT1)") (class "Default")
      (node (ref "D301") (pin "C") (pinfunction "C_C") (pintype "passive"))
      (node (ref "IC22") (pin "6") (pinfunction "OUT1_6") (pintype "output"))
    )
    (net (code "440") (name "Net-(IC22-OUT2)") (class "Default")
      (node (ref "D302") (pin "C") (pinfunction "C_C") (pintype "passive"))
      (node (ref "IC22") (pin "7") (pinfunction "OUT2_7") (pintype "output"))
    )
    (net (code "441") (name "Net-(IC22-OUT3)") (class "Default")
      (node (ref "D303") (pin "C") (pinfunction "C_C") (pintype "passive"))
      (node (ref "IC22") (pin "8") (pinfunction "OUT3_8") (pintype "output"))
    )
    (net (code "442") (name "Net-(IC22-OUT4)") (class "Default")
      (node (ref "D304") (pin "C") (pinfunction "C_C") (pintype "passive"))
      (node (ref "IC22") (pin "9") (pinfunction "OUT4_9") (pintype "output"))
    )
    (net (code "443") (name "Net-(IC22-OUT5)") (class "Default")
      (node (ref "D305") (pin "C") (pinfunction "C_C") (pintype "passive"))
      (node (ref "IC22") (pin "10") (pinfunction "OUT5_10") (pintype "output"))
    )
    (net (code "444") (name "Net-(IC22-OUT6)") (class "Default")
      (node (ref "D306") (pin "C") (pinfunction "C_C") (pintype "passive"))
      (node (ref "IC22") (pin "11") (pinfunction "OUT6_11") (pintype "output"))
    )
    (net (code "445") (name "Net-(IC22-OUT7)") (class "Default")
      (node (ref "D307") (pin "C") (pinfunction "C_C") (pintype "passive"))
      (node (ref "IC22") (pin "12") (pinfunction "OUT7_12") (pintype "output"))
    )
    (net (code "446") (name "Net-(IC22-OUT8)") (class "Default")
      (node (ref "D371") (pin "C") (pinfunction "C_C") (pintype "passive"))
      (node (ref "IC22") (pin "13") (pinfunction "OUT8_13") (pintype "output"))
    )
    (net (code "447") (name "Net-(IC22-OUT9)") (class "Default")
      (node (ref "D370") (pin "C") (pinfunction "C_C") (pintype "passive"))
      (node (ref "IC22") (pin "14") (pinfunction "OUT9_14") (pintype "output"))
    )
    (net (code "448") (name "Net-(IC22-OUT10)") (class "Default")
      (node (ref "D369") (pin "C") (pinfunction "C_C") (pintype "passive"))
      (node (ref "IC22") (pin "15") (pinfunction "OUT10_15") (pintype "output"))
    )
    (net (code "449") (name "Net-(IC22-OUT11)") (class "Default")
      (node (ref "D368") (pin "C") (pinfunction "C_C") (pintype "passive"))
      (node (ref "IC22") (pin "16") (pinfunction "OUT11_16") (pintype "output"))
    )
    (net (code "450") (name "Net-(IC22-OUT12)") (class "Default")
      (node (ref "D367") (pin "C") (pinfunction "C_C") (pintype "passive"))
      (node (ref "IC22") (pin "17") (pinfunction "OUT12_17") (pintype "output"))
    )
    (net (code "451") (name "Net-(IC22-OUT13)") (class "Default")
      (node (ref "D366") (pin "C") (pinfunction "C_C") (pintype "passive"))
      (node (ref "IC22") (pin "18") (pinfunction "OUT13_18") (pintype "output"))
    )
    (net (code "452") (name "Net-(IC22-OUT14)") (class "Default")
      (node (ref "D365") (pin "C") (pinfunction "C_C") (pintype "passive"))
      (node (ref "IC22") (pin "19") (pinfunction "OUT14_19") (pintype "output"))
    )
    (net (code "453") (name "Net-(IC22-OUT15)") (class "Default")
      (node (ref "D364") (pin "C") (pinfunction "C_C") (pintype "passive"))
      (node (ref "IC22") (pin "20") (pinfunction "OUT15_20") (pintype "output"))
    )
    (net (code "454") (name "Net-(IC23-IREF)") (class "Default")
      (node (ref "IC23") (pin "23") (pinfunction "IREF_23") (pintype "bidirectional"))
      (node (ref "R34") (pin "1") (pinfunction "1_1") (pintype "passive"))
    )
    (net (code "455") (name "Net-(IC23-OUT0)") (class "Default")
      (node (ref "D308") (pin "C") (pinfunction "C_C") (pintype "passive"))
      (node (ref "IC23") (pin "5") (pinfunction "OUT0_5") (pintype "output"))
    )
    (net (code "456") (name "Net-(IC23-OUT1)") (class "Default")
      (node (ref "D309") (pin "C") (pinfunction "C_C") (pintype "passive"))
      (node (ref "IC23") (pin "6") (pinfunction "OUT1_6") (pintype "output"))
    )
    (net (code "457") (name "Net-(IC23-OUT2)") (class "Default")
      (node (ref "D310") (pin "C") (pinfunction "C_C") (pintype "passive"))
      (node (ref "IC23") (pin "7") (pinfunction "OUT2_7") (pintype "output"))
    )
    (net (code "458") (name "Net-(IC23-OUT3)") (class "Default")
      (node (ref "D311") (pin "C") (pinfunction "C_C") (pintype "passive"))
      (node (ref "IC23") (pin "8") (pinfunction "OUT3_8") (pintype "output"))
    )
    (net (code "459") (name "Net-(IC23-OUT4)") (class "Default")
      (node (ref "D312") (pin "C") (pinfunction "C_C") (pintype "passive"))
      (node (ref "IC23") (pin "9") (pinfunction "OUT4_9") (pintype "output"))
    )
    (net (code "460") (name "Net-(IC23-OUT5)") (class "Default")
      (node (ref "D313") (pin "C") (pinfunction "C_C") (pintype "passive"))
      (node (ref "IC23") (pin "10") (pinfunction "OUT5_10") (pintype "output"))
    )
    (net (code "461") (name "Net-(IC23-OUT6)") (class "Default")
      (node (ref "D314") (pin "C") (pinfunction "C_C") (pintype "passive"))
      (node (ref "IC23") (pin "11") (pinfunction "OUT6_11") (pintype "output"))
    )
    (net (code "462") (name "Net-(IC23-OUT7)") (class "Default")
      (node (ref "D315") (pin "C") (pinfunction "C_C") (pintype "passive"))
      (node (ref "IC23") (pin "12") (pinfunction "OUT7_12") (pintype "output"))
    )
    (net (code "463") (name "Net-(IC23-OUT8)") (class "Default")
      (node (ref "D379") (pin "C") (pinfunction "C_C") (pintype "passive"))
      (node (ref "IC23") (pin "13") (pinfunction "OUT8_13") (pintype "output"))
    )
    (net (code "464") (name "Net-(IC23-OUT9)") (class "Default")
      (node (ref "D378") (pin "C") (pinfunction "C_C") (pintype "passive"))
      (node (ref "IC23") (pin "14") (pinfunction "OUT9_14") (pintype "output"))
    )
    (net (code "465") (name "Net-(IC23-OUT10)") (class "Default")
      (node (ref "D377") (pin "C") (pinfunction "C_C") (pintype "passive"))
      (node (ref "IC23") (pin "15") (pinfunction "OUT10_15") (pintype "output"))
    )
    (net (code "466") (name "Net-(IC23-OUT11)") (class "Default")
      (node (ref "D376") (pin "C") (pinfunction "C_C") (pintype "passive"))
      (node (ref "IC23") (pin "16") (pinfunction "OUT11_16") (pintype "output"))
    )
    (net (code "467") (name "Net-(IC23-OUT12)") (class "Default")
      (node (ref "D375") (pin "C") (pinfunction "C_C") (pintype "passive"))
      (node (ref "IC23") (pin "17") (pinfunction "OUT12_17") (pintype "output"))
    )
    (net (code "468") (name "Net-(IC23-OUT13)") (class "Default")
      (node (ref "D374") (pin "C") (pinfunction "C_C") (pintype "passive"))
      (node (ref "IC23") (pin "18") (pinfunction "OUT13_18") (pintype "output"))
    )
    (net (code "469") (name "Net-(IC23-OUT14)") (class "Default")
      (node (ref "D373") (pin "C") (pinfunction "C_C") (pintype "passive"))
      (node (ref "IC23") (pin "19") (pinfunction "OUT14_19") (pintype "output"))
    )
    (net (code "470") (name "Net-(IC23-OUT15)") (class "Default")
      (node (ref "D372") (pin "C") (pinfunction "C_C") (pintype "passive"))
      (node (ref "IC23") (pin "20") (pinfunction "OUT15_20") (pintype "output"))
    )
    (net (code "471") (name "Net-(IC24-IREF)") (class "Default")
      (node (ref "IC24") (pin "23") (pinfunction "IREF_23") (pintype "bidirectional"))
      (node (ref "R35") (pin "1") (pinfunction "1_1") (pintype "passive"))
    )
    (net (code "472") (name "Net-(IC24-OUT0)") (class "Default")
      (node (ref "D316") (pin "C") (pinfunction "C_C") (pintype "passive"))
      (node (ref "IC24") (pin "5") (pinfunction "OUT0_5") (pintype "output"))
    )
    (net (code "473") (name "Net-(IC24-OUT1)") (class "Default")
      (node (ref "D317") (pin "C") (pinfunction "C_C") (pintype "passive"))
      (node (ref "IC24") (pin "6") (pinfunction "OUT1_6") (pintype "output"))
    )
    (net (code "474") (name "Net-(IC24-OUT2)") (class "Default")
      (node (ref "D318") (pin "C") (pinfunction "C_C") (pintype "passive"))
      (node (ref "IC24") (pin "7") (pinfunction "OUT2_7") (pintype "output"))
    )
    (net (code "475") (name "Net-(IC24-OUT3)") (class "Default")
      (node (ref "D319") (pin "C") (pinfunction "C_C") (pintype "passive"))
      (node (ref "IC24") (pin "8") (pinfunction "OUT3_8") (pintype "output"))
    )
    (net (code "476") (name "Net-(IC24-OUT4)") (class "Default")
      (node (ref "D320") (pin "C") (pinfunction "C_C") (pintype "passive"))
      (node (ref "IC24") (pin "9") (pinfunction "OUT4_9") (pintype "output"))
    )
    (net (code "477") (name "Net-(IC24-OUT5)") (class "Default")
      (node (ref "D321") (pin "C") (pinfunction "C_C") (pintype "passive"))
      (node (ref "IC24") (pin "10") (pinfunction "OUT5_10") (pintype "output"))
    )
    (net (code "478") (name "Net-(IC24-OUT6)") (class "Default")
      (node (ref "D322") (pin "C") (pinfunction "C_C") (pintype "passive"))
      (node (ref "IC24") (pin "11") (pinfunction "OUT6_11") (pintype "output"))
    )
    (net (code "479") (name "Net-(IC24-OUT7)") (class "Default")
      (node (ref "D323") (pin "C") (pinfunction "C_C") (pintype "passive"))
      (node (ref "IC24") (pin "12") (pinfunction "OUT7_12") (pintype "output"))
    )
    (net (code "480") (name "Net-(IC24-OUT8)") (class "Default")
      (node (ref "D387") (pin "C") (pinfunction "C_C") (pintype "passive"))
      (node (ref "IC24") (pin "13") (pinfunction "OUT8_13") (pintype "output"))
    )
    (net (code "481") (name "Net-(IC24-OUT9)") (class "Default")
      (node (ref "D386") (pin "C") (pinfunction "C_C") (pintype "passive"))
      (node (ref "IC24") (pin "14") (pinfunction "OUT9_14") (pintype "output"))
    )
    (net (code "482") (name "Net-(IC24-OUT10)") (class "Default")
      (node (ref "D385") (pin "C") (pinfunction "C_C") (pintype "passive"))
      (node (ref "IC24") (pin "15") (pinfunction "OUT10_15") (pintype "output"))
    )
    (net (code "483") (name "Net-(IC24-OUT11)") (class "Default")
      (node (ref "D384") (pin "C") (pinfunction "C_C") (pintype "passive"))
      (node (ref "IC24") (pin "16") (pinfunction "OUT11_16") (pintype "output"))
    )
    (net (code "484") (name "Net-(IC24-OUT12)") (class "Default")
      (node (ref "D383") (pin "C") (pinfunction "C_C") (pintype "passive"))
      (node (ref "IC24") (pin "17") (pinfunction "OUT12_17") (pintype "output"))
    )
    (net (code "485") (name "Net-(IC24-OUT13)") (class "Default")
      (node (ref "D382") (pin "C") (pinfunction "C_C") (pintype "passive"))
      (node (ref "IC24") (pin "18") (pinfunction "OUT13_18") (pintype "output"))
    )
    (net (code "486") (name "Net-(IC24-OUT14)") (class "Default")
      (node (ref "D381") (pin "C") (pinfunction "C_C") (pintype "passive"))
      (node (ref "IC24") (pin "19") (pinfunction "OUT14_19") (pintype "output"))
    )
    (net (code "487") (name "Net-(IC24-OUT15)") (class "Default")
      (node (ref "D380") (pin "C") (pinfunction "C_C") (pintype "passive"))
      (node (ref "IC24") (pin "20") (pinfunction "OUT15_20") (pintype "output"))
    )
    (net (code "488") (name "Net-(IC25-IREF)") (class "Default")
      (node (ref "IC25") (pin "23") (pinfunction "IREF_23") (pintype "bidirectional"))
      (node (ref "R36") (pin "1") (pinfunction "1_1") (pintype "passive"))
    )
    (net (code "489") (name "Net-(IC25-OUT0)") (class "Default")
      (node (ref "D388") (pin "C") (pinfunction "C_C") (pintype "passive"))
      (node (ref "IC25") (pin "5") (pinfunction "OUT0_5") (pintype "output"))
    )
    (net (code "490") (name "Net-(IC25-OUT1)") (class "Default")
      (node (ref "D389") (pin "C") (pinfunction "C_C") (pintype "passive"))
      (node (ref "IC25") (pin "6") (pinfunction "OUT1_6") (pintype "output"))
    )
    (net (code "491") (name "Net-(IC25-OUT2)") (class "Default")
      (node (ref "D390") (pin "C") (pinfunction "C_C") (pintype "passive"))
      (node (ref "IC25") (pin "7") (pinfunction "OUT2_7") (pintype "output"))
    )
    (net (code "492") (name "Net-(IC25-OUT3)") (class "Default")
      (node (ref "D391") (pin "C") (pinfunction "C_C") (pintype "passive"))
      (node (ref "IC25") (pin "8") (pinfunction "OUT3_8") (pintype "output"))
    )
    (net (code "493") (name "Net-(IC25-OUT4)") (class "Default")
      (node (ref "D392") (pin "C") (pinfunction "C_C") (pintype "passive"))
      (node (ref "IC25") (pin "9") (pinfunction "OUT4_9") (pintype "output"))
    )
    (net (code "494") (name "Net-(IC25-OUT5)") (class "Default")
      (node (ref "D393") (pin "C") (pinfunction "C_C") (pintype "passive"))
      (node (ref "IC25") (pin "10") (pinfunction "OUT5_10") (pintype "output"))
    )
    (net (code "495") (name "Net-(IC25-OUT6)") (class "Default")
      (node (ref "D394") (pin "C") (pinfunction "C_C") (pintype "passive"))
      (node (ref "IC25") (pin "11") (pinfunction "OUT6_11") (pintype "output"))
    )
    (net (code "496") (name "Net-(IC25-OUT7)") (class "Default")
      (node (ref "D395") (pin "C") (pinfunction "C_C") (pintype "passive"))
      (node (ref "IC25") (pin "12") (pinfunction "OUT7_12") (pintype "output"))
    )
    (net (code "497") (name "Net-(IC25-OUT8)") (class "Default")
      (node (ref "D459") (pin "C") (pinfunction "C_C") (pintype "passive"))
      (node (ref "IC25") (pin "13") (pinfunction "OUT8_13") (pintype "output"))
    )
    (net (code "498") (name "Net-(IC25-OUT9)") (class "Default")
      (node (ref "D458") (pin "C") (pinfunction "C_C") (pintype "passive"))
      (node (ref "IC25") (pin "14") (pinfunction "OUT9_14") (pintype "output"))
    )
    (net (code "499") (name "Net-(IC25-OUT10)") (class "Default")
      (node (ref "D457") (pin "C") (pinfunction "C_C") (pintype "passive"))
      (node (ref "IC25") (pin "15") (pinfunction "OUT10_15") (pintype "output"))
    )
    (net (code "500") (name "Net-(IC25-OUT11)") (class "Default")
      (node (ref "D456") (pin "C") (pinfunction "C_C") (pintype "passive"))
      (node (ref "IC25") (pin "16") (pinfunction "OUT11_16") (pintype "output"))
    )
    (net (code "501") (name "Net-(IC25-OUT12)") (class "Default")
      (node (ref "D455") (pin "C") (pinfunction "C_C") (pintype "passive"))
      (node (ref "IC25") (pin "17") (pinfunction "OUT12_17") (pintype "output"))
    )
    (net (code "502") (name "Net-(IC25-OUT13)") (class "Default")
      (node (ref "D454") (pin "C") (pinfunction "C_C") (pintype "passive"))
      (node (ref "IC25") (pin "18") (pinfunction "OUT13_18") (pintype "output"))
    )
    (net (code "503") (name "Net-(IC25-OUT14)") (class "Default")
      (node (ref "D453") (pin "C") (pinfunction "C_C") (pintype "passive"))
      (node (ref "IC25") (pin "19") (pinfunction "OUT14_19") (pintype "output"))
    )
    (net (code "504") (name "Net-(IC25-OUT15)") (class "Default")
      (node (ref "D452") (pin "C") (pinfunction "C_C") (pintype "passive"))
      (node (ref "IC25") (pin "20") (pinfunction "OUT15_20") (pintype "output"))
    )
    (net (code "505") (name "Net-(IC26-IREF)") (class "Default")
      (node (ref "IC26") (pin "23") (pinfunction "IREF_23") (pintype "bidirectional"))
      (node (ref "R37") (pin "1") (pinfunction "1_1") (pintype "passive"))
    )
    (net (code "506") (name "Net-(IC26-OUT0)") (class "Default")
      (node (ref "D396") (pin "C") (pinfunction "C_C") (pintype "passive"))
      (node (ref "IC26") (pin "5") (pinfunction "OUT0_5") (pintype "output"))
    )
    (net (code "507") (name "Net-(IC26-OUT1)") (class "Default")
      (node (ref "D397") (pin "C") (pinfunction "C_C") (pintype "passive"))
      (node (ref "IC26") (pin "6") (pinfunction "OUT1_6") (pintype "output"))
    )
    (net (code "508") (name "Net-(IC26-OUT2)") (class "Default")
      (node (ref "D398") (pin "C") (pinfunction "C_C") (pintype "passive"))
      (node (ref "IC26") (pin "7") (pinfunction "OUT2_7") (pintype "output"))
    )
    (net (code "509") (name "Net-(IC26-OUT3)") (class "Default")
      (node (ref "D399") (pin "C") (pinfunction "C_C") (pintype "passive"))
      (node (ref "IC26") (pin "8") (pinfunction "OUT3_8") (pintype "output"))
    )
    (net (code "510") (name "Net-(IC26-OUT4)") (class "Default")
      (node (ref "D400") (pin "C") (pinfunction "C_C") (pintype "passive"))
      (node (ref "IC26") (pin "9") (pinfunction "OUT4_9") (pintype "output"))
    )
    (net (code "511") (name "Net-(IC26-OUT5)") (class "Default")
      (node (ref "D401") (pin "C") (pinfunction "C_C") (pintype "passive"))
      (node (ref "IC26") (pin "10") (pinfunction "OUT5_10") (pintype "output"))
    )
    (net (code "512") (name "Net-(IC26-OUT6)") (class "Default")
      (node (ref "D402") (pin "C") (pinfunction "C_C") (pintype "passive"))
      (node (ref "IC26") (pin "11") (pinfunction "OUT6_11") (pintype "output"))
    )
    (net (code "513") (name "Net-(IC26-OUT7)") (class "Default")
      (node (ref "D403") (pin "C") (pinfunction "C_C") (pintype "passive"))
      (node (ref "IC26") (pin "12") (pinfunction "OUT7_12") (pintype "output"))
    )
    (net (code "514") (name "Net-(IC26-OUT8)") (class "Default")
      (node (ref "D467") (pin "C") (pinfunction "C_C") (pintype "passive"))
      (node (ref "IC26") (pin "13") (pinfunction "OUT8_13") (pintype "output"))
    )
    (net (code "515") (name "Net-(IC26-OUT9)") (class "Default")
      (node (ref "D466") (pin "C") (pinfunction "C_C") (pintype "passive"))
      (node (ref "IC26") (pin "14") (pinfunction "OUT9_14") (pintype "output"))
    )
    (net (code "516") (name "Net-(IC26-OUT10)") (class "Default")
      (node (ref "D465") (pin "C") (pinfunction "C_C") (pintype "passive"))
      (node (ref "IC26") (pin "15") (pinfunction "OUT10_15") (pintype "output"))
    )
    (net (code "517") (name "Net-(IC26-OUT11)") (class "Default")
      (node (ref "D464") (pin "C") (pinfunction "C_C") (pintype "passive"))
      (node (ref "IC26") (pin "16") (pinfunction "OUT11_16") (pintype "output"))
    )
    (net (code "518") (name "Net-(IC26-OUT12)") (class "Default")
      (node (ref "D463") (pin "C") (pinfunction "C_C") (pintype "passive"))
      (node (ref "IC26") (pin "17") (pinfunction "OUT12_17") (pintype "output"))
    )
    (net (code "519") (name "Net-(IC26-OUT13)") (class "Default")
      (node (ref "D462") (pin "C") (pinfunction "C_C") (pintype "passive"))
      (node (ref "IC26") (pin "18") (pinfunction "OUT13_18") (pintype "output"))
    )
    (net (code "520") (name "Net-(IC26-OUT14)") (class "Default")
      (node (ref "D461") (pin "C") (pinfunction "C_C") (pintype "passive"))
      (node (ref "IC26") (pin "19") (pinfunction "OUT14_19") (pintype "output"))
    )
    (net (code "521") (name "Net-(IC26-OUT15)") (class "Default")
      (node (ref "D460") (pin "C") (pinfunction "C_C") (pintype "passive"))
      (node (ref "IC26") (pin "20") (pinfunction "OUT15_20") (pintype "output"))
    )
    (net (code "522") (name "Net-(IC27-IREF)") (class "Default")
      (node (ref "IC27") (pin "23") (pinfunction "IREF_23") (pintype "bidirectional"))
      (node (ref "R38") (pin "1") (pinfunction "1_1") (pintype "passive"))
    )
    (net (code "523") (name "Net-(IC27-OUT0)") (class "Default")
      (node (ref "D404") (pin "C") (pinfunction "C_C") (pintype "passive"))
      (node (ref "IC27") (pin "5") (pinfunction "OUT0_5") (pintype "output"))
    )
    (net (code "524") (name "Net-(IC27-OUT1)") (class "Default")
      (node (ref "D405") (pin "C") (pinfunction "C_C") (pintype "passive"))
      (node (ref "IC27") (pin "6") (pinfunction "OUT1_6") (pintype "output"))
    )
    (net (code "525") (name "Net-(IC27-OUT2)") (class "Default")
      (node (ref "D406") (pin "C") (pinfunction "C_C") (pintype "passive"))
      (node (ref "IC27") (pin "7") (pinfunction "OUT2_7") (pintype "output"))
    )
    (net (code "526") (name "Net-(IC27-OUT3)") (class "Default")
      (node (ref "D407") (pin "C") (pinfunction "C_C") (pintype "passive"))
      (node (ref "IC27") (pin "8") (pinfunction "OUT3_8") (pintype "output"))
    )
    (net (code "527") (name "Net-(IC27-OUT4)") (class "Default")
      (node (ref "D408") (pin "C") (pinfunction "C_C") (pintype "passive"))
      (node (ref "IC27") (pin "9") (pinfunction "OUT4_9") (pintype "output"))
    )
    (net (code "528") (name "Net-(IC27-OUT5)") (class "Default")
      (node (ref "D409") (pin "C") (pinfunction "C_C") (pintype "passive"))
      (node (ref "IC27") (pin "10") (pinfunction "OUT5_10") (pintype "output"))
    )
    (net (code "529") (name "Net-(IC27-OUT6)") (class "Default")
      (node (ref "D410") (pin "C") (pinfunction "C_C") (pintype "passive"))
      (node (ref "IC27") (pin "11") (pinfunction "OUT6_11") (pintype "output"))
    )
    (net (code "530") (name "Net-(IC27-OUT7)") (class "Default")
      (node (ref "D411") (pin "C") (pinfunction "C_C") (pintype "passive"))
      (node (ref "IC27") (pin "12") (pinfunction "OUT7_12") (pintype "output"))
    )
    (net (code "531") (name "Net-(IC27-OUT8)") (class "Default")
      (node (ref "D475") (pin "C") (pinfunction "C_C") (pintype "passive"))
      (node (ref "IC27") (pin "13") (pinfunction "OUT8_13") (pintype "output"))
    )
    (net (code "532") (name "Net-(IC27-OUT9)") (class "Default")
      (node (ref "D474") (pin "C") (pinfunction "C_C") (pintype "passive"))
      (node (ref "IC27") (pin "14") (pinfunction "OUT9_14") (pintype "output"))
    )
    (net (code "533") (name "Net-(IC27-OUT10)") (class "Default")
      (node (ref "D473") (pin "C") (pinfunction "C_C") (pintype "passive"))
      (node (ref "IC27") (pin "15") (pinfunction "OUT10_15") (pintype "output"))
    )
    (net (code "534") (name "Net-(IC27-OUT11)") (class "Default")
      (node (ref "D472") (pin "C") (pinfunction "C_C") (pintype "passive"))
      (node (ref "IC27") (pin "16") (pinfunction "OUT11_16") (pintype "output"))
    )
    (net (code "535") (name "Net-(IC27-OUT12)") (class "Default")
      (node (ref "D471") (pin "C") (pinfunction "C_C") (pintype "passive"))
      (node (ref "IC27") (pin "17") (pinfunction "OUT12_17") (pintype "output"))
    )
    (net (code "536") (name "Net-(IC27-OUT13)") (class "Default")
      (node (ref "D470") (pin "C") (pinfunction "C_C") (pintype "passive"))
      (node (ref "IC27") (pin "18") (pinfunction "OUT13_18") (pintype "output"))
    )
    (net (code "537") (name "Net-(IC27-OUT14)") (class "Default")
      (node (ref "D469") (pin "C") (pinfunction "C_C") (pintype "passive"))
      (node (ref "IC27") (pin "19") (pinfunction "OUT14_19") (pintype "output"))
    )
    (net (code "538") (name "Net-(IC27-OUT15)") (class "Default")
      (node (ref "D468") (pin "C") (pinfunction "C_C") (pintype "passive"))
      (node (ref "IC27") (pin "20") (pinfunction "OUT15_20") (pintype "output"))
    )
    (net (code "539") (name "Net-(IC28-IREF)") (class "Default")
      (node (ref "IC28") (pin "23") (pinfunction "IREF_23") (pintype "bidirectional"))
      (node (ref "R39") (pin "1") (pinfunction "1_1") (pintype "passive"))
    )
    (net (code "540") (name "Net-(IC28-OUT0)") (class "Default")
      (node (ref "D412") (pin "C") (pinfunction "C_C") (pintype "passive"))
      (node (ref "IC28") (pin "5") (pinfunction "OUT0_5") (pintype "output"))
    )
    (net (code "541") (name "Net-(IC28-OUT1)") (class "Default")
      (node (ref "D413") (pin "C") (pinfunction "C_C") (pintype "passive"))
      (node (ref "IC28") (pin "6") (pinfunction "OUT1_6") (pintype "output"))
    )
    (net (code "542") (name "Net-(IC28-OUT2)") (class "Default")
      (node (ref "D414") (pin "C") (pinfunction "C_C") (pintype "passive"))
      (node (ref "IC28") (pin "7") (pinfunction "OUT2_7") (pintype "output"))
    )
    (net (code "543") (name "Net-(IC28-OUT3)") (class "Default")
      (node (ref "D415") (pin "C") (pinfunction "C_C") (pintype "passive"))
      (node (ref "IC28") (pin "8") (pinfunction "OUT3_8") (pintype "output"))
    )
    (net (code "544") (name "Net-(IC28-OUT4)") (class "Default")
      (node (ref "D416") (pin "C") (pinfunction "C_C") (pintype "passive"))
      (node (ref "IC28") (pin "9") (pinfunction "OUT4_9") (pintype "output"))
    )
    (net (code "545") (name "Net-(IC28-OUT5)") (class "Default")
      (node (ref "D417") (pin "C") (pinfunction "C_C") (pintype "passive"))
      (node (ref "IC28") (pin "10") (pinfunction "OUT5_10") (pintype "output"))
    )
    (net (code "546") (name "Net-(IC28-OUT6)") (class "Default")
      (node (ref "D418") (pin "C") (pinfunction "C_C") (pintype "passive"))
      (node (ref "IC28") (pin "11") (pinfunction "OUT6_11") (pintype "output"))
    )
    (net (code "547") (name "Net-(IC28-OUT7)") (class "Default")
      (node (ref "D419") (pin "C") (pinfunction "C_C") (pintype "passive"))
      (node (ref "IC28") (pin "12") (pinfunction "OUT7_12") (pintype "output"))
    )
    (net (code "548") (name "Net-(IC28-OUT8)") (class "Default")
      (node (ref "D483") (pin "C") (pinfunction "C_C") (pintype "passive"))
      (node (ref "IC28") (pin "13") (pinfunction "OUT8_13") (pintype "output"))
    )
    (net (code "549") (name "Net-(IC28-OUT9)") (class "Default")
      (node (ref "D482") (pin "C") (pinfunction "C_C") (pintype "passive"))
      (node (ref "IC28") (pin "14") (pinfunction "OUT9_14") (pintype "output"))
    )
    (net (code "550") (name "Net-(IC28-OUT10)") (class "Default")
      (node (ref "D481") (pin "C") (pinfunction "C_C") (pintype "passive"))
      (node (ref "IC28") (pin "15") (pinfunction "OUT10_15") (pintype "output"))
    )
    (net (code "551") (name "Net-(IC28-OUT11)") (class "Default")
      (node (ref "D480") (pin "C") (pinfunction "C_C") (pintype "passive"))
      (node (ref "IC28") (pin "16") (pinfunction "OUT11_16") (pintype "output"))
    )
    (net (code "552") (name "Net-(IC28-OUT12)") (class "Default")
      (node (ref "D479") (pin "C") (pinfunction "C_C") (pintype "passive"))
      (node (ref "IC28") (pin "17") (pinfunction "OUT12_17") (pintype "output"))
    )
    (net (code "553") (name "Net-(IC28-OUT13)") (class "Default")
      (node (ref "D478") (pin "C") (pinfunction "C_C") (pintype "passive"))
      (node (ref "IC28") (pin "18") (pinfunction "OUT13_18") (pintype "output"))
    )
    (net (code "554") (name "Net-(IC28-OUT14)") (class "Default")
      (node (ref "D477") (pin "C") (pinfunction "C_C") (pintype "passive"))
      (node (ref "IC28") (pin "19") (pinfunction "OUT14_19") (pintype "output"))
    )
    (net (code "555") (name "Net-(IC28-OUT15)") (class "Default")
      (node (ref "D476") (pin "C") (pinfunction "C_C") (pintype "passive"))
      (node (ref "IC28") (pin "20") (pinfunction "OUT15_20") (pintype "output"))
    )
    (net (code "556") (name "Net-(IC29-IREF)") (class "Default")
      (node (ref "IC29") (pin "23") (pinfunction "IREF_23") (pintype "bidirectional"))
      (node (ref "R40") (pin "1") (pinfunction "1_1") (pintype "passive"))
    )
    (net (code "557") (name "Net-(IC29-OUT0)") (class "Default")
      (node (ref "D420") (pin "C") (pinfunction "C_C") (pintype "passive"))
      (node (ref "IC29") (pin "5") (pinfunction "OUT0_5") (pintype "output"))
    )
    (net (code "558") (name "Net-(IC29-OUT1)") (class "Default")
      (node (ref "D421") (pin "C") (pinfunction "C_C") (pintype "passive"))
      (node (ref "IC29") (pin "6") (pinfunction "OUT1_6") (pintype "output"))
    )
    (net (code "559") (name "Net-(IC29-OUT2)") (class "Default")
      (node (ref "D422") (pin "C") (pinfunction "C_C") (pintype "passive"))
      (node (ref "IC29") (pin "7") (pinfunction "OUT2_7") (pintype "output"))
    )
    (net (code "560") (name "Net-(IC29-OUT3)") (class "Default")
      (node (ref "D423") (pin "C") (pinfunction "C_C") (pintype "passive"))
      (node (ref "IC29") (pin "8") (pinfunction "OUT3_8") (pintype "output"))
    )
    (net (code "561") (name "Net-(IC29-OUT4)") (class "Default")
      (node (ref "D424") (pin "C") (pinfunction "C_C") (pintype "passive"))
      (node (ref "IC29") (pin "9") (pinfunction "OUT4_9") (pintype "output"))
    )
    (net (code "562") (name "Net-(IC29-OUT5)") (class "Default")
      (node (ref "D425") (pin "C") (pinfunction "C_C") (pintype "passive"))
      (node (ref "IC29") (pin "10") (pinfunction "OUT5_10") (pintype "output"))
    )
    (net (code "563") (name "Net-(IC29-OUT6)") (class "Default")
      (node (ref "D426") (pin "C") (pinfunction "C_C") (pintype "passive"))
      (node (ref "IC29") (pin "11") (pinfunction "OUT6_11") (pintype "output"))
    )
    (net (code "564") (name "Net-(IC29-OUT7)") (class "Default")
      (node (ref "D427") (pin "C") (pinfunction "C_C") (pintype "passive"))
      (node (ref "IC29") (pin "12") (pinfunction "OUT7_12") (pintype "output"))
    )
    (net (code "565") (name "Net-(IC29-OUT8)") (class "Default")
      (node (ref "D491") (pin "C") (pinfunction "C_C") (pintype "passive"))
      (node (ref "IC29") (pin "13") (pinfunction "OUT8_13") (pintype "output"))
    )
    (net (code "566") (name "Net-(IC29-OUT9)") (class "Default")
      (node (ref "D490") (pin "C") (pinfunction "C_C") (pintype "passive"))
      (node (ref "IC29") (pin "14") (pinfunction "OUT9_14") (pintype "output"))
    )
    (net (code "567") (name "Net-(IC29-OUT10)") (class "Default")
      (node (ref "D489") (pin "C") (pinfunction "C_C") (pintype "passive"))
      (node (ref "IC29") (pin "15") (pinfunction "OUT10_15") (pintype "output"))
    )
    (net (code "568") (name "Net-(IC29-OUT11)") (class "Default")
      (node (ref "D488") (pin "C") (pinfunction "C_C") (pintype "passive"))
      (node (ref "IC29") (pin "16") (pinfunction "OUT11_16") (pintype "output"))
    )
    (net (code "569") (name "Net-(IC29-OUT12)") (class "Default")
      (node (ref "D487") (pin "C") (pinfunction "C_C") (pintype "passive"))
      (node (ref "IC29") (pin "17") (pinfunction "OUT12_17") (pintype "output"))
    )
    (net (code "570") (name "Net-(IC29-OUT13)") (class "Default")
      (node (ref "D486") (pin "C") (pinfunction "C_C") (pintype "passive"))
      (node (ref "IC29") (pin "18") (pinfunction "OUT13_18") (pintype "output"))
    )
    (net (code "571") (name "Net-(IC29-OUT14)") (class "Default")
      (node (ref "D485") (pin "C") (pinfunction "C_C") (pintype "passive"))
      (node (ref "IC29") (pin "19") (pinfunction "OUT14_19") (pintype "output"))
    )
    (net (code "572") (name "Net-(IC29-OUT15)") (class "Default")
      (node (ref "D484") (pin "C") (pinfunction "C_C") (pintype "passive"))
      (node (ref "IC29") (pin "20") (pinfunction "OUT15_20") (pintype "output"))
    )
    (net (code "573") (name "Net-(IC30-IREF)") (class "Default")
      (node (ref "IC30") (pin "23") (pinfunction "IREF_23") (pintype "bidirectional"))
      (node (ref "R41") (pin "1") (pinfunction "1_1") (pintype "passive"))
    )
    (net (code "574") (name "Net-(IC30-OUT0)") (class "Default")
      (node (ref "D428") (pin "C") (pinfunction "C_C") (pintype "passive"))
      (node (ref "IC30") (pin "5") (pinfunction "OUT0_5") (pintype "output"))
    )
    (net (code "575") (name "Net-(IC30-OUT1)") (class "Default")
      (node (ref "D429") (pin "C") (pinfunction "C_C") (pintype "passive"))
      (node (ref "IC30") (pin "6") (pinfunction "OUT1_6") (pintype "output"))
    )
    (net (code "576") (name "Net-(IC30-OUT2)") (class "Default")
      (node (ref "D430") (pin "C") (pinfunction "C_C") (pintype "passive"))
      (node (ref "IC30") (pin "7") (pinfunction "OUT2_7") (pintype "output"))
    )
    (net (code "577") (name "Net-(IC30-OUT3)") (class "Default")
      (node (ref "D431") (pin "C") (pinfunction "C_C") (pintype "passive"))
      (node (ref "IC30") (pin "8") (pinfunction "OUT3_8") (pintype "output"))
    )
    (net (code "578") (name "Net-(IC30-OUT4)") (class "Default")
      (node (ref "D432") (pin "C") (pinfunction "C_C") (pintype "passive"))
      (node (ref "IC30") (pin "9") (pinfunction "OUT4_9") (pintype "output"))
    )
    (net (code "579") (name "Net-(IC30-OUT5)") (class "Default")
      (node (ref "D433") (pin "C") (pinfunction "C_C") (pintype "passive"))
      (node (ref "IC30") (pin "10") (pinfunction "OUT5_10") (pintype "output"))
    )
    (net (code "580") (name "Net-(IC30-OUT6)") (class "Default")
      (node (ref "D434") (pin "C") (pinfunction "C_C") (pintype "passive"))
      (node (ref "IC30") (pin "11") (pinfunction "OUT6_11") (pintype "output"))
    )
    (net (code "581") (name "Net-(IC30-OUT7)") (class "Default")
      (node (ref "D435") (pin "C") (pinfunction "C_C") (pintype "passive"))
      (node (ref "IC30") (pin "12") (pinfunction "OUT7_12") (pintype "output"))
    )
    (net (code "582") (name "Net-(IC30-OUT8)") (class "Default")
      (node (ref "D499") (pin "C") (pinfunction "C_C") (pintype "passive"))
      (node (ref "IC30") (pin "13") (pinfunction "OUT8_13") (pintype "output"))
    )
    (net (code "583") (name "Net-(IC30-OUT9)") (class "Default")
      (node (ref "D498") (pin "C") (pinfunction "C_C") (pintype "passive"))
      (node (ref "IC30") (pin "14") (pinfunction "OUT9_14") (pintype "output"))
    )
    (net (code "584") (name "Net-(IC30-OUT10)") (class "Default")
      (node (ref "D497") (pin "C") (pinfunction "C_C") (pintype "passive"))
      (node (ref "IC30") (pin "15") (pinfunction "OUT10_15") (pintype "output"))
    )
    (net (code "585") (name "Net-(IC30-OUT11)") (class "Default")
      (node (ref "D496") (pin "C") (pinfunction "C_C") (pintype "passive"))
      (node (ref "IC30") (pin "16") (pinfunction "OUT11_16") (pintype "output"))
    )
    (net (code "586") (name "Net-(IC30-OUT12)") (class "Default")
      (node (ref "D495") (pin "C") (pinfunction "C_C") (pintype "passive"))
      (node (ref "IC30") (pin "17") (pinfunction "OUT12_17") (pintype "output"))
    )
    (net (code "587") (name "Net-(IC30-OUT13)") (class "Default")
      (node (ref "D494") (pin "C") (pinfunction "C_C") (pintype "passive"))
      (node (ref "IC30") (pin "18") (pinfunction "OUT13_18") (pintype "output"))
    )
    (net (code "588") (name "Net-(IC30-OUT14)") (class "Default")
      (node (ref "D493") (pin "C") (pinfunction "C_C") (pintype "passive"))
      (node (ref "IC30") (pin "19") (pinfunction "OUT14_19") (pintype "output"))
    )
    (net (code "589") (name "Net-(IC30-OUT15)") (class "Default")
      (node (ref "D492") (pin "C") (pinfunction "C_C") (pintype "passive"))
      (node (ref "IC30") (pin "20") (pinfunction "OUT15_20") (pintype "output"))
    )
    (net (code "590") (name "Net-(IC31-IREF)") (class "Default")
      (node (ref "IC31") (pin "23") (pinfunction "IREF_23") (pintype "bidirectional"))
      (node (ref "R42") (pin "1") (pinfunction "1_1") (pintype "passive"))
    )
    (net (code "591") (name "Net-(IC31-OUT0)") (class "Default")
      (node (ref "D436") (pin "C") (pinfunction "C_C") (pintype "passive"))
      (node (ref "IC31") (pin "5") (pinfunction "OUT0_5") (pintype "output"))
    )
    (net (code "592") (name "Net-(IC31-OUT1)") (class "Default")
      (node (ref "D437") (pin "C") (pinfunction "C_C") (pintype "passive"))
      (node (ref "IC31") (pin "6") (pinfunction "OUT1_6") (pintype "output"))
    )
    (net (code "593") (name "Net-(IC31-OUT2)") (class "Default")
      (node (ref "D438") (pin "C") (pinfunction "C_C") (pintype "passive"))
      (node (ref "IC31") (pin "7") (pinfunction "OUT2_7") (pintype "output"))
    )
    (net (code "594") (name "Net-(IC31-OUT3)") (class "Default")
      (node (ref "D439") (pin "C") (pinfunction "C_C") (pintype "passive"))
      (node (ref "IC31") (pin "8") (pinfunction "OUT3_8") (pintype "output"))
    )
    (net (code "595") (name "Net-(IC31-OUT4)") (class "Default")
      (node (ref "D440") (pin "C") (pinfunction "C_C") (pintype "passive"))
      (node (ref "IC31") (pin "9") (pinfunction "OUT4_9") (pintype "output"))
    )
    (net (code "596") (name "Net-(IC31-OUT5)") (class "Default")
      (node (ref "D441") (pin "C") (pinfunction "C_C") (pintype "passive"))
      (node (ref "IC31") (pin "10") (pinfunction "OUT5_10") (pintype "output"))
    )
    (net (code "597") (name "Net-(IC31-OUT6)") (class "Default")
      (node (ref "D442") (pin "C") (pinfunction "C_C") (pintype "passive"))
      (node (ref "IC31") (pin "11") (pinfunction "OUT6_11") (pintype "output"))
    )
    (net (code "598") (name "Net-(IC31-OUT7)") (class "Default")
      (node (ref "D443") (pin "C") (pinfunction "C_C") (pintype "passive"))
      (node (ref "IC31") (pin "12") (pinfunction "OUT7_12") (pintype "output"))
    )
    (net (code "599") (name "Net-(IC31-OUT8)") (class "Default")
      (node (ref "D507") (pin "C") (pinfunction "C_C") (pintype "passive"))
      (node (ref "IC31") (pin "13") (pinfunction "OUT8_13") (pintype "output"))
    )
    (net (code "600") (name "Net-(IC31-OUT9)") (class "Default")
      (node (ref "D506") (pin "C") (pinfunction "C_C") (pintype "passive"))
      (node (ref "IC31") (pin "14") (pinfunction "OUT9_14") (pintype "output"))
    )
    (net (code "601") (name "Net-(IC31-OUT10)") (class "Default")
      (node (ref "D505") (pin "C") (pinfunction "C_C") (pintype "passive"))
      (node (ref "IC31") (pin "15") (pinfunction "OUT10_15") (pintype "output"))
    )
    (net (code "602") (name "Net-(IC31-OUT11)") (class "Default")
      (node (ref "D504") (pin "C") (pinfunction "C_C") (pintype "passive"))
      (node (ref "IC31") (pin "16") (pinfunction "OUT11_16") (pintype "output"))
    )
    (net (code "603") (name "Net-(IC31-OUT12)") (class "Default")
      (node (ref "D503") (pin "C") (pinfunction "C_C") (pintype "passive"))
      (node (ref "IC31") (pin "17") (pinfunction "OUT12_17") (pintype "output"))
    )
    (net (code "604") (name "Net-(IC31-OUT13)") (class "Default")
      (node (ref "D502") (pin "C") (pinfunction "C_C") (pintype "passive"))
      (node (ref "IC31") (pin "18") (pinfunction "OUT13_18") (pintype "output"))
    )
    (net (code "605") (name "Net-(IC31-OUT14)") (class "Default")
      (node (ref "D501") (pin "C") (pinfunction "C_C") (pintype "passive"))
      (node (ref "IC31") (pin "19") (pinfunction "OUT14_19") (pintype "output"))
    )
    (net (code "606") (name "Net-(IC31-OUT15)") (class "Default")
      (node (ref "D500") (pin "C") (pinfunction "C_C") (pintype "passive"))
      (node (ref "IC31") (pin "20") (pinfunction "OUT15_20") (pintype "output"))
    )
    (net (code "607") (name "Net-(IC32-IREF)") (class "Default")
      (node (ref "IC32") (pin "23") (pinfunction "IREF_23") (pintype "bidirectional"))
      (node (ref "R43") (pin "1") (pinfunction "1_1") (pintype "passive"))
    )
    (net (code "608") (name "Net-(IC32-OUT0)") (class "Default")
      (node (ref "D444") (pin "C") (pinfunction "C_C") (pintype "passive"))
      (node (ref "IC32") (pin "5") (pinfunction "OUT0_5") (pintype "output"))
    )
    (net (code "609") (name "Net-(IC32-OUT1)") (class "Default")
      (node (ref "D445") (pin "C") (pinfunction "C_C") (pintype "passive"))
      (node (ref "IC32") (pin "6") (pinfunction "OUT1_6") (pintype "output"))
    )
    (net (code "610") (name "Net-(IC32-OUT2)") (class "Default")
      (node (ref "D446") (pin "C") (pinfunction "C_C") (pintype "passive"))
      (node (ref "IC32") (pin "7") (pinfunction "OUT2_7") (pintype "output"))
    )
    (net (code "611") (name "Net-(IC32-OUT3)") (class "Default")
      (node (ref "D447") (pin "C") (pinfunction "C_C") (pintype "passive"))
      (node (ref "IC32") (pin "8") (pinfunction "OUT3_8") (pintype "output"))
    )
    (net (code "612") (name "Net-(IC32-OUT4)") (class "Default")
      (node (ref "D448") (pin "C") (pinfunction "C_C") (pintype "passive"))
      (node (ref "IC32") (pin "9") (pinfunction "OUT4_9") (pintype "output"))
    )
    (net (code "613") (name "Net-(IC32-OUT5)") (class "Default")
      (node (ref "D449") (pin "C") (pinfunction "C_C") (pintype "passive"))
      (node (ref "IC32") (pin "10") (pinfunction "OUT5_10") (pintype "output"))
    )
    (net (code "614") (name "Net-(IC32-OUT6)") (class "Default")
      (node (ref "D450") (pin "C") (pinfunction "C_C") (pintype "passive"))
      (node (ref "IC32") (pin "11") (pinfunction "OUT6_11") (pintype "output"))
    )
    (net (code "615") (name "Net-(IC32-OUT7)") (class "Default")
      (node (ref "D451") (pin "C") (pinfunction "C_C") (pintype "passive"))
      (node (ref "IC32") (pin "12") (pinfunction "OUT7_12") (pintype "output"))
    )
    (net (code "616") (name "Net-(IC32-OUT8)") (class "Default")
      (node (ref "D515") (pin "C") (pinfunction "C_C") (pintype "passive"))
      (node (ref "IC32") (pin "13") (pinfunction "OUT8_13") (pintype "output"))
    )
    (net (code "617") (name "Net-(IC32-OUT9)") (class "Default")
      (node (ref "D514") (pin "C") (pinfunction "C_C") (pintype "passive"))
      (node (ref "IC32") (pin "14") (pinfunction "OUT9_14") (pintype "output"))
    )
    (net (code "618") (name "Net-(IC32-OUT10)") (class "Default")
      (node (ref "D513") (pin "C") (pinfunction "C_C") (pintype "passive"))
      (node (ref "IC32") (pin "15") (pinfunction "OUT10_15") (pintype "output"))
    )
    (net (code "619") (name "Net-(IC32-OUT11)") (class "Default")
      (node (ref "D512") (pin "C") (pinfunction "C_C") (pintype "passive"))
      (node (ref "IC32") (pin "16") (pinfunction "OUT11_16") (pintype "output"))
    )
    (net (code "620") (name "Net-(IC32-OUT12)") (class "Default")
      (node (ref "D511") (pin "C") (pinfunction "C_C") (pintype "passive"))
      (node (ref "IC32") (pin "17") (pinfunction "OUT12_17") (pintype "output"))
    )
    (net (code "621") (name "Net-(IC32-OUT13)") (class "Default")
      (node (ref "D510") (pin "C") (pinfunction "C_C") (pintype "passive"))
      (node (ref "IC32") (pin "18") (pinfunction "OUT13_18") (pintype "output"))
    )
    (net (code "622") (name "Net-(IC32-OUT14)") (class "Default")
      (node (ref "D509") (pin "C") (pinfunction "C_C") (pintype "passive"))
      (node (ref "IC32") (pin "19") (pinfunction "OUT14_19") (pintype "output"))
    )
    (net (code "623") (name "Net-(IC32-OUT15)") (class "Default")
      (node (ref "D508") (pin "C") (pinfunction "C_C") (pintype "passive"))
      (node (ref "IC32") (pin "20") (pinfunction "OUT15_20") (pintype "output"))
    )
    (net (code "624") (name "Net-(IC33-IREF)") (class "Default")
      (node (ref "IC33") (pin "23") (pinfunction "IREF_23") (pintype "bidirectional"))
      (node (ref "R44") (pin "1") (pinfunction "1_1") (pintype "passive"))
    )
    (net (code "625") (name "Net-(IC33-OUT0)") (class "Default")
      (node (ref "D516") (pin "C") (pinfunction "C_C") (pintype "passive"))
      (node (ref "IC33") (pin "5") (pinfunction "OUT0_5") (pintype "output"))
    )
    (net (code "626") (name "Net-(IC33-OUT1)") (class "Default")
      (node (ref "D517") (pin "C") (pinfunction "C_C") (pintype "passive"))
      (node (ref "IC33") (pin "6") (pinfunction "OUT1_6") (pintype "output"))
    )
    (net (code "627") (name "Net-(IC33-OUT2)") (class "Default")
      (node (ref "D518") (pin "C") (pinfunction "C_C") (pintype "passive"))
      (node (ref "IC33") (pin "7") (pinfunction "OUT2_7") (pintype "output"))
    )
    (net (code "628") (name "Net-(IC33-OUT3)") (class "Default")
      (node (ref "D519") (pin "C") (pinfunction "C_C") (pintype "passive"))
      (node (ref "IC33") (pin "8") (pinfunction "OUT3_8") (pintype "output"))
    )
    (net (code "629") (name "Net-(IC33-OUT4)") (class "Default")
      (node (ref "D520") (pin "C") (pinfunction "C_C") (pintype "passive"))
      (node (ref "IC33") (pin "9") (pinfunction "OUT4_9") (pintype "output"))
    )
    (net (code "630") (name "Net-(IC33-OUT5)") (class "Default")
      (node (ref "D521") (pin "C") (pinfunction "C_C") (pintype "passive"))
      (node (ref "IC33") (pin "10") (pinfunction "OUT5_10") (pintype "output"))
    )
    (net (code "631") (name "Net-(IC33-OUT6)") (class "Default")
      (node (ref "D522") (pin "C") (pinfunction "C_C") (pintype "passive"))
      (node (ref "IC33") (pin "11") (pinfunction "OUT6_11") (pintype "output"))
    )
    (net (code "632") (name "Net-(IC33-OUT7)") (class "Default")
      (node (ref "D523") (pin "C") (pinfunction "C_C") (pintype "passive"))
      (node (ref "IC33") (pin "12") (pinfunction "OUT7_12") (pintype "output"))
    )
    (net (code "633") (name "Net-(IC33-OUT8)") (class "Default")
      (node (ref "D587") (pin "C") (pinfunction "C_C") (pintype "passive"))
      (node (ref "IC33") (pin "13") (pinfunction "OUT8_13") (pintype "output"))
    )
    (net (code "634") (name "Net-(IC33-OUT9)") (class "Default")
      (node (ref "D586") (pin "C") (pinfunction "C_C") (pintype "passive"))
      (node (ref "IC33") (pin "14") (pinfunction "OUT9_14") (pintype "output"))
    )
    (net (code "635") (name "Net-(IC33-OUT10)") (class "Default")
      (node (ref "D585") (pin "C") (pinfunction "C_C") (pintype "passive"))
      (node (ref "IC33") (pin "15") (pinfunction "OUT10_15") (pintype "output"))
    )
    (net (code "636") (name "Net-(IC33-OUT11)") (class "Default")
      (node (ref "D584") (pin "C") (pinfunction "C_C") (pintype "passive"))
      (node (ref "IC33") (pin "16") (pinfunction "OUT11_16") (pintype "output"))
    )
    (net (code "637") (name "Net-(IC33-OUT12)") (class "Default")
      (node (ref "D583") (pin "C") (pinfunction "C_C") (pintype "passive"))
      (node (ref "IC33") (pin "17") (pinfunction "OUT12_17") (pintype "output"))
    )
    (net (code "638") (name "Net-(IC33-OUT13)") (class "Default")
      (node (ref "D582") (pin "C") (pinfunction "C_C") (pintype "passive"))
      (node (ref "IC33") (pin "18") (pinfunction "OUT13_18") (pintype "output"))
    )
    (net (code "639") (name "Net-(IC33-OUT14)") (class "Default")
      (node (ref "D581") (pin "C") (pinfunction "C_C") (pintype "passive"))
      (node (ref "IC33") (pin "19") (pinfunction "OUT14_19") (pintype "output"))
    )
    (net (code "640") (name "Net-(IC33-OUT15)") (class "Default")
      (node (ref "D580") (pin "C") (pinfunction "C_C") (pintype "passive"))
      (node (ref "IC33") (pin "20") (pinfunction "OUT15_20") (pintype "output"))
    )
    (net (code "641") (name "Net-(IC34-IREF)") (class "Default")
      (node (ref "IC34") (pin "23") (pinfunction "IREF_23") (pintype "bidirectional"))
      (node (ref "R45") (pin "1") (pinfunction "1_1") (pintype "passive"))
    )
    (net (code "642") (name "Net-(IC34-OUT0)") (class "Default")
      (node (ref "D524") (pin "C") (pinfunction "C_C") (pintype "passive"))
      (node (ref "IC34") (pin "5") (pinfunction "OUT0_5") (pintype "output"))
    )
    (net (code "643") (name "Net-(IC34-OUT1)") (class "Default")
      (node (ref "D525") (pin "C") (pinfunction "C_C") (pintype "passive"))
      (node (ref "IC34") (pin "6") (pinfunction "OUT1_6") (pintype "output"))
    )
    (net (code "644") (name "Net-(IC34-OUT2)") (class "Default")
      (node (ref "D526") (pin "C") (pinfunction "C_C") (pintype "passive"))
      (node (ref "IC34") (pin "7") (pinfunction "OUT2_7") (pintype "output"))
    )
    (net (code "645") (name "Net-(IC34-OUT3)") (class "Default")
      (node (ref "D527") (pin "C") (pinfunction "C_C") (pintype "passive"))
      (node (ref "IC34") (pin "8") (pinfunction "OUT3_8") (pintype "output"))
    )
    (net (code "646") (name "Net-(IC34-OUT4)") (class "Default")
      (node (ref "D528") (pin "C") (pinfunction "C_C") (pintype "passive"))
      (node (ref "IC34") (pin "9") (pinfunction "OUT4_9") (pintype "output"))
    )
    (net (code "647") (name "Net-(IC34-OUT5)") (class "Default")
      (node (ref "D529") (pin "C") (pinfunction "C_C") (pintype "passive"))
      (node (ref "IC34") (pin "10") (pinfunction "OUT5_10") (pintype "output"))
    )
    (net (code "648") (name "Net-(IC34-OUT6)") (class "Default")
      (node (ref "D530") (pin "C") (pinfunction "C_C") (pintype "passive"))
      (node (ref "IC34") (pin "11") (pinfunction "OUT6_11") (pintype "output"))
    )
    (net (code "649") (name "Net-(IC34-OUT7)") (class "Default")
      (node (ref "D531") (pin "C") (pinfunction "C_C") (pintype "passive"))
      (node (ref "IC34") (pin "12") (pinfunction "OUT7_12") (pintype "output"))
    )
    (net (code "650") (name "Net-(IC34-OUT8)") (class "Default")
      (node (ref "D595") (pin "C") (pinfunction "C_C") (pintype "passive"))
      (node (ref "IC34") (pin "13") (pinfunction "OUT8_13") (pintype "output"))
    )
    (net (code "651") (name "Net-(IC34-OUT9)") (class "Default")
      (node (ref "D594") (pin "C") (pinfunction "C_C") (pintype "passive"))
      (node (ref "IC34") (pin "14") (pinfunction "OUT9_14") (pintype "output"))
    )
    (net (code "652") (name "Net-(IC34-OUT10)") (class "Default")
      (node (ref "D593") (pin "C") (pinfunction "C_C") (pintype "passive"))
      (node (ref "IC34") (pin "15") (pinfunction "OUT10_15") (pintype "output"))
    )
    (net (code "653") (name "Net-(IC34-OUT11)") (class "Default")
      (node (ref "D592") (pin "C") (pinfunction "C_C") (pintype "passive"))
      (node (ref "IC34") (pin "16") (pinfunction "OUT11_16") (pintype "output"))
    )
    (net (code "654") (name "Net-(IC34-OUT12)") (class "Default")
      (node (ref "D591") (pin "C") (pinfunction "C_C") (pintype "passive"))
      (node (ref "IC34") (pin "17") (pinfunction "OUT12_17") (pintype "output"))
    )
    (net (code "655") (name "Net-(IC34-OUT13)") (class "Default")
      (node (ref "D590") (pin "C") (pinfunction "C_C") (pintype "passive"))
      (node (ref "IC34") (pin "18") (pinfunction "OUT13_18") (pintype "output"))
    )
    (net (code "656") (name "Net-(IC34-OUT14)") (class "Default")
      (node (ref "D589") (pin "C") (pinfunction "C_C") (pintype "passive"))
      (node (ref "IC34") (pin "19") (pinfunction "OUT14_19") (pintype "output"))
    )
    (net (code "657") (name "Net-(IC34-OUT15)") (class "Default")
      (node (ref "D588") (pin "C") (pinfunction "C_C") (pintype "passive"))
      (node (ref "IC34") (pin "20") (pinfunction "OUT15_20") (pintype "output"))
    )
    (net (code "658") (name "Net-(IC35-IREF)") (class "Default")
      (node (ref "IC35") (pin "23") (pinfunction "IREF_23") (pintype "bidirectional"))
      (node (ref "R46") (pin "1") (pinfunction "1_1") (pintype "passive"))
    )
    (net (code "659") (name "Net-(IC35-OUT0)") (class "Default")
      (node (ref "D532") (pin "C") (pinfunction "C_C") (pintype "passive"))
      (node (ref "IC35") (pin "5") (pinfunction "OUT0_5") (pintype "output"))
    )
    (net (code "660") (name "Net-(IC35-OUT1)") (class "Default")
      (node (ref "D533") (pin "C") (pinfunction "C_C") (pintype "passive"))
      (node (ref "IC35") (pin "6") (pinfunction "OUT1_6") (pintype "output"))
    )
    (net (code "661") (name "Net-(IC35-OUT2)") (class "Default")
      (node (ref "D534") (pin "C") (pinfunction "C_C") (pintype "passive"))
      (node (ref "IC35") (pin "7") (pinfunction "OUT2_7") (pintype "output"))
    )
    (net (code "662") (name "Net-(IC35-OUT3)") (class "Default")
      (node (ref "D535") (pin "C") (pinfunction "C_C") (pintype "passive"))
      (node (ref "IC35") (pin "8") (pinfunction "OUT3_8") (pintype "output"))
    )
    (net (code "663") (name "Net-(IC35-OUT4)") (class "Default")
      (node (ref "D536") (pin "C") (pinfunction "C_C") (pintype "passive"))
      (node (ref "IC35") (pin "9") (pinfunction "OUT4_9") (pintype "output"))
    )
    (net (code "664") (name "Net-(IC35-OUT5)") (class "Default")
      (node (ref "D537") (pin "C") (pinfunction "C_C") (pintype "passive"))
      (node (ref "IC35") (pin "10") (pinfunction "OUT5_10") (pintype "output"))
    )
    (net (code "665") (name "Net-(IC35-OUT6)") (class "Default")
      (node (ref "D538") (pin "C") (pinfunction "C_C") (pintype "passive"))
      (node (ref "IC35") (pin "11") (pinfunction "OUT6_11") (pintype "output"))
    )
    (net (code "666") (name "Net-(IC35-OUT7)") (class "Default")
      (node (ref "D539") (pin "C") (pinfunction "C_C") (pintype "passive"))
      (node (ref "IC35") (pin "12") (pinfunction "OUT7_12") (pintype "output"))
    )
    (net (code "667") (name "Net-(IC35-OUT8)") (class "Default")
      (node (ref "D603") (pin "C") (pinfunction "C_C") (pintype "passive"))
      (node (ref "IC35") (pin "13") (pinfunction "OUT8_13") (pintype "output"))
    )
    (net (code "668") (name "Net-(IC35-OUT9)") (class "Default")
      (node (ref "D602") (pin "C") (pinfunction "C_C") (pintype "passive"))
      (node (ref "IC35") (pin "14") (pinfunction "OUT9_14") (pintype "output"))
    )
    (net (code "669") (name "Net-(IC35-OUT10)") (class "Default")
      (node (ref "D601") (pin "C") (pinfunction "C_C") (pintype "passive"))
      (node (ref "IC35") (pin "15") (pinfunction "OUT10_15") (pintype "output"))
    )
    (net (code "670") (name "Net-(IC35-OUT11)") (class "Default")
      (node (ref "D600") (pin "C") (pinfunction "C_C") (pintype "passive"))
      (node (ref "IC35") (pin "16") (pinfunction "OUT11_16") (pintype "output"))
    )
    (net (code "671") (name "Net-(IC35-OUT12)") (class "Default")
      (node (ref "D599") (pin "C") (pinfunction "C_C") (pintype "passive"))
      (node (ref "IC35") (pin "17") (pinfunction "OUT12_17") (pintype "output"))
    )
    (net (code "672") (name "Net-(IC35-OUT13)") (class "Default")
      (node (ref "D598") (pin "C") (pinfunction "C_C") (pintype "passive"))
      (node (ref "IC35") (pin "18") (pinfunction "OUT13_18") (pintype "output"))
    )
    (net (code "673") (name "Net-(IC35-OUT14)") (class "Default")
      (node (ref "D597") (pin "C") (pinfunction "C_C") (pintype "passive"))
      (node (ref "IC35") (pin "19") (pinfunction "OUT14_19") (pintype "output"))
    )
    (net (code "674") (name "Net-(IC35-OUT15)") (class "Default")
      (node (ref "D596") (pin "C") (pinfunction "C_C") (pintype "passive"))
      (node (ref "IC35") (pin "20") (pinfunction "OUT15_20") (pintype "output"))
    )
    (net (code "675") (name "Net-(IC36-IREF)") (class "Default")
      (node (ref "IC36") (pin "23") (pinfunction "IREF_23") (pintype "bidirectional"))
      (node (ref "R47") (pin "1") (pinfunction "1_1") (pintype "passive"))
    )
    (net (code "676") (name "Net-(IC36-OUT0)") (class "Default")
      (node (ref "D540") (pin "C") (pinfunction "C_C") (pintype "passive"))
      (node (ref "IC36") (pin "5") (pinfunction "OUT0_5") (pintype "output"))
    )
    (net (code "677") (name "Net-(IC36-OUT1)") (class "Default")
      (node (ref "D541") (pin "C") (pinfunction "C_C") (pintype "passive"))
      (node (ref "IC36") (pin "6") (pinfunction "OUT1_6") (pintype "output"))
    )
    (net (code "678") (name "Net-(IC36-OUT2)") (class "Default")
      (node (ref "D542") (pin "C") (pinfunction "C_C") (pintype "passive"))
      (node (ref "IC36") (pin "7") (pinfunction "OUT2_7") (pintype "output"))
    )
    (net (code "679") (name "Net-(IC36-OUT3)") (class "Default")
      (node (ref "D543") (pin "C") (pinfunction "C_C") (pintype "passive"))
      (node (ref "IC36") (pin "8") (pinfunction "OUT3_8") (pintype "output"))
    )
    (net (code "680") (name "Net-(IC36-OUT4)") (class "Default")
      (node (ref "D544") (pin "C") (pinfunction "C_C") (pintype "passive"))
      (node (ref "IC36") (pin "9") (pinfunction "OUT4_9") (pintype "output"))
    )
    (net (code "681") (name "Net-(IC36-OUT5)") (class "Default")
      (node (ref "D545") (pin "C") (pinfunction "C_C") (pintype "passive"))
      (node (ref "IC36") (pin "10") (pinfunction "OUT5_10") (pintype "output"))
    )
    (net (code "682") (name "Net-(IC36-OUT6)") (class "Default")
      (node (ref "D546") (pin "C") (pinfunction "C_C") (pintype "passive"))
      (node (ref "IC36") (pin "11") (pinfunction "OUT6_11") (pintype "output"))
    )
    (net (code "683") (name "Net-(IC36-OUT7)") (class "Default")
      (node (ref "D547") (pin "C") (pinfunction "C_C") (pintype "passive"))
      (node (ref "IC36") (pin "12") (pinfunction "OUT7_12") (pintype "output"))
    )
    (net (code "684") (name "Net-(IC36-OUT8)") (class "Default")
      (node (ref "D611") (pin "C") (pinfunction "C_C") (pintype "passive"))
      (node (ref "IC36") (pin "13") (pinfunction "OUT8_13") (pintype "output"))
    )
    (net (code "685") (name "Net-(IC36-OUT9)") (class "Default")
      (node (ref "D610") (pin "C") (pinfunction "C_C") (pintype "passive"))
      (node (ref "IC36") (pin "14") (pinfunction "OUT9_14") (pintype "output"))
    )
    (net (code "686") (name "Net-(IC36-OUT10)") (class "Default")
      (node (ref "D609") (pin "C") (pinfunction "C_C") (pintype "passive"))
      (node (ref "IC36") (pin "15") (pinfunction "OUT10_15") (pintype "output"))
    )
    (net (code "687") (name "Net-(IC36-OUT11)") (class "Default")
      (node (ref "D608") (pin "C") (pinfunction "C_C") (pintype "passive"))
      (node (ref "IC36") (pin "16") (pinfunction "OUT11_16") (pintype "output"))
    )
    (net (code "688") (name "Net-(IC36-OUT12)") (class "Default")
      (node (ref "D607") (pin "C") (pinfunction "C_C") (pintype "passive"))
      (node (ref "IC36") (pin "17") (pinfunction "OUT12_17") (pintype "output"))
    )
    (net (code "689") (name "Net-(IC36-OUT13)") (class "Default")
      (node (ref "D606") (pin "C") (pinfunction "C_C") (pintype "passive"))
      (node (ref "IC36") (pin "18") (pinfunction "OUT13_18") (pintype "output"))
    )
    (net (code "690") (name "Net-(IC36-OUT14)") (class "Default")
      (node (ref "D605") (pin "C") (pinfunction "C_C") (pintype "passive"))
      (node (ref "IC36") (pin "19") (pinfunction "OUT14_19") (pintype "output"))
    )
    (net (code "691") (name "Net-(IC36-OUT15)") (class "Default")
      (node (ref "D604") (pin "C") (pinfunction "C_C") (pintype "passive"))
      (node (ref "IC36") (pin "20") (pinfunction "OUT15_20") (pintype "output"))
    )
    (net (code "692") (name "Net-(IC37-IREF)") (class "Default")
      (node (ref "IC37") (pin "23") (pinfunction "IREF_23") (pintype "bidirectional"))
      (node (ref "R48") (pin "1") (pinfunction "1_1") (pintype "passive"))
    )
    (net (code "693") (name "Net-(IC37-OUT0)") (class "Default")
      (node (ref "D548") (pin "C") (pinfunction "C_C") (pintype "passive"))
      (node (ref "IC37") (pin "5") (pinfunction "OUT0_5") (pintype "output"))
    )
    (net (code "694") (name "Net-(IC37-OUT1)") (class "Default")
      (node (ref "D549") (pin "C") (pinfunction "C_C") (pintype "passive"))
      (node (ref "IC37") (pin "6") (pinfunction "OUT1_6") (pintype "output"))
    )
    (net (code "695") (name "Net-(IC37-OUT2)") (class "Default")
      (node (ref "D550") (pin "C") (pinfunction "C_C") (pintype "passive"))
      (node (ref "IC37") (pin "7") (pinfunction "OUT2_7") (pintype "output"))
    )
    (net (code "696") (name "Net-(IC37-OUT3)") (class "Default")
      (node (ref "D551") (pin "C") (pinfunction "C_C") (pintype "passive"))
      (node (ref "IC37") (pin "8") (pinfunction "OUT3_8") (pintype "output"))
    )
    (net (code "697") (name "Net-(IC37-OUT4)") (class "Default")
      (node (ref "D552") (pin "C") (pinfunction "C_C") (pintype "passive"))
      (node (ref "IC37") (pin "9") (pinfunction "OUT4_9") (pintype "output"))
    )
    (net (code "698") (name "Net-(IC37-OUT5)") (class "Default")
      (node (ref "D553") (pin "C") (pinfunction "C_C") (pintype "passive"))
      (node (ref "IC37") (pin "10") (pinfunction "OUT5_10") (pintype "output"))
    )
    (net (code "699") (name "Net-(IC37-OUT6)") (class "Default")
      (node (ref "D554") (pin "C") (pinfunction "C_C") (pintype "passive"))
      (node (ref "IC37") (pin "11") (pinfunction "OUT6_11") (pintype "output"))
    )
    (net (code "700") (name "Net-(IC37-OUT7)") (class "Default")
      (node (ref "D555") (pin "C") (pinfunction "C_C") (pintype "passive"))
      (node (ref "IC37") (pin "12") (pinfunction "OUT7_12") (pintype "output"))
    )
    (net (code "701") (name "Net-(IC37-OUT8)") (class "Default")
      (node (ref "D619") (pin "C") (pinfunction "C_C") (pintype "passive"))
      (node (ref "IC37") (pin "13") (pinfunction "OUT8_13") (pintype "output"))
    )
    (net (code "702") (name "Net-(IC37-OUT9)") (class "Default")
      (node (ref "D618") (pin "C") (pinfunction "C_C") (pintype "passive"))
      (node (ref "IC37") (pin "14") (pinfunction "OUT9_14") (pintype "output"))
    )
    (net (code "703") (name "Net-(IC37-OUT10)") (class "Default")
      (node (ref "D617") (pin "C") (pinfunction "C_C") (pintype "passive"))
      (node (ref "IC37") (pin "15") (pinfunction "OUT10_15") (pintype "output"))
    )
    (net (code "704") (name "Net-(IC37-OUT11)") (class "Default")
      (node (ref "D616") (pin "C") (pinfunction "C_C") (pintype "passive"))
      (node (ref "IC37") (pin "16") (pinfunction "OUT11_16") (pintype "output"))
    )
    (net (code "705") (name "Net-(IC37-OUT12)") (class "Default")
      (node (ref "D615") (pin "C") (pinfunction "C_C") (pintype "passive"))
      (node (ref "IC37") (pin "17") (pinfunction "OUT12_17") (pintype "output"))
    )
    (net (code "706") (name "Net-(IC37-OUT13)") (class "Default")
      (node (ref "D614") (pin "C") (pinfunction "C_C") (pintype "passive"))
      (node (ref "IC37") (pin "18") (pinfunction "OUT13_18") (pintype "output"))
    )
    (net (code "707") (name "Net-(IC37-OUT14)") (class "Default")
      (node (ref "D613") (pin "C") (pinfunction "C_C") (pintype "passive"))
      (node (ref "IC37") (pin "19") (pinfunction "OUT14_19") (pintype "output"))
    )
    (net (code "708") (name "Net-(IC37-OUT15)") (class "Default")
      (node (ref "D612") (pin "C") (pinfunction "C_C") (pintype "passive"))
      (node (ref "IC37") (pin "20") (pinfunction "OUT15_20") (pintype "output"))
    )
    (net (code "709") (name "Net-(IC38-IREF)") (class "Default")
      (node (ref "IC38") (pin "23") (pinfunction "IREF_23") (pintype "bidirectional"))
      (node (ref "R49") (pin "1") (pinfunction "1_1") (pintype "passive"))
    )
    (net (code "710") (name "Net-(IC38-OUT0)") (class "Default")
      (node (ref "D556") (pin "C") (pinfunction "C_C") (pintype "passive"))
      (node (ref "IC38") (pin "5") (pinfunction "OUT0_5") (pintype "output"))
    )
    (net (code "711") (name "Net-(IC38-OUT1)") (class "Default")
      (node (ref "D557") (pin "C") (pinfunction "C_C") (pintype "passive"))
      (node (ref "IC38") (pin "6") (pinfunction "OUT1_6") (pintype "output"))
    )
    (net (code "712") (name "Net-(IC38-OUT2)") (class "Default")
      (node (ref "D558") (pin "C") (pinfunction "C_C") (pintype "passive"))
      (node (ref "IC38") (pin "7") (pinfunction "OUT2_7") (pintype "output"))
    )
    (net (code "713") (name "Net-(IC38-OUT3)") (class "Default")
      (node (ref "D559") (pin "C") (pinfunction "C_C") (pintype "passive"))
      (node (ref "IC38") (pin "8") (pinfunction "OUT3_8") (pintype "output"))
    )
    (net (code "714") (name "Net-(IC38-OUT4)") (class "Default")
      (node (ref "D560") (pin "C") (pinfunction "C_C") (pintype "passive"))
      (node (ref "IC38") (pin "9") (pinfunction "OUT4_9") (pintype "output"))
    )
    (net (code "715") (name "Net-(IC38-OUT5)") (class "Default")
      (node (ref "D561") (pin "C") (pinfunction "C_C") (pintype "passive"))
      (node (ref "IC38") (pin "10") (pinfunction "OUT5_10") (pintype "output"))
    )
    (net (code "716") (name "Net-(IC38-OUT6)") (class "Default")
      (node (ref "D562") (pin "C") (pinfunction "C_C") (pintype "passive"))
      (node (ref "IC38") (pin "11") (pinfunction "OUT6_11") (pintype "output"))
    )
    (net (code "717") (name "Net-(IC38-OUT7)") (class "Default")
      (node (ref "D563") (pin "C") (pinfunction "C_C") (pintype "passive"))
      (node (ref "IC38") (pin "12") (pinfunction "OUT7_12") (pintype "output"))
    )
    (net (code "718") (name "Net-(IC38-OUT8)") (class "Default")
      (node (ref "D627") (pin "C") (pinfunction "C_C") (pintype "passive"))
      (node (ref "IC38") (pin "13") (pinfunction "OUT8_13") (pintype "output"))
    )
    (net (code "719") (name "Net-(IC38-OUT9)") (class "Default")
      (node (ref "D626") (pin "C") (pinfunction "C_C") (pintype "passive"))
      (node (ref "IC38") (pin "14") (pinfunction "OUT9_14") (pintype "output"))
    )
    (net (code "720") (name "Net-(IC38-OUT10)") (class "Default")
      (node (ref "D625") (pin "C") (pinfunction "C_C") (pintype "passive"))
      (node (ref "IC38") (pin "15") (pinfunction "OUT10_15") (pintype "output"))
    )
    (net (code "721") (name "Net-(IC38-OUT11)") (class "Default")
      (node (ref "D624") (pin "C") (pinfunction "C_C") (pintype "passive"))
      (node (ref "IC38") (pin "16") (pinfunction "OUT11_16") (pintype "output"))
    )
    (net (code "722") (name "Net-(IC38-OUT12)") (class "Default")
      (node (ref "D623") (pin "C") (pinfunction "C_C") (pintype "passive"))
      (node (ref "IC38") (pin "17") (pinfunction "OUT12_17") (pintype "output"))
    )
    (net (code "723") (name "Net-(IC38-OUT13)") (class "Default")
      (node (ref "D622") (pin "C") (pinfunction "C_C") (pintype "passive"))
      (node (ref "IC38") (pin "18") (pinfunction "OUT13_18") (pintype "output"))
    )
    (net (code "724") (name "Net-(IC38-OUT14)") (class "Default")
      (node (ref "D621") (pin "C") (pinfunction "C_C") (pintype "passive"))
      (node (ref "IC38") (pin "19") (pinfunction "OUT14_19") (pintype "output"))
    )
    (net (code "725") (name "Net-(IC38-OUT15)") (class "Default")
      (node (ref "D620") (pin "C") (pinfunction "C_C") (pintype "passive"))
      (node (ref "IC38") (pin "20") (pinfunction "OUT15_20") (pintype "output"))
    )
    (net (code "726") (name "Net-(IC39-IREF)") (class "Default")
      (node (ref "IC39") (pin "23") (pinfunction "IREF_23") (pintype "bidirectional"))
      (node (ref "R50") (pin "1") (pinfunction "1_1") (pintype "passive"))
    )
    (net (code "727") (name "Net-(IC39-OUT0)") (class "Default")
      (node (ref "D564") (pin "C") (pinfunction "C_C") (pintype "passive"))
      (node (ref "IC39") (pin "5") (pinfunction "OUT0_5") (pintype "output"))
    )
    (net (code "728") (name "Net-(IC39-OUT1)") (class "Default")
      (node (ref "D565") (pin "C") (pinfunction "C_C") (pintype "passive"))
      (node (ref "IC39") (pin "6") (pinfunction "OUT1_6") (pintype "output"))
    )
    (net (code "729") (name "Net-(IC39-OUT2)") (class "Default")
      (node (ref "D566") (pin "C") (pinfunction "C_C") (pintype "passive"))
      (node (ref "IC39") (pin "7") (pinfunction "OUT2_7") (pintype "output"))
    )
    (net (code "730") (name "Net-(IC39-OUT3)") (class "Default")
      (node (ref "D567") (pin "C") (pinfunction "C_C") (pintype "passive"))
      (node (ref "IC39") (pin "8") (pinfunction "OUT3_8") (pintype "output"))
    )
    (net (code "731") (name "Net-(IC39-OUT4)") (class "Default")
      (node (ref "D568") (pin "C") (pinfunction "C_C") (pintype "passive"))
      (node (ref "IC39") (pin "9") (pinfunction "OUT4_9") (pintype "output"))
    )
    (net (code "732") (name "Net-(IC39-OUT5)") (class "Default")
      (node (ref "D569") (pin "C") (pinfunction "C_C") (pintype "passive"))
      (node (ref "IC39") (pin "10") (pinfunction "OUT5_10") (pintype "output"))
    )
    (net (code "733") (name "Net-(IC39-OUT6)") (class "Default")
      (node (ref "D570") (pin "C") (pinfunction "C_C") (pintype "passive"))
      (node (ref "IC39") (pin "11") (pinfunction "OUT6_11") (pintype "output"))
    )
    (net (code "734") (name "Net-(IC39-OUT7)") (class "Default")
      (node (ref "D571") (pin "C") (pinfunction "C_C") (pintype "passive"))
      (node (ref "IC39") (pin "12") (pinfunction "OUT7_12") (pintype "output"))
    )
    (net (code "735") (name "Net-(IC39-OUT8)") (class "Default")
      (node (ref "D635") (pin "C") (pinfunction "C_C") (pintype "passive"))
      (node (ref "IC39") (pin "13") (pinfunction "OUT8_13") (pintype "output"))
    )
    (net (code "736") (name "Net-(IC39-OUT9)") (class "Default")
      (node (ref "D634") (pin "C") (pinfunction "C_C") (pintype "passive"))
      (node (ref "IC39") (pin "14") (pinfunction "OUT9_14") (pintype "output"))
    )
    (net (code "737") (name "Net-(IC39-OUT10)") (class "Default")
      (node (ref "D633") (pin "C") (pinfunction "C_C") (pintype "passive"))
      (node (ref "IC39") (pin "15") (pinfunction "OUT10_15") (pintype "output"))
    )
    (net (code "738") (name "Net-(IC39-OUT11)") (class "Default")
      (node (ref "D632") (pin "C") (pinfunction "C_C") (pintype "passive"))
      (node (ref "IC39") (pin "16") (pinfunction "OUT11_16") (pintype "output"))
    )
    (net (code "739") (name "Net-(IC39-OUT12)") (class "Default")
      (node (ref "D631") (pin "C") (pinfunction "C_C") (pintype "passive"))
      (node (ref "IC39") (pin "17") (pinfunction "OUT12_17") (pintype "output"))
    )
    (net (code "740") (name "Net-(IC39-OUT13)") (class "Default")
      (node (ref "D630") (pin "C") (pinfunction "C_C") (pintype "passive"))
      (node (ref "IC39") (pin "18") (pinfunction "OUT13_18") (pintype "output"))
    )
    (net (code "741") (name "Net-(IC39-OUT14)") (class "Default")
      (node (ref "D629") (pin "C") (pinfunction "C_C") (pintype "passive"))
      (node (ref "IC39") (pin "19") (pinfunction "OUT14_19") (pintype "output"))
    )
    (net (code "742") (name "Net-(IC39-OUT15)") (class "Default")
      (node (ref "D628") (pin "C") (pinfunction "C_C") (pintype "passive"))
      (node (ref "IC39") (pin "20") (pinfunction "OUT15_20") (pintype "output"))
    )
    (net (code "743") (name "Net-(IC40-IREF)") (class "Default")
      (node (ref "IC40") (pin "23") (pinfunction "IREF_23") (pintype "bidirectional"))
      (node (ref "R51") (pin "1") (pinfunction "1_1") (pintype "passive"))
    )
    (net (code "744") (name "Net-(IC40-OUT0)") (class "Default")
      (node (ref "D572") (pin "C") (pinfunction "C_C") (pintype "passive"))
      (node (ref "IC40") (pin "5") (pinfunction "OUT0_5") (pintype "output"))
    )
    (net (code "745") (name "Net-(IC40-OUT1)") (class "Default")
      (node (ref "D573") (pin "C") (pinfunction "C_C") (pintype "passive"))
      (node (ref "IC40") (pin "6") (pinfunction "OUT1_6") (pintype "output"))
    )
    (net (code "746") (name "Net-(IC40-OUT2)") (class "Default")
      (node (ref "D574") (pin "C") (pinfunction "C_C") (pintype "passive"))
      (node (ref "IC40") (pin "7") (pinfunction "OUT2_7") (pintype "output"))
    )
    (net (code "747") (name "Net-(IC40-OUT3)") (class "Default")
      (node (ref "D575") (pin "C") (pinfunction "C_C") (pintype "passive"))
      (node (ref "IC40") (pin "8") (pinfunction "OUT3_8") (pintype "output"))
    )
    (net (code "748") (name "Net-(IC40-OUT4)") (class "Default")
      (node (ref "D576") (pin "C") (pinfunction "C_C") (pintype "passive"))
      (node (ref "IC40") (pin "9") (pinfunction "OUT4_9") (pintype "output"))
    )
    (net (code "749") (name "Net-(IC40-OUT5)") (class "Default")
      (node (ref "D577") (pin "C") (pinfunction "C_C") (pintype "passive"))
      (node (ref "IC40") (pin "10") (pinfunction "OUT5_10") (pintype "output"))
    )
    (net (code "750") (name "Net-(IC40-OUT6)") (class "Default")
      (node (ref "D578") (pin "C") (pinfunction "C_C") (pintype "passive"))
      (node (ref "IC40") (pin "11") (pinfunction "OUT6_11") (pintype "output"))
    )
    (net (code "751") (name "Net-(IC40-OUT7)") (class "Default")
      (node (ref "D579") (pin "C") (pinfunction "C_C") (pintype "passive"))
      (node (ref "IC40") (pin "12") (pinfunction "OUT7_12") (pintype "output"))
    )
    (net (code "752") (name "Net-(IC40-OUT8)") (class "Default")
      (node (ref "D643") (pin "C") (pinfunction "C_C") (pintype "passive"))
      (node (ref "IC40") (pin "13") (pinfunction "OUT8_13") (pintype "output"))
    )
    (net (code "753") (name "Net-(IC40-OUT9)") (class "Default")
      (node (ref "D642") (pin "C") (pinfunction "C_C") (pintype "passive"))
      (node (ref "IC40") (pin "14") (pinfunction "OUT9_14") (pintype "output"))
    )
    (net (code "754") (name "Net-(IC40-OUT10)") (class "Default")
      (node (ref "D641") (pin "C") (pinfunction "C_C") (pintype "passive"))
      (node (ref "IC40") (pin "15") (pinfunction "OUT10_15") (pintype "output"))
    )
    (net (code "755") (name "Net-(IC40-OUT11)") (class "Default")
      (node (ref "D640") (pin "C") (pinfunction "C_C") (pintype "passive"))
      (node (ref "IC40") (pin "16") (pinfunction "OUT11_16") (pintype "output"))
    )
    (net (code "756") (name "Net-(IC40-OUT12)") (class "Default")
      (node (ref "D639") (pin "C") (pinfunction "C_C") (pintype "passive"))
      (node (ref "IC40") (pin "17") (pinfunction "OUT12_17") (pintype "output"))
    )
    (net (code "757") (name "Net-(IC40-OUT13)") (class "Default")
      (node (ref "D638") (pin "C") (pinfunction "C_C") (pintype "passive"))
      (node (ref "IC40") (pin "18") (pinfunction "OUT13_18") (pintype "output"))
    )
    (net (code "758") (name "Net-(IC40-OUT14)") (class "Default")
      (node (ref "D637") (pin "C") (pinfunction "C_C") (pintype "passive"))
      (node (ref "IC40") (pin "19") (pinfunction "OUT14_19") (pintype "output"))
    )
    (net (code "759") (name "Net-(IC40-OUT15)") (class "Default")
      (node (ref "D636") (pin "C") (pinfunction "C_C") (pintype "passive"))
      (node (ref "IC40") (pin "20") (pinfunction "OUT15_20") (pintype "output"))
    )
    (net (code "760") (name "Net-(IC41-IREF)") (class "Default")
      (node (ref "IC41") (pin "23") (pinfunction "IREF_23") (pintype "bidirectional"))
      (node (ref "R52") (pin "1") (pinfunction "1_1") (pintype "passive"))
    )
    (net (code "761") (name "Net-(IC41-OUT0)") (class "Default")
      (node (ref "D644") (pin "C") (pinfunction "C_C") (pintype "passive"))
      (node (ref "IC41") (pin "5") (pinfunction "OUT0_5") (pintype "output"))
    )
    (net (code "762") (name "Net-(IC41-OUT1)") (class "Default")
      (node (ref "D645") (pin "C") (pinfunction "C_C") (pintype "passive"))
      (node (ref "IC41") (pin "6") (pinfunction "OUT1_6") (pintype "output"))
    )
    (net (code "763") (name "Net-(IC41-OUT2)") (class "Default")
      (node (ref "D646") (pin "C") (pinfunction "C_C") (pintype "passive"))
      (node (ref "IC41") (pin "7") (pinfunction "OUT2_7") (pintype "output"))
    )
    (net (code "764") (name "Net-(IC41-OUT3)") (class "Default")
      (node (ref "D647") (pin "C") (pinfunction "C_C") (pintype "passive"))
      (node (ref "IC41") (pin "8") (pinfunction "OUT3_8") (pintype "output"))
    )
    (net (code "765") (name "Net-(IC41-OUT4)") (class "Default")
      (node (ref "D648") (pin "C") (pinfunction "C_C") (pintype "passive"))
      (node (ref "IC41") (pin "9") (pinfunction "OUT4_9") (pintype "output"))
    )
    (net (code "766") (name "Net-(IC41-OUT5)") (class "Default")
      (node (ref "D649") (pin "C") (pinfunction "C_C") (pintype "passive"))
      (node (ref "IC41") (pin "10") (pinfunction "OUT5_10") (pintype "output"))
    )
    (net (code "767") (name "Net-(IC41-OUT6)") (class "Default")
      (node (ref "D650") (pin "C") (pinfunction "C_C") (pintype "passive"))
      (node (ref "IC41") (pin "11") (pinfunction "OUT6_11") (pintype "output"))
    )
    (net (code "768") (name "Net-(IC41-OUT7)") (class "Default")
      (node (ref "D651") (pin "C") (pinfunction "C_C") (pintype "passive"))
      (node (ref "IC41") (pin "12") (pinfunction "OUT7_12") (pintype "output"))
    )
    (net (code "769") (name "Net-(IC41-OUT8)") (class "Default")
      (node (ref "D715") (pin "C") (pinfunction "C_C") (pintype "passive"))
      (node (ref "IC41") (pin "13") (pinfunction "OUT8_13") (pintype "output"))
    )
    (net (code "770") (name "Net-(IC41-OUT9)") (class "Default")
      (node (ref "D714") (pin "C") (pinfunction "C_C") (pintype "passive"))
      (node (ref "IC41") (pin "14") (pinfunction "OUT9_14") (pintype "output"))
    )
    (net (code "771") (name "Net-(IC41-OUT10)") (class "Default")
      (node (ref "D713") (pin "C") (pinfunction "C_C") (pintype "passive"))
      (node (ref "IC41") (pin "15") (pinfunction "OUT10_15") (pintype "output"))
    )
    (net (code "772") (name "Net-(IC41-OUT11)") (class "Default")
      (node (ref "D712") (pin "C") (pinfunction "C_C") (pintype "passive"))
      (node (ref "IC41") (pin "16") (pinfunction "OUT11_16") (pintype "output"))
    )
    (net (code "773") (name "Net-(IC41-OUT12)") (class "Default")
      (node (ref "D711") (pin "C") (pinfunction "C_C") (pintype "passive"))
      (node (ref "IC41") (pin "17") (pinfunction "OUT12_17") (pintype "output"))
    )
    (net (code "774") (name "Net-(IC41-OUT13)") (class "Default")
      (node (ref "D710") (pin "C") (pinfunction "C_C") (pintype "passive"))
      (node (ref "IC41") (pin "18") (pinfunction "OUT13_18") (pintype "output"))
    )
    (net (code "775") (name "Net-(IC41-OUT14)") (class "Default")
      (node (ref "D709") (pin "C") (pinfunction "C_C") (pintype "passive"))
      (node (ref "IC41") (pin "19") (pinfunction "OUT14_19") (pintype "output"))
    )
    (net (code "776") (name "Net-(IC41-OUT15)") (class "Default")
      (node (ref "D708") (pin "C") (pinfunction "C_C") (pintype "passive"))
      (node (ref "IC41") (pin "20") (pinfunction "OUT15_20") (pintype "output"))
    )
    (net (code "777") (name "Net-(IC42-IREF)") (class "Default")
      (node (ref "IC42") (pin "23") (pinfunction "IREF_23") (pintype "bidirectional"))
      (node (ref "R53") (pin "1") (pinfunction "1_1") (pintype "passive"))
    )
    (net (code "778") (name "Net-(IC42-OUT0)") (class "Default")
      (node (ref "D652") (pin "C") (pinfunction "C_C") (pintype "passive"))
      (node (ref "IC42") (pin "5") (pinfunction "OUT0_5") (pintype "output"))
    )
    (net (code "779") (name "Net-(IC42-OUT1)") (class "Default")
      (node (ref "D653") (pin "C") (pinfunction "C_C") (pintype "passive"))
      (node (ref "IC42") (pin "6") (pinfunction "OUT1_6") (pintype "output"))
    )
    (net (code "780") (name "Net-(IC42-OUT2)") (class "Default")
      (node (ref "D654") (pin "C") (pinfunction "C_C") (pintype "passive"))
      (node (ref "IC42") (pin "7") (pinfunction "OUT2_7") (pintype "output"))
    )
    (net (code "781") (name "Net-(IC42-OUT3)") (class "Default")
      (node (ref "D655") (pin "C") (pinfunction "C_C") (pintype "passive"))
      (node (ref "IC42") (pin "8") (pinfunction "OUT3_8") (pintype "output"))
    )
    (net (code "782") (name "Net-(IC42-OUT4)") (class "Default")
      (node (ref "D656") (pin "C") (pinfunction "C_C") (pintype "passive"))
      (node (ref "IC42") (pin "9") (pinfunction "OUT4_9") (pintype "output"))
    )
    (net (code "783") (name "Net-(IC42-OUT5)") (class "Default")
      (node (ref "D657") (pin "C") (pinfunction "C_C") (pintype "passive"))
      (node (ref "IC42") (pin "10") (pinfunction "OUT5_10") (pintype "output"))
    )
    (net (code "784") (name "Net-(IC42-OUT6)") (class "Default")
      (node (ref "D658") (pin "C") (pinfunction "C_C") (pintype "passive"))
      (node (ref "IC42") (pin "11") (pinfunction "OUT6_11") (pintype "output"))
    )
    (net (code "785") (name "Net-(IC42-OUT7)") (class "Default")
      (node (ref "D659") (pin "C") (pinfunction "C_C") (pintype "passive"))
      (node (ref "IC42") (pin "12") (pinfunction "OUT7_12") (pintype "output"))
    )
    (net (code "786") (name "Net-(IC42-OUT8)") (class "Default")
      (node (ref "D723") (pin "C") (pinfunction "C_C") (pintype "passive"))
      (node (ref "IC42") (pin "13") (pinfunction "OUT8_13") (pintype "output"))
    )
    (net (code "787") (name "Net-(IC42-OUT9)") (class "Default")
      (node (ref "D722") (pin "C") (pinfunction "C_C") (pintype "passive"))
      (node (ref "IC42") (pin "14") (pinfunction "OUT9_14") (pintype "output"))
    )
    (net (code "788") (name "Net-(IC42-OUT10)") (class "Default")
      (node (ref "D721") (pin "C") (pinfunction "C_C") (pintype "passive"))
      (node (ref "IC42") (pin "15") (pinfunction "OUT10_15") (pintype "output"))
    )
    (net (code "789") (name "Net-(IC42-OUT11)") (class "Default")
      (node (ref "D720") (pin "C") (pinfunction "C_C") (pintype "passive"))
      (node (ref "IC42") (pin "16") (pinfunction "OUT11_16") (pintype "output"))
    )
    (net (code "790") (name "Net-(IC42-OUT12)") (class "Default")
      (node (ref "D719") (pin "C") (pinfunction "C_C") (pintype "passive"))
      (node (ref "IC42") (pin "17") (pinfunction "OUT12_17") (pintype "output"))
    )
    (net (code "791") (name "Net-(IC42-OUT13)") (class "Default")
      (node (ref "D718") (pin "C") (pinfunction "C_C") (pintype "passive"))
      (node (ref "IC42") (pin "18") (pinfunction "OUT13_18") (pintype "output"))
    )
    (net (code "792") (name "Net-(IC42-OUT14)") (class "Default")
      (node (ref "D717") (pin "C") (pinfunction "C_C") (pintype "passive"))
      (node (ref "IC42") (pin "19") (pinfunction "OUT14_19") (pintype "output"))
    )
    (net (code "793") (name "Net-(IC42-OUT15)") (class "Default")
      (node (ref "D716") (pin "C") (pinfunction "C_C") (pintype "passive"))
      (node (ref "IC42") (pin "20") (pinfunction "OUT15_20") (pintype "output"))
    )
    (net (code "794") (name "Net-(IC43-IREF)") (class "Default")
      (node (ref "IC43") (pin "23") (pinfunction "IREF_23") (pintype "bidirectional"))
      (node (ref "R54") (pin "1") (pinfunction "1_1") (pintype "passive"))
    )
    (net (code "795") (name "Net-(IC43-OUT0)") (class "Default")
      (node (ref "D660") (pin "C") (pinfunction "C_C") (pintype "passive"))
      (node (ref "IC43") (pin "5") (pinfunction "OUT0_5") (pintype "output"))
    )
    (net (code "796") (name "Net-(IC43-OUT1)") (class "Default")
      (node (ref "D661") (pin "C") (pinfunction "C_C") (pintype "passive"))
      (node (ref "IC43") (pin "6") (pinfunction "OUT1_6") (pintype "output"))
    )
    (net (code "797") (name "Net-(IC43-OUT2)") (class "Default")
      (node (ref "D662") (pin "C") (pinfunction "C_C") (pintype "passive"))
      (node (ref "IC43") (pin "7") (pinfunction "OUT2_7") (pintype "output"))
    )
    (net (code "798") (name "Net-(IC43-OUT3)") (class "Default")
      (node (ref "D663") (pin "C") (pinfunction "C_C") (pintype "passive"))
      (node (ref "IC43") (pin "8") (pinfunction "OUT3_8") (pintype "output"))
    )
    (net (code "799") (name "Net-(IC43-OUT4)") (class "Default")
      (node (ref "D664") (pin "C") (pinfunction "C_C") (pintype "passive"))
      (node (ref "IC43") (pin "9") (pinfunction "OUT4_9") (pintype "output"))
    )
    (net (code "800") (name "Net-(IC43-OUT5)") (class "Default")
      (node (ref "D665") (pin "C") (pinfunction "C_C") (pintype "passive"))
      (node (ref "IC43") (pin "10") (pinfunction "OUT5_10") (pintype "output"))
    )
    (net (code "801") (name "Net-(IC43-OUT6)") (class "Default")
      (node (ref "D666") (pin "C") (pinfunction "C_C") (pintype "passive"))
      (node (ref "IC43") (pin "11") (pinfunction "OUT6_11") (pintype "output"))
    )
    (net (code "802") (name "Net-(IC43-OUT7)") (class "Default")
      (node (ref "D667") (pin "C") (pinfunction "C_C") (pintype "passive"))
      (node (ref "IC43") (pin "12") (pinfunction "OUT7_12") (pintype "output"))
    )
    (net (code "803") (name "Net-(IC43-OUT8)") (class "Default")
      (node (ref "D731") (pin "C") (pinfunction "C_C") (pintype "passive"))
      (node (ref "IC43") (pin "13") (pinfunction "OUT8_13") (pintype "output"))
    )
    (net (code "804") (name "Net-(IC43-OUT9)") (class "Default")
      (node (ref "D730") (pin "C") (pinfunction "C_C") (pintype "passive"))
      (node (ref "IC43") (pin "14") (pinfunction "OUT9_14") (pintype "output"))
    )
    (net (code "805") (name "Net-(IC43-OUT10)") (class "Default")
      (node (ref "D729") (pin "C") (pinfunction "C_C") (pintype "passive"))
      (node (ref "IC43") (pin "15") (pinfunction "OUT10_15") (pintype "output"))
    )
    (net (code "806") (name "Net-(IC43-OUT11)") (class "Default")
      (node (ref "D728") (pin "C") (pinfunction "C_C") (pintype "passive"))
      (node (ref "IC43") (pin "16") (pinfunction "OUT11_16") (pintype "output"))
    )
    (net (code "807") (name "Net-(IC43-OUT12)") (class "Default")
      (node (ref "D727") (pin "C") (pinfunction "C_C") (pintype "passive"))
      (node (ref "IC43") (pin "17") (pinfunction "OUT12_17") (pintype "output"))
    )
    (net (code "808") (name "Net-(IC43-OUT13)") (class "Default")
      (node (ref "D726") (pin "C") (pinfunction "C_C") (pintype "passive"))
      (node (ref "IC43") (pin "18") (pinfunction "OUT13_18") (pintype "output"))
    )
    (net (code "809") (name "Net-(IC43-OUT14)") (class "Default")
      (node (ref "D725") (pin "C") (pinfunction "C_C") (pintype "passive"))
      (node (ref "IC43") (pin "19") (pinfunction "OUT14_19") (pintype "output"))
    )
    (net (code "810") (name "Net-(IC43-OUT15)") (class "Default")
      (node (ref "D724") (pin "C") (pinfunction "C_C") (pintype "passive"))
      (node (ref "IC43") (pin "20") (pinfunction "OUT15_20") (pintype "output"))
    )
    (net (code "811") (name "Net-(IC44-IREF)") (class "Default")
      (node (ref "IC44") (pin "23") (pinfunction "IREF_23") (pintype "bidirectional"))
      (node (ref "R55") (pin "1") (pinfunction "1_1") (pintype "passive"))
    )
    (net (code "812") (name "Net-(IC44-OUT0)") (class "Default")
      (node (ref "D668") (pin "C") (pinfunction "C_C") (pintype "passive"))
      (node (ref "IC44") (pin "5") (pinfunction "OUT0_5") (pintype "output"))
    )
    (net (code "813") (name "Net-(IC44-OUT1)") (class "Default")
      (node (ref "D669") (pin "C") (pinfunction "C_C") (pintype "passive"))
      (node (ref "IC44") (pin "6") (pinfunction "OUT1_6") (pintype "output"))
    )
    (net (code "814") (name "Net-(IC44-OUT2)") (class "Default")
      (node (ref "D670") (pin "C") (pinfunction "C_C") (pintype "passive"))
      (node (ref "IC44") (pin "7") (pinfunction "OUT2_7") (pintype "output"))
    )
    (net (code "815") (name "Net-(IC44-OUT3)") (class "Default")
      (node (ref "D671") (pin "C") (pinfunction "C_C") (pintype "passive"))
      (node (ref "IC44") (pin "8") (pinfunction "OUT3_8") (pintype "output"))
    )
    (net (code "816") (name "Net-(IC44-OUT4)") (class "Default")
      (node (ref "D672") (pin "C") (pinfunction "C_C") (pintype "passive"))
      (node (ref "IC44") (pin "9") (pinfunction "OUT4_9") (pintype "output"))
    )
    (net (code "817") (name "Net-(IC44-OUT5)") (class "Default")
      (node (ref "D673") (pin "C") (pinfunction "C_C") (pintype "passive"))
      (node (ref "IC44") (pin "10") (pinfunction "OUT5_10") (pintype "output"))
    )
    (net (code "818") (name "Net-(IC44-OUT6)") (class "Default")
      (node (ref "D674") (pin "C") (pinfunction "C_C") (pintype "passive"))
      (node (ref "IC44") (pin "11") (pinfunction "OUT6_11") (pintype "output"))
    )
    (net (code "819") (name "Net-(IC44-OUT7)") (class "Default")
      (node (ref "D675") (pin "C") (pinfunction "C_C") (pintype "passive"))
      (node (ref "IC44") (pin "12") (pinfunction "OUT7_12") (pintype "output"))
    )
    (net (code "820") (name "Net-(IC44-OUT8)") (class "Default")
      (node (ref "D739") (pin "C") (pinfunction "C_C") (pintype "passive"))
      (node (ref "IC44") (pin "13") (pinfunction "OUT8_13") (pintype "output"))
    )
    (net (code "821") (name "Net-(IC44-OUT9)") (class "Default")
      (node (ref "D738") (pin "C") (pinfunction "C_C") (pintype "passive"))
      (node (ref "IC44") (pin "14") (pinfunction "OUT9_14") (pintype "output"))
    )
    (net (code "822") (name "Net-(IC44-OUT10)") (class "Default")
      (node (ref "D737") (pin "C") (pinfunction "C_C") (pintype "passive"))
      (node (ref "IC44") (pin "15") (pinfunction "OUT10_15") (pintype "output"))
    )
    (net (code "823") (name "Net-(IC44-OUT11)") (class "Default")
      (node (ref "D736") (pin "C") (pinfunction "C_C") (pintype "passive"))
      (node (ref "IC44") (pin "16") (pinfunction "OUT11_16") (pintype "output"))
    )
    (net (code "824") (name "Net-(IC44-OUT12)") (class "Default")
      (node (ref "D735") (pin "C") (pinfunction "C_C") (pintype "passive"))
      (node (ref "IC44") (pin "17") (pinfunction "OUT12_17") (pintype "output"))
    )
    (net (code "825") (name "Net-(IC44-OUT13)") (class "Default")
      (node (ref "D734") (pin "C") (pinfunction "C_C") (pintype "passive"))
      (node (ref "IC44") (pin "18") (pinfunction "OUT13_18") (pintype "output"))
    )
    (net (code "826") (name "Net-(IC44-OUT14)") (class "Default")
      (node (ref "D733") (pin "C") (pinfunction "C_C") (pintype "passive"))
      (node (ref "IC44") (pin "19") (pinfunction "OUT14_19") (pintype "output"))
    )
    (net (code "827") (name "Net-(IC44-OUT15)") (class "Default")
      (node (ref "D732") (pin "C") (pinfunction "C_C") (pintype "passive"))
      (node (ref "IC44") (pin "20") (pinfunction "OUT15_20") (pintype "output"))
    )
    (net (code "828") (name "Net-(IC45-IREF)") (class "Default")
      (node (ref "IC45") (pin "23") (pinfunction "IREF_23") (pintype "bidirectional"))
      (node (ref "R56") (pin "1") (pinfunction "1_1") (pintype "passive"))
    )
    (net (code "829") (name "Net-(IC45-OUT0)") (class "Default")
      (node (ref "D676") (pin "C") (pinfunction "C_C") (pintype "passive"))
      (node (ref "IC45") (pin "5") (pinfunction "OUT0_5") (pintype "output"))
    )
    (net (code "830") (name "Net-(IC45-OUT1)") (class "Default")
      (node (ref "D677") (pin "C") (pinfunction "C_C") (pintype "passive"))
      (node (ref "IC45") (pin "6") (pinfunction "OUT1_6") (pintype "output"))
    )
    (net (code "831") (name "Net-(IC45-OUT2)") (class "Default")
      (node (ref "D678") (pin "C") (pinfunction "C_C") (pintype "passive"))
      (node (ref "IC45") (pin "7") (pinfunction "OUT2_7") (pintype "output"))
    )
    (net (code "832") (name "Net-(IC45-OUT3)") (class "Default")
      (node (ref "D679") (pin "C") (pinfunction "C_C") (pintype "passive"))
      (node (ref "IC45") (pin "8") (pinfunction "OUT3_8") (pintype "output"))
    )
    (net (code "833") (name "Net-(IC45-OUT4)") (class "Default")
      (node (ref "D680") (pin "C") (pinfunction "C_C") (pintype "passive"))
      (node (ref "IC45") (pin "9") (pinfunction "OUT4_9") (pintype "output"))
    )
    (net (code "834") (name "Net-(IC45-OUT5)") (class "Default")
      (node (ref "D681") (pin "C") (pinfunction "C_C") (pintype "passive"))
      (node (ref "IC45") (pin "10") (pinfunction "OUT5_10") (pintype "output"))
    )
    (net (code "835") (name "Net-(IC45-OUT6)") (class "Default")
      (node (ref "D682") (pin "C") (pinfunction "C_C") (pintype "passive"))
      (node (ref "IC45") (pin "11") (pinfunction "OUT6_11") (pintype "output"))
    )
    (net (code "836") (name "Net-(IC45-OUT7)") (class "Default")
      (node (ref "D683") (pin "C") (pinfunction "C_C") (pintype "passive"))
      (node (ref "IC45") (pin "12") (pinfunction "OUT7_12") (pintype "output"))
    )
    (net (code "837") (name "Net-(IC45-OUT8)") (class "Default")
      (node (ref "D747") (pin "C") (pinfunction "C_C") (pintype "passive"))
      (node (ref "IC45") (pin "13") (pinfunction "OUT8_13") (pintype "output"))
    )
    (net (code "838") (name "Net-(IC45-OUT9)") (class "Default")
      (node (ref "D746") (pin "C") (pinfunction "C_C") (pintype "passive"))
      (node (ref "IC45") (pin "14") (pinfunction "OUT9_14") (pintype "output"))
    )
    (net (code "839") (name "Net-(IC45-OUT10)") (class "Default")
      (node (ref "D745") (pin "C") (pinfunction "C_C") (pintype "passive"))
      (node (ref "IC45") (pin "15") (pinfunction "OUT10_15") (pintype "output"))
    )
    (net (code "840") (name "Net-(IC45-OUT11)") (class "Default")
      (node (ref "D744") (pin "C") (pinfunction "C_C") (pintype "passive"))
      (node (ref "IC45") (pin "16") (pinfunction "OUT11_16") (pintype "output"))
    )
    (net (code "841") (name "Net-(IC45-OUT12)") (class "Default")
      (node (ref "D743") (pin "C") (pinfunction "C_C") (pintype "passive"))
      (node (ref "IC45") (pin "17") (pinfunction "OUT12_17") (pintype "output"))
    )
    (net (code "842") (name "Net-(IC45-OUT13)") (class "Default")
      (node (ref "D742") (pin "C") (pinfunction "C_C") (pintype "passive"))
      (node (ref "IC45") (pin "18") (pinfunction "OUT13_18") (pintype "output"))
    )
    (net (code "843") (name "Net-(IC45-OUT14)") (class "Default")
      (node (ref "D741") (pin "C") (pinfunction "C_C") (pintype "passive"))
      (node (ref "IC45") (pin "19") (pinfunction "OUT14_19") (pintype "output"))
    )
    (net (code "844") (name "Net-(IC45-OUT15)") (class "Default")
      (node (ref "D740") (pin "C") (pinfunction "C_C") (pintype "passive"))
      (node (ref "IC45") (pin "20") (pinfunction "OUT15_20") (pintype "output"))
    )
    (net (code "845") (name "Net-(IC46-IREF)") (class "Default")
      (node (ref "IC46") (pin "23") (pinfunction "IREF_23") (pintype "bidirectional"))
      (node (ref "R57") (pin "1") (pinfunction "1_1") (pintype "passive"))
    )
    (net (code "846") (name "Net-(IC46-OUT0)") (class "Default")
      (node (ref "D684") (pin "C") (pinfunction "C_C") (pintype "passive"))
      (node (ref "IC46") (pin "5") (pinfunction "OUT0_5") (pintype "output"))
    )
    (net (code "847") (name "Net-(IC46-OUT1)") (class "Default")
      (node (ref "D685") (pin "C") (pinfunction "C_C") (pintype "passive"))
      (node (ref "IC46") (pin "6") (pinfunction "OUT1_6") (pintype "output"))
    )
    (net (code "848") (name "Net-(IC46-OUT2)") (class "Default")
      (node (ref "D686") (pin "C") (pinfunction "C_C") (pintype "passive"))
      (node (ref "IC46") (pin "7") (pinfunction "OUT2_7") (pintype "output"))
    )
    (net (code "849") (name "Net-(IC46-OUT3)") (class "Default")
      (node (ref "D687") (pin "C") (pinfunction "C_C") (pintype "passive"))
      (node (ref "IC46") (pin "8") (pinfunction "OUT3_8") (pintype "output"))
    )
    (net (code "850") (name "Net-(IC46-OUT4)") (class "Default")
      (node (ref "D688") (pin "C") (pinfunction "C_C") (pintype "passive"))
      (node (ref "IC46") (pin "9") (pinfunction "OUT4_9") (pintype "output"))
    )
    (net (code "851") (name "Net-(IC46-OUT5)") (class "Default")
      (node (ref "D689") (pin "C") (pinfunction "C_C") (pintype "passive"))
      (node (ref "IC46") (pin "10") (pinfunction "OUT5_10") (pintype "output"))
    )
    (net (code "852") (name "Net-(IC46-OUT6)") (class "Default")
      (node (ref "D690") (pin "C") (pinfunction "C_C") (pintype "passive"))
      (node (ref "IC46") (pin "11") (pinfunction "OUT6_11") (pintype "output"))
    )
    (net (code "853") (name "Net-(IC46-OUT7)") (class "Default")
      (node (ref "D691") (pin "C") (pinfunction "C_C") (pintype "passive"))
      (node (ref "IC46") (pin "12") (pinfunction "OUT7_12") (pintype "output"))
    )
    (net (code "854") (name "Net-(IC46-OUT8)") (class "Default")
      (node (ref "D755") (pin "C") (pinfunction "C_C") (pintype "passive"))
      (node (ref "IC46") (pin "13") (pinfunction "OUT8_13") (pintype "output"))
    )
    (net (code "855") (name "Net-(IC46-OUT9)") (class "Default")
      (node (ref "D754") (pin "C") (pinfunction "C_C") (pintype "passive"))
      (node (ref "IC46") (pin "14") (pinfunction "OUT9_14") (pintype "output"))
    )
    (net (code "856") (name "Net-(IC46-OUT10)") (class "Default")
      (node (ref "D753") (pin "C") (pinfunction "C_C") (pintype "passive"))
      (node (ref "IC46") (pin "15") (pinfunction "OUT10_15") (pintype "output"))
    )
    (net (code "857") (name "Net-(IC46-OUT11)") (class "Default")
      (node (ref "D752") (pin "C") (pinfunction "C_C") (pintype "passive"))
      (node (ref "IC46") (pin "16") (pinfunction "OUT11_16") (pintype "output"))
    )
    (net (code "858") (name "Net-(IC46-OUT12)") (class "Default")
      (node (ref "D751") (pin "C") (pinfunction "C_C") (pintype "passive"))
      (node (ref "IC46") (pin "17") (pinfunction "OUT12_17") (pintype "output"))
    )
    (net (code "859") (name "Net-(IC46-OUT13)") (class "Default")
      (node (ref "D750") (pin "C") (pinfunction "C_C") (pintype "passive"))
      (node (ref "IC46") (pin "18") (pinfunction "OUT13_18") (pintype "output"))
    )
    (net (code "860") (name "Net-(IC46-OUT14)") (class "Default")
      (node (ref "D749") (pin "C") (pinfunction "C_C") (pintype "passive"))
      (node (ref "IC46") (pin "19") (pinfunction "OUT14_19") (pintype "output"))
    )
    (net (code "861") (name "Net-(IC46-OUT15)") (class "Default")
      (node (ref "D748") (pin "C") (pinfunction "C_C") (pintype "passive"))
      (node (ref "IC46") (pin "20") (pinfunction "OUT15_20") (pintype "output"))
    )
    (net (code "862") (name "Net-(IC47-IREF)") (class "Default")
      (node (ref "IC47") (pin "23") (pinfunction "IREF_23") (pintype "bidirectional"))
      (node (ref "R58") (pin "1") (pinfunction "1_1") (pintype "passive"))
    )
    (net (code "863") (name "Net-(IC47-OUT0)") (class "Default")
      (node (ref "D692") (pin "C") (pinfunction "C_C") (pintype "passive"))
      (node (ref "IC47") (pin "5") (pinfunction "OUT0_5") (pintype "output"))
    )
    (net (code "864") (name "Net-(IC47-OUT1)") (class "Default")
      (node (ref "D693") (pin "C") (pinfunction "C_C") (pintype "passive"))
      (node (ref "IC47") (pin "6") (pinfunction "OUT1_6") (pintype "output"))
    )
    (net (code "865") (name "Net-(IC47-OUT2)") (class "Default")
      (node (ref "D694") (pin "C") (pinfunction "C_C") (pintype "passive"))
      (node (ref "IC47") (pin "7") (pinfunction "OUT2_7") (pintype "output"))
    )
    (net (code "866") (name "Net-(IC47-OUT3)") (class "Default")
      (node (ref "D695") (pin "C") (pinfunction "C_C") (pintype "passive"))
      (node (ref "IC47") (pin "8") (pinfunction "OUT3_8") (pintype "output"))
    )
    (net (code "867") (name "Net-(IC47-OUT4)") (class "Default")
      (node (ref "D696") (pin "C") (pinfunction "C_C") (pintype "passive"))
      (node (ref "IC47") (pin "9") (pinfunction "OUT4_9") (pintype "output"))
    )
    (net (code "868") (name "Net-(IC47-OUT5)") (class "Default")
      (node (ref "D697") (pin "C") (pinfunction "C_C") (pintype "passive"))
      (node (ref "IC47") (pin "10") (pinfunction "OUT5_10") (pintype "output"))
    )
    (net (code "869") (name "Net-(IC47-OUT6)") (class "Default")
      (node (ref "D698") (pin "C") (pinfunction "C_C") (pintype "passive"))
      (node (ref "IC47") (pin "11") (pinfunction "OUT6_11") (pintype "output"))
    )
    (net (code "870") (name "Net-(IC47-OUT7)") (class "Default")
      (node (ref "D699") (pin "C") (pinfunction "C_C") (pintype "passive"))
      (node (ref "IC47") (pin "12") (pinfunction "OUT7_12") (pintype "output"))
    )
    (net (code "871") (name "Net-(IC47-OUT8)") (class "Default")
      (node (ref "D763") (pin "C") (pinfunction "C_C") (pintype "passive"))
      (node (ref "IC47") (pin "13") (pinfunction "OUT8_13") (pintype "output"))
    )
    (net (code "872") (name "Net-(IC47-OUT9)") (class "Default")
      (node (ref "D762") (pin "C") (pinfunction "C_C") (pintype "passive"))
      (node (ref "IC47") (pin "14") (pinfunction "OUT9_14") (pintype "output"))
    )
    (net (code "873") (name "Net-(IC47-OUT10)") (class "Default")
      (node (ref "D761") (pin "C") (pinfunction "C_C") (pintype "passive"))
      (node (ref "IC47") (pin "15") (pinfunction "OUT10_15") (pintype "output"))
    )
    (net (code "874") (name "Net-(IC47-OUT11)") (class "Default")
      (node (ref "D760") (pin "C") (pinfunction "C_C") (pintype "passive"))
      (node (ref "IC47") (pin "16") (pinfunction "OUT11_16") (pintype "output"))
    )
    (net (code "875") (name "Net-(IC47-OUT12)") (class "Default")
      (node (ref "D759") (pin "C") (pinfunction "C_C") (pintype "passive"))
      (node (ref "IC47") (pin "17") (pinfunction "OUT12_17") (pintype "output"))
    )
    (net (code "876") (name "Net-(IC47-OUT13)") (class "Default")
      (node (ref "D758") (pin "C") (pinfunction "C_C") (pintype "passive"))
      (node (ref "IC47") (pin "18") (pinfunction "OUT13_18") (pintype "output"))
    )
    (net (code "877") (name "Net-(IC47-OUT14)") (class "Default")
      (node (ref "D757") (pin "C") (pinfunction "C_C") (pintype "passive"))
      (node (ref "IC47") (pin "19") (pinfunction "OUT14_19") (pintype "output"))
    )
    (net (code "878") (name "Net-(IC47-OUT15)") (class "Default")
      (node (ref "D756") (pin "C") (pinfunction "C_C") (pintype "passive"))
      (node (ref "IC47") (pin "20") (pinfunction "OUT15_20") (pintype "output"))
    )
    (net (code "879") (name "Net-(IC48-IREF)") (class "Default")
      (node (ref "IC48") (pin "23") (pinfunction "IREF_23") (pintype "bidirectional"))
      (node (ref "R59") (pin "1") (pinfunction "1_1") (pintype "passive"))
    )
    (net (code "880") (name "Net-(IC48-OUT0)") (class "Default")
      (node (ref "D700") (pin "C") (pinfunction "C_C") (pintype "passive"))
      (node (ref "IC48") (pin "5") (pinfunction "OUT0_5") (pintype "output"))
    )
    (net (code "881") (name "Net-(IC48-OUT1)") (class "Default")
      (node (ref "D701") (pin "C") (pinfunction "C_C") (pintype "passive"))
      (node (ref "IC48") (pin "6") (pinfunction "OUT1_6") (pintype "output"))
    )
    (net (code "882") (name "Net-(IC48-OUT2)") (class "Default")
      (node (ref "D702") (pin "C") (pinfunction "C_C") (pintype "passive"))
      (node (ref "IC48") (pin "7") (pinfunction "OUT2_7") (pintype "output"))
    )
    (net (code "883") (name "Net-(IC48-OUT3)") (class "Default")
      (node (ref "D703") (pin "C") (pinfunction "C_C") (pintype "passive"))
      (node (ref "IC48") (pin "8") (pinfunction "OUT3_8") (pintype "output"))
    )
    (net (code "884") (name "Net-(IC48-OUT4)") (class "Default")
      (node (ref "D704") (pin "C") (pinfunction "C_C") (pintype "passive"))
      (node (ref "IC48") (pin "9") (pinfunction "OUT4_9") (pintype "output"))
    )
    (net (code "885") (name "Net-(IC48-OUT5)") (class "Default")
      (node (ref "D705") (pin "C") (pinfunction "C_C") (pintype "passive"))
      (node (ref "IC48") (pin "10") (pinfunction "OUT5_10") (pintype "output"))
    )
    (net (code "886") (name "Net-(IC48-OUT6)") (class "Default")
      (node (ref "D706") (pin "C") (pinfunction "C_C") (pintype "passive"))
      (node (ref "IC48") (pin "11") (pinfunction "OUT6_11") (pintype "output"))
    )
    (net (code "887") (name "Net-(IC48-OUT7)") (class "Default")
      (node (ref "D707") (pin "C") (pinfunction "C_C") (pintype "passive"))
      (node (ref "IC48") (pin "12") (pinfunction "OUT7_12") (pintype "output"))
    )
    (net (code "888") (name "Net-(IC48-OUT8)") (class "Default")
      (node (ref "D771") (pin "C") (pinfunction "C_C") (pintype "passive"))
      (node (ref "IC48") (pin "13") (pinfunction "OUT8_13") (pintype "output"))
    )
    (net (code "889") (name "Net-(IC48-OUT9)") (class "Default")
      (node (ref "D770") (pin "C") (pinfunction "C_C") (pintype "passive"))
      (node (ref "IC48") (pin "14") (pinfunction "OUT9_14") (pintype "output"))
    )
    (net (code "890") (name "Net-(IC48-OUT10)") (class "Default")
      (node (ref "D769") (pin "C") (pinfunction "C_C") (pintype "passive"))
      (node (ref "IC48") (pin "15") (pinfunction "OUT10_15") (pintype "output"))
    )
    (net (code "891") (name "Net-(IC48-OUT11)") (class "Default")
      (node (ref "D768") (pin "C") (pinfunction "C_C") (pintype "passive"))
      (node (ref "IC48") (pin "16") (pinfunction "OUT11_16") (pintype "output"))
    )
    (net (code "892") (name "Net-(IC48-OUT12)") (class "Default")
      (node (ref "D767") (pin "C") (pinfunction "C_C") (pintype "passive"))
      (node (ref "IC48") (pin "17") (pinfunction "OUT12_17") (pintype "output"))
    )
    (net (code "893") (name "Net-(IC48-OUT13)") (class "Default")
      (node (ref "D766") (pin "C") (pinfunction "C_C") (pintype "passive"))
      (node (ref "IC48") (pin "18") (pinfunction "OUT13_18") (pintype "output"))
    )
    (net (code "894") (name "Net-(IC48-OUT14)") (class "Default")
      (node (ref "D765") (pin "C") (pinfunction "C_C") (pintype "passive"))
      (node (ref "IC48") (pin "19") (pinfunction "OUT14_19") (pintype "output"))
    )
    (net (code "895") (name "Net-(IC48-OUT15)") (class "Default")
      (node (ref "D764") (pin "C") (pinfunction "C_C") (pintype "passive"))
      (node (ref "IC48") (pin "20") (pinfunction "OUT15_20") (pintype "output"))
    )
    (net (code "896") (name "Net-(IC49-IREF)") (class "Default")
      (node (ref "IC49") (pin "23") (pinfunction "IREF_23") (pintype "bidirectional"))
      (node (ref "R60") (pin "1") (pinfunction "1_1") (pintype "passive"))
    )
    (net (code "897") (name "Net-(IC49-OUT0)") (class "Default")
      (node (ref "D772") (pin "C") (pinfunction "C_C") (pintype "passive"))
      (node (ref "IC49") (pin "5") (pinfunction "OUT0_5") (pintype "output"))
    )
    (net (code "898") (name "Net-(IC49-OUT1)") (class "Default")
      (node (ref "D773") (pin "C") (pinfunction "C_C") (pintype "passive"))
      (node (ref "IC49") (pin "6") (pinfunction "OUT1_6") (pintype "output"))
    )
    (net (code "899") (name "Net-(IC49-OUT2)") (class "Default")
      (node (ref "D774") (pin "C") (pinfunction "C_C") (pintype "passive"))
      (node (ref "IC49") (pin "7") (pinfunction "OUT2_7") (pintype "output"))
    )
    (net (code "900") (name "Net-(IC49-OUT3)") (class "Default")
      (node (ref "D775") (pin "C") (pinfunction "C_C") (pintype "passive"))
      (node (ref "IC49") (pin "8") (pinfunction "OUT3_8") (pintype "output"))
    )
    (net (code "901") (name "Net-(IC49-OUT4)") (class "Default")
      (node (ref "D776") (pin "C") (pinfunction "C_C") (pintype "passive"))
      (node (ref "IC49") (pin "9") (pinfunction "OUT4_9") (pintype "output"))
    )
    (net (code "902") (name "Net-(IC49-OUT5)") (class "Default")
      (node (ref "D777") (pin "C") (pinfunction "C_C") (pintype "passive"))
      (node (ref "IC49") (pin "10") (pinfunction "OUT5_10") (pintype "output"))
    )
    (net (code "903") (name "Net-(IC49-OUT6)") (class "Default")
      (node (ref "D778") (pin "C") (pinfunction "C_C") (pintype "passive"))
      (node (ref "IC49") (pin "11") (pinfunction "OUT6_11") (pintype "output"))
    )
    (net (code "904") (name "Net-(IC49-OUT7)") (class "Default")
      (node (ref "D779") (pin "C") (pinfunction "C_C") (pintype "passive"))
      (node (ref "IC49") (pin "12") (pinfunction "OUT7_12") (pintype "output"))
    )
    (net (code "905") (name "Net-(IC49-OUT8)") (class "Default")
      (node (ref "D843") (pin "C") (pinfunction "C_C") (pintype "passive"))
      (node (ref "IC49") (pin "13") (pinfunction "OUT8_13") (pintype "output"))
    )
    (net (code "906") (name "Net-(IC49-OUT9)") (class "Default")
      (node (ref "D842") (pin "C") (pinfunction "C_C") (pintype "passive"))
      (node (ref "IC49") (pin "14") (pinfunction "OUT9_14") (pintype "output"))
    )
    (net (code "907") (name "Net-(IC49-OUT10)") (class "Default")
      (node (ref "D841") (pin "C") (pinfunction "C_C") (pintype "passive"))
      (node (ref "IC49") (pin "15") (pinfunction "OUT10_15") (pintype "output"))
    )
    (net (code "908") (name "Net-(IC49-OUT11)") (class "Default")
      (node (ref "D840") (pin "C") (pinfunction "C_C") (pintype "passive"))
      (node (ref "IC49") (pin "16") (pinfunction "OUT11_16") (pintype "output"))
    )
    (net (code "909") (name "Net-(IC49-OUT12)") (class "Default")
      (node (ref "D839") (pin "C") (pinfunction "C_C") (pintype "passive"))
      (node (ref "IC49") (pin "17") (pinfunction "OUT12_17") (pintype "output"))
    )
    (net (code "910") (name "Net-(IC49-OUT13)") (class "Default")
      (node (ref "D838") (pin "C") (pinfunction "C_C") (pintype "passive"))
      (node (ref "IC49") (pin "18") (pinfunction "OUT13_18") (pintype "output"))
    )
    (net (code "911") (name "Net-(IC49-OUT14)") (class "Default")
      (node (ref "D837") (pin "C") (pinfunction "C_C") (pintype "passive"))
      (node (ref "IC49") (pin "19") (pinfunction "OUT14_19") (pintype "output"))
    )
    (net (code "912") (name "Net-(IC49-OUT15)") (class "Default")
      (node (ref "D836") (pin "C") (pinfunction "C_C") (pintype "passive"))
      (node (ref "IC49") (pin "20") (pinfunction "OUT15_20") (pintype "output"))
    )
    (net (code "913") (name "Net-(IC50-IREF)") (class "Default")
      (node (ref "IC50") (pin "23") (pinfunction "IREF_23") (pintype "bidirectional"))
      (node (ref "R61") (pin "1") (pinfunction "1_1") (pintype "passive"))
    )
    (net (code "914") (name "Net-(IC50-OUT0)") (class "Default")
      (node (ref "D780") (pin "C") (pinfunction "C_C") (pintype "passive"))
      (node (ref "IC50") (pin "5") (pinfunction "OUT0_5") (pintype "output"))
    )
    (net (code "915") (name "Net-(IC50-OUT1)") (class "Default")
      (node (ref "D781") (pin "C") (pinfunction "C_C") (pintype "passive"))
      (node (ref "IC50") (pin "6") (pinfunction "OUT1_6") (pintype "output"))
    )
    (net (code "916") (name "Net-(IC50-OUT2)") (class "Default")
      (node (ref "D782") (pin "C") (pinfunction "C_C") (pintype "passive"))
      (node (ref "IC50") (pin "7") (pinfunction "OUT2_7") (pintype "output"))
    )
    (net (code "917") (name "Net-(IC50-OUT3)") (class "Default")
      (node (ref "D783") (pin "C") (pinfunction "C_C") (pintype "passive"))
      (node (ref "IC50") (pin "8") (pinfunction "OUT3_8") (pintype "output"))
    )
    (net (code "918") (name "Net-(IC50-OUT4)") (class "Default")
      (node (ref "D784") (pin "C") (pinfunction "C_C") (pintype "passive"))
      (node (ref "IC50") (pin "9") (pinfunction "OUT4_9") (pintype "output"))
    )
    (net (code "919") (name "Net-(IC50-OUT5)") (class "Default")
      (node (ref "D785") (pin "C") (pinfunction "C_C") (pintype "passive"))
      (node (ref "IC50") (pin "10") (pinfunction "OUT5_10") (pintype "output"))
    )
    (net (code "920") (name "Net-(IC50-OUT6)") (class "Default")
      (node (ref "D786") (pin "C") (pinfunction "C_C") (pintype "passive"))
      (node (ref "IC50") (pin "11") (pinfunction "OUT6_11") (pintype "output"))
    )
    (net (code "921") (name "Net-(IC50-OUT7)") (class "Default")
      (node (ref "D787") (pin "C") (pinfunction "C_C") (pintype "passive"))
      (node (ref "IC50") (pin "12") (pinfunction "OUT7_12") (pintype "output"))
    )
    (net (code "922") (name "Net-(IC50-OUT8)") (class "Default")
      (node (ref "D851") (pin "C") (pinfunction "C_C") (pintype "passive"))
      (node (ref "IC50") (pin "13") (pinfunction "OUT8_13") (pintype "output"))
    )
    (net (code "923") (name "Net-(IC50-OUT9)") (class "Default")
      (node (ref "D850") (pin "C") (pinfunction "C_C") (pintype "passive"))
      (node (ref "IC50") (pin "14") (pinfunction "OUT9_14") (pintype "output"))
    )
    (net (code "924") (name "Net-(IC50-OUT10)") (class "Default")
      (node (ref "D849") (pin "C") (pinfunction "C_C") (pintype "passive"))
      (node (ref "IC50") (pin "15") (pinfunction "OUT10_15") (pintype "output"))
    )
    (net (code "925") (name "Net-(IC50-OUT11)") (class "Default")
      (node (ref "D848") (pin "C") (pinfunction "C_C") (pintype "passive"))
      (node (ref "IC50") (pin "16") (pinfunction "OUT11_16") (pintype "output"))
    )
    (net (code "926") (name "Net-(IC50-OUT12)") (class "Default")
      (node (ref "D847") (pin "C") (pinfunction "C_C") (pintype "passive"))
      (node (ref "IC50") (pin "17") (pinfunction "OUT12_17") (pintype "output"))
    )
    (net (code "927") (name "Net-(IC50-OUT13)") (class "Default")
      (node (ref "D846") (pin "C") (pinfunction "C_C") (pintype "passive"))
      (node (ref "IC50") (pin "18") (pinfunction "OUT13_18") (pintype "output"))
    )
    (net (code "928") (name "Net-(IC50-OUT14)") (class "Default")
      (node (ref "D845") (pin "C") (pinfunction "C_C") (pintype "passive"))
      (node (ref "IC50") (pin "19") (pinfunction "OUT14_19") (pintype "output"))
    )
    (net (code "929") (name "Net-(IC50-OUT15)") (class "Default")
      (node (ref "D844") (pin "C") (pinfunction "C_C") (pintype "passive"))
      (node (ref "IC50") (pin "20") (pinfunction "OUT15_20") (pintype "output"))
    )
    (net (code "930") (name "Net-(IC51-IREF)") (class "Default")
      (node (ref "IC51") (pin "23") (pinfunction "IREF_23") (pintype "bidirectional"))
      (node (ref "R62") (pin "1") (pinfunction "1_1") (pintype "passive"))
    )
    (net (code "931") (name "Net-(IC51-OUT0)") (class "Default")
      (node (ref "D788") (pin "C") (pinfunction "C_C") (pintype "passive"))
      (node (ref "IC51") (pin "5") (pinfunction "OUT0_5") (pintype "output"))
    )
    (net (code "932") (name "Net-(IC51-OUT1)") (class "Default")
      (node (ref "D789") (pin "C") (pinfunction "C_C") (pintype "passive"))
      (node (ref "IC51") (pin "6") (pinfunction "OUT1_6") (pintype "output"))
    )
    (net (code "933") (name "Net-(IC51-OUT2)") (class "Default")
      (node (ref "D790") (pin "C") (pinfunction "C_C") (pintype "passive"))
      (node (ref "IC51") (pin "7") (pinfunction "OUT2_7") (pintype "output"))
    )
    (net (code "934") (name "Net-(IC51-OUT3)") (class "Default")
      (node (ref "D791") (pin "C") (pinfunction "C_C") (pintype "passive"))
      (node (ref "IC51") (pin "8") (pinfunction "OUT3_8") (pintype "output"))
    )
    (net (code "935") (name "Net-(IC51-OUT4)") (class "Default")
      (node (ref "D792") (pin "C") (pinfunction "C_C") (pintype "passive"))
      (node (ref "IC51") (pin "9") (pinfunction "OUT4_9") (pintype "output"))
    )
    (net (code "936") (name "Net-(IC51-OUT5)") (class "Default")
      (node (ref "D793") (pin "C") (pinfunction "C_C") (pintype "passive"))
      (node (ref "IC51") (pin "10") (pinfunction "OUT5_10") (pintype "output"))
    )
    (net (code "937") (name "Net-(IC51-OUT6)") (class "Default")
      (node (ref "D794") (pin "C") (pinfunction "C_C") (pintype "passive"))
      (node (ref "IC51") (pin "11") (pinfunction "OUT6_11") (pintype "output"))
    )
    (net (code "938") (name "Net-(IC51-OUT7)") (class "Default")
      (node (ref "D795") (pin "C") (pinfunction "C_C") (pintype "passive"))
      (node (ref "IC51") (pin "12") (pinfunction "OUT7_12") (pintype "output"))
    )
    (net (code "939") (name "Net-(IC51-OUT8)") (class "Default")
      (node (ref "D859") (pin "C") (pinfunction "C_C") (pintype "passive"))
      (node (ref "IC51") (pin "13") (pinfunction "OUT8_13") (pintype "output"))
    )
    (net (code "940") (name "Net-(IC51-OUT9)") (class "Default")
      (node (ref "D858") (pin "C") (pinfunction "C_C") (pintype "passive"))
      (node (ref "IC51") (pin "14") (pinfunction "OUT9_14") (pintype "output"))
    )
    (net (code "941") (name "Net-(IC51-OUT10)") (class "Default")
      (node (ref "D857") (pin "C") (pinfunction "C_C") (pintype "passive"))
      (node (ref "IC51") (pin "15") (pinfunction "OUT10_15") (pintype "output"))
    )
    (net (code "942") (name "Net-(IC51-OUT11)") (class "Default")
      (node (ref "D856") (pin "C") (pinfunction "C_C") (pintype "passive"))
      (node (ref "IC51") (pin "16") (pinfunction "OUT11_16") (pintype "output"))
    )
    (net (code "943") (name "Net-(IC51-OUT12)") (class "Default")
      (node (ref "D855") (pin "C") (pinfunction "C_C") (pintype "passive"))
      (node (ref "IC51") (pin "17") (pinfunction "OUT12_17") (pintype "output"))
    )
    (net (code "944") (name "Net-(IC51-OUT13)") (class "Default")
      (node (ref "D854") (pin "C") (pinfunction "C_C") (pintype "passive"))
      (node (ref "IC51") (pin "18") (pinfunction "OUT13_18") (pintype "output"))
    )
    (net (code "945") (name "Net-(IC51-OUT14)") (class "Default")
      (node (ref "D853") (pin "C") (pinfunction "C_C") (pintype "passive"))
      (node (ref "IC51") (pin "19") (pinfunction "OUT14_19") (pintype "output"))
    )
    (net (code "946") (name "Net-(IC51-OUT15)") (class "Default")
      (node (ref "D852") (pin "C") (pinfunction "C_C") (pintype "passive"))
      (node (ref "IC51") (pin "20") (pinfunction "OUT15_20") (pintype "output"))
    )
    (net (code "947") (name "Net-(IC52-IREF)") (class "Default")
      (node (ref "IC52") (pin "23") (pinfunction "IREF_23") (pintype "bidirectional"))
      (node (ref "R63") (pin "1") (pinfunction "1_1") (pintype "passive"))
    )
    (net (code "948") (name "Net-(IC52-OUT0)") (class "Default")
      (node (ref "D796") (pin "C") (pinfunction "C_C") (pintype "passive"))
      (node (ref "IC52") (pin "5") (pinfunction "OUT0_5") (pintype "output"))
    )
    (net (code "949") (name "Net-(IC52-OUT1)") (class "Default")
      (node (ref "D797") (pin "C") (pinfunction "C_C") (pintype "passive"))
      (node (ref "IC52") (pin "6") (pinfunction "OUT1_6") (pintype "output"))
    )
    (net (code "950") (name "Net-(IC52-OUT2)") (class "Default")
      (node (ref "D798") (pin "C") (pinfunction "C_C") (pintype "passive"))
      (node (ref "IC52") (pin "7") (pinfunction "OUT2_7") (pintype "output"))
    )
    (net (code "951") (name "Net-(IC52-OUT3)") (class "Default")
      (node (ref "D799") (pin "C") (pinfunction "C_C") (pintype "passive"))
      (node (ref "IC52") (pin "8") (pinfunction "OUT3_8") (pintype "output"))
    )
    (net (code "952") (name "Net-(IC52-OUT4)") (class "Default")
      (node (ref "D800") (pin "C") (pinfunction "C_C") (pintype "passive"))
      (node (ref "IC52") (pin "9") (pinfunction "OUT4_9") (pintype "output"))
    )
    (net (code "953") (name "Net-(IC52-OUT5)") (class "Default")
      (node (ref "D801") (pin "C") (pinfunction "C_C") (pintype "passive"))
      (node (ref "IC52") (pin "10") (pinfunction "OUT5_10") (pintype "output"))
    )
    (net (code "954") (name "Net-(IC52-OUT6)") (class "Default")
      (node (ref "D802") (pin "C") (pinfunction "C_C") (pintype "passive"))
      (node (ref "IC52") (pin "11") (pinfunction "OUT6_11") (pintype "output"))
    )
    (net (code "955") (name "Net-(IC52-OUT7)") (class "Default")
      (node (ref "D803") (pin "C") (pinfunction "C_C") (pintype "passive"))
      (node (ref "IC52") (pin "12") (pinfunction "OUT7_12") (pintype "output"))
    )
    (net (code "956") (name "Net-(IC52-OUT8)") (class "Default")
      (node (ref "D867") (pin "C") (pinfunction "C_C") (pintype "passive"))
      (node (ref "IC52") (pin "13") (pinfunction "OUT8_13") (pintype "output"))
    )
    (net (code "957") (name "Net-(IC52-OUT9)") (class "Default")
      (node (ref "D866") (pin "C") (pinfunction "C_C") (pintype "passive"))
      (node (ref "IC52") (pin "14") (pinfunction "OUT9_14") (pintype "output"))
    )
    (net (code "958") (name "Net-(IC52-OUT10)") (class "Default")
      (node (ref "D865") (pin "C") (pinfunction "C_C") (pintype "passive"))
      (node (ref "IC52") (pin "15") (pinfunction "OUT10_15") (pintype "output"))
    )
    (net (code "959") (name "Net-(IC52-OUT11)") (class "Default")
      (node (ref "D864") (pin "C") (pinfunction "C_C") (pintype "passive"))
      (node (ref "IC52") (pin "16") (pinfunction "OUT11_16") (pintype "output"))
    )
    (net (code "960") (name "Net-(IC52-OUT12)") (class "Default")
      (node (ref "D863") (pin "C") (pinfunction "C_C") (pintype "passive"))
      (node (ref "IC52") (pin "17") (pinfunction "OUT12_17") (pintype "output"))
    )
    (net (code "961") (name "Net-(IC52-OUT13)") (class "Default")
      (node (ref "D862") (pin "C") (pinfunction "C_C") (pintype "passive"))
      (node (ref "IC52") (pin "18") (pinfunction "OUT13_18") (pintype "output"))
    )
    (net (code "962") (name "Net-(IC52-OUT14)") (class "Default")
      (node (ref "D861") (pin "C") (pinfunction "C_C") (pintype "passive"))
      (node (ref "IC52") (pin "19") (pinfunction "OUT14_19") (pintype "output"))
    )
    (net (code "963") (name "Net-(IC52-OUT15)") (class "Default")
      (node (ref "D860") (pin "C") (pinfunction "C_C") (pintype "passive"))
      (node (ref "IC52") (pin "20") (pinfunction "OUT15_20") (pintype "output"))
    )
    (net (code "964") (name "Net-(IC53-IREF)") (class "Default")
      (node (ref "IC53") (pin "23") (pinfunction "IREF_23") (pintype "bidirectional"))
      (node (ref "R64") (pin "1") (pinfunction "1_1") (pintype "passive"))
    )
    (net (code "965") (name "Net-(IC53-OUT0)") (class "Default")
      (node (ref "D804") (pin "C") (pinfunction "C_C") (pintype "passive"))
      (node (ref "IC53") (pin "5") (pinfunction "OUT0_5") (pintype "output"))
    )
    (net (code "966") (name "Net-(IC53-OUT1)") (class "Default")
      (node (ref "D805") (pin "C") (pinfunction "C_C") (pintype "passive"))
      (node (ref "IC53") (pin "6") (pinfunction "OUT1_6") (pintype "output"))
    )
    (net (code "967") (name "Net-(IC53-OUT2)") (class "Default")
      (node (ref "D806") (pin "C") (pinfunction "C_C") (pintype "passive"))
      (node (ref "IC53") (pin "7") (pinfunction "OUT2_7") (pintype "output"))
    )
    (net (code "968") (name "Net-(IC53-OUT3)") (class "Default")
      (node (ref "D807") (pin "C") (pinfunction "C_C") (pintype "passive"))
      (node (ref "IC53") (pin "8") (pinfunction "OUT3_8") (pintype "output"))
    )
    (net (code "969") (name "Net-(IC53-OUT4)") (class "Default")
      (node (ref "D808") (pin "C") (pinfunction "C_C") (pintype "passive"))
      (node (ref "IC53") (pin "9") (pinfunction "OUT4_9") (pintype "output"))
    )
    (net (code "970") (name "Net-(IC53-OUT5)") (class "Default")
      (node (ref "D809") (pin "C") (pinfunction "C_C") (pintype "passive"))
      (node (ref "IC53") (pin "10") (pinfunction "OUT5_10") (pintype "output"))
    )
    (net (code "971") (name "Net-(IC53-OUT6)") (class "Default")
      (node (ref "D810") (pin "C") (pinfunction "C_C") (pintype "passive"))
      (node (ref "IC53") (pin "11") (pinfunction "OUT6_11") (pintype "output"))
    )
    (net (code "972") (name "Net-(IC53-OUT7)") (class "Default")
      (node (ref "D811") (pin "C") (pinfunction "C_C") (pintype "passive"))
      (node (ref "IC53") (pin "12") (pinfunction "OUT7_12") (pintype "output"))
    )
    (net (code "973") (name "Net-(IC53-OUT8)") (class "Default")
      (node (ref "D875") (pin "C") (pinfunction "C_C") (pintype "passive"))
      (node (ref "IC53") (pin "13") (pinfunction "OUT8_13") (pintype "output"))
    )
    (net (code "974") (name "Net-(IC53-OUT9)") (class "Default")
      (node (ref "D874") (pin "C") (pinfunction "C_C") (pintype "passive"))
      (node (ref "IC53") (pin "14") (pinfunction "OUT9_14") (pintype "output"))
    )
    (net (code "975") (name "Net-(IC53-OUT10)") (class "Default")
      (node (ref "D873") (pin "C") (pinfunction "C_C") (pintype "passive"))
      (node (ref "IC53") (pin "15") (pinfunction "OUT10_15") (pintype "output"))
    )
    (net (code "976") (name "Net-(IC53-OUT11)") (class "Default")
      (node (ref "D872") (pin "C") (pinfunction "C_C") (pintype "passive"))
      (node (ref "IC53") (pin "16") (pinfunction "OUT11_16") (pintype "output"))
    )
    (net (code "977") (name "Net-(IC53-OUT12)") (class "Default")
      (node (ref "D871") (pin "C") (pinfunction "C_C") (pintype "passive"))
      (node (ref "IC53") (pin "17") (pinfunction "OUT12_17") (pintype "output"))
    )
    (net (code "978") (name "Net-(IC53-OUT13)") (class "Default")
      (node (ref "D870") (pin "C") (pinfunction "C_C") (pintype "passive"))
      (node (ref "IC53") (pin "18") (pinfunction "OUT13_18") (pintype "output"))
    )
    (net (code "979") (name "Net-(IC53-OUT14)") (class "Default")
      (node (ref "D869") (pin "C") (pinfunction "C_C") (pintype "passive"))
      (node (ref "IC53") (pin "19") (pinfunction "OUT14_19") (pintype "output"))
    )
    (net (code "980") (name "Net-(IC53-OUT15)") (class "Default")
      (node (ref "D868") (pin "C") (pinfunction "C_C") (pintype "passive"))
      (node (ref "IC53") (pin "20") (pinfunction "OUT15_20") (pintype "output"))
    )
    (net (code "981") (name "Net-(IC54-IREF)") (class "Default")
      (node (ref "IC54") (pin "23") (pinfunction "IREF_23") (pintype "bidirectional"))
      (node (ref "R65") (pin "1") (pinfunction "1_1") (pintype "passive"))
    )
    (net (code "982") (name "Net-(IC54-OUT0)") (class "Default")
      (node (ref "D812") (pin "C") (pinfunction "C_C") (pintype "passive"))
      (node (ref "IC54") (pin "5") (pinfunction "OUT0_5") (pintype "output"))
    )
    (net (code "983") (name "Net-(IC54-OUT1)") (class "Default")
      (node (ref "D813") (pin "C") (pinfunction "C_C") (pintype "passive"))
      (node (ref "IC54") (pin "6") (pinfunction "OUT1_6") (pintype "output"))
    )
    (net (code "984") (name "Net-(IC54-OUT2)") (class "Default")
      (node (ref "D814") (pin "C") (pinfunction "C_C") (pintype "passive"))
      (node (ref "IC54") (pin "7") (pinfunction "OUT2_7") (pintype "output"))
    )
    (net (code "985") (name "Net-(IC54-OUT3)") (class "Default")
      (node (ref "D815") (pin "C") (pinfunction "C_C") (pintype "passive"))
      (node (ref "IC54") (pin "8") (pinfunction "OUT3_8") (pintype "output"))
    )
    (net (code "986") (name "Net-(IC54-OUT4)") (class "Default")
      (node (ref "D816") (pin "C") (pinfunction "C_C") (pintype "passive"))
      (node (ref "IC54") (pin "9") (pinfunction "OUT4_9") (pintype "output"))
    )
    (net (code "987") (name "Net-(IC54-OUT5)") (class "Default")
      (node (ref "D817") (pin "C") (pinfunction "C_C") (pintype "passive"))
      (node (ref "IC54") (pin "10") (pinfunction "OUT5_10") (pintype "output"))
    )
    (net (code "988") (name "Net-(IC54-OUT6)") (class "Default")
      (node (ref "D818") (pin "C") (pinfunction "C_C") (pintype "passive"))
      (node (ref "IC54") (pin "11") (pinfunction "OUT6_11") (pintype "output"))
    )
    (net (code "989") (name "Net-(IC54-OUT7)") (class "Default")
      (node (ref "D819") (pin "C") (pinfunction "C_C") (pintype "passive"))
      (node (ref "IC54") (pin "12") (pinfunction "OUT7_12") (pintype "output"))
    )
    (net (code "990") (name "Net-(IC54-OUT8)") (class "Default")
      (node (ref "D883") (pin "C") (pinfunction "C_C") (pintype "passive"))
      (node (ref "IC54") (pin "13") (pinfunction "OUT8_13") (pintype "output"))
    )
    (net (code "991") (name "Net-(IC54-OUT9)") (class "Default")
      (node (ref "D882") (pin "C") (pinfunction "C_C") (pintype "passive"))
      (node (ref "IC54") (pin "14") (pinfunction "OUT9_14") (pintype "output"))
    )
    (net (code "992") (name "Net-(IC54-OUT10)") (class "Default")
      (node (ref "D881") (pin "C") (pinfunction "C_C") (pintype "passive"))
      (node (ref "IC54") (pin "15") (pinfunction "OUT10_15") (pintype "output"))
    )
    (net (code "993") (name "Net-(IC54-OUT11)") (class "Default")
      (node (ref "D880") (pin "C") (pinfunction "C_C") (pintype "passive"))
      (node (ref "IC54") (pin "16") (pinfunction "OUT11_16") (pintype "output"))
    )
    (net (code "994") (name "Net-(IC54-OUT12)") (class "Default")
      (node (ref "D879") (pin "C") (pinfunction "C_C") (pintype "passive"))
      (node (ref "IC54") (pin "17") (pinfunction "OUT12_17") (pintype "output"))
    )
    (net (code "995") (name "Net-(IC54-OUT13)") (class "Default")
      (node (ref "D878") (pin "C") (pinfunction "C_C") (pintype "passive"))
      (node (ref "IC54") (pin "18") (pinfunction "OUT13_18") (pintype "output"))
    )
    (net (code "996") (name "Net-(IC54-OUT14)") (class "Default")
      (node (ref "D877") (pin "C") (pinfunction "C_C") (pintype "passive"))
      (node (ref "IC54") (pin "19") (pinfunction "OUT14_19") (pintype "output"))
    )
    (net (code "997") (name "Net-(IC54-OUT15)") (class "Default")
      (node (ref "D876") (pin "C") (pinfunction "C_C") (pintype "passive"))
      (node (ref "IC54") (pin "20") (pinfunction "OUT15_20") (pintype "output"))
    )
    (net (code "998") (name "Net-(IC55-IREF)") (class "Default")
      (node (ref "IC55") (pin "23") (pinfunction "IREF_23") (pintype "bidirectional"))
      (node (ref "R66") (pin "1") (pinfunction "1_1") (pintype "passive"))
    )
    (net (code "999") (name "Net-(IC55-OUT0)") (class "Default")
      (node (ref "D820") (pin "C") (pinfunction "C_C") (pintype "passive"))
      (node (ref "IC55") (pin "5") (pinfunction "OUT0_5") (pintype "output"))
    )
    (net (code "1000") (name "Net-(IC55-OUT1)") (class "Default")
      (node (ref "D821") (pin "C") (pinfunction "C_C") (pintype "passive"))
      (node (ref "IC55") (pin "6") (pinfunction "OUT1_6") (pintype "output"))
    )
    (net (code "1001") (name "Net-(IC55-OUT2)") (class "Default")
      (node (ref "D822") (pin "C") (pinfunction "C_C") (pintype "passive"))
      (node (ref "IC55") (pin "7") (pinfunction "OUT2_7") (pintype "output"))
    )
    (net (code "1002") (name "Net-(IC55-OUT3)") (class "Default")
      (node (ref "D823") (pin "C") (pinfunction "C_C") (pintype "passive"))
      (node (ref "IC55") (pin "8") (pinfunction "OUT3_8") (pintype "output"))
    )
    (net (code "1003") (name "Net-(IC55-OUT4)") (class "Default")
      (node (ref "D824") (pin "C") (pinfunction "C_C") (pintype "passive"))
      (node (ref "IC55") (pin "9") (pinfunction "OUT4_9") (pintype "output"))
    )
    (net (code "1004") (name "Net-(IC55-OUT5)") (class "Default")
      (node (ref "D825") (pin "C") (pinfunction "C_C") (pintype "passive"))
      (node (ref "IC55") (pin "10") (pinfunction "OUT5_10") (pintype "output"))
    )
    (net (code "1005") (name "Net-(IC55-OUT6)") (class "Default")
      (node (ref "D826") (pin "C") (pinfunction "C_C") (pintype "passive"))
      (node (ref "IC55") (pin "11") (pinfunction "OUT6_11") (pintype "output"))
    )
    (net (code "1006") (name "Net-(IC55-OUT7)") (class "Default")
      (node (ref "D827") (pin "C") (pinfunction "C_C") (pintype "passive"))
      (node (ref "IC55") (pin "12") (pinfunction "OUT7_12") (pintype "output"))
    )
    (net (code "1007") (name "Net-(IC55-OUT8)") (class "Default")
      (node (ref "D891") (pin "C") (pinfunction "C_C") (pintype "passive"))
      (node (ref "IC55") (pin "13") (pinfunction "OUT8_13") (pintype "output"))
    )
    (net (code "1008") (name "Net-(IC55-OUT9)") (class "Default")
      (node (ref "D890") (pin "C") (pinfunction "C_C") (pintype "passive"))
      (node (ref "IC55") (pin "14") (pinfunction "OUT9_14") (pintype "output"))
    )
    (net (code "1009") (name "Net-(IC55-OUT10)") (class "Default")
      (node (ref "D889") (pin "C") (pinfunction "C_C") (pintype "passive"))
      (node (ref "IC55") (pin "15") (pinfunction "OUT10_15") (pintype "output"))
    )
    (net (code "1010") (name "Net-(IC55-OUT11)") (class "Default")
      (node (ref "D888") (pin "C") (pinfunction "C_C") (pintype "passive"))
      (node (ref "IC55") (pin "16") (pinfunction "OUT11_16") (pintype "output"))
    )
    (net (code "1011") (name "Net-(IC55-OUT12)") (class "Default")
      (node (ref "D887") (pin "C") (pinfunction "C_C") (pintype "passive"))
      (node (ref "IC55") (pin "17") (pinfunction "OUT12_17") (pintype "output"))
    )
    (net (code "1012") (name "Net-(IC55-OUT13)") (class "Default")
      (node (ref "D886") (pin "C") (pinfunction "C_C") (pintype "passive"))
      (node (ref "IC55") (pin "18") (pinfunction "OUT13_18") (pintype "output"))
    )
    (net (code "1013") (name "Net-(IC55-OUT14)") (class "Default")
      (node (ref "D885") (pin "C") (pinfunction "C_C") (pintype "passive"))
      (node (ref "IC55") (pin "19") (pinfunction "OUT14_19") (pintype "output"))
    )
    (net (code "1014") (name "Net-(IC55-OUT15)") (class "Default")
      (node (ref "D884") (pin "C") (pinfunction "C_C") (pintype "passive"))
      (node (ref "IC55") (pin "20") (pinfunction "OUT15_20") (pintype "output"))
    )
    (net (code "1015") (name "Net-(IC56-IREF)") (class "Default")
      (node (ref "IC56") (pin "23") (pinfunction "IREF_23") (pintype "bidirectional"))
      (node (ref "R67") (pin "1") (pinfunction "1_1") (pintype "passive"))
    )
    (net (code "1016") (name "Net-(IC56-OUT0)") (class "Default")
      (node (ref "D828") (pin "C") (pinfunction "C_C") (pintype "passive"))
      (node (ref "IC56") (pin "5") (pinfunction "OUT0_5") (pintype "output"))
    )
    (net (code "1017") (name "Net-(IC56-OUT1)") (class "Default")
      (node (ref "D829") (pin "C") (pinfunction "C_C") (pintype "passive"))
      (node (ref "IC56") (pin "6") (pinfunction "OUT1_6") (pintype "output"))
    )
    (net (code "1018") (name "Net-(IC56-OUT2)") (class "Default")
      (node (ref "D830") (pin "C") (pinfunction "C_C") (pintype "passive"))
      (node (ref "IC56") (pin "7") (pinfunction "OUT2_7") (pintype "output"))
    )
    (net (code "1019") (name "Net-(IC56-OUT3)") (class "Default")
      (node (ref "D831") (pin "C") (pinfunction "C_C") (pintype "passive"))
      (node (ref "IC56") (pin "8") (pinfunction "OUT3_8") (pintype "output"))
    )
    (net (code "1020") (name "Net-(IC56-OUT4)") (class "Default")
      (node (ref "D832") (pin "C") (pinfunction "C_C") (pintype "passive"))
      (node (ref "IC56") (pin "9") (pinfunction "OUT4_9") (pintype "output"))
    )
    (net (code "1021") (name "Net-(IC56-OUT5)") (class "Default")
      (node (ref "D833") (pin "C") (pinfunction "C_C") (pintype "passive"))
      (node (ref "IC56") (pin "10") (pinfunction "OUT5_10") (pintype "output"))
    )
    (net (code "1022") (name "Net-(IC56-OUT6)") (class "Default")
      (node (ref "D834") (pin "C") (pinfunction "C_C") (pintype "passive"))
      (node (ref "IC56") (pin "11") (pinfunction "OUT6_11") (pintype "output"))
    )
    (net (code "1023") (name "Net-(IC56-OUT7)") (class "Default")
      (node (ref "D835") (pin "C") (pinfunction "C_C") (pintype "passive"))
      (node (ref "IC56") (pin "12") (pinfunction "OUT7_12") (pintype "output"))
    )
    (net (code "1024") (name "Net-(IC56-OUT8)") (class "Default")
      (node (ref "D899") (pin "C") (pinfunction "C_C") (pintype "passive"))
      (node (ref "IC56") (pin "13") (pinfunction "OUT8_13") (pintype "output"))
    )
    (net (code "1025") (name "Net-(IC56-OUT9)") (class "Default")
      (node (ref "D898") (pin "C") (pinfunction "C_C") (pintype "passive"))
      (node (ref "IC56") (pin "14") (pinfunction "OUT9_14") (pintype "output"))
    )
    (net (code "1026") (name "Net-(IC56-OUT10)") (class "Default")
      (node (ref "D897") (pin "C") (pinfunction "C_C") (pintype "passive"))
      (node (ref "IC56") (pin "15") (pinfunction "OUT10_15") (pintype "output"))
    )
    (net (code "1027") (name "Net-(IC56-OUT11)") (class "Default")
      (node (ref "D896") (pin "C") (pinfunction "C_C") (pintype "passive"))
      (node (ref "IC56") (pin "16") (pinfunction "OUT11_16") (pintype "output"))
    )
    (net (code "1028") (name "Net-(IC56-OUT12)") (class "Default")
      (node (ref "D895") (pin "C") (pinfunction "C_C") (pintype "passive"))
      (node (ref "IC56") (pin "17") (pinfunction "OUT12_17") (pintype "output"))
    )
    (net (code "1029") (name "Net-(IC56-OUT13)") (class "Default")
      (node (ref "D894") (pin "C") (pinfunction "C_C") (pintype "passive"))
      (node (ref "IC56") (pin "18") (pinfunction "OUT13_18") (pintype "output"))
    )
    (net (code "1030") (name "Net-(IC56-OUT14)") (class "Default")
      (node (ref "D893") (pin "C") (pinfunction "C_C") (pintype "passive"))
      (node (ref "IC56") (pin "19") (pinfunction "OUT14_19") (pintype "output"))
    )
    (net (code "1031") (name "Net-(IC56-OUT15)") (class "Default")
      (node (ref "D892") (pin "C") (pinfunction "C_C") (pintype "passive"))
      (node (ref "IC56") (pin "20") (pinfunction "OUT15_20") (pintype "output"))
    )
    (net (code "1032") (name "Net-(IC57-IREF)") (class "Default")
      (node (ref "IC57") (pin "23") (pinfunction "IREF_23") (pintype "bidirectional"))
      (node (ref "R68") (pin "1") (pinfunction "1_1") (pintype "passive"))
    )
    (net (code "1033") (name "Net-(IC57-OUT0)") (class "Default")
      (node (ref "D900") (pin "C") (pinfunction "C_C") (pintype "passive"))
      (node (ref "IC57") (pin "5") (pinfunction "OUT0_5") (pintype "output"))
    )
    (net (code "1034") (name "Net-(IC57-OUT1)") (class "Default")
      (node (ref "D901") (pin "C") (pinfunction "C_C") (pintype "passive"))
      (node (ref "IC57") (pin "6") (pinfunction "OUT1_6") (pintype "output"))
    )
    (net (code "1035") (name "Net-(IC57-OUT2)") (class "Default")
      (node (ref "D902") (pin "C") (pinfunction "C_C") (pintype "passive"))
      (node (ref "IC57") (pin "7") (pinfunction "OUT2_7") (pintype "output"))
    )
    (net (code "1036") (name "Net-(IC57-OUT3)") (class "Default")
      (node (ref "D903") (pin "C") (pinfunction "C_C") (pintype "passive"))
      (node (ref "IC57") (pin "8") (pinfunction "OUT3_8") (pintype "output"))
    )
    (net (code "1037") (name "Net-(IC57-OUT4)") (class "Default")
      (node (ref "D904") (pin "C") (pinfunction "C_C") (pintype "passive"))
      (node (ref "IC57") (pin "9") (pinfunction "OUT4_9") (pintype "output"))
    )
    (net (code "1038") (name "Net-(IC57-OUT5)") (class "Default")
      (node (ref "D905") (pin "C") (pinfunction "C_C") (pintype "passive"))
      (node (ref "IC57") (pin "10") (pinfunction "OUT5_10") (pintype "output"))
    )
    (net (code "1039") (name "Net-(IC57-OUT6)") (class "Default")
      (node (ref "D906") (pin "C") (pinfunction "C_C") (pintype "passive"))
      (node (ref "IC57") (pin "11") (pinfunction "OUT6_11") (pintype "output"))
    )
    (net (code "1040") (name "Net-(IC57-OUT7)") (class "Default")
      (node (ref "D907") (pin "C") (pinfunction "C_C") (pintype "passive"))
      (node (ref "IC57") (pin "12") (pinfunction "OUT7_12") (pintype "output"))
    )
    (net (code "1041") (name "Net-(IC57-OUT8)") (class "Default")
      (node (ref "D971") (pin "C") (pinfunction "C_C") (pintype "passive"))
      (node (ref "IC57") (pin "13") (pinfunction "OUT8_13") (pintype "output"))
    )
    (net (code "1042") (name "Net-(IC57-OUT9)") (class "Default")
      (node (ref "D970") (pin "C") (pinfunction "C_C") (pintype "passive"))
      (node (ref "IC57") (pin "14") (pinfunction "OUT9_14") (pintype "output"))
    )
    (net (code "1043") (name "Net-(IC57-OUT10)") (class "Default")
      (node (ref "D969") (pin "C") (pinfunction "C_C") (pintype "passive"))
      (node (ref "IC57") (pin "15") (pinfunction "OUT10_15") (pintype "output"))
    )
    (net (code "1044") (name "Net-(IC57-OUT11)") (class "Default")
      (node (ref "D968") (pin "C") (pinfunction "C_C") (pintype "passive"))
      (node (ref "IC57") (pin "16") (pinfunction "OUT11_16") (pintype "output"))
    )
    (net (code "1045") (name "Net-(IC57-OUT12)") (class "Default")
      (node (ref "D967") (pin "C") (pinfunction "C_C") (pintype "passive"))
      (node (ref "IC57") (pin "17") (pinfunction "OUT12_17") (pintype "output"))
    )
    (net (code "1046") (name "Net-(IC57-OUT13)") (class "Default")
      (node (ref "D966") (pin "C") (pinfunction "C_C") (pintype "passive"))
      (node (ref "IC57") (pin "18") (pinfunction "OUT13_18") (pintype "output"))
    )
    (net (code "1047") (name "Net-(IC57-OUT14)") (class "Default")
      (node (ref "D965") (pin "C") (pinfunction "C_C") (pintype "passive"))
      (node (ref "IC57") (pin "19") (pinfunction "OUT14_19") (pintype "output"))
    )
    (net (code "1048") (name "Net-(IC57-OUT15)") (class "Default")
      (node (ref "D964") (pin "C") (pinfunction "C_C") (pintype "passive"))
      (node (ref "IC57") (pin "20") (pinfunction "OUT15_20") (pintype "output"))
    )
    (net (code "1049") (name "Net-(IC58-IREF)") (class "Default")
      (node (ref "IC58") (pin "23") (pinfunction "IREF_23") (pintype "bidirectional"))
      (node (ref "R69") (pin "1") (pinfunction "1_1") (pintype "passive"))
    )
    (net (code "1050") (name "Net-(IC58-OUT0)") (class "Default")
      (node (ref "D908") (pin "C") (pinfunction "C_C") (pintype "passive"))
      (node (ref "IC58") (pin "5") (pinfunction "OUT0_5") (pintype "output"))
    )
    (net (code "1051") (name "Net-(IC58-OUT1)") (class "Default")
      (node (ref "D909") (pin "C") (pinfunction "C_C") (pintype "passive"))
      (node (ref "IC58") (pin "6") (pinfunction "OUT1_6") (pintype "output"))
    )
    (net (code "1052") (name "Net-(IC58-OUT2)") (class "Default")
      (node (ref "D910") (pin "C") (pinfunction "C_C") (pintype "passive"))
      (node (ref "IC58") (pin "7") (pinfunction "OUT2_7") (pintype "output"))
    )
    (net (code "1053") (name "Net-(IC58-OUT3)") (class "Default")
      (node (ref "D911") (pin "C") (pinfunction "C_C") (pintype "passive"))
      (node (ref "IC58") (pin "8") (pinfunction "OUT3_8") (pintype "output"))
    )
    (net (code "1054") (name "Net-(IC58-OUT4)") (class "Default")
      (node (ref "D912") (pin "C") (pinfunction "C_C") (pintype "passive"))
      (node (ref "IC58") (pin "9") (pinfunction "OUT4_9") (pintype "output"))
    )
    (net (code "1055") (name "Net-(IC58-OUT5)") (class "Default")
      (node (ref "D913") (pin "C") (pinfunction "C_C") (pintype "passive"))
      (node (ref "IC58") (pin "10") (pinfunction "OUT5_10") (pintype "output"))
    )
    (net (code "1056") (name "Net-(IC58-OUT6)") (class "Default")
      (node (ref "D914") (pin "C") (pinfunction "C_C") (pintype "passive"))
      (node (ref "IC58") (pin "11") (pinfunction "OUT6_11") (pintype "output"))
    )
    (net (code "1057") (name "Net-(IC58-OUT7)") (class "Default")
      (node (ref "D915") (pin "C") (pinfunction "C_C") (pintype "passive"))
      (node (ref "IC58") (pin "12") (pinfunction "OUT7_12") (pintype "output"))
    )
    (net (code "1058") (name "Net-(IC58-OUT8)") (class "Default")
      (node (ref "D979") (pin "C") (pinfunction "C_C") (pintype "passive"))
      (node (ref "IC58") (pin "13") (pinfunction "OUT8_13") (pintype "output"))
    )
    (net (code "1059") (name "Net-(IC58-OUT9)") (class "Default")
      (node (ref "D978") (pin "C") (pinfunction "C_C") (pintype "passive"))
      (node (ref "IC58") (pin "14") (pinfunction "OUT9_14") (pintype "output"))
    )
    (net (code "1060") (name "Net-(IC58-OUT10)") (class "Default")
      (node (ref "D977") (pin "C") (pinfunction "C_C") (pintype "passive"))
      (node (ref "IC58") (pin "15") (pinfunction "OUT10_15") (pintype "output"))
    )
    (net (code "1061") (name "Net-(IC58-OUT11)") (class "Default")
      (node (ref "D976") (pin "C") (pinfunction "C_C") (pintype "passive"))
      (node (ref "IC58") (pin "16") (pinfunction "OUT11_16") (pintype "output"))
    )
    (net (code "1062") (name "Net-(IC58-OUT12)") (class "Default")
      (node (ref "D975") (pin "C") (pinfunction "C_C") (pintype "passive"))
      (node (ref "IC58") (pin "17") (pinfunction "OUT12_17") (pintype "output"))
    )
    (net (code "1063") (name "Net-(IC58-OUT13)") (class "Default")
      (node (ref "D974") (pin "C") (pinfunction "C_C") (pintype "passive"))
      (node (ref "IC58") (pin "18") (pinfunction "OUT13_18") (pintype "output"))
    )
    (net (code "1064") (name "Net-(IC58-OUT14)") (class "Default")
      (node (ref "D973") (pin "C") (pinfunction "C_C") (pintype "passive"))
      (node (ref "IC58") (pin "19") (pinfunction "OUT14_19") (pintype "output"))
    )
    (net (code "1065") (name "Net-(IC58-OUT15)") (class "Default")
      (node (ref "D972") (pin "C") (pinfunction "C_C") (pintype "passive"))
      (node (ref "IC58") (pin "20") (pinfunction "OUT15_20") (pintype "output"))
    )
    (net (code "1066") (name "Net-(IC59-IREF)") (class "Default")
      (node (ref "IC59") (pin "23") (pinfunction "IREF_23") (pintype "bidirectional"))
      (node (ref "R70") (pin "1") (pinfunction "1_1") (pintype "passive"))
    )
    (net (code "1067") (name "Net-(IC59-OUT0)") (class "Default")
      (node (ref "D916") (pin "C") (pinfunction "C_C") (pintype "passive"))
      (node (ref "IC59") (pin "5") (pinfunction "OUT0_5") (pintype "output"))
    )
    (net (code "1068") (name "Net-(IC59-OUT1)") (class "Default")
      (node (ref "D917") (pin "C") (pinfunction "C_C") (pintype "passive"))
      (node (ref "IC59") (pin "6") (pinfunction "OUT1_6") (pintype "output"))
    )
    (net (code "1069") (name "Net-(IC59-OUT2)") (class "Default")
      (node (ref "D918") (pin "C") (pinfunction "C_C") (pintype "passive"))
      (node (ref "IC59") (pin "7") (pinfunction "OUT2_7") (pintype "output"))
    )
    (net (code "1070") (name "Net-(IC59-OUT3)") (class "Default")
      (node (ref "D919") (pin "C") (pinfunction "C_C") (pintype "passive"))
      (node (ref "IC59") (pin "8") (pinfunction "OUT3_8") (pintype "output"))
    )
    (net (code "1071") (name "Net-(IC59-OUT4)") (class "Default")
      (node (ref "D920") (pin "C") (pinfunction "C_C") (pintype "passive"))
      (node (ref "IC59") (pin "9") (pinfunction "OUT4_9") (pintype "output"))
    )
    (net (code "1072") (name "Net-(IC59-OUT5)") (class "Default")
      (node (ref "D921") (pin "C") (pinfunction "C_C") (pintype "passive"))
      (node (ref "IC59") (pin "10") (pinfunction "OUT5_10") (pintype "output"))
    )
    (net (code "1073") (name "Net-(IC59-OUT6)") (class "Default")
      (node (ref "D922") (pin "C") (pinfunction "C_C") (pintype "passive"))
      (node (ref "IC59") (pin "11") (pinfunction "OUT6_11") (pintype "output"))
    )
    (net (code "1074") (name "Net-(IC59-OUT7)") (class "Default")
      (node (ref "D923") (pin "C") (pinfunction "C_C") (pintype "passive"))
      (node (ref "IC59") (pin "12") (pinfunction "OUT7_12") (pintype "output"))
    )
    (net (code "1075") (name "Net-(IC59-OUT8)") (class "Default")
      (node (ref "D987") (pin "C") (pinfunction "C_C") (pintype "passive"))
      (node (ref "IC59") (pin "13") (pinfunction "OUT8_13") (pintype "output"))
    )
    (net (code "1076") (name "Net-(IC59-OUT9)") (class "Default")
      (node (ref "D986") (pin "C") (pinfunction "C_C") (pintype "passive"))
      (node (ref "IC59") (pin "14") (pinfunction "OUT9_14") (pintype "output"))
    )
    (net (code "1077") (name "Net-(IC59-OUT10)") (class "Default")
      (node (ref "D985") (pin "C") (pinfunction "C_C") (pintype "passive"))
      (node (ref "IC59") (pin "15") (pinfunction "OUT10_15") (pintype "output"))
    )
    (net (code "1078") (name "Net-(IC59-OUT11)") (class "Default")
      (node (ref "D984") (pin "C") (pinfunction "C_C") (pintype "passive"))
      (node (ref "IC59") (pin "16") (pinfunction "OUT11_16") (pintype "output"))
    )
    (net (code "1079") (name "Net-(IC59-OUT12)") (class "Default")
      (node (ref "D983") (pin "C") (pinfunction "C_C") (pintype "passive"))
      (node (ref "IC59") (pin "17") (pinfunction "OUT12_17") (pintype "output"))
    )
    (net (code "1080") (name "Net-(IC59-OUT13)") (class "Default")
      (node (ref "D982") (pin "C") (pinfunction "C_C") (pintype "passive"))
      (node (ref "IC59") (pin "18") (pinfunction "OUT13_18") (pintype "output"))
    )
    (net (code "1081") (name "Net-(IC59-OUT14)") (class "Default")
      (node (ref "D981") (pin "C") (pinfunction "C_C") (pintype "passive"))
      (node (ref "IC59") (pin "19") (pinfunction "OUT14_19") (pintype "output"))
    )
    (net (code "1082") (name "Net-(IC59-OUT15)") (class "Default")
      (node (ref "D980") (pin "C") (pinfunction "C_C") (pintype "passive"))
      (node (ref "IC59") (pin "20") (pinfunction "OUT15_20") (pintype "output"))
    )
    (net (code "1083") (name "Net-(IC60-IREF)") (class "Default")
      (node (ref "IC60") (pin "23") (pinfunction "IREF_23") (pintype "bidirectional"))
      (node (ref "R71") (pin "1") (pinfunction "1_1") (pintype "passive"))
    )
    (net (code "1084") (name "Net-(IC60-OUT0)") (class "Default")
      (node (ref "D924") (pin "C") (pinfunction "C_C") (pintype "passive"))
      (node (ref "IC60") (pin "5") (pinfunction "OUT0_5") (pintype "output"))
    )
    (net (code "1085") (name "Net-(IC60-OUT1)") (class "Default")
      (node (ref "D925") (pin "C") (pinfunction "C_C") (pintype "passive"))
      (node (ref "IC60") (pin "6") (pinfunction "OUT1_6") (pintype "output"))
    )
    (net (code "1086") (name "Net-(IC60-OUT2)") (class "Default")
      (node (ref "D926") (pin "C") (pinfunction "C_C") (pintype "passive"))
      (node (ref "IC60") (pin "7") (pinfunction "OUT2_7") (pintype "output"))
    )
    (net (code "1087") (name "Net-(IC60-OUT3)") (class "Default")
      (node (ref "D927") (pin "C") (pinfunction "C_C") (pintype "passive"))
      (node (ref "IC60") (pin "8") (pinfunction "OUT3_8") (pintype "output"))
    )
    (net (code "1088") (name "Net-(IC60-OUT4)") (class "Default")
      (node (ref "D928") (pin "C") (pinfunction "C_C") (pintype "passive"))
      (node (ref "IC60") (pin "9") (pinfunction "OUT4_9") (pintype "output"))
    )
    (net (code "1089") (name "Net-(IC60-OUT5)") (class "Default")
      (node (ref "D929") (pin "C") (pinfunction "C_C") (pintype "passive"))
      (node (ref "IC60") (pin "10") (pinfunction "OUT5_10") (pintype "output"))
    )
    (net (code "1090") (name "Net-(IC60-OUT6)") (class "Default")
      (node (ref "D930") (pin "C") (pinfunction "C_C") (pintype "passive"))
      (node (ref "IC60") (pin "11") (pinfunction "OUT6_11") (pintype "output"))
    )
    (net (code "1091") (name "Net-(IC60-OUT7)") (class "Default")
      (node (ref "D931") (pin "C") (pinfunction "C_C") (pintype "passive"))
      (node (ref "IC60") (pin "12") (pinfunction "OUT7_12") (pintype "output"))
    )
    (net (code "1092") (name "Net-(IC60-OUT8)") (class "Default")
      (node (ref "D995") (pin "C") (pinfunction "C_C") (pintype "passive"))
      (node (ref "IC60") (pin "13") (pinfunction "OUT8_13") (pintype "output"))
    )
    (net (code "1093") (name "Net-(IC60-OUT9)") (class "Default")
      (node (ref "D994") (pin "C") (pinfunction "C_C") (pintype "passive"))
      (node (ref "IC60") (pin "14") (pinfunction "OUT9_14") (pintype "output"))
    )
    (net (code "1094") (name "Net-(IC60-OUT10)") (class "Default")
      (node (ref "D993") (pin "C") (pinfunction "C_C") (pintype "passive"))
      (node (ref "IC60") (pin "15") (pinfunction "OUT10_15") (pintype "output"))
    )
    (net (code "1095") (name "Net-(IC60-OUT11)") (class "Default")
      (node (ref "D992") (pin "C") (pinfunction "C_C") (pintype "passive"))
      (node (ref "IC60") (pin "16") (pinfunction "OUT11_16") (pintype "output"))
    )
    (net (code "1096") (name "Net-(IC60-OUT12)") (class "Default")
      (node (ref "D991") (pin "C") (pinfunction "C_C") (pintype "passive"))
      (node (ref "IC60") (pin "17") (pinfunction "OUT12_17") (pintype "output"))
    )
    (net (code "1097") (name "Net-(IC60-OUT13)") (class "Default")
      (node (ref "D990") (pin "C") (pinfunction "C_C") (pintype "passive"))
      (node (ref "IC60") (pin "18") (pinfunction "OUT13_18") (pintype "output"))
    )
    (net (code "1098") (name "Net-(IC60-OUT14)") (class "Default")
      (node (ref "D989") (pin "C") (pinfunction "C_C") (pintype "passive"))
      (node (ref "IC60") (pin "19") (pinfunction "OUT14_19") (pintype "output"))
    )
    (net (code "1099") (name "Net-(IC60-OUT15)") (class "Default")
      (node (ref "D988") (pin "C") (pinfunction "C_C") (pintype "passive"))
      (node (ref "IC60") (pin "20") (pinfunction "OUT15_20") (pintype "output"))
    )
    (net (code "1100") (name "Net-(IC61-IREF)") (class "Default")
      (node (ref "IC61") (pin "23") (pinfunction "IREF_23") (pintype "bidirectional"))
      (node (ref "R72") (pin "1") (pinfunction "1_1") (pintype "passive"))
    )
    (net (code "1101") (name "Net-(IC61-OUT0)") (class "Default")
      (node (ref "D932") (pin "C") (pinfunction "C_C") (pintype "passive"))
      (node (ref "IC61") (pin "5") (pinfunction "OUT0_5") (pintype "output"))
    )
    (net (code "1102") (name "Net-(IC61-OUT1)") (class "Default")
      (node (ref "D933") (pin "C") (pinfunction "C_C") (pintype "passive"))
      (node (ref "IC61") (pin "6") (pinfunction "OUT1_6") (pintype "output"))
    )
    (net (code "1103") (name "Net-(IC61-OUT2)") (class "Default")
      (node (ref "D934") (pin "C") (pinfunction "C_C") (pintype "passive"))
      (node (ref "IC61") (pin "7") (pinfunction "OUT2_7") (pintype "output"))
    )
    (net (code "1104") (name "Net-(IC61-OUT3)") (class "Default")
      (node (ref "D935") (pin "C") (pinfunction "C_C") (pintype "passive"))
      (node (ref "IC61") (pin "8") (pinfunction "OUT3_8") (pintype "output"))
    )
    (net (code "1105") (name "Net-(IC61-OUT4)") (class "Default")
      (node (ref "D936") (pin "C") (pinfunction "C_C") (pintype "passive"))
      (node (ref "IC61") (pin "9") (pinfunction "OUT4_9") (pintype "output"))
    )
    (net (code "1106") (name "Net-(IC61-OUT5)") (class "Default")
      (node (ref "D937") (pin "C") (pinfunction "C_C") (pintype "passive"))
      (node (ref "IC61") (pin "10") (pinfunction "OUT5_10") (pintype "output"))
    )
    (net (code "1107") (name "Net-(IC61-OUT6)") (class "Default")
      (node (ref "D938") (pin "C") (pinfunction "C_C") (pintype "passive"))
      (node (ref "IC61") (pin "11") (pinfunction "OUT6_11") (pintype "output"))
    )
    (net (code "1108") (name "Net-(IC61-OUT7)") (class "Default")
      (node (ref "D939") (pin "C") (pinfunction "C_C") (pintype "passive"))
      (node (ref "IC61") (pin "12") (pinfunction "OUT7_12") (pintype "output"))
    )
    (net (code "1109") (name "Net-(IC61-OUT8)") (class "Default")
      (node (ref "D1003") (pin "C") (pinfunction "C_C") (pintype "passive"))
      (node (ref "IC61") (pin "13") (pinfunction "OUT8_13") (pintype "output"))
    )
    (net (code "1110") (name "Net-(IC61-OUT9)") (class "Default")
      (node (ref "D1002") (pin "C") (pinfunction "C_C") (pintype "passive"))
      (node (ref "IC61") (pin "14") (pinfunction "OUT9_14") (pintype "output"))
    )
    (net (code "1111") (name "Net-(IC61-OUT10)") (class "Default")
      (node (ref "D1001") (pin "C") (pinfunction "C_C") (pintype "passive"))
      (node (ref "IC61") (pin "15") (pinfunction "OUT10_15") (pintype "output"))
    )
    (net (code "1112") (name "Net-(IC61-OUT11)") (class "Default")
      (node (ref "D1000") (pin "C") (pinfunction "C_C") (pintype "passive"))
      (node (ref "IC61") (pin "16") (pinfunction "OUT11_16") (pintype "output"))
    )
    (net (code "1113") (name "Net-(IC61-OUT12)") (class "Default")
      (node (ref "D999") (pin "C") (pinfunction "C_C") (pintype "passive"))
      (node (ref "IC61") (pin "17") (pinfunction "OUT12_17") (pintype "output"))
    )
    (net (code "1114") (name "Net-(IC61-OUT13)") (class "Default")
      (node (ref "D998") (pin "C") (pinfunction "C_C") (pintype "passive"))
      (node (ref "IC61") (pin "18") (pinfunction "OUT13_18") (pintype "output"))
    )
    (net (code "1115") (name "Net-(IC61-OUT14)") (class "Default")
      (node (ref "D997") (pin "C") (pinfunction "C_C") (pintype "passive"))
      (node (ref "IC61") (pin "19") (pinfunction "OUT14_19") (pintype "output"))
    )
    (net (code "1116") (name "Net-(IC61-OUT15)") (class "Default")
      (node (ref "D996") (pin "C") (pinfunction "C_C") (pintype "passive"))
      (node (ref "IC61") (pin "20") (pinfunction "OUT15_20") (pintype "output"))
    )
    (net (code "1117") (name "Net-(IC62-IREF)") (class "Default")
      (node (ref "IC62") (pin "23") (pinfunction "IREF_23") (pintype "bidirectional"))
      (node (ref "R73") (pin "1") (pinfunction "1_1") (pintype "passive"))
    )
    (net (code "1118") (name "Net-(IC62-OUT0)") (class "Default")
      (node (ref "D940") (pin "C") (pinfunction "C_C") (pintype "passive"))
      (node (ref "IC62") (pin "5") (pinfunction "OUT0_5") (pintype "output"))
    )
    (net (code "1119") (name "Net-(IC62-OUT1)") (class "Default")
      (node (ref "D941") (pin "C") (pinfunction "C_C") (pintype "passive"))
      (node (ref "IC62") (pin "6") (pinfunction "OUT1_6") (pintype "output"))
    )
    (net (code "1120") (name "Net-(IC62-OUT2)") (class "Default")
      (node (ref "D942") (pin "C") (pinfunction "C_C") (pintype "passive"))
      (node (ref "IC62") (pin "7") (pinfunction "OUT2_7") (pintype "output"))
    )
    (net (code "1121") (name "Net-(IC62-OUT3)") (class "Default")
      (node (ref "D943") (pin "C") (pinfunction "C_C") (pintype "passive"))
      (node (ref "IC62") (pin "8") (pinfunction "OUT3_8") (pintype "output"))
    )
    (net (code "1122") (name "Net-(IC62-OUT4)") (class "Default")
      (node (ref "D944") (pin "C") (pinfunction "C_C") (pintype "passive"))
      (node (ref "IC62") (pin "9") (pinfunction "OUT4_9") (pintype "output"))
    )
    (net (code "1123") (name "Net-(IC62-OUT5)") (class "Default")
      (node (ref "D945") (pin "C") (pinfunction "C_C") (pintype "passive"))
      (node (ref "IC62") (pin "10") (pinfunction "OUT5_10") (pintype "output"))
    )
    (net (code "1124") (name "Net-(IC62-OUT6)") (class "Default")
      (node (ref "D946") (pin "C") (pinfunction "C_C") (pintype "passive"))
      (node (ref "IC62") (pin "11") (pinfunction "OUT6_11") (pintype "output"))
    )
    (net (code "1125") (name "Net-(IC62-OUT7)") (class "Default")
      (node (ref "D947") (pin "C") (pinfunction "C_C") (pintype "passive"))
      (node (ref "IC62") (pin "12") (pinfunction "OUT7_12") (pintype "output"))
    )
    (net (code "1126") (name "Net-(IC62-OUT8)") (class "Default")
      (node (ref "D1011") (pin "C") (pinfunction "C_C") (pintype "passive"))
      (node (ref "IC62") (pin "13") (pinfunction "OUT8_13") (pintype "output"))
    )
    (net (code "1127") (name "Net-(IC62-OUT9)") (class "Default")
      (node (ref "D1010") (pin "C") (pinfunction "C_C") (pintype "passive"))
      (node (ref "IC62") (pin "14") (pinfunction "OUT9_14") (pintype "output"))
    )
    (net (code "1128") (name "Net-(IC62-OUT10)") (class "Default")
      (node (ref "D1009") (pin "C") (pinfunction "C_C") (pintype "passive"))
      (node (ref "IC62") (pin "15") (pinfunction "OUT10_15") (pintype "output"))
    )
    (net (code "1129") (name "Net-(IC62-OUT11)") (class "Default")
      (node (ref "D1008") (pin "C") (pinfunction "C_C") (pintype "passive"))
      (node (ref "IC62") (pin "16") (pinfunction "OUT11_16") (pintype "output"))
    )
    (net (code "1130") (name "Net-(IC62-OUT12)") (class "Default")
      (node (ref "D1007") (pin "C") (pinfunction "C_C") (pintype "passive"))
      (node (ref "IC62") (pin "17") (pinfunction "OUT12_17") (pintype "output"))
    )
    (net (code "1131") (name "Net-(IC62-OUT13)") (class "Default")
      (node (ref "D1006") (pin "C") (pinfunction "C_C") (pintype "passive"))
      (node (ref "IC62") (pin "18") (pinfunction "OUT13_18") (pintype "output"))
    )
    (net (code "1132") (name "Net-(IC62-OUT14)") (class "Default")
      (node (ref "D1005") (pin "C") (pinfunction "C_C") (pintype "passive"))
      (node (ref "IC62") (pin "19") (pinfunction "OUT14_19") (pintype "output"))
    )
    (net (code "1133") (name "Net-(IC62-OUT15)") (class "Default")
      (node (ref "D1004") (pin "C") (pinfunction "C_C") (pintype "passive"))
      (node (ref "IC62") (pin "20") (pinfunction "OUT15_20") (pintype "output"))
    )
    (net (code "1134") (name "Net-(IC63-IREF)") (class "Default")
      (node (ref "IC63") (pin "23") (pinfunction "IREF_23") (pintype "bidirectional"))
      (node (ref "R74") (pin "1") (pinfunction "1_1") (pintype "passive"))
    )
    (net (code "1135") (name "Net-(IC63-OUT0)") (class "Default")
      (node (ref "D948") (pin "C") (pinfunction "C_C") (pintype "passive"))
      (node (ref "IC63") (pin "5") (pinfunction "OUT0_5") (pintype "output"))
    )
    (net (code "1136") (name "Net-(IC63-OUT1)") (class "Default")
      (node (ref "D949") (pin "C") (pinfunction "C_C") (pintype "passive"))
      (node (ref "IC63") (pin "6") (pinfunction "OUT1_6") (pintype "output"))
    )
    (net (code "1137") (name "Net-(IC63-OUT2)") (class "Default")
      (node (ref "D950") (pin "C") (pinfunction "C_C") (pintype "passive"))
      (node (ref "IC63") (pin "7") (pinfunction "OUT2_7") (pintype "output"))
    )
    (net (code "1138") (name "Net-(IC63-OUT3)") (class "Default")
      (node (ref "D951") (pin "C") (pinfunction "C_C") (pintype "passive"))
      (node (ref "IC63") (pin "8") (pinfunction "OUT3_8") (pintype "output"))
    )
    (net (code "1139") (name "Net-(IC63-OUT4)") (class "Default")
      (node (ref "D952") (pin "C") (pinfunction "C_C") (pintype "passive"))
      (node (ref "IC63") (pin "9") (pinfunction "OUT4_9") (pintype "output"))
    )
    (net (code "1140") (name "Net-(IC63-OUT5)") (class "Default")
      (node (ref "D953") (pin "C") (pinfunction "C_C") (pintype "passive"))
      (node (ref "IC63") (pin "10") (pinfunction "OUT5_10") (pintype "output"))
    )
    (net (code "1141") (name "Net-(IC63-OUT6)") (class "Default")
      (node (ref "D954") (pin "C") (pinfunction "C_C") (pintype "passive"))
      (node (ref "IC63") (pin "11") (pinfunction "OUT6_11") (pintype "output"))
    )
    (net (code "1142") (name "Net-(IC63-OUT7)") (class "Default")
      (node (ref "D955") (pin "C") (pinfunction "C_C") (pintype "passive"))
      (node (ref "IC63") (pin "12") (pinfunction "OUT7_12") (pintype "output"))
    )
    (net (code "1143") (name "Net-(IC63-OUT8)") (class "Default")
      (node (ref "D1019") (pin "C") (pinfunction "C_C") (pintype "passive"))
      (node (ref "IC63") (pin "13") (pinfunction "OUT8_13") (pintype "output"))
    )
    (net (code "1144") (name "Net-(IC63-OUT9)") (class "Default")
      (node (ref "D1018") (pin "C") (pinfunction "C_C") (pintype "passive"))
      (node (ref "IC63") (pin "14") (pinfunction "OUT9_14") (pintype "output"))
    )
    (net (code "1145") (name "Net-(IC63-OUT10)") (class "Default")
      (node (ref "D1017") (pin "C") (pinfunction "C_C") (pintype "passive"))
      (node (ref "IC63") (pin "15") (pinfunction "OUT10_15") (pintype "output"))
    )
    (net (code "1146") (name "Net-(IC63-OUT11)") (class "Default")
      (node (ref "D1016") (pin "C") (pinfunction "C_C") (pintype "passive"))
      (node (ref "IC63") (pin "16") (pinfunction "OUT11_16") (pintype "output"))
    )
    (net (code "1147") (name "Net-(IC63-OUT12)") (class "Default")
      (node (ref "D1015") (pin "C") (pinfunction "C_C") (pintype "passive"))
      (node (ref "IC63") (pin "17") (pinfunction "OUT12_17") (pintype "output"))
    )
    (net (code "1148") (name "Net-(IC63-OUT13)") (class "Default")
      (node (ref "D1014") (pin "C") (pinfunction "C_C") (pintype "passive"))
      (node (ref "IC63") (pin "18") (pinfunction "OUT13_18") (pintype "output"))
    )
    (net (code "1149") (name "Net-(IC63-OUT14)") (class "Default")
      (node (ref "D1013") (pin "C") (pinfunction "C_C") (pintype "passive"))
      (node (ref "IC63") (pin "19") (pinfunction "OUT14_19") (pintype "output"))
    )
    (net (code "1150") (name "Net-(IC63-OUT15)") (class "Default")
      (node (ref "D1012") (pin "C") (pinfunction "C_C") (pintype "passive"))
      (node (ref "IC63") (pin "20") (pinfunction "OUT15_20") (pintype "output"))
    )
    (net (code "1151") (name "Net-(IC64-IREF)") (class "Default")
      (node (ref "IC64") (pin "23") (pinfunction "IREF_23") (pintype "bidirectional"))
      (node (ref "R75") (pin "1") (pinfunction "1_1") (pintype "passive"))
    )
    (net (code "1152") (name "Net-(IC64-OUT0)") (class "Default")
      (node (ref "D956") (pin "C") (pinfunction "C_C") (pintype "passive"))
      (node (ref "IC64") (pin "5") (pinfunction "OUT0_5") (pintype "output"))
    )
    (net (code "1153") (name "Net-(IC64-OUT1)") (class "Default")
      (node (ref "D957") (pin "C") (pinfunction "C_C") (pintype "passive"))
      (node (ref "IC64") (pin "6") (pinfunction "OUT1_6") (pintype "output"))
    )
    (net (code "1154") (name "Net-(IC64-OUT2)") (class "Default")
      (node (ref "D958") (pin "C") (pinfunction "C_C") (pintype "passive"))
      (node (ref "IC64") (pin "7") (pinfunction "OUT2_7") (pintype "output"))
    )
    (net (code "1155") (name "Net-(IC64-OUT3)") (class "Default")
      (node (ref "D959") (pin "C") (pinfunction "C_C") (pintype "passive"))
      (node (ref "IC64") (pin "8") (pinfunction "OUT3_8") (pintype "output"))
    )
    (net (code "1156") (name "Net-(IC64-OUT4)") (class "Default")
      (node (ref "D960") (pin "C") (pinfunction "C_C") (pintype "passive"))
      (node (ref "IC64") (pin "9") (pinfunction "OUT4_9") (pintype "output"))
    )
    (net (code "1157") (name "Net-(IC64-OUT5)") (class "Default")
      (node (ref "D961") (pin "C") (pinfunction "C_C") (pintype "passive"))
      (node (ref "IC64") (pin "10") (pinfunction "OUT5_10") (pintype "output"))
    )
    (net (code "1158") (name "Net-(IC64-OUT6)") (class "Default")
      (node (ref "D962") (pin "C") (pinfunction "C_C") (pintype "passive"))
      (node (ref "IC64") (pin "11") (pinfunction "OUT6_11") (pintype "output"))
    )
    (net (code "1159") (name "Net-(IC64-OUT7)") (class "Default")
      (node (ref "D963") (pin "C") (pinfunction "C_C") (pintype "passive"))
      (node (ref "IC64") (pin "12") (pinfunction "OUT7_12") (pintype "output"))
    )
    (net (code "1160") (name "Net-(IC64-OUT8)") (class "Default")
      (node (ref "D1027") (pin "C") (pinfunction "C_C") (pintype "passive"))
      (node (ref "IC64") (pin "13") (pinfunction "OUT8_13") (pintype "output"))
    )
    (net (code "1161") (name "Net-(IC64-OUT9)") (class "Default")
      (node (ref "D1026") (pin "C") (pinfunction "C_C") (pintype "passive"))
      (node (ref "IC64") (pin "14") (pinfunction "OUT9_14") (pintype "output"))
    )
    (net (code "1162") (name "Net-(IC64-OUT10)") (class "Default")
      (node (ref "D1025") (pin "C") (pinfunction "C_C") (pintype "passive"))
      (node (ref "IC64") (pin "15") (pinfunction "OUT10_15") (pintype "output"))
    )
    (net (code "1163") (name "Net-(IC64-OUT11)") (class "Default")
      (node (ref "D1024") (pin "C") (pinfunction "C_C") (pintype "passive"))
      (node (ref "IC64") (pin "16") (pinfunction "OUT11_16") (pintype "output"))
    )
    (net (code "1164") (name "Net-(IC64-OUT12)") (class "Default")
      (node (ref "D1023") (pin "C") (pinfunction "C_C") (pintype "passive"))
      (node (ref "IC64") (pin "17") (pinfunction "OUT12_17") (pintype "output"))
    )
    (net (code "1165") (name "Net-(IC64-OUT13)") (class "Default")
      (node (ref "D1022") (pin "C") (pinfunction "C_C") (pintype "passive"))
      (node (ref "IC64") (pin "18") (pinfunction "OUT13_18") (pintype "output"))
    )
    (net (code "1166") (name "Net-(IC64-OUT14)") (class "Default")
      (node (ref "D1021") (pin "C") (pinfunction "C_C") (pintype "passive"))
      (node (ref "IC64") (pin "19") (pinfunction "OUT14_19") (pintype "output"))
    )
    (net (code "1167") (name "Net-(IC64-OUT15)") (class "Default")
      (node (ref "D1020") (pin "C") (pinfunction "C_C") (pintype "passive"))
      (node (ref "IC64") (pin "20") (pinfunction "OUT15_20") (pintype "output"))
    )
    (net (code "1168") (name "Net-(J2----VCC)") (class "Default")
      (node (ref "F1") (pin "1") (pinfunction "1_1") (pintype "passive"))
      (node (ref "J2") (pin "1") (pinfunction "---VCC_1") (pintype "power_in"))
    )
    (net (code "1169") (name "Net-(JP2-Pad2)") (class "Default")
      (node (ref "JP2") (pin "2") (pinfunction "2_2") (pintype "passive"))
      (node (ref "R8") (pin "2") (pinfunction "2_2") (pintype "passive"))
    )
    (net (code "1170") (name "Net-(JP2-Pad3)") (class "Default")
      (node (ref "JP2") (pin "3") (pinfunction "3_3") (pintype "passive"))
      (node (ref "R9") (pin "2") (pinfunction "2_2") (pintype "passive"))
    )
    (net (code "1171") (name "Net-(U2-IO19)") (class "Default")
      (node (ref "R5") (pin "1") (pinfunction "1_1") (pintype "passive"))
      (node (ref "U2") (pin "22") (pinfunction "IO19_22") (pintype "bidirectional"))
    )
    (net (code "1172") (name "Net-(U2-IO20)") (class "Default")
      (node (ref "R4") (pin "1") (pinfunction "1_1") (pintype "passive"))
      (node (ref "U2") (pin "23") (pinfunction "IO20_23") (pintype "bidirectional"))
    )
    (net (code "1173") (name "Net-(U5-FB)") (class "Default")
      (node (ref "R6") (pin "1") (pinfunction "1_1") (pintype "passive"))
      (node (ref "R7") (pin "2") (pinfunction "2_2") (pintype "passive"))
      (node (ref "U5") (pin "2") (pinfunction "FB_2") (pintype "input"))
    )
    (net (code "1174") (name "Net-(U5-VC)") (class "Default")
      (node (ref "C5") (pin "2") (pinfunction "2_2") (pintype "passive"))
      (node (ref "U5") (pin "4") (pinfunction "VC_4") (pintype "passive"))
    )
    (net (code "1175") (name "RESET") (class "Default")
      (node (ref "C3") (pin "2") (pinfunction "2_2") (pintype "passive"))
      (node (ref "R2") (pin "1") (pinfunction "1_1") (pintype "passive"))
      (node (ref "SW1") (pin "2") (pinfunction "2_2") (pintype "passive"))
      (node (ref "U2") (pin "41") (pinfunction "EN_41") (pintype "input"))
    )
    (net (code "1176") (name "RXD") (class "Default")
      (node (ref "R9") (pin "1") (pinfunction "1_1") (pintype "passive"))
      (node (ref "U2") (pin "38") (pinfunction "RXD0_38") (pintype "bidirectional"))
    )
    (net (code "1177") (name "SD_CLK") (class "Default")
      (node (ref "J1") (pin "5") (pinfunction "CLK_5") (pintype "bidirectional"))
      (node (ref "U2") (pin "15") (pinfunction "IO12_15") (pintype "bidirectional"))
    )
    (net (code "1178") (name "SD_CS") (class "Default")
      (node (ref "J1") (pin "2") (pinfunction "CD_DAT3_CS_2") (pintype "bidirectional"))
      (node (ref "U2") (pin "13") (pinfunction "IO10_13") (pintype "bidirectional"))
    )
    (net (code "1179") (name "SD_MISO") (class "Default")
      (node (ref "J1") (pin "7") (pinfunction "DAT0_DO_7") (pintype "bidirectional"))
      (node (ref "R10") (pin "1") (pinfunction "1_1") (pintype "passive"))
      (node (ref "U2") (pin "16") (pinfunction "IO13_16") (pintype "bidirectional"))
    )
    (net (code "1180") (name "SD_MOSI") (class "Default")
      (node (ref "J1") (pin "3") (pinfunction "CMD_DIN_3") (pintype "bidirectional"))
      (node (ref "U2") (pin "14") (pinfunction "IO11_14") (pintype "bidirectional"))
    )
    (net (code "1181") (name "TXD") (class "Default")
      (node (ref "R8") (pin "1") (pinfunction "1_1") (pintype "passive"))
      (node (ref "U2") (pin "37") (pinfunction "TXD0_37") (pintype "bidirectional"))
    )
    (net (code "1182") (name "VIN") (class "Default")
      (node (ref "C10") (pin "+") (pinfunction "+_+") (pintype "passive"))
      (node (ref "C5") (pin "1") (pinfunction "1_1") (pintype "passive"))
      (node (ref "C7") (pin "1") (pinfunction "1_1") (pintype "passive"))
      (node (ref "JP1") (pin "2") (pinfunction "2_2") (pintype "passive"))
      (node (ref "U5") (pin "5") (pinfunction "VIN_5") (pintype "power_in"))
    )
    (net (code "1183") (name "unconnected-(J1-DAT1-Pad8)") (class "Default")
      (node (ref "J1") (pin "8") (pinfunction "DAT1_8") (pintype "bidirectional"))
    )
    (net (code "1184") (name "unconnected-(J1-DAT2-Pad1)") (class "Default")
      (node (ref "J1") (pin "1") (pinfunction "DAT2_1") (pintype "bidirectional"))
    )
    (net (code "1185") (name "unconnected-(J1-PadCD)") (class "Default")
      (node (ref "J1") (pin "CD") (pinfunction "CD_CD") (pintype "bidirectional"))
    )
    (net (code "1186") (name "unconnected-(U2-IO2-Pad5)") (class "Default")
      (node (ref "U2") (pin "5") (pinfunction "IO2_5") (pintype "bidirectional"))
    )
    (net (code "1187") (name "unconnected-(U2-IO3-Pad6)") (class "Default")
      (node (ref "U2") (pin "6") (pinfunction "IO3_6") (pintype "bidirectional"))
    )
    (net (code "1188") (name "unconnected-(U2-IO4-Pad7)") (class "Default")
      (node (ref "U2") (pin "7") (pinfunction "IO4_7") (pintype "bidirectional"))
    )
    (net (code "1189") (name "unconnected-(U2-IO5-Pad8)") (class "Default")
      (node (ref "U2") (pin "8") (pinfunction "IO5_8") (pintype "bidirectional"))
    )
    (net (code "1190") (name "unconnected-(U2-IO6-Pad9)") (class "Default")
      (node (ref "U2") (pin "9") (pinfunction "IO6_9") (pintype "bidirectional"))
    )
    (net (code "1191") (name "unconnected-(U2-IO7-Pad10)") (class "Default")
      (node (ref "U2") (pin "10") (pinfunction "IO7_10") (pintype "bidirectional"))
    )
    (net (code "1192") (name "unconnected-(U2-IO8-Pad11)") (class "Default")
      (node (ref "U2") (pin "11") (pinfunction "IO8_11") (pintype "bidirectional"))
    )
    (net (code "1193") (name "unconnected-(U2-IO9-Pad12)") (class "Default")
      (node (ref "U2") (pin "12") (pinfunction "IO9_12") (pintype "bidirectional"))
    )
    (net (code "1194") (name "unconnected-(U2-IO14-Pad17)") (class "Default")
      (node (ref "U2") (pin "17") (pinfunction "IO14_17") (pintype "bidirectional"))
    )
    (net (code "1195") (name "unconnected-(U2-IO15-Pad18)") (class "Default")
      (node (ref "U2") (pin "18") (pinfunction "IO15_18") (pintype "bidirectional"))
    )
    (net (code "1196") (name "unconnected-(U2-IO16-Pad19)") (class "Default")
      (node (ref "U2") (pin "19") (pinfunction "IO16_19") (pintype "bidirectional"))
    )
    (net (code "1197") (name "unconnected-(U2-IO17-Pad20)") (class "Default")
      (node (ref "U2") (pin "20") (pinfunction "IO17_20") (pintype "bidirectional"))
    )
    (net (code "1198") (name "unconnected-(U2-IO18-Pad21)") (class "Default")
      (node (ref "U2") (pin "21") (pinfunction "IO18_21") (pintype "bidirectional"))
    )
    (net (code "1199") (name "unconnected-(U2-IO33-Pad27)") (class "Default")
      (node (ref "U2") (pin "27") (pinfunction "IO33_27") (pintype "bidirectional"))
    )
    (net (code "1200") (name "unconnected-(U2-IO38-Pad32)") (class "Default")
      (node (ref "U2") (pin "32") (pinfunction "IO38_32") (pintype "bidirectional"))
    )
    (net (code "1201") (name "unconnected-(U2-IO45-Pad39)") (class "Default")
      (node (ref "U2") (pin "39") (pinfunction "IO45_39") (pintype "bidirectional"))
    )
    (net (code "1202") (name "unconnected-(U2-IO46-Pad40)") (class "Default")
      (node (ref "U2") (pin "40") (pinfunction "IO46_40") (pintype "input"))
    )
    (net (code "1203") (name "unconnected-(U3-NC-Pad4)") (class "Default")
      (node (ref "U3") (pin "4") (pinfunction "NC_4") (pintype "bidirectional"))
    )
    (net (code "1204") (name "{slash}26") (class "Default")
      (node (ref "U2") (pin "25") (pinfunction "IO26_25") (pintype "bidirectional"))
    )
    (net (code "1205") (name "{slash}34") (class "Default")
      (node (ref "U2") (pin "28") (pinfunction "IO34_28") (pintype "input"))
    )
    (net (code "1206") (name "{slash}39") (class "Default")
      (node (ref "U2") (pin "33") (pinfunction "IO39_33") (pintype "bidirectional"))
    )
    (net (code "1207") (name "{slash}42") (class "Default")
      (node (ref "U2") (pin "36") (pinfunction "IO42_36") (pintype "bidirectional"))
    )
    (net (code "1208") (name "{slash}IO21") (class "Default")
      (node (ref "U2") (pin "24") (pinfunction "IO21_24") (pintype "bidirectional"))
    )
    (net (code "1209") (name "{slash}LE1") (class "Default")
      (node (ref "IC1") (pin "4") (pinfunction "LAT_4") (pintype "input"))
      (node (ref "IC10") (pin "4") (pinfunction "LAT_4") (pintype "input"))
      (node (ref "IC11") (pin "4") (pinfunction "LAT_4") (pintype "input"))
      (node (ref "IC12") (pin "4") (pinfunction "LAT_4") (pintype "input"))
      (node (ref "IC13") (pin "4") (pinfunction "LAT_4") (pintype "input"))
      (node (ref "IC14") (pin "4") (pinfunction "LAT_4") (pintype "input"))
      (node (ref "IC15") (pin "4") (pinfunction "LAT_4") (pintype "input"))
      (node (ref "IC16") (pin "4") (pinfunction "LAT_4") (pintype "input"))
      (node (ref "IC17") (pin "4") (pinfunction "LAT_4") (pintype "input"))
      (node (ref "IC18") (pin "4") (pinfunction "LAT_4") (pintype "input"))
      (node (ref "IC19") (pin "4") (pinfunction "LAT_4") (pintype "input"))
      (node (ref "IC2") (pin "4") (pinfunction "LAT_4") (pintype "input"))
      (node (ref "IC20") (pin "4") (pinfunction "LAT_4") (pintype "input"))
      (node (ref "IC21") (pin "4") (pinfunction "LAT_4") (pintype "input"))
      (node (ref "IC22") (pin "4") (pinfunction "LAT_4") (pintype "input"))
      (node (ref "IC23") (pin "4") (pinfunction "LAT_4") (pintype "input"))
      (node (ref "IC24") (pin "4") (pinfunction "LAT_4") (pintype "input"))
      (node (ref "IC25") (pin "4") (pinfunction "LAT_4") (pintype "input"))
      (node (ref "IC26") (pin "4") (pinfunction "LAT_4") (pintype "input"))
      (node (ref "IC27") (pin "4") (pinfunction "LAT_4") (pintype "input"))
      (node (ref "IC28") (pin "4") (pinfunction "LAT_4") (pintype "input"))
      (node (ref "IC29") (pin "4") (pinfunction "LAT_4") (pintype "input"))
      (node (ref "IC3") (pin "4") (pinfunction "LAT_4") (pintype "input"))
      (node (ref "IC30") (pin "4") (pinfunction "LAT_4") (pintype "input"))
      (node (ref "IC31") (pin "4") (pinfunction "LAT_4") (pintype "input"))
      (node (ref "IC32") (pin "4") (pinfunction "LAT_4") (pintype "input"))
      (node (ref "IC4") (pin "4") (pinfunction "LAT_4") (pintype "input"))
      (node (ref "IC5") (pin "4") (pinfunction "LAT_4") (pintype "input"))
      (node (ref "IC6") (pin "4") (pinfunction "LAT_4") (pintype "input"))
      (node (ref "IC7") (pin "4") (pinfunction "LAT_4") (pintype "input"))
      (node (ref "IC8") (pin "4") (pinfunction "LAT_4") (pintype "input"))
      (node (ref "IC9") (pin "4") (pinfunction "LAT_4") (pintype "input"))
      (node (ref "U2") (pin "35") (pinfunction "IO41_35") (pintype "bidirectional"))
    )
    (net (code "1210") (name "{slash}LE2") (class "Default")
      (node (ref "IC33") (pin "4") (pinfunction "LAT_4") (pintype "input"))
      (node (ref "IC34") (pin "4") (pinfunction "LAT_4") (pintype "input"))
      (node (ref "IC35") (pin "4") (pinfunction "LAT_4") (pintype "input"))
      (node (ref "IC36") (pin "4") (pinfunction "LAT_4") (pintype "input"))
      (node (ref "IC37") (pin "4") (pinfunction "LAT_4") (pintype "input"))
      (node (ref "IC38") (pin "4") (pinfunction "LAT_4") (pintype "input"))
      (node (ref "IC39") (pin "4") (pinfunction "LAT_4") (pintype "input"))
      (node (ref "IC40") (pin "4") (pinfunction "LAT_4") (pintype "input"))
      (node (ref "IC41") (pin "4") (pinfunction "LAT_4") (pintype "input"))
      (node (ref "IC42") (pin "4") (pinfunction "LAT_4") (pintype "input"))
      (node (ref "IC43") (pin "4") (pinfunction "LAT_4") (pintype "input"))
      (node (ref "IC44") (pin "4") (pinfunction "LAT_4") (pintype "input"))
      (node (ref "IC45") (pin "4") (pinfunction "LAT_4") (pintype "input"))
      (node (ref "IC46") (pin "4") (pinfunction "LAT_4") (pintype "input"))
      (node (ref "IC47") (pin "4") (pinfunction "LAT_4") (pintype "input"))
      (node (ref "IC48") (pin "4") (pinfunction "LAT_4") (pintype "input"))
      (node (ref "IC49") (pin "4") (pinfunction "LAT_4") (pintype "input"))
      (node (ref "IC50") (pin "4") (pinfunction "LAT_4") (pintype "input"))
      (node (ref "IC51") (pin "4") (pinfunction "LAT_4") (pintype "input"))
      (node (ref "IC52") (pin "4") (pinfunction "LAT_4") (pintype "input"))
      (node (ref "IC53") (pin "4") (pinfunction "LAT_4") (pintype "input"))
      (node (ref "IC54") (pin "4") (pinfunction "LAT_4") (pintype "input"))
      (node (ref "IC55") (pin "4") (pinfunction "LAT_4") (pintype "input"))
      (node (ref "IC56") (pin "4") (pinfunction "LAT_4") (pintype "input"))
      (node (ref "IC57") (pin "4") (pinfunction "LAT_4") (pintype "input"))
      (node (ref "IC58") (pin "4") (pinfunction "LAT_4") (pintype "input"))
      (node (ref "IC59") (pin "4") (pinfunction "LAT_4") (pintype "input"))
      (node (ref "IC60") (pin "4") (pinfunction "LAT_4") (pintype "input"))
      (node (ref "IC61") (pin "4") (pinfunction "LAT_4") (pintype "input"))
      (node (ref "IC62") (pin "4") (pinfunction "LAT_4") (pintype "input"))
      (node (ref "IC63") (pin "4") (pinfunction "LAT_4") (pintype "input"))
      (node (ref "IC64") (pin "4") (pinfunction "LAT_4") (pintype "input"))
      (node (ref "P1") (pin "2") (pinfunction "2_2") (pintype "bidirectional"))
      (node (ref "P2") (pin "2") (pinfunction "2_2") (pintype "bidirectional"))
      (node (ref "U2") (pin "34") (pinfunction "IO40_34") (pintype "bidirectional"))
    )
  )
)
